# UCirKitBreadboardWithEverything3.net
KiCad netlist of a schematic drawn in EAGLE
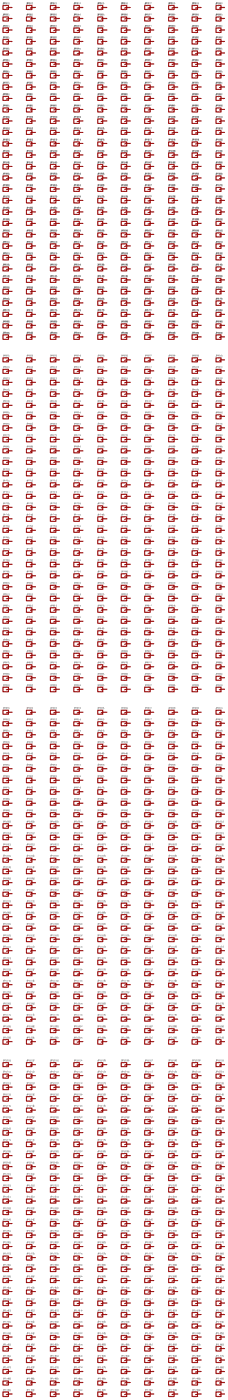
[diagram p0: schematic, sheet 1, overview]
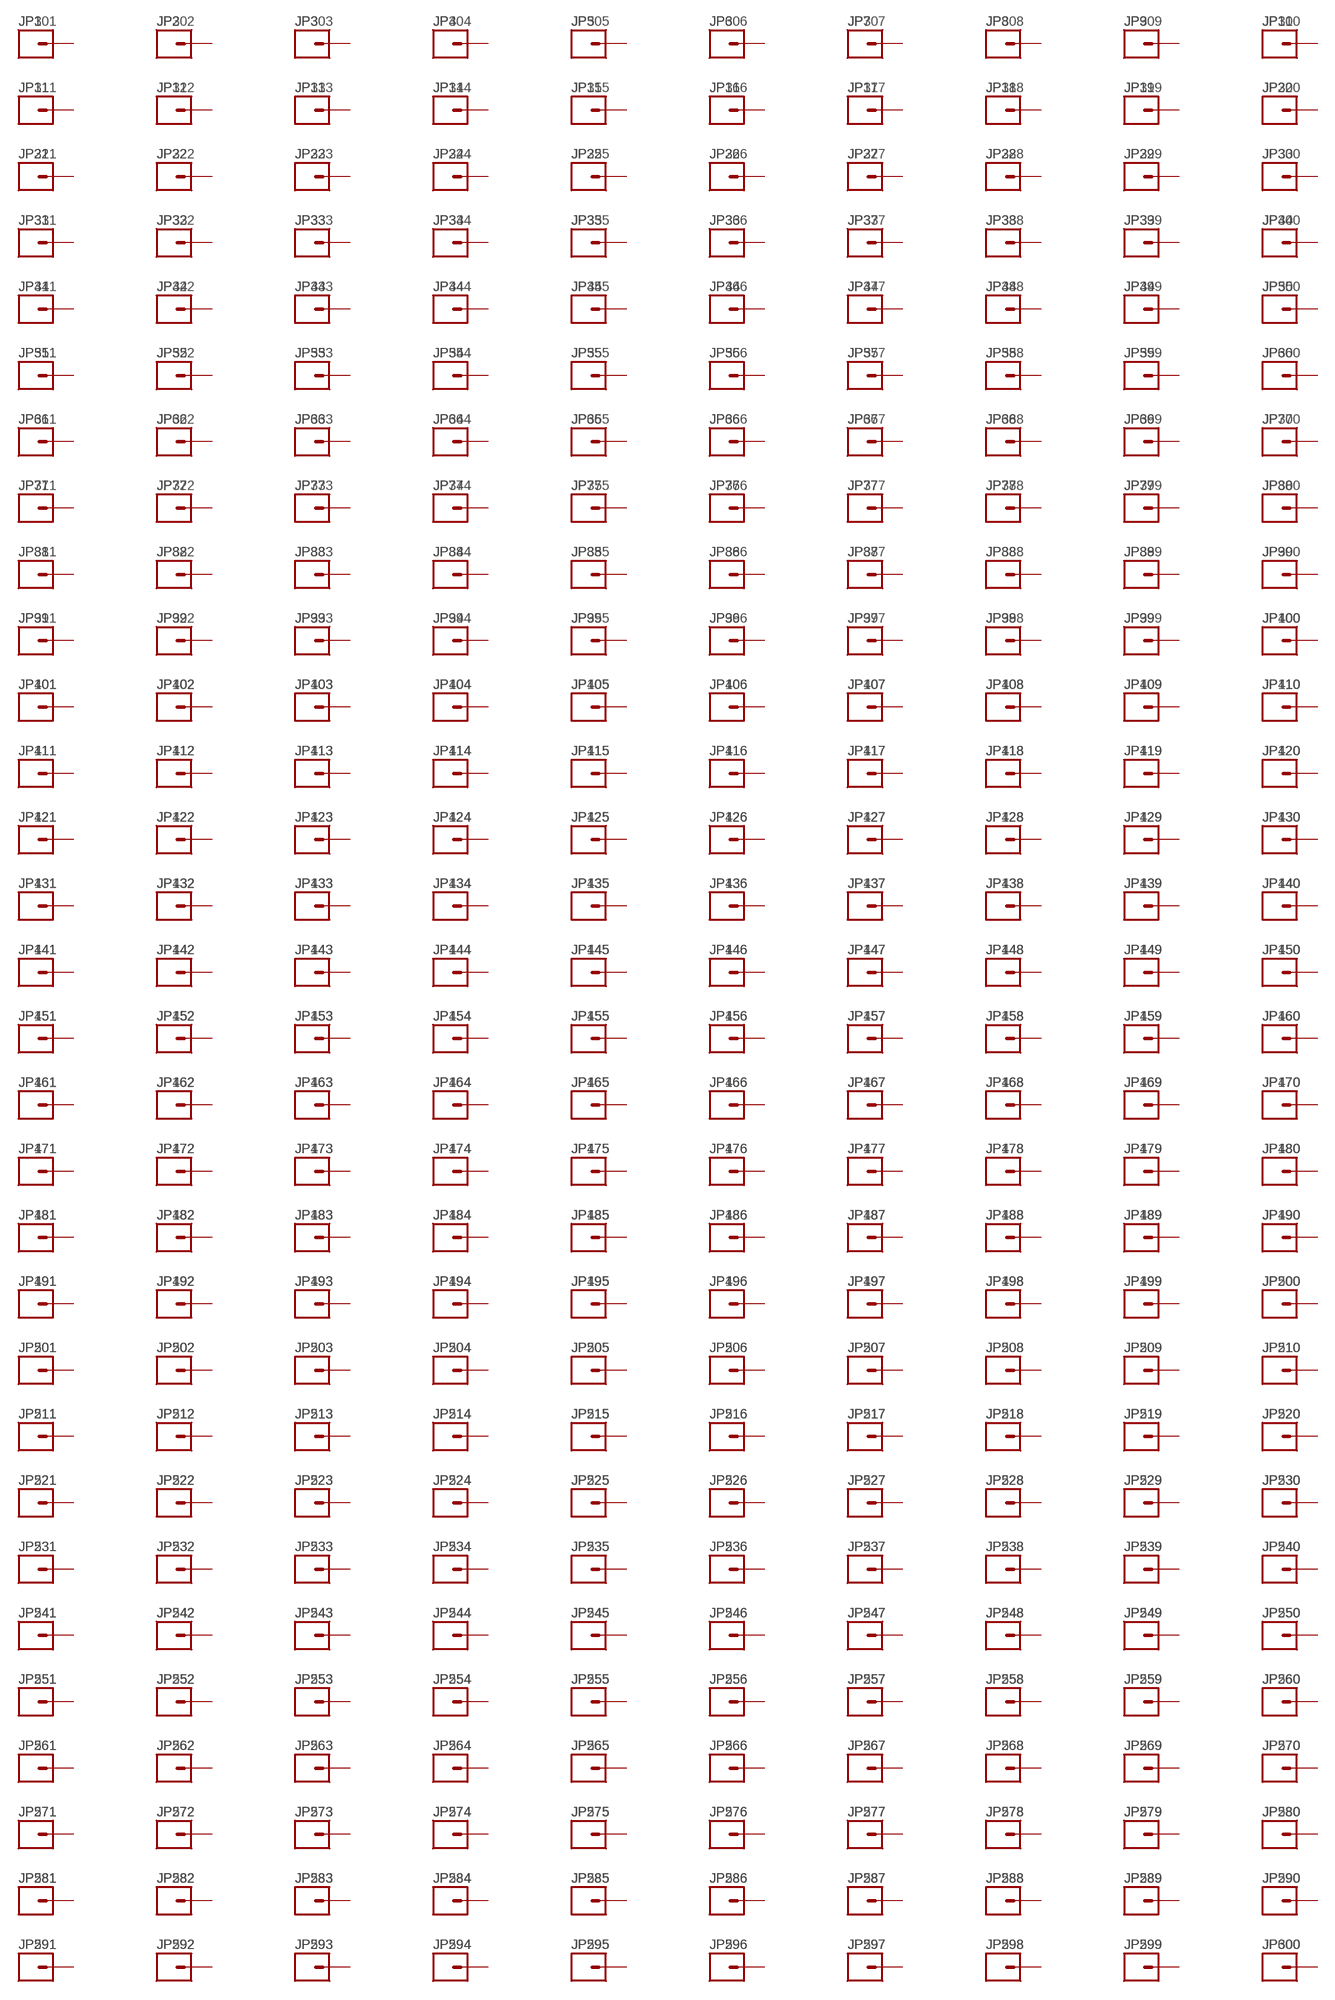
[diagram p1: schematic, sheet 1, part 1 of 4]
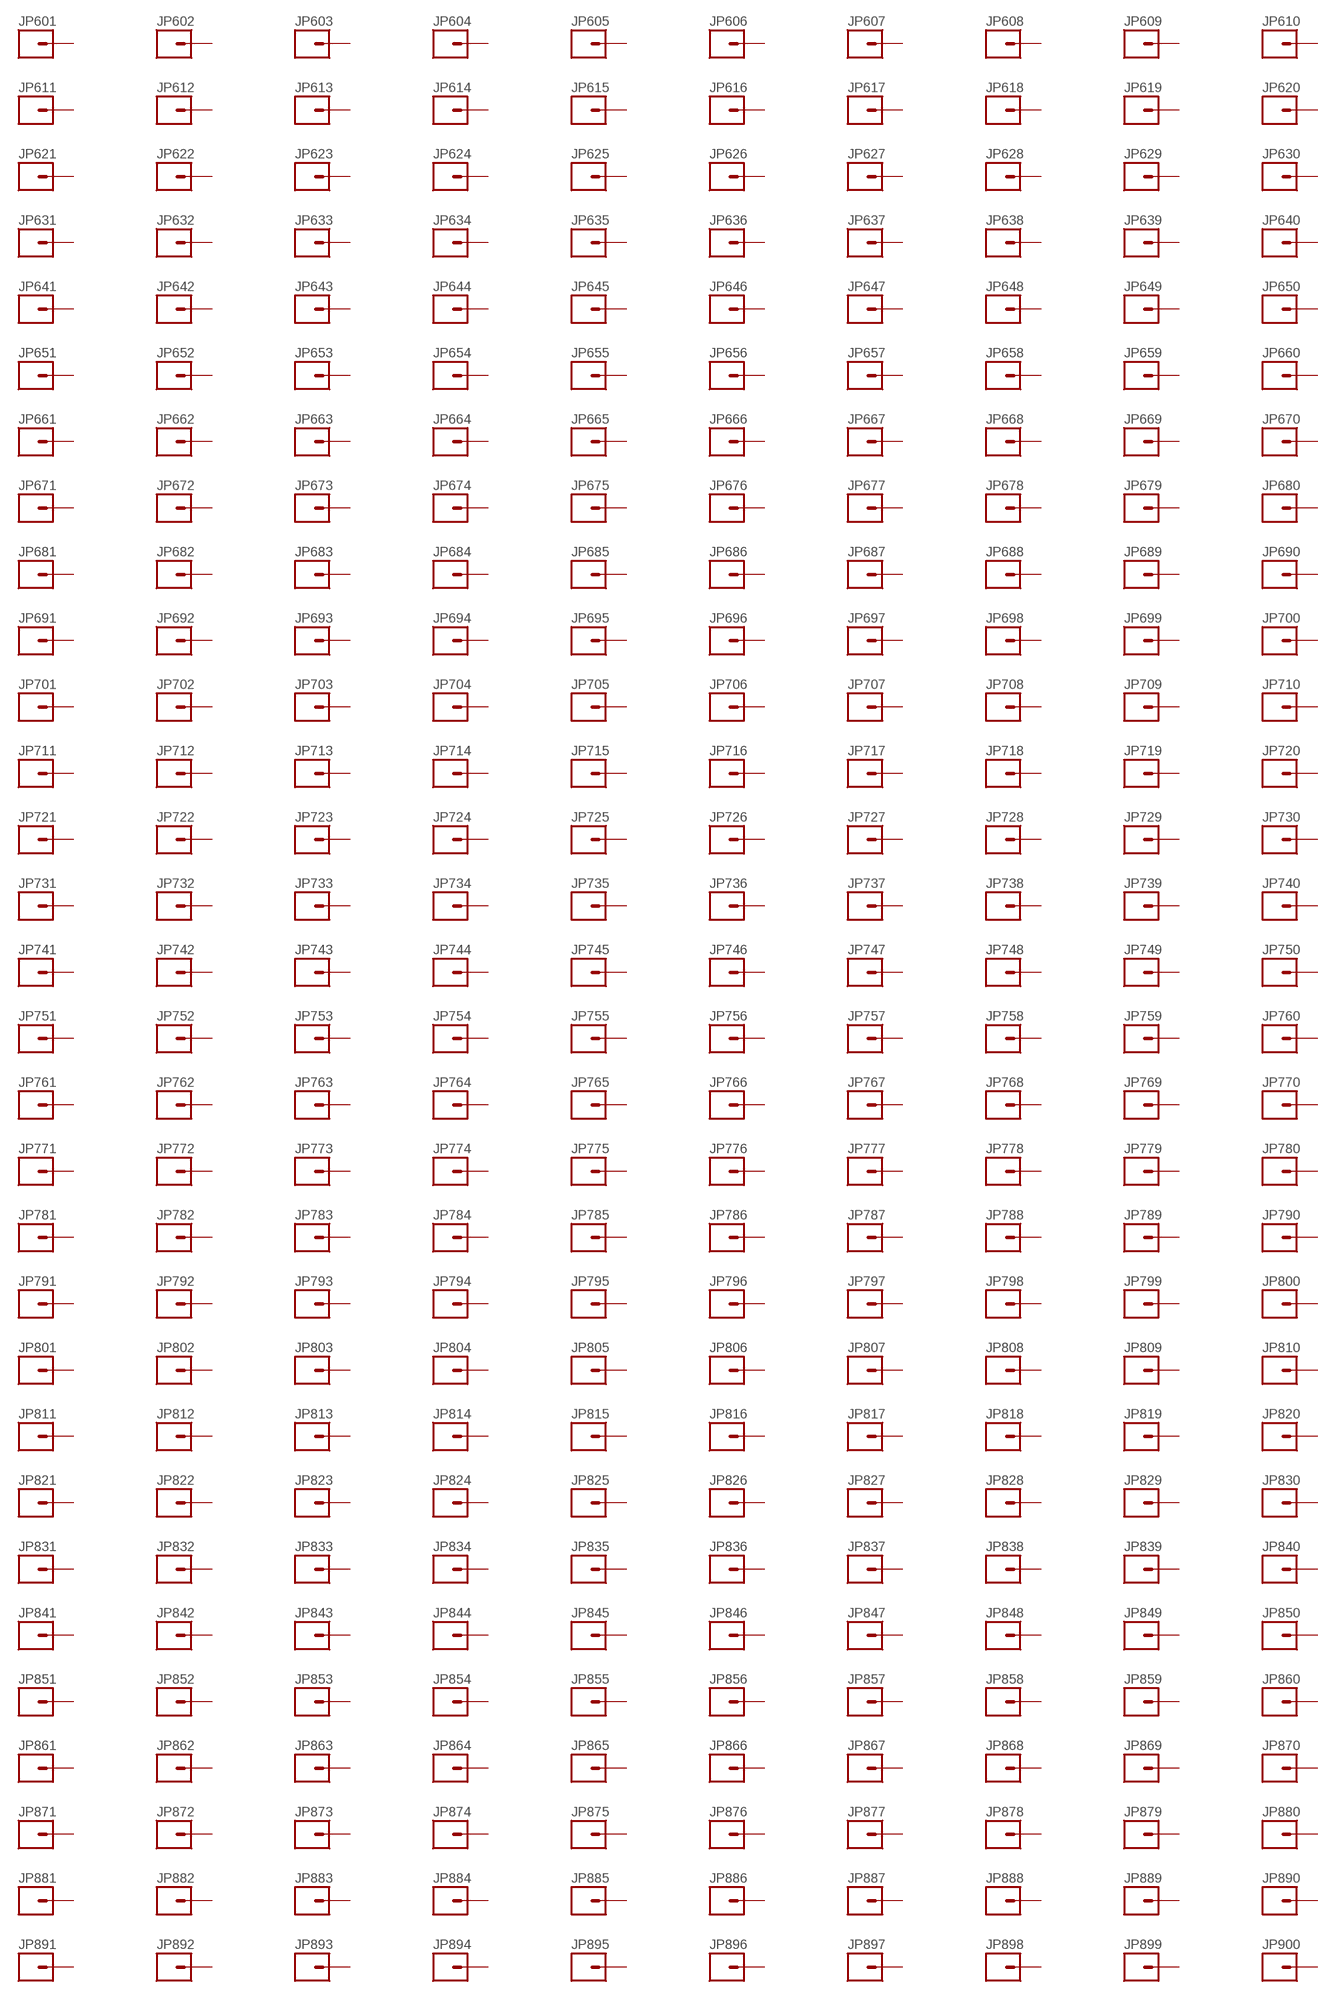
[diagram p2: schematic, sheet 1, part 2 of 4]
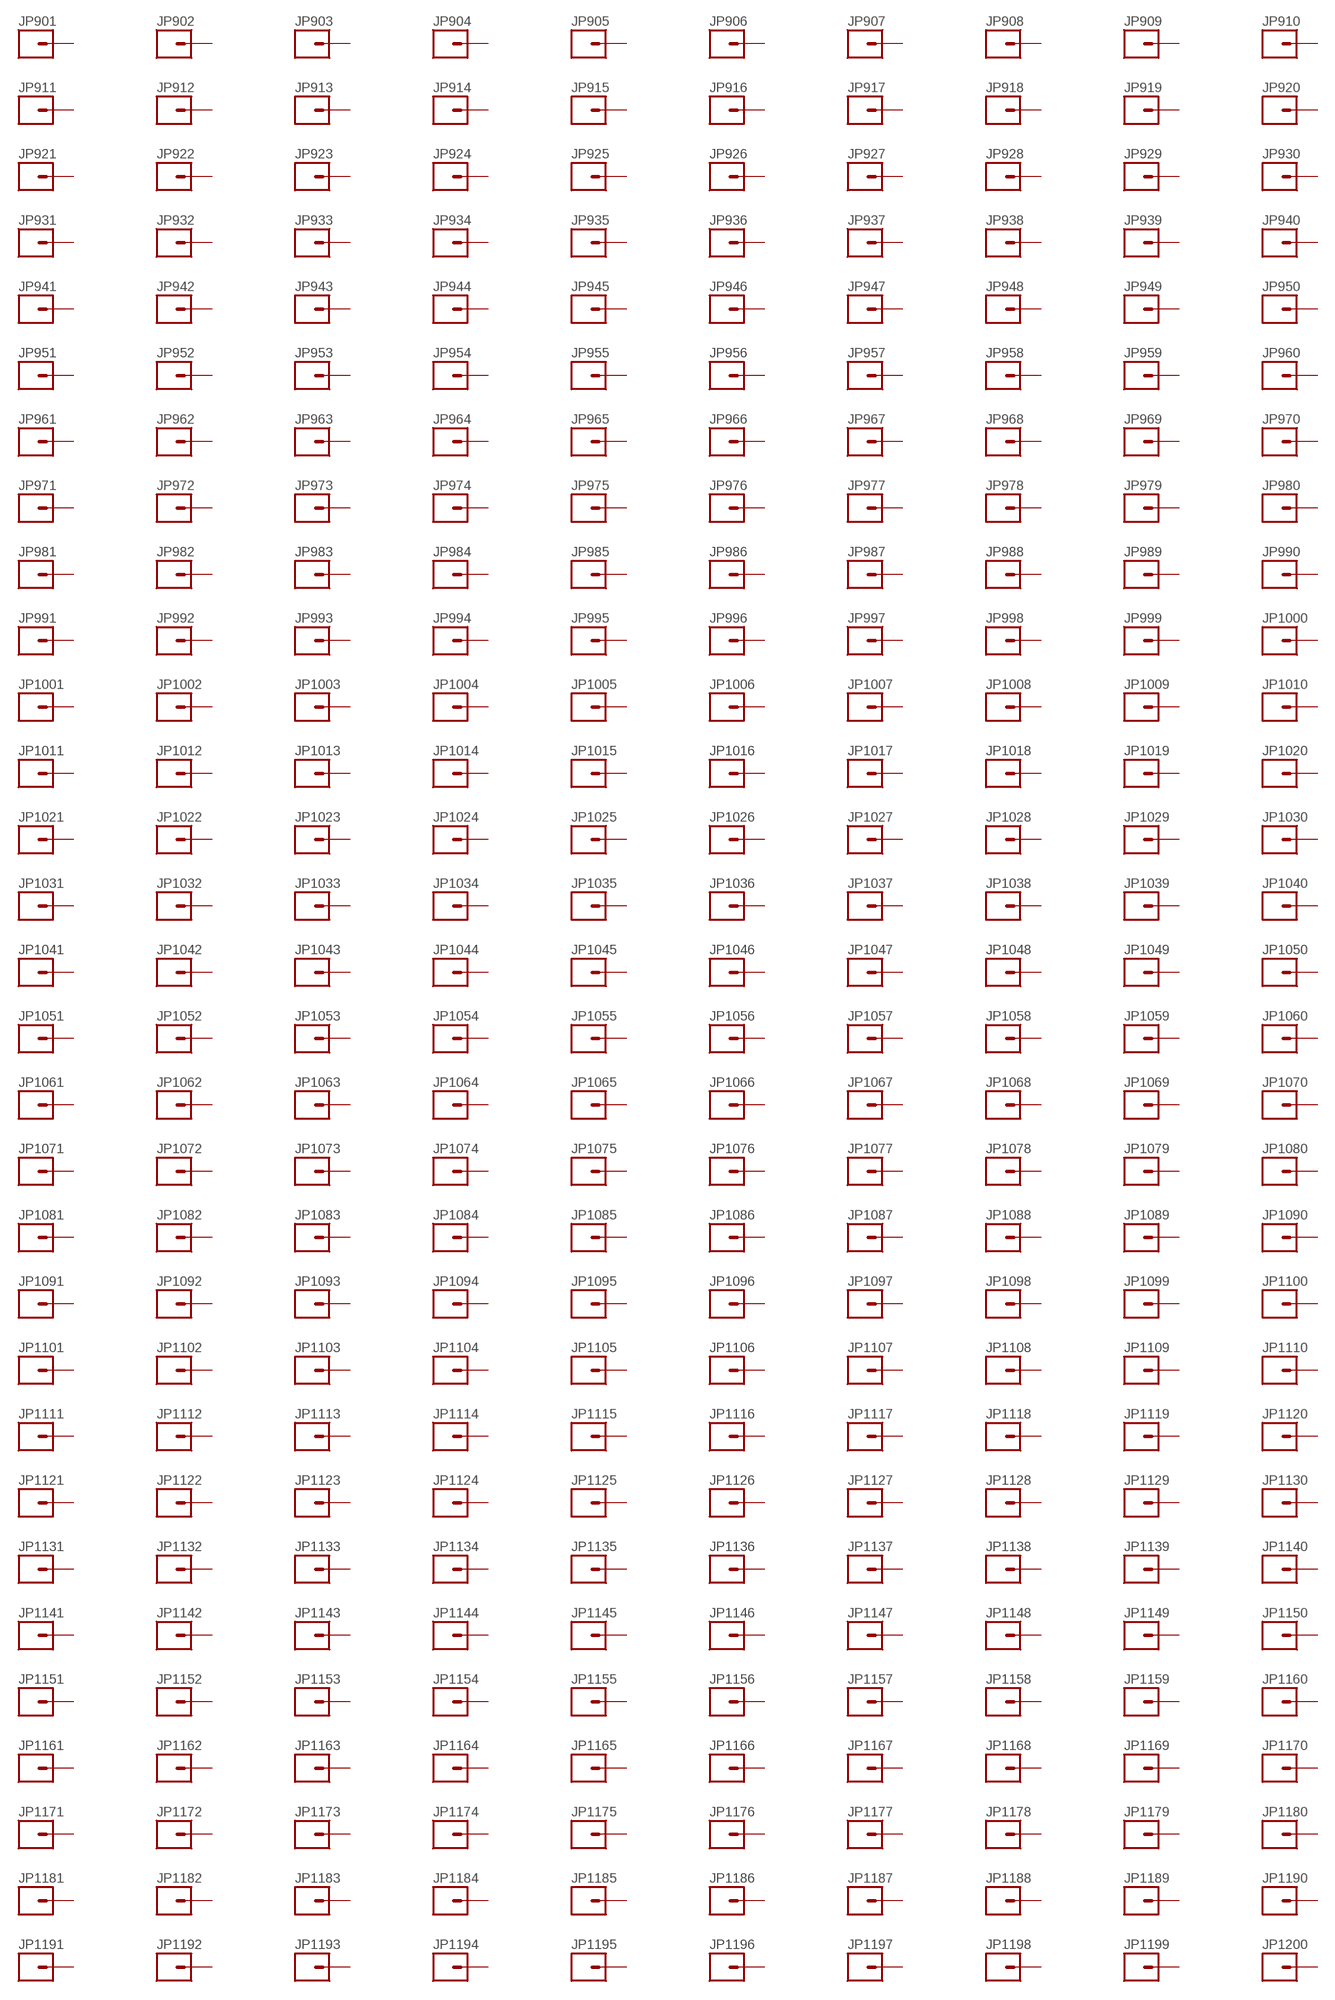
[diagram p3: schematic, sheet 1, part 3 of 4]
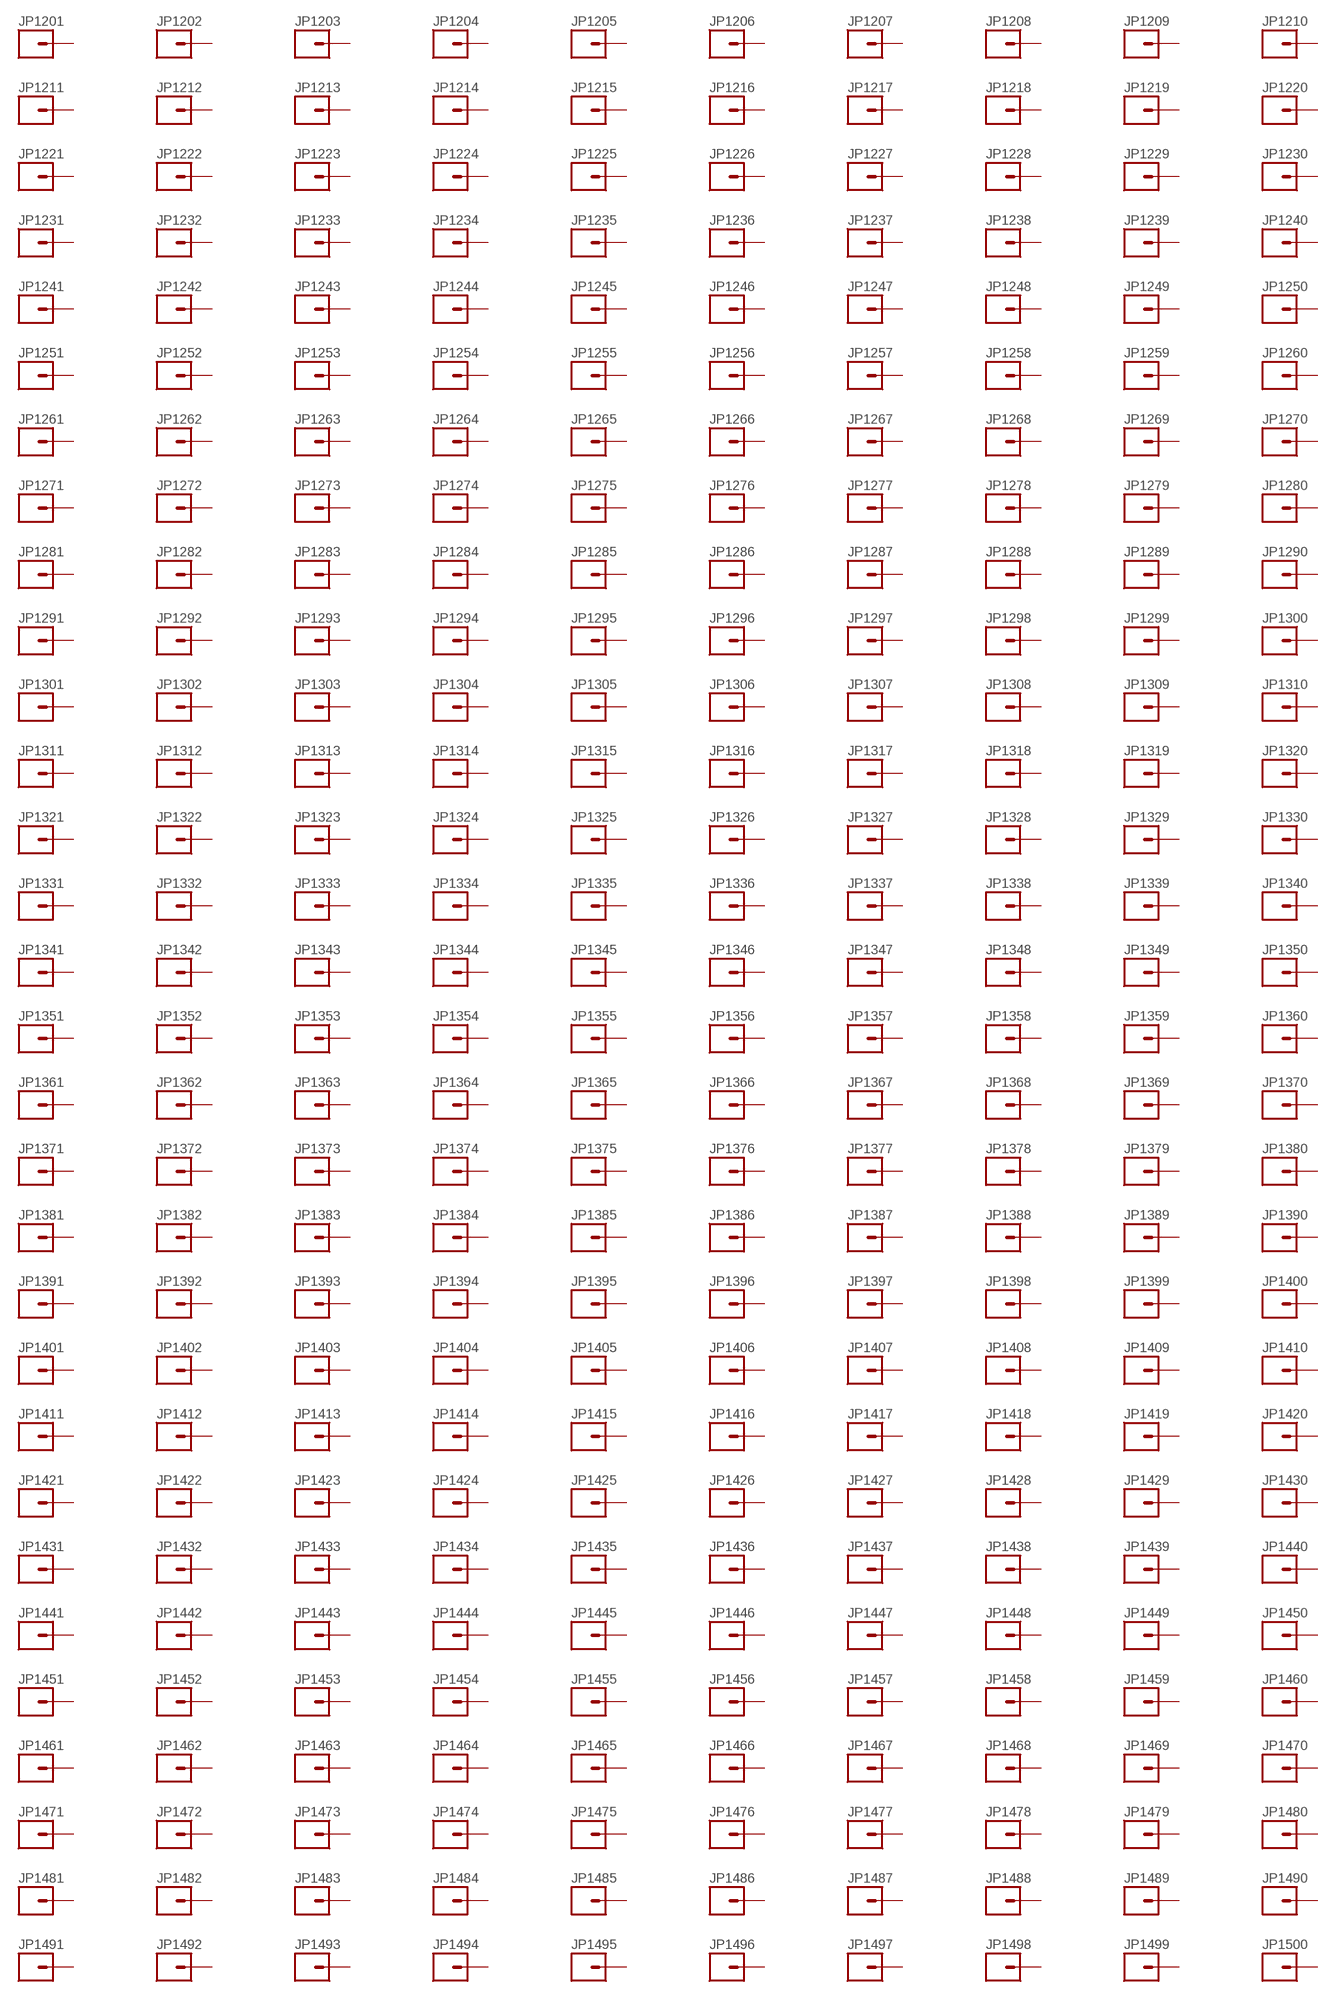
[diagram p4: schematic, sheet 1, part 4 of 4]

(export (version "E")
  (design (tool "Eeschema 10.0.6"))
  (components
    (comp (ref "JP1")
      (value "M01PTH_WITHOUT_TEXT")
      (footprint "eagle-import:1X01_WITHOUT_TEXT")
      (libsource (lib "eagle-import") (part "M01PTH_WITHOUT_TEXT"))
    )
    (comp (ref "JP2")
      (value "M01PTH_WITHOUT_TEXT")
      (footprint "eagle-import:1X01_WITHOUT_TEXT")
      (libsource (lib "eagle-import") (part "M01PTH_WITHOUT_TEXT"))
    )
    (comp (ref "JP3")
      (value "M01PTH_WITHOUT_TEXT")
      (footprint "eagle-import:1X01_WITHOUT_TEXT")
      (libsource (lib "eagle-import") (part "M01PTH_WITHOUT_TEXT"))
    )
    (comp (ref "JP4")
      (value "M01PTH_WITHOUT_TEXT")
      (footprint "eagle-import:1X01_WITHOUT_TEXT")
      (libsource (lib "eagle-import") (part "M01PTH_WITHOUT_TEXT"))
    )
    (comp (ref "JP5")
      (value "M01PTH_WITHOUT_TEXT")
      (footprint "eagle-import:1X01_WITHOUT_TEXT")
      (libsource (lib "eagle-import") (part "M01PTH_WITHOUT_TEXT"))
    )
    (comp (ref "JP6")
      (value "M01PTH_WITHOUT_TEXT")
      (footprint "eagle-import:1X01_WITHOUT_TEXT")
      (libsource (lib "eagle-import") (part "M01PTH_WITHOUT_TEXT"))
    )
    (comp (ref "JP7")
      (value "M01PTH_WITHOUT_TEXT")
      (footprint "eagle-import:1X01_WITHOUT_TEXT")
      (libsource (lib "eagle-import") (part "M01PTH_WITHOUT_TEXT"))
    )
    (comp (ref "JP8")
      (value "M01PTH_WITHOUT_TEXT")
      (footprint "eagle-import:1X01_WITHOUT_TEXT")
      (libsource (lib "eagle-import") (part "M01PTH_WITHOUT_TEXT"))
    )
    (comp (ref "JP9")
      (value "M01PTH_WITHOUT_TEXT")
      (footprint "eagle-import:1X01_WITHOUT_TEXT")
      (libsource (lib "eagle-import") (part "M01PTH_WITHOUT_TEXT"))
    )
    (comp (ref "JP10")
      (value "M01PTH_WITHOUT_TEXT")
      (footprint "eagle-import:1X01_WITHOUT_TEXT")
      (libsource (lib "eagle-import") (part "M01PTH_WITHOUT_TEXT"))
    )
    (comp (ref "JP11")
      (value "M01PTH_WITHOUT_TEXT")
      (footprint "eagle-import:1X01_WITHOUT_TEXT")
      (libsource (lib "eagle-import") (part "M01PTH_WITHOUT_TEXT"))
    )
    (comp (ref "JP12")
      (value "M01PTH_WITHOUT_TEXT")
      (footprint "eagle-import:1X01_WITHOUT_TEXT")
      (libsource (lib "eagle-import") (part "M01PTH_WITHOUT_TEXT"))
    )
    (comp (ref "JP13")
      (value "M01PTH_WITHOUT_TEXT")
      (footprint "eagle-import:1X01_WITHOUT_TEXT")
      (libsource (lib "eagle-import") (part "M01PTH_WITHOUT_TEXT"))
    )
    (comp (ref "JP14")
      (value "M01PTH_WITHOUT_TEXT")
      (footprint "eagle-import:1X01_WITHOUT_TEXT")
      (libsource (lib "eagle-import") (part "M01PTH_WITHOUT_TEXT"))
    )
    (comp (ref "JP15")
      (value "M01PTH_WITHOUT_TEXT")
      (footprint "eagle-import:1X01_WITHOUT_TEXT")
      (libsource (lib "eagle-import") (part "M01PTH_WITHOUT_TEXT"))
    )
    (comp (ref "JP16")
      (value "M01PTH_WITHOUT_TEXT")
      (footprint "eagle-import:1X01_WITHOUT_TEXT")
      (libsource (lib "eagle-import") (part "M01PTH_WITHOUT_TEXT"))
    )
    (comp (ref "JP17")
      (value "M01PTH_WITHOUT_TEXT")
      (footprint "eagle-import:1X01_WITHOUT_TEXT")
      (libsource (lib "eagle-import") (part "M01PTH_WITHOUT_TEXT"))
    )
    (comp (ref "JP18")
      (value "M01PTH_WITHOUT_TEXT")
      (footprint "eagle-import:1X01_WITHOUT_TEXT")
      (libsource (lib "eagle-import") (part "M01PTH_WITHOUT_TEXT"))
    )
    (comp (ref "JP19")
      (value "M01PTH_WITHOUT_TEXT")
      (footprint "eagle-import:1X01_WITHOUT_TEXT")
      (libsource (lib "eagle-import") (part "M01PTH_WITHOUT_TEXT"))
    )
    (comp (ref "JP20")
      (value "M01PTH_WITHOUT_TEXT")
      (footprint "eagle-import:1X01_WITHOUT_TEXT")
      (libsource (lib "eagle-import") (part "M01PTH_WITHOUT_TEXT"))
    )
    (comp (ref "JP21")
      (value "M01PTH_WITHOUT_TEXT")
      (footprint "eagle-import:1X01_WITHOUT_TEXT")
      (libsource (lib "eagle-import") (part "M01PTH_WITHOUT_TEXT"))
    )
    (comp (ref "JP22")
      (value "M01PTH_WITHOUT_TEXT")
      (footprint "eagle-import:1X01_WITHOUT_TEXT")
      (libsource (lib "eagle-import") (part "M01PTH_WITHOUT_TEXT"))
    )
    (comp (ref "JP23")
      (value "M01PTH_WITHOUT_TEXT")
      (footprint "eagle-import:1X01_WITHOUT_TEXT")
      (libsource (lib "eagle-import") (part "M01PTH_WITHOUT_TEXT"))
    )
    (comp (ref "JP24")
      (value "M01PTH_WITHOUT_TEXT")
      (footprint "eagle-import:1X01_WITHOUT_TEXT")
      (libsource (lib "eagle-import") (part "M01PTH_WITHOUT_TEXT"))
    )
    (comp (ref "JP25")
      (value "M01PTH_WITHOUT_TEXT")
      (footprint "eagle-import:1X01_WITHOUT_TEXT")
      (libsource (lib "eagle-import") (part "M01PTH_WITHOUT_TEXT"))
    )
    (comp (ref "JP26")
      (value "M01PTH_WITHOUT_TEXT")
      (footprint "eagle-import:1X01_WITHOUT_TEXT")
      (libsource (lib "eagle-import") (part "M01PTH_WITHOUT_TEXT"))
    )
    (comp (ref "JP27")
      (value "M01PTH_WITHOUT_TEXT")
      (footprint "eagle-import:1X01_WITHOUT_TEXT")
      (libsource (lib "eagle-import") (part "M01PTH_WITHOUT_TEXT"))
    )
    (comp (ref "JP28")
      (value "M01PTH_WITHOUT_TEXT")
      (footprint "eagle-import:1X01_WITHOUT_TEXT")
      (libsource (lib "eagle-import") (part "M01PTH_WITHOUT_TEXT"))
    )
    (comp (ref "JP29")
      (value "M01PTH_WITHOUT_TEXT")
      (footprint "eagle-import:1X01_WITHOUT_TEXT")
      (libsource (lib "eagle-import") (part "M01PTH_WITHOUT_TEXT"))
    )
    (comp (ref "JP30")
      (value "M01PTH_WITHOUT_TEXT")
      (footprint "eagle-import:1X01_WITHOUT_TEXT")
      (libsource (lib "eagle-import") (part "M01PTH_WITHOUT_TEXT"))
    )
    (comp (ref "JP31")
      (value "M01PTH_WITHOUT_TEXT")
      (footprint "eagle-import:1X01_WITHOUT_TEXT")
      (libsource (lib "eagle-import") (part "M01PTH_WITHOUT_TEXT"))
    )
    (comp (ref "JP32")
      (value "M01PTH_WITHOUT_TEXT")
      (footprint "eagle-import:1X01_WITHOUT_TEXT")
      (libsource (lib "eagle-import") (part "M01PTH_WITHOUT_TEXT"))
    )
    (comp (ref "JP33")
      (value "M01PTH_WITHOUT_TEXT")
      (footprint "eagle-import:1X01_WITHOUT_TEXT")
      (libsource (lib "eagle-import") (part "M01PTH_WITHOUT_TEXT"))
    )
    (comp (ref "JP34")
      (value "M01PTH_WITHOUT_TEXT")
      (footprint "eagle-import:1X01_WITHOUT_TEXT")
      (libsource (lib "eagle-import") (part "M01PTH_WITHOUT_TEXT"))
    )
    (comp (ref "JP35")
      (value "M01PTH_WITHOUT_TEXT")
      (footprint "eagle-import:1X01_WITHOUT_TEXT")
      (libsource (lib "eagle-import") (part "M01PTH_WITHOUT_TEXT"))
    )
    (comp (ref "JP36")
      (value "M01PTH_WITHOUT_TEXT")
      (footprint "eagle-import:1X01_WITHOUT_TEXT")
      (libsource (lib "eagle-import") (part "M01PTH_WITHOUT_TEXT"))
    )
    (comp (ref "JP37")
      (value "M01PTH_WITHOUT_TEXT")
      (footprint "eagle-import:1X01_WITHOUT_TEXT")
      (libsource (lib "eagle-import") (part "M01PTH_WITHOUT_TEXT"))
    )
    (comp (ref "JP38")
      (value "M01PTH_WITHOUT_TEXT")
      (footprint "eagle-import:1X01_WITHOUT_TEXT")
      (libsource (lib "eagle-import") (part "M01PTH_WITHOUT_TEXT"))
    )
    (comp (ref "JP39")
      (value "M01PTH_WITHOUT_TEXT")
      (footprint "eagle-import:1X01_WITHOUT_TEXT")
      (libsource (lib "eagle-import") (part "M01PTH_WITHOUT_TEXT"))
    )
    (comp (ref "JP40")
      (value "M01PTH_WITHOUT_TEXT")
      (footprint "eagle-import:1X01_WITHOUT_TEXT")
      (libsource (lib "eagle-import") (part "M01PTH_WITHOUT_TEXT"))
    )
    (comp (ref "JP41")
      (value "M01PTH_WITHOUT_TEXT")
      (footprint "eagle-import:1X01_WITHOUT_TEXT")
      (libsource (lib "eagle-import") (part "M01PTH_WITHOUT_TEXT"))
    )
    (comp (ref "JP42")
      (value "M01PTH_WITHOUT_TEXT")
      (footprint "eagle-import:1X01_WITHOUT_TEXT")
      (libsource (lib "eagle-import") (part "M01PTH_WITHOUT_TEXT"))
    )
    (comp (ref "JP43")
      (value "M01PTH_WITHOUT_TEXT")
      (footprint "eagle-import:1X01_WITHOUT_TEXT")
      (libsource (lib "eagle-import") (part "M01PTH_WITHOUT_TEXT"))
    )
    (comp (ref "JP44")
      (value "M01PTH_WITHOUT_TEXT")
      (footprint "eagle-import:1X01_WITHOUT_TEXT")
      (libsource (lib "eagle-import") (part "M01PTH_WITHOUT_TEXT"))
    )
    (comp (ref "JP45")
      (value "M01PTH_WITHOUT_TEXT")
      (footprint "eagle-import:1X01_WITHOUT_TEXT")
      (libsource (lib "eagle-import") (part "M01PTH_WITHOUT_TEXT"))
    )
    (comp (ref "JP46")
      (value "M01PTH_WITHOUT_TEXT")
      (footprint "eagle-import:1X01_WITHOUT_TEXT")
      (libsource (lib "eagle-import") (part "M01PTH_WITHOUT_TEXT"))
    )
    (comp (ref "JP47")
      (value "M01PTH_WITHOUT_TEXT")
      (footprint "eagle-import:1X01_WITHOUT_TEXT")
      (libsource (lib "eagle-import") (part "M01PTH_WITHOUT_TEXT"))
    )
    (comp (ref "JP48")
      (value "M01PTH_WITHOUT_TEXT")
      (footprint "eagle-import:1X01_WITHOUT_TEXT")
      (libsource (lib "eagle-import") (part "M01PTH_WITHOUT_TEXT"))
    )
    (comp (ref "JP49")
      (value "M01PTH_WITHOUT_TEXT")
      (footprint "eagle-import:1X01_WITHOUT_TEXT")
      (libsource (lib "eagle-import") (part "M01PTH_WITHOUT_TEXT"))
    )
    (comp (ref "JP50")
      (value "M01PTH_WITHOUT_TEXT")
      (footprint "eagle-import:1X01_WITHOUT_TEXT")
      (libsource (lib "eagle-import") (part "M01PTH_WITHOUT_TEXT"))
    )
    (comp (ref "JP51")
      (value "M01PTH_WITHOUT_TEXT")
      (footprint "eagle-import:1X01_WITHOUT_TEXT")
      (libsource (lib "eagle-import") (part "M01PTH_WITHOUT_TEXT"))
    )
    (comp (ref "JP52")
      (value "M01PTH_WITHOUT_TEXT")
      (footprint "eagle-import:1X01_WITHOUT_TEXT")
      (libsource (lib "eagle-import") (part "M01PTH_WITHOUT_TEXT"))
    )
    (comp (ref "JP53")
      (value "M01PTH_WITHOUT_TEXT")
      (footprint "eagle-import:1X01_WITHOUT_TEXT")
      (libsource (lib "eagle-import") (part "M01PTH_WITHOUT_TEXT"))
    )
    (comp (ref "JP54")
      (value "M01PTH_WITHOUT_TEXT")
      (footprint "eagle-import:1X01_WITHOUT_TEXT")
      (libsource (lib "eagle-import") (part "M01PTH_WITHOUT_TEXT"))
    )
    (comp (ref "JP55")
      (value "M01PTH_WITHOUT_TEXT")
      (footprint "eagle-import:1X01_WITHOUT_TEXT")
      (libsource (lib "eagle-import") (part "M01PTH_WITHOUT_TEXT"))
    )
    (comp (ref "JP56")
      (value "M01PTH_WITHOUT_TEXT")
      (footprint "eagle-import:1X01_WITHOUT_TEXT")
      (libsource (lib "eagle-import") (part "M01PTH_WITHOUT_TEXT"))
    )
    (comp (ref "JP57")
      (value "M01PTH_WITHOUT_TEXT")
      (footprint "eagle-import:1X01_WITHOUT_TEXT")
      (libsource (lib "eagle-import") (part "M01PTH_WITHOUT_TEXT"))
    )
    (comp (ref "JP58")
      (value "M01PTH_WITHOUT_TEXT")
      (footprint "eagle-import:1X01_WITHOUT_TEXT")
      (libsource (lib "eagle-import") (part "M01PTH_WITHOUT_TEXT"))
    )
    (comp (ref "JP59")
      (value "M01PTH_WITHOUT_TEXT")
      (footprint "eagle-import:1X01_WITHOUT_TEXT")
      (libsource (lib "eagle-import") (part "M01PTH_WITHOUT_TEXT"))
    )
    (comp (ref "JP60")
      (value "M01PTH_WITHOUT_TEXT")
      (footprint "eagle-import:1X01_WITHOUT_TEXT")
      (libsource (lib "eagle-import") (part "M01PTH_WITHOUT_TEXT"))
    )
    (comp (ref "JP61")
      (value "M01PTH_WITHOUT_TEXT")
      (footprint "eagle-import:1X01_WITHOUT_TEXT")
      (libsource (lib "eagle-import") (part "M01PTH_WITHOUT_TEXT"))
    )
    (comp (ref "JP62")
      (value "M01PTH_WITHOUT_TEXT")
      (footprint "eagle-import:1X01_WITHOUT_TEXT")
      (libsource (lib "eagle-import") (part "M01PTH_WITHOUT_TEXT"))
    )
    (comp (ref "JP63")
      (value "M01PTH_WITHOUT_TEXT")
      (footprint "eagle-import:1X01_WITHOUT_TEXT")
      (libsource (lib "eagle-import") (part "M01PTH_WITHOUT_TEXT"))
    )
    (comp (ref "JP64")
      (value "M01PTH_WITHOUT_TEXT")
      (footprint "eagle-import:1X01_WITHOUT_TEXT")
      (libsource (lib "eagle-import") (part "M01PTH_WITHOUT_TEXT"))
    )
    (comp (ref "JP65")
      (value "M01PTH_WITHOUT_TEXT")
      (footprint "eagle-import:1X01_WITHOUT_TEXT")
      (libsource (lib "eagle-import") (part "M01PTH_WITHOUT_TEXT"))
    )
    (comp (ref "JP66")
      (value "M01PTH_WITHOUT_TEXT")
      (footprint "eagle-import:1X01_WITHOUT_TEXT")
      (libsource (lib "eagle-import") (part "M01PTH_WITHOUT_TEXT"))
    )
    (comp (ref "JP67")
      (value "M01PTH_WITHOUT_TEXT")
      (footprint "eagle-import:1X01_WITHOUT_TEXT")
      (libsource (lib "eagle-import") (part "M01PTH_WITHOUT_TEXT"))
    )
    (comp (ref "JP68")
      (value "M01PTH_WITHOUT_TEXT")
      (footprint "eagle-import:1X01_WITHOUT_TEXT")
      (libsource (lib "eagle-import") (part "M01PTH_WITHOUT_TEXT"))
    )
    (comp (ref "JP69")
      (value "M01PTH_WITHOUT_TEXT")
      (footprint "eagle-import:1X01_WITHOUT_TEXT")
      (libsource (lib "eagle-import") (part "M01PTH_WITHOUT_TEXT"))
    )
    (comp (ref "JP70")
      (value "M01PTH_WITHOUT_TEXT")
      (footprint "eagle-import:1X01_WITHOUT_TEXT")
      (libsource (lib "eagle-import") (part "M01PTH_WITHOUT_TEXT"))
    )
    (comp (ref "JP71")
      (value "M01PTH_WITHOUT_TEXT")
      (footprint "eagle-import:1X01_WITHOUT_TEXT")
      (libsource (lib "eagle-import") (part "M01PTH_WITHOUT_TEXT"))
    )
    (comp (ref "JP72")
      (value "M01PTH_WITHOUT_TEXT")
      (footprint "eagle-import:1X01_WITHOUT_TEXT")
      (libsource (lib "eagle-import") (part "M01PTH_WITHOUT_TEXT"))
    )
    (comp (ref "JP73")
      (value "M01PTH_WITHOUT_TEXT")
      (footprint "eagle-import:1X01_WITHOUT_TEXT")
      (libsource (lib "eagle-import") (part "M01PTH_WITHOUT_TEXT"))
    )
    (comp (ref "JP74")
      (value "M01PTH_WITHOUT_TEXT")
      (footprint "eagle-import:1X01_WITHOUT_TEXT")
      (libsource (lib "eagle-import") (part "M01PTH_WITHOUT_TEXT"))
    )
    (comp (ref "JP75")
      (value "M01PTH_WITHOUT_TEXT")
      (footprint "eagle-import:1X01_WITHOUT_TEXT")
      (libsource (lib "eagle-import") (part "M01PTH_WITHOUT_TEXT"))
    )
    (comp (ref "JP76")
      (value "M01PTH_WITHOUT_TEXT")
      (footprint "eagle-import:1X01_WITHOUT_TEXT")
      (libsource (lib "eagle-import") (part "M01PTH_WITHOUT_TEXT"))
    )
    (comp (ref "JP77")
      (value "M01PTH_WITHOUT_TEXT")
      (footprint "eagle-import:1X01_WITHOUT_TEXT")
      (libsource (lib "eagle-import") (part "M01PTH_WITHOUT_TEXT"))
    )
    (comp (ref "JP78")
      (value "M01PTH_WITHOUT_TEXT")
      (footprint "eagle-import:1X01_WITHOUT_TEXT")
      (libsource (lib "eagle-import") (part "M01PTH_WITHOUT_TEXT"))
    )
    (comp (ref "JP79")
      (value "M01PTH_WITHOUT_TEXT")
      (footprint "eagle-import:1X01_WITHOUT_TEXT")
      (libsource (lib "eagle-import") (part "M01PTH_WITHOUT_TEXT"))
    )
    (comp (ref "JP80")
      (value "M01PTH_WITHOUT_TEXT")
      (footprint "eagle-import:1X01_WITHOUT_TEXT")
      (libsource (lib "eagle-import") (part "M01PTH_WITHOUT_TEXT"))
    )
    (comp (ref "JP81")
      (value "M01PTH_WITHOUT_TEXT")
      (footprint "eagle-import:1X01_WITHOUT_TEXT")
      (libsource (lib "eagle-import") (part "M01PTH_WITHOUT_TEXT"))
    )
    (comp (ref "JP82")
      (value "M01PTH_WITHOUT_TEXT")
      (footprint "eagle-import:1X01_WITHOUT_TEXT")
      (libsource (lib "eagle-import") (part "M01PTH_WITHOUT_TEXT"))
    )
    (comp (ref "JP83")
      (value "M01PTH_WITHOUT_TEXT")
      (footprint "eagle-import:1X01_WITHOUT_TEXT")
      (libsource (lib "eagle-import") (part "M01PTH_WITHOUT_TEXT"))
    )
    (comp (ref "JP84")
      (value "M01PTH_WITHOUT_TEXT")
      (footprint "eagle-import:1X01_WITHOUT_TEXT")
      (libsource (lib "eagle-import") (part "M01PTH_WITHOUT_TEXT"))
    )
    (comp (ref "JP85")
      (value "M01PTH_WITHOUT_TEXT")
      (footprint "eagle-import:1X01_WITHOUT_TEXT")
      (libsource (lib "eagle-import") (part "M01PTH_WITHOUT_TEXT"))
    )
    (comp (ref "JP86")
      (value "M01PTH_WITHOUT_TEXT")
      (footprint "eagle-import:1X01_WITHOUT_TEXT")
      (libsource (lib "eagle-import") (part "M01PTH_WITHOUT_TEXT"))
    )
    (comp (ref "JP87")
      (value "M01PTH_WITHOUT_TEXT")
      (footprint "eagle-import:1X01_WITHOUT_TEXT")
      (libsource (lib "eagle-import") (part "M01PTH_WITHOUT_TEXT"))
    )
    (comp (ref "JP88")
      (value "M01PTH_WITHOUT_TEXT")
      (footprint "eagle-import:1X01_WITHOUT_TEXT")
      (libsource (lib "eagle-import") (part "M01PTH_WITHOUT_TEXT"))
    )
    (comp (ref "JP89")
      (value "M01PTH_WITHOUT_TEXT")
      (footprint "eagle-import:1X01_WITHOUT_TEXT")
      (libsource (lib "eagle-import") (part "M01PTH_WITHOUT_TEXT"))
    )
    (comp (ref "JP90")
      (value "M01PTH_WITHOUT_TEXT")
      (footprint "eagle-import:1X01_WITHOUT_TEXT")
      (libsource (lib "eagle-import") (part "M01PTH_WITHOUT_TEXT"))
    )
    (comp (ref "JP91")
      (value "M01PTH_WITHOUT_TEXT")
      (footprint "eagle-import:1X01_WITHOUT_TEXT")
      (libsource (lib "eagle-import") (part "M01PTH_WITHOUT_TEXT"))
    )
    (comp (ref "JP92")
      (value "M01PTH_WITHOUT_TEXT")
      (footprint "eagle-import:1X01_WITHOUT_TEXT")
      (libsource (lib "eagle-import") (part "M01PTH_WITHOUT_TEXT"))
    )
    (comp (ref "JP93")
      (value "M01PTH_WITHOUT_TEXT")
      (footprint "eagle-import:1X01_WITHOUT_TEXT")
      (libsource (lib "eagle-import") (part "M01PTH_WITHOUT_TEXT"))
    )
    (comp (ref "JP94")
      (value "M01PTH_WITHOUT_TEXT")
      (footprint "eagle-import:1X01_WITHOUT_TEXT")
      (libsource (lib "eagle-import") (part "M01PTH_WITHOUT_TEXT"))
    )
    (comp (ref "JP95")
      (value "M01PTH_WITHOUT_TEXT")
      (footprint "eagle-import:1X01_WITHOUT_TEXT")
      (libsource (lib "eagle-import") (part "M01PTH_WITHOUT_TEXT"))
    )
    (comp (ref "JP96")
      (value "M01PTH_WITHOUT_TEXT")
      (footprint "eagle-import:1X01_WITHOUT_TEXT")
      (libsource (lib "eagle-import") (part "M01PTH_WITHOUT_TEXT"))
    )
    (comp (ref "JP97")
      (value "M01PTH_WITHOUT_TEXT")
      (footprint "eagle-import:1X01_WITHOUT_TEXT")
      (libsource (lib "eagle-import") (part "M01PTH_WITHOUT_TEXT"))
    )
    (comp (ref "JP98")
      (value "M01PTH_WITHOUT_TEXT")
      (footprint "eagle-import:1X01_WITHOUT_TEXT")
      (libsource (lib "eagle-import") (part "M01PTH_WITHOUT_TEXT"))
    )
    (comp (ref "JP99")
      (value "M01PTH_WITHOUT_TEXT")
      (footprint "eagle-import:1X01_WITHOUT_TEXT")
      (libsource (lib "eagle-import") (part "M01PTH_WITHOUT_TEXT"))
    )
    (comp (ref "JP100")
      (value "M01PTH_WITHOUT_TEXT")
      (footprint "eagle-import:1X01_WITHOUT_TEXT")
      (libsource (lib "eagle-import") (part "M01PTH_WITHOUT_TEXT"))
    )
    (comp (ref "JP101")
      (value "M01PTH_WITHOUT_TEXT")
      (footprint "eagle-import:1X01_WITHOUT_TEXT")
      (libsource (lib "eagle-import") (part "M01PTH_WITHOUT_TEXT"))
    )
    (comp (ref "JP102")
      (value "M01PTH_WITHOUT_TEXT")
      (footprint "eagle-import:1X01_WITHOUT_TEXT")
      (libsource (lib "eagle-import") (part "M01PTH_WITHOUT_TEXT"))
    )
    (comp (ref "JP103")
      (value "M01PTH_WITHOUT_TEXT")
      (footprint "eagle-import:1X01_WITHOUT_TEXT")
      (libsource (lib "eagle-import") (part "M01PTH_WITHOUT_TEXT"))
    )
    (comp (ref "JP104")
      (value "M01PTH_WITHOUT_TEXT")
      (footprint "eagle-import:1X01_WITHOUT_TEXT")
      (libsource (lib "eagle-import") (part "M01PTH_WITHOUT_TEXT"))
    )
    (comp (ref "JP105")
      (value "M01PTH_WITHOUT_TEXT")
      (footprint "eagle-import:1X01_WITHOUT_TEXT")
      (libsource (lib "eagle-import") (part "M01PTH_WITHOUT_TEXT"))
    )
    (comp (ref "JP106")
      (value "M01PTH_WITHOUT_TEXT")
      (footprint "eagle-import:1X01_WITHOUT_TEXT")
      (libsource (lib "eagle-import") (part "M01PTH_WITHOUT_TEXT"))
    )
    (comp (ref "JP107")
      (value "M01PTH_WITHOUT_TEXT")
      (footprint "eagle-import:1X01_WITHOUT_TEXT")
      (libsource (lib "eagle-import") (part "M01PTH_WITHOUT_TEXT"))
    )
    (comp (ref "JP108")
      (value "M01PTH_WITHOUT_TEXT")
      (footprint "eagle-import:1X01_WITHOUT_TEXT")
      (libsource (lib "eagle-import") (part "M01PTH_WITHOUT_TEXT"))
    )
    (comp (ref "JP109")
      (value "M01PTH_WITHOUT_TEXT")
      (footprint "eagle-import:1X01_WITHOUT_TEXT")
      (libsource (lib "eagle-import") (part "M01PTH_WITHOUT_TEXT"))
    )
    (comp (ref "JP110")
      (value "M01PTH_WITHOUT_TEXT")
      (footprint "eagle-import:1X01_WITHOUT_TEXT")
      (libsource (lib "eagle-import") (part "M01PTH_WITHOUT_TEXT"))
    )
    (comp (ref "JP111")
      (value "M01PTH_WITHOUT_TEXT")
      (footprint "eagle-import:1X01_WITHOUT_TEXT")
      (libsource (lib "eagle-import") (part "M01PTH_WITHOUT_TEXT"))
    )
    (comp (ref "JP112")
      (value "M01PTH_WITHOUT_TEXT")
      (footprint "eagle-import:1X01_WITHOUT_TEXT")
      (libsource (lib "eagle-import") (part "M01PTH_WITHOUT_TEXT"))
    )
    (comp (ref "JP113")
      (value "M01PTH_WITHOUT_TEXT")
      (footprint "eagle-import:1X01_WITHOUT_TEXT")
      (libsource (lib "eagle-import") (part "M01PTH_WITHOUT_TEXT"))
    )
    (comp (ref "JP114")
      (value "M01PTH_WITHOUT_TEXT")
      (footprint "eagle-import:1X01_WITHOUT_TEXT")
      (libsource (lib "eagle-import") (part "M01PTH_WITHOUT_TEXT"))
    )
    (comp (ref "JP115")
      (value "M01PTH_WITHOUT_TEXT")
      (footprint "eagle-import:1X01_WITHOUT_TEXT")
      (libsource (lib "eagle-import") (part "M01PTH_WITHOUT_TEXT"))
    )
    (comp (ref "JP116")
      (value "M01PTH_WITHOUT_TEXT")
      (footprint "eagle-import:1X01_WITHOUT_TEXT")
      (libsource (lib "eagle-import") (part "M01PTH_WITHOUT_TEXT"))
    )
    (comp (ref "JP117")
      (value "M01PTH_WITHOUT_TEXT")
      (footprint "eagle-import:1X01_WITHOUT_TEXT")
      (libsource (lib "eagle-import") (part "M01PTH_WITHOUT_TEXT"))
    )
    (comp (ref "JP118")
      (value "M01PTH_WITHOUT_TEXT")
      (footprint "eagle-import:1X01_WITHOUT_TEXT")
      (libsource (lib "eagle-import") (part "M01PTH_WITHOUT_TEXT"))
    )
    (comp (ref "JP119")
      (value "M01PTH_WITHOUT_TEXT")
      (footprint "eagle-import:1X01_WITHOUT_TEXT")
      (libsource (lib "eagle-import") (part "M01PTH_WITHOUT_TEXT"))
    )
    (comp (ref "JP120")
      (value "M01PTH_WITHOUT_TEXT")
      (footprint "eagle-import:1X01_WITHOUT_TEXT")
      (libsource (lib "eagle-import") (part "M01PTH_WITHOUT_TEXT"))
    )
    (comp (ref "JP121")
      (value "M01PTH_WITHOUT_TEXT")
      (footprint "eagle-import:1X01_WITHOUT_TEXT")
      (libsource (lib "eagle-import") (part "M01PTH_WITHOUT_TEXT"))
    )
    (comp (ref "JP122")
      (value "M01PTH_WITHOUT_TEXT")
      (footprint "eagle-import:1X01_WITHOUT_TEXT")
      (libsource (lib "eagle-import") (part "M01PTH_WITHOUT_TEXT"))
    )
    (comp (ref "JP123")
      (value "M01PTH_WITHOUT_TEXT")
      (footprint "eagle-import:1X01_WITHOUT_TEXT")
      (libsource (lib "eagle-import") (part "M01PTH_WITHOUT_TEXT"))
    )
    (comp (ref "JP124")
      (value "M01PTH_WITHOUT_TEXT")
      (footprint "eagle-import:1X01_WITHOUT_TEXT")
      (libsource (lib "eagle-import") (part "M01PTH_WITHOUT_TEXT"))
    )
    (comp (ref "JP125")
      (value "M01PTH_WITHOUT_TEXT")
      (footprint "eagle-import:1X01_WITHOUT_TEXT")
      (libsource (lib "eagle-import") (part "M01PTH_WITHOUT_TEXT"))
    )
    (comp (ref "JP126")
      (value "M01PTH_WITHOUT_TEXT")
      (footprint "eagle-import:1X01_WITHOUT_TEXT")
      (libsource (lib "eagle-import") (part "M01PTH_WITHOUT_TEXT"))
    )
    (comp (ref "JP127")
      (value "M01PTH_WITHOUT_TEXT")
      (footprint "eagle-import:1X01_WITHOUT_TEXT")
      (libsource (lib "eagle-import") (part "M01PTH_WITHOUT_TEXT"))
    )
    (comp (ref "JP128")
      (value "M01PTH_WITHOUT_TEXT")
      (footprint "eagle-import:1X01_WITHOUT_TEXT")
      (libsource (lib "eagle-import") (part "M01PTH_WITHOUT_TEXT"))
    )
    (comp (ref "JP129")
      (value "M01PTH_WITHOUT_TEXT")
      (footprint "eagle-import:1X01_WITHOUT_TEXT")
      (libsource (lib "eagle-import") (part "M01PTH_WITHOUT_TEXT"))
    )
    (comp (ref "JP130")
      (value "M01PTH_WITHOUT_TEXT")
      (footprint "eagle-import:1X01_WITHOUT_TEXT")
      (libsource (lib "eagle-import") (part "M01PTH_WITHOUT_TEXT"))
    )
    (comp (ref "JP131")
      (value "M01PTH_WITHOUT_TEXT")
      (footprint "eagle-import:1X01_WITHOUT_TEXT")
      (libsource (lib "eagle-import") (part "M01PTH_WITHOUT_TEXT"))
    )
    (comp (ref "JP132")
      (value "M01PTH_WITHOUT_TEXT")
      (footprint "eagle-import:1X01_WITHOUT_TEXT")
      (libsource (lib "eagle-import") (part "M01PTH_WITHOUT_TEXT"))
    )
    (comp (ref "JP133")
      (value "M01PTH_WITHOUT_TEXT")
      (footprint "eagle-import:1X01_WITHOUT_TEXT")
      (libsource (lib "eagle-import") (part "M01PTH_WITHOUT_TEXT"))
    )
    (comp (ref "JP134")
      (value "M01PTH_WITHOUT_TEXT")
      (footprint "eagle-import:1X01_WITHOUT_TEXT")
      (libsource (lib "eagle-import") (part "M01PTH_WITHOUT_TEXT"))
    )
    (comp (ref "JP135")
      (value "M01PTH_WITHOUT_TEXT")
      (footprint "eagle-import:1X01_WITHOUT_TEXT")
      (libsource (lib "eagle-import") (part "M01PTH_WITHOUT_TEXT"))
    )
    (comp (ref "JP136")
      (value "M01PTH_WITHOUT_TEXT")
      (footprint "eagle-import:1X01_WITHOUT_TEXT")
      (libsource (lib "eagle-import") (part "M01PTH_WITHOUT_TEXT"))
    )
    (comp (ref "JP137")
      (value "M01PTH_WITHOUT_TEXT")
      (footprint "eagle-import:1X01_WITHOUT_TEXT")
      (libsource (lib "eagle-import") (part "M01PTH_WITHOUT_TEXT"))
    )
    (comp (ref "JP138")
      (value "M01PTH_WITHOUT_TEXT")
      (footprint "eagle-import:1X01_WITHOUT_TEXT")
      (libsource (lib "eagle-import") (part "M01PTH_WITHOUT_TEXT"))
    )
    (comp (ref "JP139")
      (value "M01PTH_WITHOUT_TEXT")
      (footprint "eagle-import:1X01_WITHOUT_TEXT")
      (libsource (lib "eagle-import") (part "M01PTH_WITHOUT_TEXT"))
    )
    (comp (ref "JP140")
      (value "M01PTH_WITHOUT_TEXT")
      (footprint "eagle-import:1X01_WITHOUT_TEXT")
      (libsource (lib "eagle-import") (part "M01PTH_WITHOUT_TEXT"))
    )
    (comp (ref "JP141")
      (value "M01PTH_WITHOUT_TEXT")
      (footprint "eagle-import:1X01_WITHOUT_TEXT")
      (libsource (lib "eagle-import") (part "M01PTH_WITHOUT_TEXT"))
    )
    (comp (ref "JP142")
      (value "M01PTH_WITHOUT_TEXT")
      (footprint "eagle-import:1X01_WITHOUT_TEXT")
      (libsource (lib "eagle-import") (part "M01PTH_WITHOUT_TEXT"))
    )
    (comp (ref "JP143")
      (value "M01PTH_WITHOUT_TEXT")
      (footprint "eagle-import:1X01_WITHOUT_TEXT")
      (libsource (lib "eagle-import") (part "M01PTH_WITHOUT_TEXT"))
    )
    (comp (ref "JP144")
      (value "M01PTH_WITHOUT_TEXT")
      (footprint "eagle-import:1X01_WITHOUT_TEXT")
      (libsource (lib "eagle-import") (part "M01PTH_WITHOUT_TEXT"))
    )
    (comp (ref "JP145")
      (value "M01PTH_WITHOUT_TEXT")
      (footprint "eagle-import:1X01_WITHOUT_TEXT")
      (libsource (lib "eagle-import") (part "M01PTH_WITHOUT_TEXT"))
    )
    (comp (ref "JP146")
      (value "M01PTH_WITHOUT_TEXT")
      (footprint "eagle-import:1X01_WITHOUT_TEXT")
      (libsource (lib "eagle-import") (part "M01PTH_WITHOUT_TEXT"))
    )
    (comp (ref "JP147")
      (value "M01PTH_WITHOUT_TEXT")
      (footprint "eagle-import:1X01_WITHOUT_TEXT")
      (libsource (lib "eagle-import") (part "M01PTH_WITHOUT_TEXT"))
    )
    (comp (ref "JP148")
      (value "M01PTH_WITHOUT_TEXT")
      (footprint "eagle-import:1X01_WITHOUT_TEXT")
      (libsource (lib "eagle-import") (part "M01PTH_WITHOUT_TEXT"))
    )
    (comp (ref "JP149")
      (value "M01PTH_WITHOUT_TEXT")
      (footprint "eagle-import:1X01_WITHOUT_TEXT")
      (libsource (lib "eagle-import") (part "M01PTH_WITHOUT_TEXT"))
    )
    (comp (ref "JP150")
      (value "M01PTH_WITHOUT_TEXT")
      (footprint "eagle-import:1X01_WITHOUT_TEXT")
      (libsource (lib "eagle-import") (part "M01PTH_WITHOUT_TEXT"))
    )
    (comp (ref "JP151")
      (value "M01PTH_WITHOUT_TEXT")
      (footprint "eagle-import:1X01_WITHOUT_TEXT")
      (libsource (lib "eagle-import") (part "M01PTH_WITHOUT_TEXT"))
    )
    (comp (ref "JP152")
      (value "M01PTH_WITHOUT_TEXT")
      (footprint "eagle-import:1X01_WITHOUT_TEXT")
      (libsource (lib "eagle-import") (part "M01PTH_WITHOUT_TEXT"))
    )
    (comp (ref "JP153")
      (value "M01PTH_WITHOUT_TEXT")
      (footprint "eagle-import:1X01_WITHOUT_TEXT")
      (libsource (lib "eagle-import") (part "M01PTH_WITHOUT_TEXT"))
    )
    (comp (ref "JP154")
      (value "M01PTH_WITHOUT_TEXT")
      (footprint "eagle-import:1X01_WITHOUT_TEXT")
      (libsource (lib "eagle-import") (part "M01PTH_WITHOUT_TEXT"))
    )
    (comp (ref "JP155")
      (value "M01PTH_WITHOUT_TEXT")
      (footprint "eagle-import:1X01_WITHOUT_TEXT")
      (libsource (lib "eagle-import") (part "M01PTH_WITHOUT_TEXT"))
    )
    (comp (ref "JP156")
      (value "M01PTH_WITHOUT_TEXT")
      (footprint "eagle-import:1X01_WITHOUT_TEXT")
      (libsource (lib "eagle-import") (part "M01PTH_WITHOUT_TEXT"))
    )
    (comp (ref "JP157")
      (value "M01PTH_WITHOUT_TEXT")
      (footprint "eagle-import:1X01_WITHOUT_TEXT")
      (libsource (lib "eagle-import") (part "M01PTH_WITHOUT_TEXT"))
    )
    (comp (ref "JP158")
      (value "M01PTH_WITHOUT_TEXT")
      (footprint "eagle-import:1X01_WITHOUT_TEXT")
      (libsource (lib "eagle-import") (part "M01PTH_WITHOUT_TEXT"))
    )
    (comp (ref "JP159")
      (value "M01PTH_WITHOUT_TEXT")
      (footprint "eagle-import:1X01_WITHOUT_TEXT")
      (libsource (lib "eagle-import") (part "M01PTH_WITHOUT_TEXT"))
    )
    (comp (ref "JP160")
      (value "M01PTH_WITHOUT_TEXT")
      (footprint "eagle-import:1X01_WITHOUT_TEXT")
      (libsource (lib "eagle-import") (part "M01PTH_WITHOUT_TEXT"))
    )
    (comp (ref "JP161")
      (value "M01PTH_WITHOUT_TEXT")
      (footprint "eagle-import:1X01_WITHOUT_TEXT")
      (libsource (lib "eagle-import") (part "M01PTH_WITHOUT_TEXT"))
    )
    (comp (ref "JP162")
      (value "M01PTH_WITHOUT_TEXT")
      (footprint "eagle-import:1X01_WITHOUT_TEXT")
      (libsource (lib "eagle-import") (part "M01PTH_WITHOUT_TEXT"))
    )
    (comp (ref "JP163")
      (value "M01PTH_WITHOUT_TEXT")
      (footprint "eagle-import:1X01_WITHOUT_TEXT")
      (libsource (lib "eagle-import") (part "M01PTH_WITHOUT_TEXT"))
    )
    (comp (ref "JP164")
      (value "M01PTH_WITHOUT_TEXT")
      (footprint "eagle-import:1X01_WITHOUT_TEXT")
      (libsource (lib "eagle-import") (part "M01PTH_WITHOUT_TEXT"))
    )
    (comp (ref "JP165")
      (value "M01PTH_WITHOUT_TEXT")
      (footprint "eagle-import:1X01_WITHOUT_TEXT")
      (libsource (lib "eagle-import") (part "M01PTH_WITHOUT_TEXT"))
    )
    (comp (ref "JP166")
      (value "M01PTH_WITHOUT_TEXT")
      (footprint "eagle-import:1X01_WITHOUT_TEXT")
      (libsource (lib "eagle-import") (part "M01PTH_WITHOUT_TEXT"))
    )
    (comp (ref "JP167")
      (value "M01PTH_WITHOUT_TEXT")
      (footprint "eagle-import:1X01_WITHOUT_TEXT")
      (libsource (lib "eagle-import") (part "M01PTH_WITHOUT_TEXT"))
    )
    (comp (ref "JP168")
      (value "M01PTH_WITHOUT_TEXT")
      (footprint "eagle-import:1X01_WITHOUT_TEXT")
      (libsource (lib "eagle-import") (part "M01PTH_WITHOUT_TEXT"))
    )
    (comp (ref "JP169")
      (value "M01PTH_WITHOUT_TEXT")
      (footprint "eagle-import:1X01_WITHOUT_TEXT")
      (libsource (lib "eagle-import") (part "M01PTH_WITHOUT_TEXT"))
    )
    (comp (ref "JP170")
      (value "M01PTH_WITHOUT_TEXT")
      (footprint "eagle-import:1X01_WITHOUT_TEXT")
      (libsource (lib "eagle-import") (part "M01PTH_WITHOUT_TEXT"))
    )
    (comp (ref "JP171")
      (value "M01PTH_WITHOUT_TEXT")
      (footprint "eagle-import:1X01_WITHOUT_TEXT")
      (libsource (lib "eagle-import") (part "M01PTH_WITHOUT_TEXT"))
    )
    (comp (ref "JP172")
      (value "M01PTH_WITHOUT_TEXT")
      (footprint "eagle-import:1X01_WITHOUT_TEXT")
      (libsource (lib "eagle-import") (part "M01PTH_WITHOUT_TEXT"))
    )
    (comp (ref "JP173")
      (value "M01PTH_WITHOUT_TEXT")
      (footprint "eagle-import:1X01_WITHOUT_TEXT")
      (libsource (lib "eagle-import") (part "M01PTH_WITHOUT_TEXT"))
    )
    (comp (ref "JP174")
      (value "M01PTH_WITHOUT_TEXT")
      (footprint "eagle-import:1X01_WITHOUT_TEXT")
      (libsource (lib "eagle-import") (part "M01PTH_WITHOUT_TEXT"))
    )
    (comp (ref "JP175")
      (value "M01PTH_WITHOUT_TEXT")
      (footprint "eagle-import:1X01_WITHOUT_TEXT")
      (libsource (lib "eagle-import") (part "M01PTH_WITHOUT_TEXT"))
    )
    (comp (ref "JP176")
      (value "M01PTH_WITHOUT_TEXT")
      (footprint "eagle-import:1X01_WITHOUT_TEXT")
      (libsource (lib "eagle-import") (part "M01PTH_WITHOUT_TEXT"))
    )
    (comp (ref "JP177")
      (value "M01PTH_WITHOUT_TEXT")
      (footprint "eagle-import:1X01_WITHOUT_TEXT")
      (libsource (lib "eagle-import") (part "M01PTH_WITHOUT_TEXT"))
    )
    (comp (ref "JP178")
      (value "M01PTH_WITHOUT_TEXT")
      (footprint "eagle-import:1X01_WITHOUT_TEXT")
      (libsource (lib "eagle-import") (part "M01PTH_WITHOUT_TEXT"))
    )
    (comp (ref "JP179")
      (value "M01PTH_WITHOUT_TEXT")
      (footprint "eagle-import:1X01_WITHOUT_TEXT")
      (libsource (lib "eagle-import") (part "M01PTH_WITHOUT_TEXT"))
    )
    (comp (ref "JP180")
      (value "M01PTH_WITHOUT_TEXT")
      (footprint "eagle-import:1X01_WITHOUT_TEXT")
      (libsource (lib "eagle-import") (part "M01PTH_WITHOUT_TEXT"))
    )
    (comp (ref "JP181")
      (value "M01PTH_WITHOUT_TEXT")
      (footprint "eagle-import:1X01_WITHOUT_TEXT")
      (libsource (lib "eagle-import") (part "M01PTH_WITHOUT_TEXT"))
    )
    (comp (ref "JP182")
      (value "M01PTH_WITHOUT_TEXT")
      (footprint "eagle-import:1X01_WITHOUT_TEXT")
      (libsource (lib "eagle-import") (part "M01PTH_WITHOUT_TEXT"))
    )
    (comp (ref "JP183")
      (value "M01PTH_WITHOUT_TEXT")
      (footprint "eagle-import:1X01_WITHOUT_TEXT")
      (libsource (lib "eagle-import") (part "M01PTH_WITHOUT_TEXT"))
    )
    (comp (ref "JP184")
      (value "M01PTH_WITHOUT_TEXT")
      (footprint "eagle-import:1X01_WITHOUT_TEXT")
      (libsource (lib "eagle-import") (part "M01PTH_WITHOUT_TEXT"))
    )
    (comp (ref "JP185")
      (value "M01PTH_WITHOUT_TEXT")
      (footprint "eagle-import:1X01_WITHOUT_TEXT")
      (libsource (lib "eagle-import") (part "M01PTH_WITHOUT_TEXT"))
    )
    (comp (ref "JP186")
      (value "M01PTH_WITHOUT_TEXT")
      (footprint "eagle-import:1X01_WITHOUT_TEXT")
      (libsource (lib "eagle-import") (part "M01PTH_WITHOUT_TEXT"))
    )
    (comp (ref "JP187")
      (value "M01PTH_WITHOUT_TEXT")
      (footprint "eagle-import:1X01_WITHOUT_TEXT")
      (libsource (lib "eagle-import") (part "M01PTH_WITHOUT_TEXT"))
    )
    (comp (ref "JP188")
      (value "M01PTH_WITHOUT_TEXT")
      (footprint "eagle-import:1X01_WITHOUT_TEXT")
      (libsource (lib "eagle-import") (part "M01PTH_WITHOUT_TEXT"))
    )
    (comp (ref "JP189")
      (value "M01PTH_WITHOUT_TEXT")
      (footprint "eagle-import:1X01_WITHOUT_TEXT")
      (libsource (lib "eagle-import") (part "M01PTH_WITHOUT_TEXT"))
    )
    (comp (ref "JP190")
      (value "M01PTH_WITHOUT_TEXT")
      (footprint "eagle-import:1X01_WITHOUT_TEXT")
      (libsource (lib "eagle-import") (part "M01PTH_WITHOUT_TEXT"))
    )
    (comp (ref "JP191")
      (value "M01PTH_WITHOUT_TEXT")
      (footprint "eagle-import:1X01_WITHOUT_TEXT")
      (libsource (lib "eagle-import") (part "M01PTH_WITHOUT_TEXT"))
    )
    (comp (ref "JP192")
      (value "M01PTH_WITHOUT_TEXT")
      (footprint "eagle-import:1X01_WITHOUT_TEXT")
      (libsource (lib "eagle-import") (part "M01PTH_WITHOUT_TEXT"))
    )
    (comp (ref "JP193")
      (value "M01PTH_WITHOUT_TEXT")
      (footprint "eagle-import:1X01_WITHOUT_TEXT")
      (libsource (lib "eagle-import") (part "M01PTH_WITHOUT_TEXT"))
    )
    (comp (ref "JP194")
      (value "M01PTH_WITHOUT_TEXT")
      (footprint "eagle-import:1X01_WITHOUT_TEXT")
      (libsource (lib "eagle-import") (part "M01PTH_WITHOUT_TEXT"))
    )
    (comp (ref "JP195")
      (value "M01PTH_WITHOUT_TEXT")
      (footprint "eagle-import:1X01_WITHOUT_TEXT")
      (libsource (lib "eagle-import") (part "M01PTH_WITHOUT_TEXT"))
    )
    (comp (ref "JP196")
      (value "M01PTH_WITHOUT_TEXT")
      (footprint "eagle-import:1X01_WITHOUT_TEXT")
      (libsource (lib "eagle-import") (part "M01PTH_WITHOUT_TEXT"))
    )
    (comp (ref "JP197")
      (value "M01PTH_WITHOUT_TEXT")
      (footprint "eagle-import:1X01_WITHOUT_TEXT")
      (libsource (lib "eagle-import") (part "M01PTH_WITHOUT_TEXT"))
    )
    (comp (ref "JP198")
      (value "M01PTH_WITHOUT_TEXT")
      (footprint "eagle-import:1X01_WITHOUT_TEXT")
      (libsource (lib "eagle-import") (part "M01PTH_WITHOUT_TEXT"))
    )
    (comp (ref "JP199")
      (value "M01PTH_WITHOUT_TEXT")
      (footprint "eagle-import:1X01_WITHOUT_TEXT")
      (libsource (lib "eagle-import") (part "M01PTH_WITHOUT_TEXT"))
    )
    (comp (ref "JP200")
      (value "M01PTH_WITHOUT_TEXT")
      (footprint "eagle-import:1X01_WITHOUT_TEXT")
      (libsource (lib "eagle-import") (part "M01PTH_WITHOUT_TEXT"))
    )
    (comp (ref "JP201")
      (value "M01PTH_WITHOUT_TEXT")
      (footprint "eagle-import:1X01_WITHOUT_TEXT")
      (libsource (lib "eagle-import") (part "M01PTH_WITHOUT_TEXT"))
    )
    (comp (ref "JP202")
      (value "M01PTH_WITHOUT_TEXT")
      (footprint "eagle-import:1X01_WITHOUT_TEXT")
      (libsource (lib "eagle-import") (part "M01PTH_WITHOUT_TEXT"))
    )
    (comp (ref "JP203")
      (value "M01PTH_WITHOUT_TEXT")
      (footprint "eagle-import:1X01_WITHOUT_TEXT")
      (libsource (lib "eagle-import") (part "M01PTH_WITHOUT_TEXT"))
    )
    (comp (ref "JP204")
      (value "M01PTH_WITHOUT_TEXT")
      (footprint "eagle-import:1X01_WITHOUT_TEXT")
      (libsource (lib "eagle-import") (part "M01PTH_WITHOUT_TEXT"))
    )
    (comp (ref "JP205")
      (value "M01PTH_WITHOUT_TEXT")
      (footprint "eagle-import:1X01_WITHOUT_TEXT")
      (libsource (lib "eagle-import") (part "M01PTH_WITHOUT_TEXT"))
    )
    (comp (ref "JP206")
      (value "M01PTH_WITHOUT_TEXT")
      (footprint "eagle-import:1X01_WITHOUT_TEXT")
      (libsource (lib "eagle-import") (part "M01PTH_WITHOUT_TEXT"))
    )
    (comp (ref "JP207")
      (value "M01PTH_WITHOUT_TEXT")
      (footprint "eagle-import:1X01_WITHOUT_TEXT")
      (libsource (lib "eagle-import") (part "M01PTH_WITHOUT_TEXT"))
    )
    (comp (ref "JP208")
      (value "M01PTH_WITHOUT_TEXT")
      (footprint "eagle-import:1X01_WITHOUT_TEXT")
      (libsource (lib "eagle-import") (part "M01PTH_WITHOUT_TEXT"))
    )
    (comp (ref "JP209")
      (value "M01PTH_WITHOUT_TEXT")
      (footprint "eagle-import:1X01_WITHOUT_TEXT")
      (libsource (lib "eagle-import") (part "M01PTH_WITHOUT_TEXT"))
    )
    (comp (ref "JP210")
      (value "M01PTH_WITHOUT_TEXT")
      (footprint "eagle-import:1X01_WITHOUT_TEXT")
      (libsource (lib "eagle-import") (part "M01PTH_WITHOUT_TEXT"))
    )
    (comp (ref "JP211")
      (value "M01PTH_WITHOUT_TEXT")
      (footprint "eagle-import:1X01_WITHOUT_TEXT")
      (libsource (lib "eagle-import") (part "M01PTH_WITHOUT_TEXT"))
    )
    (comp (ref "JP212")
      (value "M01PTH_WITHOUT_TEXT")
      (footprint "eagle-import:1X01_WITHOUT_TEXT")
      (libsource (lib "eagle-import") (part "M01PTH_WITHOUT_TEXT"))
    )
    (comp (ref "JP213")
      (value "M01PTH_WITHOUT_TEXT")
      (footprint "eagle-import:1X01_WITHOUT_TEXT")
      (libsource (lib "eagle-import") (part "M01PTH_WITHOUT_TEXT"))
    )
    (comp (ref "JP214")
      (value "M01PTH_WITHOUT_TEXT")
      (footprint "eagle-import:1X01_WITHOUT_TEXT")
      (libsource (lib "eagle-import") (part "M01PTH_WITHOUT_TEXT"))
    )
    (comp (ref "JP215")
      (value "M01PTH_WITHOUT_TEXT")
      (footprint "eagle-import:1X01_WITHOUT_TEXT")
      (libsource (lib "eagle-import") (part "M01PTH_WITHOUT_TEXT"))
    )
    (comp (ref "JP216")
      (value "M01PTH_WITHOUT_TEXT")
      (footprint "eagle-import:1X01_WITHOUT_TEXT")
      (libsource (lib "eagle-import") (part "M01PTH_WITHOUT_TEXT"))
    )
    (comp (ref "JP217")
      (value "M01PTH_WITHOUT_TEXT")
      (footprint "eagle-import:1X01_WITHOUT_TEXT")
      (libsource (lib "eagle-import") (part "M01PTH_WITHOUT_TEXT"))
    )
    (comp (ref "JP218")
      (value "M01PTH_WITHOUT_TEXT")
      (footprint "eagle-import:1X01_WITHOUT_TEXT")
      (libsource (lib "eagle-import") (part "M01PTH_WITHOUT_TEXT"))
    )
    (comp (ref "JP219")
      (value "M01PTH_WITHOUT_TEXT")
      (footprint "eagle-import:1X01_WITHOUT_TEXT")
      (libsource (lib "eagle-import") (part "M01PTH_WITHOUT_TEXT"))
    )
    (comp (ref "JP220")
      (value "M01PTH_WITHOUT_TEXT")
      (footprint "eagle-import:1X01_WITHOUT_TEXT")
      (libsource (lib "eagle-import") (part "M01PTH_WITHOUT_TEXT"))
    )
    (comp (ref "JP221")
      (value "M01PTH_WITHOUT_TEXT")
      (footprint "eagle-import:1X01_WITHOUT_TEXT")
      (libsource (lib "eagle-import") (part "M01PTH_WITHOUT_TEXT"))
    )
    (comp (ref "JP222")
      (value "M01PTH_WITHOUT_TEXT")
      (footprint "eagle-import:1X01_WITHOUT_TEXT")
      (libsource (lib "eagle-import") (part "M01PTH_WITHOUT_TEXT"))
    )
    (comp (ref "JP223")
      (value "M01PTH_WITHOUT_TEXT")
      (footprint "eagle-import:1X01_WITHOUT_TEXT")
      (libsource (lib "eagle-import") (part "M01PTH_WITHOUT_TEXT"))
    )
    (comp (ref "JP224")
      (value "M01PTH_WITHOUT_TEXT")
      (footprint "eagle-import:1X01_WITHOUT_TEXT")
      (libsource (lib "eagle-import") (part "M01PTH_WITHOUT_TEXT"))
    )
    (comp (ref "JP225")
      (value "M01PTH_WITHOUT_TEXT")
      (footprint "eagle-import:1X01_WITHOUT_TEXT")
      (libsource (lib "eagle-import") (part "M01PTH_WITHOUT_TEXT"))
    )
    (comp (ref "JP226")
      (value "M01PTH_WITHOUT_TEXT")
      (footprint "eagle-import:1X01_WITHOUT_TEXT")
      (libsource (lib "eagle-import") (part "M01PTH_WITHOUT_TEXT"))
    )
    (comp (ref "JP227")
      (value "M01PTH_WITHOUT_TEXT")
      (footprint "eagle-import:1X01_WITHOUT_TEXT")
      (libsource (lib "eagle-import") (part "M01PTH_WITHOUT_TEXT"))
    )
    (comp (ref "JP228")
      (value "M01PTH_WITHOUT_TEXT")
      (footprint "eagle-import:1X01_WITHOUT_TEXT")
      (libsource (lib "eagle-import") (part "M01PTH_WITHOUT_TEXT"))
    )
    (comp (ref "JP229")
      (value "M01PTH_WITHOUT_TEXT")
      (footprint "eagle-import:1X01_WITHOUT_TEXT")
      (libsource (lib "eagle-import") (part "M01PTH_WITHOUT_TEXT"))
    )
    (comp (ref "JP230")
      (value "M01PTH_WITHOUT_TEXT")
      (footprint "eagle-import:1X01_WITHOUT_TEXT")
      (libsource (lib "eagle-import") (part "M01PTH_WITHOUT_TEXT"))
    )
    (comp (ref "JP231")
      (value "M01PTH_WITHOUT_TEXT")
      (footprint "eagle-import:1X01_WITHOUT_TEXT")
      (libsource (lib "eagle-import") (part "M01PTH_WITHOUT_TEXT"))
    )
    (comp (ref "JP232")
      (value "M01PTH_WITHOUT_TEXT")
      (footprint "eagle-import:1X01_WITHOUT_TEXT")
      (libsource (lib "eagle-import") (part "M01PTH_WITHOUT_TEXT"))
    )
    (comp (ref "JP233")
      (value "M01PTH_WITHOUT_TEXT")
      (footprint "eagle-import:1X01_WITHOUT_TEXT")
      (libsource (lib "eagle-import") (part "M01PTH_WITHOUT_TEXT"))
    )
    (comp (ref "JP234")
      (value "M01PTH_WITHOUT_TEXT")
      (footprint "eagle-import:1X01_WITHOUT_TEXT")
      (libsource (lib "eagle-import") (part "M01PTH_WITHOUT_TEXT"))
    )
    (comp (ref "JP235")
      (value "M01PTH_WITHOUT_TEXT")
      (footprint "eagle-import:1X01_WITHOUT_TEXT")
      (libsource (lib "eagle-import") (part "M01PTH_WITHOUT_TEXT"))
    )
    (comp (ref "JP236")
      (value "M01PTH_WITHOUT_TEXT")
      (footprint "eagle-import:1X01_WITHOUT_TEXT")
      (libsource (lib "eagle-import") (part "M01PTH_WITHOUT_TEXT"))
    )
    (comp (ref "JP237")
      (value "M01PTH_WITHOUT_TEXT")
      (footprint "eagle-import:1X01_WITHOUT_TEXT")
      (libsource (lib "eagle-import") (part "M01PTH_WITHOUT_TEXT"))
    )
    (comp (ref "JP238")
      (value "M01PTH_WITHOUT_TEXT")
      (footprint "eagle-import:1X01_WITHOUT_TEXT")
      (libsource (lib "eagle-import") (part "M01PTH_WITHOUT_TEXT"))
    )
    (comp (ref "JP239")
      (value "M01PTH_WITHOUT_TEXT")
      (footprint "eagle-import:1X01_WITHOUT_TEXT")
      (libsource (lib "eagle-import") (part "M01PTH_WITHOUT_TEXT"))
    )
    (comp (ref "JP240")
      (value "M01PTH_WITHOUT_TEXT")
      (footprint "eagle-import:1X01_WITHOUT_TEXT")
      (libsource (lib "eagle-import") (part "M01PTH_WITHOUT_TEXT"))
    )
    (comp (ref "JP241")
      (value "M01PTH_WITHOUT_TEXT")
      (footprint "eagle-import:1X01_WITHOUT_TEXT")
      (libsource (lib "eagle-import") (part "M01PTH_WITHOUT_TEXT"))
    )
    (comp (ref "JP242")
      (value "M01PTH_WITHOUT_TEXT")
      (footprint "eagle-import:1X01_WITHOUT_TEXT")
      (libsource (lib "eagle-import") (part "M01PTH_WITHOUT_TEXT"))
    )
    (comp (ref "JP243")
      (value "M01PTH_WITHOUT_TEXT")
      (footprint "eagle-import:1X01_WITHOUT_TEXT")
      (libsource (lib "eagle-import") (part "M01PTH_WITHOUT_TEXT"))
    )
    (comp (ref "JP244")
      (value "M01PTH_WITHOUT_TEXT")
      (footprint "eagle-import:1X01_WITHOUT_TEXT")
      (libsource (lib "eagle-import") (part "M01PTH_WITHOUT_TEXT"))
    )
    (comp (ref "JP245")
      (value "M01PTH_WITHOUT_TEXT")
      (footprint "eagle-import:1X01_WITHOUT_TEXT")
      (libsource (lib "eagle-import") (part "M01PTH_WITHOUT_TEXT"))
    )
    (comp (ref "JP246")
      (value "M01PTH_WITHOUT_TEXT")
      (footprint "eagle-import:1X01_WITHOUT_TEXT")
      (libsource (lib "eagle-import") (part "M01PTH_WITHOUT_TEXT"))
    )
    (comp (ref "JP247")
      (value "M01PTH_WITHOUT_TEXT")
      (footprint "eagle-import:1X01_WITHOUT_TEXT")
      (libsource (lib "eagle-import") (part "M01PTH_WITHOUT_TEXT"))
    )
    (comp (ref "JP248")
      (value "M01PTH_WITHOUT_TEXT")
      (footprint "eagle-import:1X01_WITHOUT_TEXT")
      (libsource (lib "eagle-import") (part "M01PTH_WITHOUT_TEXT"))
    )
    (comp (ref "JP249")
      (value "M01PTH_WITHOUT_TEXT")
      (footprint "eagle-import:1X01_WITHOUT_TEXT")
      (libsource (lib "eagle-import") (part "M01PTH_WITHOUT_TEXT"))
    )
    (comp (ref "JP250")
      (value "M01PTH_WITHOUT_TEXT")
      (footprint "eagle-import:1X01_WITHOUT_TEXT")
      (libsource (lib "eagle-import") (part "M01PTH_WITHOUT_TEXT"))
    )
    (comp (ref "JP251")
      (value "M01PTH_WITHOUT_TEXT")
      (footprint "eagle-import:1X01_WITHOUT_TEXT")
      (libsource (lib "eagle-import") (part "M01PTH_WITHOUT_TEXT"))
    )
    (comp (ref "JP252")
      (value "M01PTH_WITHOUT_TEXT")
      (footprint "eagle-import:1X01_WITHOUT_TEXT")
      (libsource (lib "eagle-import") (part "M01PTH_WITHOUT_TEXT"))
    )
    (comp (ref "JP253")
      (value "M01PTH_WITHOUT_TEXT")
      (footprint "eagle-import:1X01_WITHOUT_TEXT")
      (libsource (lib "eagle-import") (part "M01PTH_WITHOUT_TEXT"))
    )
    (comp (ref "JP254")
      (value "M01PTH_WITHOUT_TEXT")
      (footprint "eagle-import:1X01_WITHOUT_TEXT")
      (libsource (lib "eagle-import") (part "M01PTH_WITHOUT_TEXT"))
    )
    (comp (ref "JP255")
      (value "M01PTH_WITHOUT_TEXT")
      (footprint "eagle-import:1X01_WITHOUT_TEXT")
      (libsource (lib "eagle-import") (part "M01PTH_WITHOUT_TEXT"))
    )
    (comp (ref "JP256")
      (value "M01PTH_WITHOUT_TEXT")
      (footprint "eagle-import:1X01_WITHOUT_TEXT")
      (libsource (lib "eagle-import") (part "M01PTH_WITHOUT_TEXT"))
    )
    (comp (ref "JP257")
      (value "M01PTH_WITHOUT_TEXT")
      (footprint "eagle-import:1X01_WITHOUT_TEXT")
      (libsource (lib "eagle-import") (part "M01PTH_WITHOUT_TEXT"))
    )
    (comp (ref "JP258")
      (value "M01PTH_WITHOUT_TEXT")
      (footprint "eagle-import:1X01_WITHOUT_TEXT")
      (libsource (lib "eagle-import") (part "M01PTH_WITHOUT_TEXT"))
    )
    (comp (ref "JP259")
      (value "M01PTH_WITHOUT_TEXT")
      (footprint "eagle-import:1X01_WITHOUT_TEXT")
      (libsource (lib "eagle-import") (part "M01PTH_WITHOUT_TEXT"))
    )
    (comp (ref "JP260")
      (value "M01PTH_WITHOUT_TEXT")
      (footprint "eagle-import:1X01_WITHOUT_TEXT")
      (libsource (lib "eagle-import") (part "M01PTH_WITHOUT_TEXT"))
    )
    (comp (ref "JP261")
      (value "M01PTH_WITHOUT_TEXT")
      (footprint "eagle-import:1X01_WITHOUT_TEXT")
      (libsource (lib "eagle-import") (part "M01PTH_WITHOUT_TEXT"))
    )
    (comp (ref "JP262")
      (value "M01PTH_WITHOUT_TEXT")
      (footprint "eagle-import:1X01_WITHOUT_TEXT")
      (libsource (lib "eagle-import") (part "M01PTH_WITHOUT_TEXT"))
    )
    (comp (ref "JP263")
      (value "M01PTH_WITHOUT_TEXT")
      (footprint "eagle-import:1X01_WITHOUT_TEXT")
      (libsource (lib "eagle-import") (part "M01PTH_WITHOUT_TEXT"))
    )
    (comp (ref "JP264")
      (value "M01PTH_WITHOUT_TEXT")
      (footprint "eagle-import:1X01_WITHOUT_TEXT")
      (libsource (lib "eagle-import") (part "M01PTH_WITHOUT_TEXT"))
    )
    (comp (ref "JP265")
      (value "M01PTH_WITHOUT_TEXT")
      (footprint "eagle-import:1X01_WITHOUT_TEXT")
      (libsource (lib "eagle-import") (part "M01PTH_WITHOUT_TEXT"))
    )
    (comp (ref "JP266")
      (value "M01PTH_WITHOUT_TEXT")
      (footprint "eagle-import:1X01_WITHOUT_TEXT")
      (libsource (lib "eagle-import") (part "M01PTH_WITHOUT_TEXT"))
    )
    (comp (ref "JP267")
      (value "M01PTH_WITHOUT_TEXT")
      (footprint "eagle-import:1X01_WITHOUT_TEXT")
      (libsource (lib "eagle-import") (part "M01PTH_WITHOUT_TEXT"))
    )
    (comp (ref "JP268")
      (value "M01PTH_WITHOUT_TEXT")
      (footprint "eagle-import:1X01_WITHOUT_TEXT")
      (libsource (lib "eagle-import") (part "M01PTH_WITHOUT_TEXT"))
    )
    (comp (ref "JP269")
      (value "M01PTH_WITHOUT_TEXT")
      (footprint "eagle-import:1X01_WITHOUT_TEXT")
      (libsource (lib "eagle-import") (part "M01PTH_WITHOUT_TEXT"))
    )
    (comp (ref "JP270")
      (value "M01PTH_WITHOUT_TEXT")
      (footprint "eagle-import:1X01_WITHOUT_TEXT")
      (libsource (lib "eagle-import") (part "M01PTH_WITHOUT_TEXT"))
    )
    (comp (ref "JP271")
      (value "M01PTH_WITHOUT_TEXT")
      (footprint "eagle-import:1X01_WITHOUT_TEXT")
      (libsource (lib "eagle-import") (part "M01PTH_WITHOUT_TEXT"))
    )
    (comp (ref "JP272")
      (value "M01PTH_WITHOUT_TEXT")
      (footprint "eagle-import:1X01_WITHOUT_TEXT")
      (libsource (lib "eagle-import") (part "M01PTH_WITHOUT_TEXT"))
    )
    (comp (ref "JP273")
      (value "M01PTH_WITHOUT_TEXT")
      (footprint "eagle-import:1X01_WITHOUT_TEXT")
      (libsource (lib "eagle-import") (part "M01PTH_WITHOUT_TEXT"))
    )
    (comp (ref "JP274")
      (value "M01PTH_WITHOUT_TEXT")
      (footprint "eagle-import:1X01_WITHOUT_TEXT")
      (libsource (lib "eagle-import") (part "M01PTH_WITHOUT_TEXT"))
    )
    (comp (ref "JP275")
      (value "M01PTH_WITHOUT_TEXT")
      (footprint "eagle-import:1X01_WITHOUT_TEXT")
      (libsource (lib "eagle-import") (part "M01PTH_WITHOUT_TEXT"))
    )
    (comp (ref "JP276")
      (value "M01PTH_WITHOUT_TEXT")
      (footprint "eagle-import:1X01_WITHOUT_TEXT")
      (libsource (lib "eagle-import") (part "M01PTH_WITHOUT_TEXT"))
    )
    (comp (ref "JP277")
      (value "M01PTH_WITHOUT_TEXT")
      (footprint "eagle-import:1X01_WITHOUT_TEXT")
      (libsource (lib "eagle-import") (part "M01PTH_WITHOUT_TEXT"))
    )
    (comp (ref "JP278")
      (value "M01PTH_WITHOUT_TEXT")
      (footprint "eagle-import:1X01_WITHOUT_TEXT")
      (libsource (lib "eagle-import") (part "M01PTH_WITHOUT_TEXT"))
    )
    (comp (ref "JP279")
      (value "M01PTH_WITHOUT_TEXT")
      (footprint "eagle-import:1X01_WITHOUT_TEXT")
      (libsource (lib "eagle-import") (part "M01PTH_WITHOUT_TEXT"))
    )
    (comp (ref "JP280")
      (value "M01PTH_WITHOUT_TEXT")
      (footprint "eagle-import:1X01_WITHOUT_TEXT")
      (libsource (lib "eagle-import") (part "M01PTH_WITHOUT_TEXT"))
    )
    (comp (ref "JP281")
      (value "M01PTH_WITHOUT_TEXT")
      (footprint "eagle-import:1X01_WITHOUT_TEXT")
      (libsource (lib "eagle-import") (part "M01PTH_WITHOUT_TEXT"))
    )
    (comp (ref "JP282")
      (value "M01PTH_WITHOUT_TEXT")
      (footprint "eagle-import:1X01_WITHOUT_TEXT")
      (libsource (lib "eagle-import") (part "M01PTH_WITHOUT_TEXT"))
    )
    (comp (ref "JP283")
      (value "M01PTH_WITHOUT_TEXT")
      (footprint "eagle-import:1X01_WITHOUT_TEXT")
      (libsource (lib "eagle-import") (part "M01PTH_WITHOUT_TEXT"))
    )
    (comp (ref "JP284")
      (value "M01PTH_WITHOUT_TEXT")
      (footprint "eagle-import:1X01_WITHOUT_TEXT")
      (libsource (lib "eagle-import") (part "M01PTH_WITHOUT_TEXT"))
    )
    (comp (ref "JP285")
      (value "M01PTH_WITHOUT_TEXT")
      (footprint "eagle-import:1X01_WITHOUT_TEXT")
      (libsource (lib "eagle-import") (part "M01PTH_WITHOUT_TEXT"))
    )
    (comp (ref "JP286")
      (value "M01PTH_WITHOUT_TEXT")
      (footprint "eagle-import:1X01_WITHOUT_TEXT")
      (libsource (lib "eagle-import") (part "M01PTH_WITHOUT_TEXT"))
    )
    (comp (ref "JP287")
      (value "M01PTH_WITHOUT_TEXT")
      (footprint "eagle-import:1X01_WITHOUT_TEXT")
      (libsource (lib "eagle-import") (part "M01PTH_WITHOUT_TEXT"))
    )
    (comp (ref "JP288")
      (value "M01PTH_WITHOUT_TEXT")
      (footprint "eagle-import:1X01_WITHOUT_TEXT")
      (libsource (lib "eagle-import") (part "M01PTH_WITHOUT_TEXT"))
    )
    (comp (ref "JP289")
      (value "M01PTH_WITHOUT_TEXT")
      (footprint "eagle-import:1X01_WITHOUT_TEXT")
      (libsource (lib "eagle-import") (part "M01PTH_WITHOUT_TEXT"))
    )
    (comp (ref "JP290")
      (value "M01PTH_WITHOUT_TEXT")
      (footprint "eagle-import:1X01_WITHOUT_TEXT")
      (libsource (lib "eagle-import") (part "M01PTH_WITHOUT_TEXT"))
    )
    (comp (ref "JP291")
      (value "M01PTH_WITHOUT_TEXT")
      (footprint "eagle-import:1X01_WITHOUT_TEXT")
      (libsource (lib "eagle-import") (part "M01PTH_WITHOUT_TEXT"))
    )
    (comp (ref "JP292")
      (value "M01PTH_WITHOUT_TEXT")
      (footprint "eagle-import:1X01_WITHOUT_TEXT")
      (libsource (lib "eagle-import") (part "M01PTH_WITHOUT_TEXT"))
    )
    (comp (ref "JP293")
      (value "M01PTH_WITHOUT_TEXT")
      (footprint "eagle-import:1X01_WITHOUT_TEXT")
      (libsource (lib "eagle-import") (part "M01PTH_WITHOUT_TEXT"))
    )
    (comp (ref "JP294")
      (value "M01PTH_WITHOUT_TEXT")
      (footprint "eagle-import:1X01_WITHOUT_TEXT")
      (libsource (lib "eagle-import") (part "M01PTH_WITHOUT_TEXT"))
    )
    (comp (ref "JP295")
      (value "M01PTH_WITHOUT_TEXT")
      (footprint "eagle-import:1X01_WITHOUT_TEXT")
      (libsource (lib "eagle-import") (part "M01PTH_WITHOUT_TEXT"))
    )
    (comp (ref "JP296")
      (value "M01PTH_WITHOUT_TEXT")
      (footprint "eagle-import:1X01_WITHOUT_TEXT")
      (libsource (lib "eagle-import") (part "M01PTH_WITHOUT_TEXT"))
    )
    (comp (ref "JP297")
      (value "M01PTH_WITHOUT_TEXT")
      (footprint "eagle-import:1X01_WITHOUT_TEXT")
      (libsource (lib "eagle-import") (part "M01PTH_WITHOUT_TEXT"))
    )
    (comp (ref "JP298")
      (value "M01PTH_WITHOUT_TEXT")
      (footprint "eagle-import:1X01_WITHOUT_TEXT")
      (libsource (lib "eagle-import") (part "M01PTH_WITHOUT_TEXT"))
    )
    (comp (ref "JP299")
      (value "M01PTH_WITHOUT_TEXT")
      (footprint "eagle-import:1X01_WITHOUT_TEXT")
      (libsource (lib "eagle-import") (part "M01PTH_WITHOUT_TEXT"))
    )
    (comp (ref "JP300")
      (value "M01PTH_WITHOUT_TEXT")
      (footprint "eagle-import:1X01_WITHOUT_TEXT")
      (libsource (lib "eagle-import") (part "M01PTH_WITHOUT_TEXT"))
    )
    (comp (ref "JP301")
      (value "M01PTH_WITHOUT_TEXT")
      (footprint "eagle-import:1X01_WITHOUT_TEXT")
      (libsource (lib "eagle-import") (part "M01PTH_WITHOUT_TEXT"))
    )
    (comp (ref "JP302")
      (value "M01PTH_WITHOUT_TEXT")
      (footprint "eagle-import:1X01_WITHOUT_TEXT")
      (libsource (lib "eagle-import") (part "M01PTH_WITHOUT_TEXT"))
    )
    (comp (ref "JP303")
      (value "M01PTH_WITHOUT_TEXT")
      (footprint "eagle-import:1X01_WITHOUT_TEXT")
      (libsource (lib "eagle-import") (part "M01PTH_WITHOUT_TEXT"))
    )
    (comp (ref "JP304")
      (value "M01PTH_WITHOUT_TEXT")
      (footprint "eagle-import:1X01_WITHOUT_TEXT")
      (libsource (lib "eagle-import") (part "M01PTH_WITHOUT_TEXT"))
    )
    (comp (ref "JP305")
      (value "M01PTH_WITHOUT_TEXT")
      (footprint "eagle-import:1X01_WITHOUT_TEXT")
      (libsource (lib "eagle-import") (part "M01PTH_WITHOUT_TEXT"))
    )
    (comp (ref "JP306")
      (value "M01PTH_WITHOUT_TEXT")
      (footprint "eagle-import:1X01_WITHOUT_TEXT")
      (libsource (lib "eagle-import") (part "M01PTH_WITHOUT_TEXT"))
    )
    (comp (ref "JP307")
      (value "M01PTH_WITHOUT_TEXT")
      (footprint "eagle-import:1X01_WITHOUT_TEXT")
      (libsource (lib "eagle-import") (part "M01PTH_WITHOUT_TEXT"))
    )
    (comp (ref "JP308")
      (value "M01PTH_WITHOUT_TEXT")
      (footprint "eagle-import:1X01_WITHOUT_TEXT")
      (libsource (lib "eagle-import") (part "M01PTH_WITHOUT_TEXT"))
    )
    (comp (ref "JP309")
      (value "M01PTH_WITHOUT_TEXT")
      (footprint "eagle-import:1X01_WITHOUT_TEXT")
      (libsource (lib "eagle-import") (part "M01PTH_WITHOUT_TEXT"))
    )
    (comp (ref "JP310")
      (value "M01PTH_WITHOUT_TEXT")
      (footprint "eagle-import:1X01_WITHOUT_TEXT")
      (libsource (lib "eagle-import") (part "M01PTH_WITHOUT_TEXT"))
    )
    (comp (ref "JP311")
      (value "M01PTH_WITHOUT_TEXT")
      (footprint "eagle-import:1X01_WITHOUT_TEXT")
      (libsource (lib "eagle-import") (part "M01PTH_WITHOUT_TEXT"))
    )
    (comp (ref "JP312")
      (value "M01PTH_WITHOUT_TEXT")
      (footprint "eagle-import:1X01_WITHOUT_TEXT")
      (libsource (lib "eagle-import") (part "M01PTH_WITHOUT_TEXT"))
    )
    (comp (ref "JP313")
      (value "M01PTH_WITHOUT_TEXT")
      (footprint "eagle-import:1X01_WITHOUT_TEXT")
      (libsource (lib "eagle-import") (part "M01PTH_WITHOUT_TEXT"))
    )
    (comp (ref "JP314")
      (value "M01PTH_WITHOUT_TEXT")
      (footprint "eagle-import:1X01_WITHOUT_TEXT")
      (libsource (lib "eagle-import") (part "M01PTH_WITHOUT_TEXT"))
    )
    (comp (ref "JP315")
      (value "M01PTH_WITHOUT_TEXT")
      (footprint "eagle-import:1X01_WITHOUT_TEXT")
      (libsource (lib "eagle-import") (part "M01PTH_WITHOUT_TEXT"))
    )
    (comp (ref "JP316")
      (value "M01PTH_WITHOUT_TEXT")
      (footprint "eagle-import:1X01_WITHOUT_TEXT")
      (libsource (lib "eagle-import") (part "M01PTH_WITHOUT_TEXT"))
    )
    (comp (ref "JP317")
      (value "M01PTH_WITHOUT_TEXT")
      (footprint "eagle-import:1X01_WITHOUT_TEXT")
      (libsource (lib "eagle-import") (part "M01PTH_WITHOUT_TEXT"))
    )
    (comp (ref "JP318")
      (value "M01PTH_WITHOUT_TEXT")
      (footprint "eagle-import:1X01_WITHOUT_TEXT")
      (libsource (lib "eagle-import") (part "M01PTH_WITHOUT_TEXT"))
    )
    (comp (ref "JP319")
      (value "M01PTH_WITHOUT_TEXT")
      (footprint "eagle-import:1X01_WITHOUT_TEXT")
      (libsource (lib "eagle-import") (part "M01PTH_WITHOUT_TEXT"))
    )
    (comp (ref "JP320")
      (value "M01PTH_WITHOUT_TEXT")
      (footprint "eagle-import:1X01_WITHOUT_TEXT")
      (libsource (lib "eagle-import") (part "M01PTH_WITHOUT_TEXT"))
    )
    (comp (ref "JP321")
      (value "M01PTH_WITHOUT_TEXT")
      (footprint "eagle-import:1X01_WITHOUT_TEXT")
      (libsource (lib "eagle-import") (part "M01PTH_WITHOUT_TEXT"))
    )
    (comp (ref "JP322")
      (value "M01PTH_WITHOUT_TEXT")
      (footprint "eagle-import:1X01_WITHOUT_TEXT")
      (libsource (lib "eagle-import") (part "M01PTH_WITHOUT_TEXT"))
    )
    (comp (ref "JP323")
      (value "M01PTH_WITHOUT_TEXT")
      (footprint "eagle-import:1X01_WITHOUT_TEXT")
      (libsource (lib "eagle-import") (part "M01PTH_WITHOUT_TEXT"))
    )
    (comp (ref "JP324")
      (value "M01PTH_WITHOUT_TEXT")
      (footprint "eagle-import:1X01_WITHOUT_TEXT")
      (libsource (lib "eagle-import") (part "M01PTH_WITHOUT_TEXT"))
    )
    (comp (ref "JP325")
      (value "M01PTH_WITHOUT_TEXT")
      (footprint "eagle-import:1X01_WITHOUT_TEXT")
      (libsource (lib "eagle-import") (part "M01PTH_WITHOUT_TEXT"))
    )
    (comp (ref "JP326")
      (value "M01PTH_WITHOUT_TEXT")
      (footprint "eagle-import:1X01_WITHOUT_TEXT")
      (libsource (lib "eagle-import") (part "M01PTH_WITHOUT_TEXT"))
    )
    (comp (ref "JP327")
      (value "M01PTH_WITHOUT_TEXT")
      (footprint "eagle-import:1X01_WITHOUT_TEXT")
      (libsource (lib "eagle-import") (part "M01PTH_WITHOUT_TEXT"))
    )
    (comp (ref "JP328")
      (value "M01PTH_WITHOUT_TEXT")
      (footprint "eagle-import:1X01_WITHOUT_TEXT")
      (libsource (lib "eagle-import") (part "M01PTH_WITHOUT_TEXT"))
    )
    (comp (ref "JP329")
      (value "M01PTH_WITHOUT_TEXT")
      (footprint "eagle-import:1X01_WITHOUT_TEXT")
      (libsource (lib "eagle-import") (part "M01PTH_WITHOUT_TEXT"))
    )
    (comp (ref "JP330")
      (value "M01PTH_WITHOUT_TEXT")
      (footprint "eagle-import:1X01_WITHOUT_TEXT")
      (libsource (lib "eagle-import") (part "M01PTH_WITHOUT_TEXT"))
    )
    (comp (ref "JP331")
      (value "M01PTH_WITHOUT_TEXT")
      (footprint "eagle-import:1X01_WITHOUT_TEXT")
      (libsource (lib "eagle-import") (part "M01PTH_WITHOUT_TEXT"))
    )
    (comp (ref "JP332")
      (value "M01PTH_WITHOUT_TEXT")
      (footprint "eagle-import:1X01_WITHOUT_TEXT")
      (libsource (lib "eagle-import") (part "M01PTH_WITHOUT_TEXT"))
    )
    (comp (ref "JP333")
      (value "M01PTH_WITHOUT_TEXT")
      (footprint "eagle-import:1X01_WITHOUT_TEXT")
      (libsource (lib "eagle-import") (part "M01PTH_WITHOUT_TEXT"))
    )
    (comp (ref "JP334")
      (value "M01PTH_WITHOUT_TEXT")
      (footprint "eagle-import:1X01_WITHOUT_TEXT")
      (libsource (lib "eagle-import") (part "M01PTH_WITHOUT_TEXT"))
    )
    (comp (ref "JP335")
      (value "M01PTH_WITHOUT_TEXT")
      (footprint "eagle-import:1X01_WITHOUT_TEXT")
      (libsource (lib "eagle-import") (part "M01PTH_WITHOUT_TEXT"))
    )
    (comp (ref "JP336")
      (value "M01PTH_WITHOUT_TEXT")
      (footprint "eagle-import:1X01_WITHOUT_TEXT")
      (libsource (lib "eagle-import") (part "M01PTH_WITHOUT_TEXT"))
    )
    (comp (ref "JP337")
      (value "M01PTH_WITHOUT_TEXT")
      (footprint "eagle-import:1X01_WITHOUT_TEXT")
      (libsource (lib "eagle-import") (part "M01PTH_WITHOUT_TEXT"))
    )
    (comp (ref "JP338")
      (value "M01PTH_WITHOUT_TEXT")
      (footprint "eagle-import:1X01_WITHOUT_TEXT")
      (libsource (lib "eagle-import") (part "M01PTH_WITHOUT_TEXT"))
    )
    (comp (ref "JP339")
      (value "M01PTH_WITHOUT_TEXT")
      (footprint "eagle-import:1X01_WITHOUT_TEXT")
      (libsource (lib "eagle-import") (part "M01PTH_WITHOUT_TEXT"))
    )
    (comp (ref "JP340")
      (value "M01PTH_WITHOUT_TEXT")
      (footprint "eagle-import:1X01_WITHOUT_TEXT")
      (libsource (lib "eagle-import") (part "M01PTH_WITHOUT_TEXT"))
    )
    (comp (ref "JP341")
      (value "M01PTH_WITHOUT_TEXT")
      (footprint "eagle-import:1X01_WITHOUT_TEXT")
      (libsource (lib "eagle-import") (part "M01PTH_WITHOUT_TEXT"))
    )
    (comp (ref "JP342")
      (value "M01PTH_WITHOUT_TEXT")
      (footprint "eagle-import:1X01_WITHOUT_TEXT")
      (libsource (lib "eagle-import") (part "M01PTH_WITHOUT_TEXT"))
    )
    (comp (ref "JP343")
      (value "M01PTH_WITHOUT_TEXT")
      (footprint "eagle-import:1X01_WITHOUT_TEXT")
      (libsource (lib "eagle-import") (part "M01PTH_WITHOUT_TEXT"))
    )
    (comp (ref "JP344")
      (value "M01PTH_WITHOUT_TEXT")
      (footprint "eagle-import:1X01_WITHOUT_TEXT")
      (libsource (lib "eagle-import") (part "M01PTH_WITHOUT_TEXT"))
    )
    (comp (ref "JP345")
      (value "M01PTH_WITHOUT_TEXT")
      (footprint "eagle-import:1X01_WITHOUT_TEXT")
      (libsource (lib "eagle-import") (part "M01PTH_WITHOUT_TEXT"))
    )
    (comp (ref "JP346")
      (value "M01PTH_WITHOUT_TEXT")
      (footprint "eagle-import:1X01_WITHOUT_TEXT")
      (libsource (lib "eagle-import") (part "M01PTH_WITHOUT_TEXT"))
    )
    (comp (ref "JP347")
      (value "M01PTH_WITHOUT_TEXT")
      (footprint "eagle-import:1X01_WITHOUT_TEXT")
      (libsource (lib "eagle-import") (part "M01PTH_WITHOUT_TEXT"))
    )
    (comp (ref "JP348")
      (value "M01PTH_WITHOUT_TEXT")
      (footprint "eagle-import:1X01_WITHOUT_TEXT")
      (libsource (lib "eagle-import") (part "M01PTH_WITHOUT_TEXT"))
    )
    (comp (ref "JP349")
      (value "M01PTH_WITHOUT_TEXT")
      (footprint "eagle-import:1X01_WITHOUT_TEXT")
      (libsource (lib "eagle-import") (part "M01PTH_WITHOUT_TEXT"))
    )
    (comp (ref "JP350")
      (value "M01PTH_WITHOUT_TEXT")
      (footprint "eagle-import:1X01_WITHOUT_TEXT")
      (libsource (lib "eagle-import") (part "M01PTH_WITHOUT_TEXT"))
    )
    (comp (ref "JP351")
      (value "M01PTH_WITHOUT_TEXT")
      (footprint "eagle-import:1X01_WITHOUT_TEXT")
      (libsource (lib "eagle-import") (part "M01PTH_WITHOUT_TEXT"))
    )
    (comp (ref "JP352")
      (value "M01PTH_WITHOUT_TEXT")
      (footprint "eagle-import:1X01_WITHOUT_TEXT")
      (libsource (lib "eagle-import") (part "M01PTH_WITHOUT_TEXT"))
    )
    (comp (ref "JP353")
      (value "M01PTH_WITHOUT_TEXT")
      (footprint "eagle-import:1X01_WITHOUT_TEXT")
      (libsource (lib "eagle-import") (part "M01PTH_WITHOUT_TEXT"))
    )
    (comp (ref "JP354")
      (value "M01PTH_WITHOUT_TEXT")
      (footprint "eagle-import:1X01_WITHOUT_TEXT")
      (libsource (lib "eagle-import") (part "M01PTH_WITHOUT_TEXT"))
    )
    (comp (ref "JP355")
      (value "M01PTH_WITHOUT_TEXT")
      (footprint "eagle-import:1X01_WITHOUT_TEXT")
      (libsource (lib "eagle-import") (part "M01PTH_WITHOUT_TEXT"))
    )
    (comp (ref "JP356")
      (value "M01PTH_WITHOUT_TEXT")
      (footprint "eagle-import:1X01_WITHOUT_TEXT")
      (libsource (lib "eagle-import") (part "M01PTH_WITHOUT_TEXT"))
    )
    (comp (ref "JP357")
      (value "M01PTH_WITHOUT_TEXT")
      (footprint "eagle-import:1X01_WITHOUT_TEXT")
      (libsource (lib "eagle-import") (part "M01PTH_WITHOUT_TEXT"))
    )
    (comp (ref "JP358")
      (value "M01PTH_WITHOUT_TEXT")
      (footprint "eagle-import:1X01_WITHOUT_TEXT")
      (libsource (lib "eagle-import") (part "M01PTH_WITHOUT_TEXT"))
    )
    (comp (ref "JP359")
      (value "M01PTH_WITHOUT_TEXT")
      (footprint "eagle-import:1X01_WITHOUT_TEXT")
      (libsource (lib "eagle-import") (part "M01PTH_WITHOUT_TEXT"))
    )
    (comp (ref "JP360")
      (value "M01PTH_WITHOUT_TEXT")
      (footprint "eagle-import:1X01_WITHOUT_TEXT")
      (libsource (lib "eagle-import") (part "M01PTH_WITHOUT_TEXT"))
    )
    (comp (ref "JP361")
      (value "M01PTH_WITHOUT_TEXT")
      (footprint "eagle-import:1X01_WITHOUT_TEXT")
      (libsource (lib "eagle-import") (part "M01PTH_WITHOUT_TEXT"))
    )
    (comp (ref "JP362")
      (value "M01PTH_WITHOUT_TEXT")
      (footprint "eagle-import:1X01_WITHOUT_TEXT")
      (libsource (lib "eagle-import") (part "M01PTH_WITHOUT_TEXT"))
    )
    (comp (ref "JP363")
      (value "M01PTH_WITHOUT_TEXT")
      (footprint "eagle-import:1X01_WITHOUT_TEXT")
      (libsource (lib "eagle-import") (part "M01PTH_WITHOUT_TEXT"))
    )
    (comp (ref "JP364")
      (value "M01PTH_WITHOUT_TEXT")
      (footprint "eagle-import:1X01_WITHOUT_TEXT")
      (libsource (lib "eagle-import") (part "M01PTH_WITHOUT_TEXT"))
    )
    (comp (ref "JP365")
      (value "M01PTH_WITHOUT_TEXT")
      (footprint "eagle-import:1X01_WITHOUT_TEXT")
      (libsource (lib "eagle-import") (part "M01PTH_WITHOUT_TEXT"))
    )
    (comp (ref "JP366")
      (value "M01PTH_WITHOUT_TEXT")
      (footprint "eagle-import:1X01_WITHOUT_TEXT")
      (libsource (lib "eagle-import") (part "M01PTH_WITHOUT_TEXT"))
    )
    (comp (ref "JP367")
      (value "M01PTH_WITHOUT_TEXT")
      (footprint "eagle-import:1X01_WITHOUT_TEXT")
      (libsource (lib "eagle-import") (part "M01PTH_WITHOUT_TEXT"))
    )
    (comp (ref "JP368")
      (value "M01PTH_WITHOUT_TEXT")
      (footprint "eagle-import:1X01_WITHOUT_TEXT")
      (libsource (lib "eagle-import") (part "M01PTH_WITHOUT_TEXT"))
    )
    (comp (ref "JP369")
      (value "M01PTH_WITHOUT_TEXT")
      (footprint "eagle-import:1X01_WITHOUT_TEXT")
      (libsource (lib "eagle-import") (part "M01PTH_WITHOUT_TEXT"))
    )
    (comp (ref "JP370")
      (value "M01PTH_WITHOUT_TEXT")
      (footprint "eagle-import:1X01_WITHOUT_TEXT")
      (libsource (lib "eagle-import") (part "M01PTH_WITHOUT_TEXT"))
    )
    (comp (ref "JP371")
      (value "M01PTH_WITHOUT_TEXT")
      (footprint "eagle-import:1X01_WITHOUT_TEXT")
      (libsource (lib "eagle-import") (part "M01PTH_WITHOUT_TEXT"))
    )
    (comp (ref "JP372")
      (value "M01PTH_WITHOUT_TEXT")
      (footprint "eagle-import:1X01_WITHOUT_TEXT")
      (libsource (lib "eagle-import") (part "M01PTH_WITHOUT_TEXT"))
    )
    (comp (ref "JP373")
      (value "M01PTH_WITHOUT_TEXT")
      (footprint "eagle-import:1X01_WITHOUT_TEXT")
      (libsource (lib "eagle-import") (part "M01PTH_WITHOUT_TEXT"))
    )
    (comp (ref "JP374")
      (value "M01PTH_WITHOUT_TEXT")
      (footprint "eagle-import:1X01_WITHOUT_TEXT")
      (libsource (lib "eagle-import") (part "M01PTH_WITHOUT_TEXT"))
    )
    (comp (ref "JP375")
      (value "M01PTH_WITHOUT_TEXT")
      (footprint "eagle-import:1X01_WITHOUT_TEXT")
      (libsource (lib "eagle-import") (part "M01PTH_WITHOUT_TEXT"))
    )
    (comp (ref "JP376")
      (value "M01PTH_WITHOUT_TEXT")
      (footprint "eagle-import:1X01_WITHOUT_TEXT")
      (libsource (lib "eagle-import") (part "M01PTH_WITHOUT_TEXT"))
    )
    (comp (ref "JP377")
      (value "M01PTH_WITHOUT_TEXT")
      (footprint "eagle-import:1X01_WITHOUT_TEXT")
      (libsource (lib "eagle-import") (part "M01PTH_WITHOUT_TEXT"))
    )
    (comp (ref "JP378")
      (value "M01PTH_WITHOUT_TEXT")
      (footprint "eagle-import:1X01_WITHOUT_TEXT")
      (libsource (lib "eagle-import") (part "M01PTH_WITHOUT_TEXT"))
    )
    (comp (ref "JP379")
      (value "M01PTH_WITHOUT_TEXT")
      (footprint "eagle-import:1X01_WITHOUT_TEXT")
      (libsource (lib "eagle-import") (part "M01PTH_WITHOUT_TEXT"))
    )
    (comp (ref "JP380")
      (value "M01PTH_WITHOUT_TEXT")
      (footprint "eagle-import:1X01_WITHOUT_TEXT")
      (libsource (lib "eagle-import") (part "M01PTH_WITHOUT_TEXT"))
    )
    (comp (ref "JP381")
      (value "M01PTH_WITHOUT_TEXT")
      (footprint "eagle-import:1X01_WITHOUT_TEXT")
      (libsource (lib "eagle-import") (part "M01PTH_WITHOUT_TEXT"))
    )
    (comp (ref "JP382")
      (value "M01PTH_WITHOUT_TEXT")
      (footprint "eagle-import:1X01_WITHOUT_TEXT")
      (libsource (lib "eagle-import") (part "M01PTH_WITHOUT_TEXT"))
    )
    (comp (ref "JP383")
      (value "M01PTH_WITHOUT_TEXT")
      (footprint "eagle-import:1X01_WITHOUT_TEXT")
      (libsource (lib "eagle-import") (part "M01PTH_WITHOUT_TEXT"))
    )
    (comp (ref "JP384")
      (value "M01PTH_WITHOUT_TEXT")
      (footprint "eagle-import:1X01_WITHOUT_TEXT")
      (libsource (lib "eagle-import") (part "M01PTH_WITHOUT_TEXT"))
    )
    (comp (ref "JP385")
      (value "M01PTH_WITHOUT_TEXT")
      (footprint "eagle-import:1X01_WITHOUT_TEXT")
      (libsource (lib "eagle-import") (part "M01PTH_WITHOUT_TEXT"))
    )
    (comp (ref "JP386")
      (value "M01PTH_WITHOUT_TEXT")
      (footprint "eagle-import:1X01_WITHOUT_TEXT")
      (libsource (lib "eagle-import") (part "M01PTH_WITHOUT_TEXT"))
    )
    (comp (ref "JP387")
      (value "M01PTH_WITHOUT_TEXT")
      (footprint "eagle-import:1X01_WITHOUT_TEXT")
      (libsource (lib "eagle-import") (part "M01PTH_WITHOUT_TEXT"))
    )
    (comp (ref "JP388")
      (value "M01PTH_WITHOUT_TEXT")
      (footprint "eagle-import:1X01_WITHOUT_TEXT")
      (libsource (lib "eagle-import") (part "M01PTH_WITHOUT_TEXT"))
    )
    (comp (ref "JP389")
      (value "M01PTH_WITHOUT_TEXT")
      (footprint "eagle-import:1X01_WITHOUT_TEXT")
      (libsource (lib "eagle-import") (part "M01PTH_WITHOUT_TEXT"))
    )
    (comp (ref "JP390")
      (value "M01PTH_WITHOUT_TEXT")
      (footprint "eagle-import:1X01_WITHOUT_TEXT")
      (libsource (lib "eagle-import") (part "M01PTH_WITHOUT_TEXT"))
    )
    (comp (ref "JP391")
      (value "M01PTH_WITHOUT_TEXT")
      (footprint "eagle-import:1X01_WITHOUT_TEXT")
      (libsource (lib "eagle-import") (part "M01PTH_WITHOUT_TEXT"))
    )
    (comp (ref "JP392")
      (value "M01PTH_WITHOUT_TEXT")
      (footprint "eagle-import:1X01_WITHOUT_TEXT")
      (libsource (lib "eagle-import") (part "M01PTH_WITHOUT_TEXT"))
    )
    (comp (ref "JP393")
      (value "M01PTH_WITHOUT_TEXT")
      (footprint "eagle-import:1X01_WITHOUT_TEXT")
      (libsource (lib "eagle-import") (part "M01PTH_WITHOUT_TEXT"))
    )
    (comp (ref "JP394")
      (value "M01PTH_WITHOUT_TEXT")
      (footprint "eagle-import:1X01_WITHOUT_TEXT")
      (libsource (lib "eagle-import") (part "M01PTH_WITHOUT_TEXT"))
    )
    (comp (ref "JP395")
      (value "M01PTH_WITHOUT_TEXT")
      (footprint "eagle-import:1X01_WITHOUT_TEXT")
      (libsource (lib "eagle-import") (part "M01PTH_WITHOUT_TEXT"))
    )
    (comp (ref "JP396")
      (value "M01PTH_WITHOUT_TEXT")
      (footprint "eagle-import:1X01_WITHOUT_TEXT")
      (libsource (lib "eagle-import") (part "M01PTH_WITHOUT_TEXT"))
    )
    (comp (ref "JP397")
      (value "M01PTH_WITHOUT_TEXT")
      (footprint "eagle-import:1X01_WITHOUT_TEXT")
      (libsource (lib "eagle-import") (part "M01PTH_WITHOUT_TEXT"))
    )
    (comp (ref "JP398")
      (value "M01PTH_WITHOUT_TEXT")
      (footprint "eagle-import:1X01_WITHOUT_TEXT")
      (libsource (lib "eagle-import") (part "M01PTH_WITHOUT_TEXT"))
    )
    (comp (ref "JP399")
      (value "M01PTH_WITHOUT_TEXT")
      (footprint "eagle-import:1X01_WITHOUT_TEXT")
      (libsource (lib "eagle-import") (part "M01PTH_WITHOUT_TEXT"))
    )
    (comp (ref "JP400")
      (value "M01PTH_WITHOUT_TEXT")
      (footprint "eagle-import:1X01_WITHOUT_TEXT")
      (libsource (lib "eagle-import") (part "M01PTH_WITHOUT_TEXT"))
    )
    (comp (ref "JP401")
      (value "M01PTH_WITHOUT_TEXT")
      (footprint "eagle-import:1X01_WITHOUT_TEXT")
      (libsource (lib "eagle-import") (part "M01PTH_WITHOUT_TEXT"))
    )
    (comp (ref "JP402")
      (value "M01PTH_WITHOUT_TEXT")
      (footprint "eagle-import:1X01_WITHOUT_TEXT")
      (libsource (lib "eagle-import") (part "M01PTH_WITHOUT_TEXT"))
    )
    (comp (ref "JP403")
      (value "M01PTH_WITHOUT_TEXT")
      (footprint "eagle-import:1X01_WITHOUT_TEXT")
      (libsource (lib "eagle-import") (part "M01PTH_WITHOUT_TEXT"))
    )
    (comp (ref "JP404")
      (value "M01PTH_WITHOUT_TEXT")
      (footprint "eagle-import:1X01_WITHOUT_TEXT")
      (libsource (lib "eagle-import") (part "M01PTH_WITHOUT_TEXT"))
    )
    (comp (ref "JP405")
      (value "M01PTH_WITHOUT_TEXT")
      (footprint "eagle-import:1X01_WITHOUT_TEXT")
      (libsource (lib "eagle-import") (part "M01PTH_WITHOUT_TEXT"))
    )
    (comp (ref "JP406")
      (value "M01PTH_WITHOUT_TEXT")
      (footprint "eagle-import:1X01_WITHOUT_TEXT")
      (libsource (lib "eagle-import") (part "M01PTH_WITHOUT_TEXT"))
    )
    (comp (ref "JP407")
      (value "M01PTH_WITHOUT_TEXT")
      (footprint "eagle-import:1X01_WITHOUT_TEXT")
      (libsource (lib "eagle-import") (part "M01PTH_WITHOUT_TEXT"))
    )
    (comp (ref "JP408")
      (value "M01PTH_WITHOUT_TEXT")
      (footprint "eagle-import:1X01_WITHOUT_TEXT")
      (libsource (lib "eagle-import") (part "M01PTH_WITHOUT_TEXT"))
    )
    (comp (ref "JP409")
      (value "M01PTH_WITHOUT_TEXT")
      (footprint "eagle-import:1X01_WITHOUT_TEXT")
      (libsource (lib "eagle-import") (part "M01PTH_WITHOUT_TEXT"))
    )
    (comp (ref "JP410")
      (value "M01PTH_WITHOUT_TEXT")
      (footprint "eagle-import:1X01_WITHOUT_TEXT")
      (libsource (lib "eagle-import") (part "M01PTH_WITHOUT_TEXT"))
    )
    (comp (ref "JP411")
      (value "M01PTH_WITHOUT_TEXT")
      (footprint "eagle-import:1X01_WITHOUT_TEXT")
      (libsource (lib "eagle-import") (part "M01PTH_WITHOUT_TEXT"))
    )
    (comp (ref "JP412")
      (value "M01PTH_WITHOUT_TEXT")
      (footprint "eagle-import:1X01_WITHOUT_TEXT")
      (libsource (lib "eagle-import") (part "M01PTH_WITHOUT_TEXT"))
    )
    (comp (ref "JP413")
      (value "M01PTH_WITHOUT_TEXT")
      (footprint "eagle-import:1X01_WITHOUT_TEXT")
      (libsource (lib "eagle-import") (part "M01PTH_WITHOUT_TEXT"))
    )
    (comp (ref "JP414")
      (value "M01PTH_WITHOUT_TEXT")
      (footprint "eagle-import:1X01_WITHOUT_TEXT")
      (libsource (lib "eagle-import") (part "M01PTH_WITHOUT_TEXT"))
    )
    (comp (ref "JP415")
      (value "M01PTH_WITHOUT_TEXT")
      (footprint "eagle-import:1X01_WITHOUT_TEXT")
      (libsource (lib "eagle-import") (part "M01PTH_WITHOUT_TEXT"))
    )
    (comp (ref "JP416")
      (value "M01PTH_WITHOUT_TEXT")
      (footprint "eagle-import:1X01_WITHOUT_TEXT")
      (libsource (lib "eagle-import") (part "M01PTH_WITHOUT_TEXT"))
    )
    (comp (ref "JP417")
      (value "M01PTH_WITHOUT_TEXT")
      (footprint "eagle-import:1X01_WITHOUT_TEXT")
      (libsource (lib "eagle-import") (part "M01PTH_WITHOUT_TEXT"))
    )
    (comp (ref "JP418")
      (value "M01PTH_WITHOUT_TEXT")
      (footprint "eagle-import:1X01_WITHOUT_TEXT")
      (libsource (lib "eagle-import") (part "M01PTH_WITHOUT_TEXT"))
    )
    (comp (ref "JP419")
      (value "M01PTH_WITHOUT_TEXT")
      (footprint "eagle-import:1X01_WITHOUT_TEXT")
      (libsource (lib "eagle-import") (part "M01PTH_WITHOUT_TEXT"))
    )
    (comp (ref "JP420")
      (value "M01PTH_WITHOUT_TEXT")
      (footprint "eagle-import:1X01_WITHOUT_TEXT")
      (libsource (lib "eagle-import") (part "M01PTH_WITHOUT_TEXT"))
    )
    (comp (ref "JP421")
      (value "M01PTH_WITHOUT_TEXT")
      (footprint "eagle-import:1X01_WITHOUT_TEXT")
      (libsource (lib "eagle-import") (part "M01PTH_WITHOUT_TEXT"))
    )
    (comp (ref "JP422")
      (value "M01PTH_WITHOUT_TEXT")
      (footprint "eagle-import:1X01_WITHOUT_TEXT")
      (libsource (lib "eagle-import") (part "M01PTH_WITHOUT_TEXT"))
    )
    (comp (ref "JP423")
      (value "M01PTH_WITHOUT_TEXT")
      (footprint "eagle-import:1X01_WITHOUT_TEXT")
      (libsource (lib "eagle-import") (part "M01PTH_WITHOUT_TEXT"))
    )
    (comp (ref "JP424")
      (value "M01PTH_WITHOUT_TEXT")
      (footprint "eagle-import:1X01_WITHOUT_TEXT")
      (libsource (lib "eagle-import") (part "M01PTH_WITHOUT_TEXT"))
    )
    (comp (ref "JP425")
      (value "M01PTH_WITHOUT_TEXT")
      (footprint "eagle-import:1X01_WITHOUT_TEXT")
      (libsource (lib "eagle-import") (part "M01PTH_WITHOUT_TEXT"))
    )
    (comp (ref "JP426")
      (value "M01PTH_WITHOUT_TEXT")
      (footprint "eagle-import:1X01_WITHOUT_TEXT")
      (libsource (lib "eagle-import") (part "M01PTH_WITHOUT_TEXT"))
    )
    (comp (ref "JP427")
      (value "M01PTH_WITHOUT_TEXT")
      (footprint "eagle-import:1X01_WITHOUT_TEXT")
      (libsource (lib "eagle-import") (part "M01PTH_WITHOUT_TEXT"))
    )
    (comp (ref "JP428")
      (value "M01PTH_WITHOUT_TEXT")
      (footprint "eagle-import:1X01_WITHOUT_TEXT")
      (libsource (lib "eagle-import") (part "M01PTH_WITHOUT_TEXT"))
    )
    (comp (ref "JP429")
      (value "M01PTH_WITHOUT_TEXT")
      (footprint "eagle-import:1X01_WITHOUT_TEXT")
      (libsource (lib "eagle-import") (part "M01PTH_WITHOUT_TEXT"))
    )
    (comp (ref "JP430")
      (value "M01PTH_WITHOUT_TEXT")
      (footprint "eagle-import:1X01_WITHOUT_TEXT")
      (libsource (lib "eagle-import") (part "M01PTH_WITHOUT_TEXT"))
    )
    (comp (ref "JP431")
      (value "M01PTH_WITHOUT_TEXT")
      (footprint "eagle-import:1X01_WITHOUT_TEXT")
      (libsource (lib "eagle-import") (part "M01PTH_WITHOUT_TEXT"))
    )
    (comp (ref "JP432")
      (value "M01PTH_WITHOUT_TEXT")
      (footprint "eagle-import:1X01_WITHOUT_TEXT")
      (libsource (lib "eagle-import") (part "M01PTH_WITHOUT_TEXT"))
    )
    (comp (ref "JP433")
      (value "M01PTH_WITHOUT_TEXT")
      (footprint "eagle-import:1X01_WITHOUT_TEXT")
      (libsource (lib "eagle-import") (part "M01PTH_WITHOUT_TEXT"))
    )
    (comp (ref "JP434")
      (value "M01PTH_WITHOUT_TEXT")
      (footprint "eagle-import:1X01_WITHOUT_TEXT")
      (libsource (lib "eagle-import") (part "M01PTH_WITHOUT_TEXT"))
    )
    (comp (ref "JP435")
      (value "M01PTH_WITHOUT_TEXT")
      (footprint "eagle-import:1X01_WITHOUT_TEXT")
      (libsource (lib "eagle-import") (part "M01PTH_WITHOUT_TEXT"))
    )
    (comp (ref "JP436")
      (value "M01PTH_WITHOUT_TEXT")
      (footprint "eagle-import:1X01_WITHOUT_TEXT")
      (libsource (lib "eagle-import") (part "M01PTH_WITHOUT_TEXT"))
    )
    (comp (ref "JP437")
      (value "M01PTH_WITHOUT_TEXT")
      (footprint "eagle-import:1X01_WITHOUT_TEXT")
      (libsource (lib "eagle-import") (part "M01PTH_WITHOUT_TEXT"))
    )
    (comp (ref "JP438")
      (value "M01PTH_WITHOUT_TEXT")
      (footprint "eagle-import:1X01_WITHOUT_TEXT")
      (libsource (lib "eagle-import") (part "M01PTH_WITHOUT_TEXT"))
    )
    (comp (ref "JP439")
      (value "M01PTH_WITHOUT_TEXT")
      (footprint "eagle-import:1X01_WITHOUT_TEXT")
      (libsource (lib "eagle-import") (part "M01PTH_WITHOUT_TEXT"))
    )
    (comp (ref "JP440")
      (value "M01PTH_WITHOUT_TEXT")
      (footprint "eagle-import:1X01_WITHOUT_TEXT")
      (libsource (lib "eagle-import") (part "M01PTH_WITHOUT_TEXT"))
    )
    (comp (ref "JP441")
      (value "M01PTH_WITHOUT_TEXT")
      (footprint "eagle-import:1X01_WITHOUT_TEXT")
      (libsource (lib "eagle-import") (part "M01PTH_WITHOUT_TEXT"))
    )
    (comp (ref "JP442")
      (value "M01PTH_WITHOUT_TEXT")
      (footprint "eagle-import:1X01_WITHOUT_TEXT")
      (libsource (lib "eagle-import") (part "M01PTH_WITHOUT_TEXT"))
    )
    (comp (ref "JP443")
      (value "M01PTH_WITHOUT_TEXT")
      (footprint "eagle-import:1X01_WITHOUT_TEXT")
      (libsource (lib "eagle-import") (part "M01PTH_WITHOUT_TEXT"))
    )
    (comp (ref "JP444")
      (value "M01PTH_WITHOUT_TEXT")
      (footprint "eagle-import:1X01_WITHOUT_TEXT")
      (libsource (lib "eagle-import") (part "M01PTH_WITHOUT_TEXT"))
    )
    (comp (ref "JP445")
      (value "M01PTH_WITHOUT_TEXT")
      (footprint "eagle-import:1X01_WITHOUT_TEXT")
      (libsource (lib "eagle-import") (part "M01PTH_WITHOUT_TEXT"))
    )
    (comp (ref "JP446")
      (value "M01PTH_WITHOUT_TEXT")
      (footprint "eagle-import:1X01_WITHOUT_TEXT")
      (libsource (lib "eagle-import") (part "M01PTH_WITHOUT_TEXT"))
    )
    (comp (ref "JP447")
      (value "M01PTH_WITHOUT_TEXT")
      (footprint "eagle-import:1X01_WITHOUT_TEXT")
      (libsource (lib "eagle-import") (part "M01PTH_WITHOUT_TEXT"))
    )
    (comp (ref "JP448")
      (value "M01PTH_WITHOUT_TEXT")
      (footprint "eagle-import:1X01_WITHOUT_TEXT")
      (libsource (lib "eagle-import") (part "M01PTH_WITHOUT_TEXT"))
    )
    (comp (ref "JP449")
      (value "M01PTH_WITHOUT_TEXT")
      (footprint "eagle-import:1X01_WITHOUT_TEXT")
      (libsource (lib "eagle-import") (part "M01PTH_WITHOUT_TEXT"))
    )
    (comp (ref "JP450")
      (value "M01PTH_WITHOUT_TEXT")
      (footprint "eagle-import:1X01_WITHOUT_TEXT")
      (libsource (lib "eagle-import") (part "M01PTH_WITHOUT_TEXT"))
    )
    (comp (ref "JP451")
      (value "M01PTH_WITHOUT_TEXT")
      (footprint "eagle-import:1X01_WITHOUT_TEXT")
      (libsource (lib "eagle-import") (part "M01PTH_WITHOUT_TEXT"))
    )
    (comp (ref "JP452")
      (value "M01PTH_WITHOUT_TEXT")
      (footprint "eagle-import:1X01_WITHOUT_TEXT")
      (libsource (lib "eagle-import") (part "M01PTH_WITHOUT_TEXT"))
    )
    (comp (ref "JP453")
      (value "M01PTH_WITHOUT_TEXT")
      (footprint "eagle-import:1X01_WITHOUT_TEXT")
      (libsource (lib "eagle-import") (part "M01PTH_WITHOUT_TEXT"))
    )
    (comp (ref "JP454")
      (value "M01PTH_WITHOUT_TEXT")
      (footprint "eagle-import:1X01_WITHOUT_TEXT")
      (libsource (lib "eagle-import") (part "M01PTH_WITHOUT_TEXT"))
    )
    (comp (ref "JP455")
      (value "M01PTH_WITHOUT_TEXT")
      (footprint "eagle-import:1X01_WITHOUT_TEXT")
      (libsource (lib "eagle-import") (part "M01PTH_WITHOUT_TEXT"))
    )
    (comp (ref "JP456")
      (value "M01PTH_WITHOUT_TEXT")
      (footprint "eagle-import:1X01_WITHOUT_TEXT")
      (libsource (lib "eagle-import") (part "M01PTH_WITHOUT_TEXT"))
    )
    (comp (ref "JP457")
      (value "M01PTH_WITHOUT_TEXT")
      (footprint "eagle-import:1X01_WITHOUT_TEXT")
      (libsource (lib "eagle-import") (part "M01PTH_WITHOUT_TEXT"))
    )
    (comp (ref "JP458")
      (value "M01PTH_WITHOUT_TEXT")
      (footprint "eagle-import:1X01_WITHOUT_TEXT")
      (libsource (lib "eagle-import") (part "M01PTH_WITHOUT_TEXT"))
    )
    (comp (ref "JP459")
      (value "M01PTH_WITHOUT_TEXT")
      (footprint "eagle-import:1X01_WITHOUT_TEXT")
      (libsource (lib "eagle-import") (part "M01PTH_WITHOUT_TEXT"))
    )
    (comp (ref "JP460")
      (value "M01PTH_WITHOUT_TEXT")
      (footprint "eagle-import:1X01_WITHOUT_TEXT")
      (libsource (lib "eagle-import") (part "M01PTH_WITHOUT_TEXT"))
    )
    (comp (ref "JP461")
      (value "M01PTH_WITHOUT_TEXT")
      (footprint "eagle-import:1X01_WITHOUT_TEXT")
      (libsource (lib "eagle-import") (part "M01PTH_WITHOUT_TEXT"))
    )
    (comp (ref "JP462")
      (value "M01PTH_WITHOUT_TEXT")
      (footprint "eagle-import:1X01_WITHOUT_TEXT")
      (libsource (lib "eagle-import") (part "M01PTH_WITHOUT_TEXT"))
    )
    (comp (ref "JP463")
      (value "M01PTH_WITHOUT_TEXT")
      (footprint "eagle-import:1X01_WITHOUT_TEXT")
      (libsource (lib "eagle-import") (part "M01PTH_WITHOUT_TEXT"))
    )
    (comp (ref "JP464")
      (value "M01PTH_WITHOUT_TEXT")
      (footprint "eagle-import:1X01_WITHOUT_TEXT")
      (libsource (lib "eagle-import") (part "M01PTH_WITHOUT_TEXT"))
    )
    (comp (ref "JP465")
      (value "M01PTH_WITHOUT_TEXT")
      (footprint "eagle-import:1X01_WITHOUT_TEXT")
      (libsource (lib "eagle-import") (part "M01PTH_WITHOUT_TEXT"))
    )
    (comp (ref "JP466")
      (value "M01PTH_WITHOUT_TEXT")
      (footprint "eagle-import:1X01_WITHOUT_TEXT")
      (libsource (lib "eagle-import") (part "M01PTH_WITHOUT_TEXT"))
    )
    (comp (ref "JP467")
      (value "M01PTH_WITHOUT_TEXT")
      (footprint "eagle-import:1X01_WITHOUT_TEXT")
      (libsource (lib "eagle-import") (part "M01PTH_WITHOUT_TEXT"))
    )
    (comp (ref "JP468")
      (value "M01PTH_WITHOUT_TEXT")
      (footprint "eagle-import:1X01_WITHOUT_TEXT")
      (libsource (lib "eagle-import") (part "M01PTH_WITHOUT_TEXT"))
    )
    (comp (ref "JP469")
      (value "M01PTH_WITHOUT_TEXT")
      (footprint "eagle-import:1X01_WITHOUT_TEXT")
      (libsource (lib "eagle-import") (part "M01PTH_WITHOUT_TEXT"))
    )
    (comp (ref "JP470")
      (value "M01PTH_WITHOUT_TEXT")
      (footprint "eagle-import:1X01_WITHOUT_TEXT")
      (libsource (lib "eagle-import") (part "M01PTH_WITHOUT_TEXT"))
    )
    (comp (ref "JP471")
      (value "M01PTH_WITHOUT_TEXT")
      (footprint "eagle-import:1X01_WITHOUT_TEXT")
      (libsource (lib "eagle-import") (part "M01PTH_WITHOUT_TEXT"))
    )
    (comp (ref "JP472")
      (value "M01PTH_WITHOUT_TEXT")
      (footprint "eagle-import:1X01_WITHOUT_TEXT")
      (libsource (lib "eagle-import") (part "M01PTH_WITHOUT_TEXT"))
    )
    (comp (ref "JP473")
      (value "M01PTH_WITHOUT_TEXT")
      (footprint "eagle-import:1X01_WITHOUT_TEXT")
      (libsource (lib "eagle-import") (part "M01PTH_WITHOUT_TEXT"))
    )
    (comp (ref "JP474")
      (value "M01PTH_WITHOUT_TEXT")
      (footprint "eagle-import:1X01_WITHOUT_TEXT")
      (libsource (lib "eagle-import") (part "M01PTH_WITHOUT_TEXT"))
    )
    (comp (ref "JP475")
      (value "M01PTH_WITHOUT_TEXT")
      (footprint "eagle-import:1X01_WITHOUT_TEXT")
      (libsource (lib "eagle-import") (part "M01PTH_WITHOUT_TEXT"))
    )
    (comp (ref "JP476")
      (value "M01PTH_WITHOUT_TEXT")
      (footprint "eagle-import:1X01_WITHOUT_TEXT")
      (libsource (lib "eagle-import") (part "M01PTH_WITHOUT_TEXT"))
    )
    (comp (ref "JP477")
      (value "M01PTH_WITHOUT_TEXT")
      (footprint "eagle-import:1X01_WITHOUT_TEXT")
      (libsource (lib "eagle-import") (part "M01PTH_WITHOUT_TEXT"))
    )
    (comp (ref "JP478")
      (value "M01PTH_WITHOUT_TEXT")
      (footprint "eagle-import:1X01_WITHOUT_TEXT")
      (libsource (lib "eagle-import") (part "M01PTH_WITHOUT_TEXT"))
    )
    (comp (ref "JP479")
      (value "M01PTH_WITHOUT_TEXT")
      (footprint "eagle-import:1X01_WITHOUT_TEXT")
      (libsource (lib "eagle-import") (part "M01PTH_WITHOUT_TEXT"))
    )
    (comp (ref "JP480")
      (value "M01PTH_WITHOUT_TEXT")
      (footprint "eagle-import:1X01_WITHOUT_TEXT")
      (libsource (lib "eagle-import") (part "M01PTH_WITHOUT_TEXT"))
    )
    (comp (ref "JP481")
      (value "M01PTH_WITHOUT_TEXT")
      (footprint "eagle-import:1X01_WITHOUT_TEXT")
      (libsource (lib "eagle-import") (part "M01PTH_WITHOUT_TEXT"))
    )
    (comp (ref "JP482")
      (value "M01PTH_WITHOUT_TEXT")
      (footprint "eagle-import:1X01_WITHOUT_TEXT")
      (libsource (lib "eagle-import") (part "M01PTH_WITHOUT_TEXT"))
    )
    (comp (ref "JP483")
      (value "M01PTH_WITHOUT_TEXT")
      (footprint "eagle-import:1X01_WITHOUT_TEXT")
      (libsource (lib "eagle-import") (part "M01PTH_WITHOUT_TEXT"))
    )
    (comp (ref "JP484")
      (value "M01PTH_WITHOUT_TEXT")
      (footprint "eagle-import:1X01_WITHOUT_TEXT")
      (libsource (lib "eagle-import") (part "M01PTH_WITHOUT_TEXT"))
    )
    (comp (ref "JP485")
      (value "M01PTH_WITHOUT_TEXT")
      (footprint "eagle-import:1X01_WITHOUT_TEXT")
      (libsource (lib "eagle-import") (part "M01PTH_WITHOUT_TEXT"))
    )
    (comp (ref "JP486")
      (value "M01PTH_WITHOUT_TEXT")
      (footprint "eagle-import:1X01_WITHOUT_TEXT")
      (libsource (lib "eagle-import") (part "M01PTH_WITHOUT_TEXT"))
    )
    (comp (ref "JP487")
      (value "M01PTH_WITHOUT_TEXT")
      (footprint "eagle-import:1X01_WITHOUT_TEXT")
      (libsource (lib "eagle-import") (part "M01PTH_WITHOUT_TEXT"))
    )
    (comp (ref "JP488")
      (value "M01PTH_WITHOUT_TEXT")
      (footprint "eagle-import:1X01_WITHOUT_TEXT")
      (libsource (lib "eagle-import") (part "M01PTH_WITHOUT_TEXT"))
    )
    (comp (ref "JP489")
      (value "M01PTH_WITHOUT_TEXT")
      (footprint "eagle-import:1X01_WITHOUT_TEXT")
      (libsource (lib "eagle-import") (part "M01PTH_WITHOUT_TEXT"))
    )
    (comp (ref "JP490")
      (value "M01PTH_WITHOUT_TEXT")
      (footprint "eagle-import:1X01_WITHOUT_TEXT")
      (libsource (lib "eagle-import") (part "M01PTH_WITHOUT_TEXT"))
    )
    (comp (ref "JP491")
      (value "M01PTH_WITHOUT_TEXT")
      (footprint "eagle-import:1X01_WITHOUT_TEXT")
      (libsource (lib "eagle-import") (part "M01PTH_WITHOUT_TEXT"))
    )
    (comp (ref "JP492")
      (value "M01PTH_WITHOUT_TEXT")
      (footprint "eagle-import:1X01_WITHOUT_TEXT")
      (libsource (lib "eagle-import") (part "M01PTH_WITHOUT_TEXT"))
    )
    (comp (ref "JP493")
      (value "M01PTH_WITHOUT_TEXT")
      (footprint "eagle-import:1X01_WITHOUT_TEXT")
      (libsource (lib "eagle-import") (part "M01PTH_WITHOUT_TEXT"))
    )
    (comp (ref "JP494")
      (value "M01PTH_WITHOUT_TEXT")
      (footprint "eagle-import:1X01_WITHOUT_TEXT")
      (libsource (lib "eagle-import") (part "M01PTH_WITHOUT_TEXT"))
    )
    (comp (ref "JP495")
      (value "M01PTH_WITHOUT_TEXT")
      (footprint "eagle-import:1X01_WITHOUT_TEXT")
      (libsource (lib "eagle-import") (part "M01PTH_WITHOUT_TEXT"))
    )
    (comp (ref "JP496")
      (value "M01PTH_WITHOUT_TEXT")
      (footprint "eagle-import:1X01_WITHOUT_TEXT")
      (libsource (lib "eagle-import") (part "M01PTH_WITHOUT_TEXT"))
    )
    (comp (ref "JP497")
      (value "M01PTH_WITHOUT_TEXT")
      (footprint "eagle-import:1X01_WITHOUT_TEXT")
      (libsource (lib "eagle-import") (part "M01PTH_WITHOUT_TEXT"))
    )
    (comp (ref "JP498")
      (value "M01PTH_WITHOUT_TEXT")
      (footprint "eagle-import:1X01_WITHOUT_TEXT")
      (libsource (lib "eagle-import") (part "M01PTH_WITHOUT_TEXT"))
    )
    (comp (ref "JP499")
      (value "M01PTH_WITHOUT_TEXT")
      (footprint "eagle-import:1X01_WITHOUT_TEXT")
      (libsource (lib "eagle-import") (part "M01PTH_WITHOUT_TEXT"))
    )
    (comp (ref "JP500")
      (value "M01PTH_WITHOUT_TEXT")
      (footprint "eagle-import:1X01_WITHOUT_TEXT")
      (libsource (lib "eagle-import") (part "M01PTH_WITHOUT_TEXT"))
    )
    (comp (ref "JP501")
      (value "M01PTH_WITHOUT_TEXT")
      (footprint "eagle-import:1X01_WITHOUT_TEXT")
      (libsource (lib "eagle-import") (part "M01PTH_WITHOUT_TEXT"))
    )
    (comp (ref "JP502")
      (value "M01PTH_WITHOUT_TEXT")
      (footprint "eagle-import:1X01_WITHOUT_TEXT")
      (libsource (lib "eagle-import") (part "M01PTH_WITHOUT_TEXT"))
    )
    (comp (ref "JP503")
      (value "M01PTH_WITHOUT_TEXT")
      (footprint "eagle-import:1X01_WITHOUT_TEXT")
      (libsource (lib "eagle-import") (part "M01PTH_WITHOUT_TEXT"))
    )
    (comp (ref "JP504")
      (value "M01PTH_WITHOUT_TEXT")
      (footprint "eagle-import:1X01_WITHOUT_TEXT")
      (libsource (lib "eagle-import") (part "M01PTH_WITHOUT_TEXT"))
    )
    (comp (ref "JP505")
      (value "M01PTH_WITHOUT_TEXT")
      (footprint "eagle-import:1X01_WITHOUT_TEXT")
      (libsource (lib "eagle-import") (part "M01PTH_WITHOUT_TEXT"))
    )
    (comp (ref "JP506")
      (value "M01PTH_WITHOUT_TEXT")
      (footprint "eagle-import:1X01_WITHOUT_TEXT")
      (libsource (lib "eagle-import") (part "M01PTH_WITHOUT_TEXT"))
    )
    (comp (ref "JP507")
      (value "M01PTH_WITHOUT_TEXT")
      (footprint "eagle-import:1X01_WITHOUT_TEXT")
      (libsource (lib "eagle-import") (part "M01PTH_WITHOUT_TEXT"))
    )
    (comp (ref "JP508")
      (value "M01PTH_WITHOUT_TEXT")
      (footprint "eagle-import:1X01_WITHOUT_TEXT")
      (libsource (lib "eagle-import") (part "M01PTH_WITHOUT_TEXT"))
    )
    (comp (ref "JP509")
      (value "M01PTH_WITHOUT_TEXT")
      (footprint "eagle-import:1X01_WITHOUT_TEXT")
      (libsource (lib "eagle-import") (part "M01PTH_WITHOUT_TEXT"))
    )
    (comp (ref "JP510")
      (value "M01PTH_WITHOUT_TEXT")
      (footprint "eagle-import:1X01_WITHOUT_TEXT")
      (libsource (lib "eagle-import") (part "M01PTH_WITHOUT_TEXT"))
    )
    (comp (ref "JP511")
      (value "M01PTH_WITHOUT_TEXT")
      (footprint "eagle-import:1X01_WITHOUT_TEXT")
      (libsource (lib "eagle-import") (part "M01PTH_WITHOUT_TEXT"))
    )
    (comp (ref "JP512")
      (value "M01PTH_WITHOUT_TEXT")
      (footprint "eagle-import:1X01_WITHOUT_TEXT")
      (libsource (lib "eagle-import") (part "M01PTH_WITHOUT_TEXT"))
    )
    (comp (ref "JP513")
      (value "M01PTH_WITHOUT_TEXT")
      (footprint "eagle-import:1X01_WITHOUT_TEXT")
      (libsource (lib "eagle-import") (part "M01PTH_WITHOUT_TEXT"))
    )
    (comp (ref "JP514")
      (value "M01PTH_WITHOUT_TEXT")
      (footprint "eagle-import:1X01_WITHOUT_TEXT")
      (libsource (lib "eagle-import") (part "M01PTH_WITHOUT_TEXT"))
    )
    (comp (ref "JP515")
      (value "M01PTH_WITHOUT_TEXT")
      (footprint "eagle-import:1X01_WITHOUT_TEXT")
      (libsource (lib "eagle-import") (part "M01PTH_WITHOUT_TEXT"))
    )
    (comp (ref "JP516")
      (value "M01PTH_WITHOUT_TEXT")
      (footprint "eagle-import:1X01_WITHOUT_TEXT")
      (libsource (lib "eagle-import") (part "M01PTH_WITHOUT_TEXT"))
    )
    (comp (ref "JP517")
      (value "M01PTH_WITHOUT_TEXT")
      (footprint "eagle-import:1X01_WITHOUT_TEXT")
      (libsource (lib "eagle-import") (part "M01PTH_WITHOUT_TEXT"))
    )
    (comp (ref "JP518")
      (value "M01PTH_WITHOUT_TEXT")
      (footprint "eagle-import:1X01_WITHOUT_TEXT")
      (libsource (lib "eagle-import") (part "M01PTH_WITHOUT_TEXT"))
    )
    (comp (ref "JP519")
      (value "M01PTH_WITHOUT_TEXT")
      (footprint "eagle-import:1X01_WITHOUT_TEXT")
      (libsource (lib "eagle-import") (part "M01PTH_WITHOUT_TEXT"))
    )
    (comp (ref "JP520")
      (value "M01PTH_WITHOUT_TEXT")
      (footprint "eagle-import:1X01_WITHOUT_TEXT")
      (libsource (lib "eagle-import") (part "M01PTH_WITHOUT_TEXT"))
    )
    (comp (ref "JP521")
      (value "M01PTH_WITHOUT_TEXT")
      (footprint "eagle-import:1X01_WITHOUT_TEXT")
      (libsource (lib "eagle-import") (part "M01PTH_WITHOUT_TEXT"))
    )
    (comp (ref "JP522")
      (value "M01PTH_WITHOUT_TEXT")
      (footprint "eagle-import:1X01_WITHOUT_TEXT")
      (libsource (lib "eagle-import") (part "M01PTH_WITHOUT_TEXT"))
    )
    (comp (ref "JP523")
      (value "M01PTH_WITHOUT_TEXT")
      (footprint "eagle-import:1X01_WITHOUT_TEXT")
      (libsource (lib "eagle-import") (part "M01PTH_WITHOUT_TEXT"))
    )
    (comp (ref "JP524")
      (value "M01PTH_WITHOUT_TEXT")
      (footprint "eagle-import:1X01_WITHOUT_TEXT")
      (libsource (lib "eagle-import") (part "M01PTH_WITHOUT_TEXT"))
    )
    (comp (ref "JP525")
      (value "M01PTH_WITHOUT_TEXT")
      (footprint "eagle-import:1X01_WITHOUT_TEXT")
      (libsource (lib "eagle-import") (part "M01PTH_WITHOUT_TEXT"))
    )
    (comp (ref "JP526")
      (value "M01PTH_WITHOUT_TEXT")
      (footprint "eagle-import:1X01_WITHOUT_TEXT")
      (libsource (lib "eagle-import") (part "M01PTH_WITHOUT_TEXT"))
    )
    (comp (ref "JP527")
      (value "M01PTH_WITHOUT_TEXT")
      (footprint "eagle-import:1X01_WITHOUT_TEXT")
      (libsource (lib "eagle-import") (part "M01PTH_WITHOUT_TEXT"))
    )
    (comp (ref "JP528")
      (value "M01PTH_WITHOUT_TEXT")
      (footprint "eagle-import:1X01_WITHOUT_TEXT")
      (libsource (lib "eagle-import") (part "M01PTH_WITHOUT_TEXT"))
    )
    (comp (ref "JP529")
      (value "M01PTH_WITHOUT_TEXT")
      (footprint "eagle-import:1X01_WITHOUT_TEXT")
      (libsource (lib "eagle-import") (part "M01PTH_WITHOUT_TEXT"))
    )
    (comp (ref "JP530")
      (value "M01PTH_WITHOUT_TEXT")
      (footprint "eagle-import:1X01_WITHOUT_TEXT")
      (libsource (lib "eagle-import") (part "M01PTH_WITHOUT_TEXT"))
    )
    (comp (ref "JP531")
      (value "M01PTH_WITHOUT_TEXT")
      (footprint "eagle-import:1X01_WITHOUT_TEXT")
      (libsource (lib "eagle-import") (part "M01PTH_WITHOUT_TEXT"))
    )
    (comp (ref "JP532")
      (value "M01PTH_WITHOUT_TEXT")
      (footprint "eagle-import:1X01_WITHOUT_TEXT")
      (libsource (lib "eagle-import") (part "M01PTH_WITHOUT_TEXT"))
    )
    (comp (ref "JP533")
      (value "M01PTH_WITHOUT_TEXT")
      (footprint "eagle-import:1X01_WITHOUT_TEXT")
      (libsource (lib "eagle-import") (part "M01PTH_WITHOUT_TEXT"))
    )
    (comp (ref "JP534")
      (value "M01PTH_WITHOUT_TEXT")
      (footprint "eagle-import:1X01_WITHOUT_TEXT")
      (libsource (lib "eagle-import") (part "M01PTH_WITHOUT_TEXT"))
    )
    (comp (ref "JP535")
      (value "M01PTH_WITHOUT_TEXT")
      (footprint "eagle-import:1X01_WITHOUT_TEXT")
      (libsource (lib "eagle-import") (part "M01PTH_WITHOUT_TEXT"))
    )
    (comp (ref "JP536")
      (value "M01PTH_WITHOUT_TEXT")
      (footprint "eagle-import:1X01_WITHOUT_TEXT")
      (libsource (lib "eagle-import") (part "M01PTH_WITHOUT_TEXT"))
    )
    (comp (ref "JP537")
      (value "M01PTH_WITHOUT_TEXT")
      (footprint "eagle-import:1X01_WITHOUT_TEXT")
      (libsource (lib "eagle-import") (part "M01PTH_WITHOUT_TEXT"))
    )
    (comp (ref "JP538")
      (value "M01PTH_WITHOUT_TEXT")
      (footprint "eagle-import:1X01_WITHOUT_TEXT")
      (libsource (lib "eagle-import") (part "M01PTH_WITHOUT_TEXT"))
    )
    (comp (ref "JP539")
      (value "M01PTH_WITHOUT_TEXT")
      (footprint "eagle-import:1X01_WITHOUT_TEXT")
      (libsource (lib "eagle-import") (part "M01PTH_WITHOUT_TEXT"))
    )
    (comp (ref "JP540")
      (value "M01PTH_WITHOUT_TEXT")
      (footprint "eagle-import:1X01_WITHOUT_TEXT")
      (libsource (lib "eagle-import") (part "M01PTH_WITHOUT_TEXT"))
    )
    (comp (ref "JP541")
      (value "M01PTH_WITHOUT_TEXT")
      (footprint "eagle-import:1X01_WITHOUT_TEXT")
      (libsource (lib "eagle-import") (part "M01PTH_WITHOUT_TEXT"))
    )
    (comp (ref "JP542")
      (value "M01PTH_WITHOUT_TEXT")
      (footprint "eagle-import:1X01_WITHOUT_TEXT")
      (libsource (lib "eagle-import") (part "M01PTH_WITHOUT_TEXT"))
    )
    (comp (ref "JP543")
      (value "M01PTH_WITHOUT_TEXT")
      (footprint "eagle-import:1X01_WITHOUT_TEXT")
      (libsource (lib "eagle-import") (part "M01PTH_WITHOUT_TEXT"))
    )
    (comp (ref "JP544")
      (value "M01PTH_WITHOUT_TEXT")
      (footprint "eagle-import:1X01_WITHOUT_TEXT")
      (libsource (lib "eagle-import") (part "M01PTH_WITHOUT_TEXT"))
    )
    (comp (ref "JP545")
      (value "M01PTH_WITHOUT_TEXT")
      (footprint "eagle-import:1X01_WITHOUT_TEXT")
      (libsource (lib "eagle-import") (part "M01PTH_WITHOUT_TEXT"))
    )
    (comp (ref "JP546")
      (value "M01PTH_WITHOUT_TEXT")
      (footprint "eagle-import:1X01_WITHOUT_TEXT")
      (libsource (lib "eagle-import") (part "M01PTH_WITHOUT_TEXT"))
    )
    (comp (ref "JP547")
      (value "M01PTH_WITHOUT_TEXT")
      (footprint "eagle-import:1X01_WITHOUT_TEXT")
      (libsource (lib "eagle-import") (part "M01PTH_WITHOUT_TEXT"))
    )
    (comp (ref "JP548")
      (value "M01PTH_WITHOUT_TEXT")
      (footprint "eagle-import:1X01_WITHOUT_TEXT")
      (libsource (lib "eagle-import") (part "M01PTH_WITHOUT_TEXT"))
    )
    (comp (ref "JP549")
      (value "M01PTH_WITHOUT_TEXT")
      (footprint "eagle-import:1X01_WITHOUT_TEXT")
      (libsource (lib "eagle-import") (part "M01PTH_WITHOUT_TEXT"))
    )
    (comp (ref "JP550")
      (value "M01PTH_WITHOUT_TEXT")
      (footprint "eagle-import:1X01_WITHOUT_TEXT")
      (libsource (lib "eagle-import") (part "M01PTH_WITHOUT_TEXT"))
    )
    (comp (ref "JP551")
      (value "M01PTH_WITHOUT_TEXT")
      (footprint "eagle-import:1X01_WITHOUT_TEXT")
      (libsource (lib "eagle-import") (part "M01PTH_WITHOUT_TEXT"))
    )
    (comp (ref "JP552")
      (value "M01PTH_WITHOUT_TEXT")
      (footprint "eagle-import:1X01_WITHOUT_TEXT")
      (libsource (lib "eagle-import") (part "M01PTH_WITHOUT_TEXT"))
    )
    (comp (ref "JP553")
      (value "M01PTH_WITHOUT_TEXT")
      (footprint "eagle-import:1X01_WITHOUT_TEXT")
      (libsource (lib "eagle-import") (part "M01PTH_WITHOUT_TEXT"))
    )
    (comp (ref "JP554")
      (value "M01PTH_WITHOUT_TEXT")
      (footprint "eagle-import:1X01_WITHOUT_TEXT")
      (libsource (lib "eagle-import") (part "M01PTH_WITHOUT_TEXT"))
    )
    (comp (ref "JP555")
      (value "M01PTH_WITHOUT_TEXT")
      (footprint "eagle-import:1X01_WITHOUT_TEXT")
      (libsource (lib "eagle-import") (part "M01PTH_WITHOUT_TEXT"))
    )
    (comp (ref "JP556")
      (value "M01PTH_WITHOUT_TEXT")
      (footprint "eagle-import:1X01_WITHOUT_TEXT")
      (libsource (lib "eagle-import") (part "M01PTH_WITHOUT_TEXT"))
    )
    (comp (ref "JP557")
      (value "M01PTH_WITHOUT_TEXT")
      (footprint "eagle-import:1X01_WITHOUT_TEXT")
      (libsource (lib "eagle-import") (part "M01PTH_WITHOUT_TEXT"))
    )
    (comp (ref "JP558")
      (value "M01PTH_WITHOUT_TEXT")
      (footprint "eagle-import:1X01_WITHOUT_TEXT")
      (libsource (lib "eagle-import") (part "M01PTH_WITHOUT_TEXT"))
    )
    (comp (ref "JP559")
      (value "M01PTH_WITHOUT_TEXT")
      (footprint "eagle-import:1X01_WITHOUT_TEXT")
      (libsource (lib "eagle-import") (part "M01PTH_WITHOUT_TEXT"))
    )
    (comp (ref "JP560")
      (value "M01PTH_WITHOUT_TEXT")
      (footprint "eagle-import:1X01_WITHOUT_TEXT")
      (libsource (lib "eagle-import") (part "M01PTH_WITHOUT_TEXT"))
    )
    (comp (ref "JP561")
      (value "M01PTH_WITHOUT_TEXT")
      (footprint "eagle-import:1X01_WITHOUT_TEXT")
      (libsource (lib "eagle-import") (part "M01PTH_WITHOUT_TEXT"))
    )
    (comp (ref "JP562")
      (value "M01PTH_WITHOUT_TEXT")
      (footprint "eagle-import:1X01_WITHOUT_TEXT")
      (libsource (lib "eagle-import") (part "M01PTH_WITHOUT_TEXT"))
    )
    (comp (ref "JP563")
      (value "M01PTH_WITHOUT_TEXT")
      (footprint "eagle-import:1X01_WITHOUT_TEXT")
      (libsource (lib "eagle-import") (part "M01PTH_WITHOUT_TEXT"))
    )
    (comp (ref "JP564")
      (value "M01PTH_WITHOUT_TEXT")
      (footprint "eagle-import:1X01_WITHOUT_TEXT")
      (libsource (lib "eagle-import") (part "M01PTH_WITHOUT_TEXT"))
    )
    (comp (ref "JP565")
      (value "M01PTH_WITHOUT_TEXT")
      (footprint "eagle-import:1X01_WITHOUT_TEXT")
      (libsource (lib "eagle-import") (part "M01PTH_WITHOUT_TEXT"))
    )
    (comp (ref "JP566")
      (value "M01PTH_WITHOUT_TEXT")
      (footprint "eagle-import:1X01_WITHOUT_TEXT")
      (libsource (lib "eagle-import") (part "M01PTH_WITHOUT_TEXT"))
    )
    (comp (ref "JP567")
      (value "M01PTH_WITHOUT_TEXT")
      (footprint "eagle-import:1X01_WITHOUT_TEXT")
      (libsource (lib "eagle-import") (part "M01PTH_WITHOUT_TEXT"))
    )
    (comp (ref "JP568")
      (value "M01PTH_WITHOUT_TEXT")
      (footprint "eagle-import:1X01_WITHOUT_TEXT")
      (libsource (lib "eagle-import") (part "M01PTH_WITHOUT_TEXT"))
    )
    (comp (ref "JP569")
      (value "M01PTH_WITHOUT_TEXT")
      (footprint "eagle-import:1X01_WITHOUT_TEXT")
      (libsource (lib "eagle-import") (part "M01PTH_WITHOUT_TEXT"))
    )
    (comp (ref "JP570")
      (value "M01PTH_WITHOUT_TEXT")
      (footprint "eagle-import:1X01_WITHOUT_TEXT")
      (libsource (lib "eagle-import") (part "M01PTH_WITHOUT_TEXT"))
    )
    (comp (ref "JP571")
      (value "M01PTH_WITHOUT_TEXT")
      (footprint "eagle-import:1X01_WITHOUT_TEXT")
      (libsource (lib "eagle-import") (part "M01PTH_WITHOUT_TEXT"))
    )
    (comp (ref "JP572")
      (value "M01PTH_WITHOUT_TEXT")
      (footprint "eagle-import:1X01_WITHOUT_TEXT")
      (libsource (lib "eagle-import") (part "M01PTH_WITHOUT_TEXT"))
    )
    (comp (ref "JP573")
      (value "M01PTH_WITHOUT_TEXT")
      (footprint "eagle-import:1X01_WITHOUT_TEXT")
      (libsource (lib "eagle-import") (part "M01PTH_WITHOUT_TEXT"))
    )
    (comp (ref "JP574")
      (value "M01PTH_WITHOUT_TEXT")
      (footprint "eagle-import:1X01_WITHOUT_TEXT")
      (libsource (lib "eagle-import") (part "M01PTH_WITHOUT_TEXT"))
    )
    (comp (ref "JP575")
      (value "M01PTH_WITHOUT_TEXT")
      (footprint "eagle-import:1X01_WITHOUT_TEXT")
      (libsource (lib "eagle-import") (part "M01PTH_WITHOUT_TEXT"))
    )
    (comp (ref "JP576")
      (value "M01PTH_WITHOUT_TEXT")
      (footprint "eagle-import:1X01_WITHOUT_TEXT")
      (libsource (lib "eagle-import") (part "M01PTH_WITHOUT_TEXT"))
    )
    (comp (ref "JP577")
      (value "M01PTH_WITHOUT_TEXT")
      (footprint "eagle-import:1X01_WITHOUT_TEXT")
      (libsource (lib "eagle-import") (part "M01PTH_WITHOUT_TEXT"))
    )
    (comp (ref "JP578")
      (value "M01PTH_WITHOUT_TEXT")
      (footprint "eagle-import:1X01_WITHOUT_TEXT")
      (libsource (lib "eagle-import") (part "M01PTH_WITHOUT_TEXT"))
    )
    (comp (ref "JP579")
      (value "M01PTH_WITHOUT_TEXT")
      (footprint "eagle-import:1X01_WITHOUT_TEXT")
      (libsource (lib "eagle-import") (part "M01PTH_WITHOUT_TEXT"))
    )
    (comp (ref "JP580")
      (value "M01PTH_WITHOUT_TEXT")
      (footprint "eagle-import:1X01_WITHOUT_TEXT")
      (libsource (lib "eagle-import") (part "M01PTH_WITHOUT_TEXT"))
    )
    (comp (ref "JP581")
      (value "M01PTH_WITHOUT_TEXT")
      (footprint "eagle-import:1X01_WITHOUT_TEXT")
      (libsource (lib "eagle-import") (part "M01PTH_WITHOUT_TEXT"))
    )
    (comp (ref "JP582")
      (value "M01PTH_WITHOUT_TEXT")
      (footprint "eagle-import:1X01_WITHOUT_TEXT")
      (libsource (lib "eagle-import") (part "M01PTH_WITHOUT_TEXT"))
    )
    (comp (ref "JP583")
      (value "M01PTH_WITHOUT_TEXT")
      (footprint "eagle-import:1X01_WITHOUT_TEXT")
      (libsource (lib "eagle-import") (part "M01PTH_WITHOUT_TEXT"))
    )
    (comp (ref "JP584")
      (value "M01PTH_WITHOUT_TEXT")
      (footprint "eagle-import:1X01_WITHOUT_TEXT")
      (libsource (lib "eagle-import") (part "M01PTH_WITHOUT_TEXT"))
    )
    (comp (ref "JP585")
      (value "M01PTH_WITHOUT_TEXT")
      (footprint "eagle-import:1X01_WITHOUT_TEXT")
      (libsource (lib "eagle-import") (part "M01PTH_WITHOUT_TEXT"))
    )
    (comp (ref "JP586")
      (value "M01PTH_WITHOUT_TEXT")
      (footprint "eagle-import:1X01_WITHOUT_TEXT")
      (libsource (lib "eagle-import") (part "M01PTH_WITHOUT_TEXT"))
    )
    (comp (ref "JP587")
      (value "M01PTH_WITHOUT_TEXT")
      (footprint "eagle-import:1X01_WITHOUT_TEXT")
      (libsource (lib "eagle-import") (part "M01PTH_WITHOUT_TEXT"))
    )
    (comp (ref "JP588")
      (value "M01PTH_WITHOUT_TEXT")
      (footprint "eagle-import:1X01_WITHOUT_TEXT")
      (libsource (lib "eagle-import") (part "M01PTH_WITHOUT_TEXT"))
    )
    (comp (ref "JP589")
      (value "M01PTH_WITHOUT_TEXT")
      (footprint "eagle-import:1X01_WITHOUT_TEXT")
      (libsource (lib "eagle-import") (part "M01PTH_WITHOUT_TEXT"))
    )
    (comp (ref "JP590")
      (value "M01PTH_WITHOUT_TEXT")
      (footprint "eagle-import:1X01_WITHOUT_TEXT")
      (libsource (lib "eagle-import") (part "M01PTH_WITHOUT_TEXT"))
    )
    (comp (ref "JP591")
      (value "M01PTH_WITHOUT_TEXT")
      (footprint "eagle-import:1X01_WITHOUT_TEXT")
      (libsource (lib "eagle-import") (part "M01PTH_WITHOUT_TEXT"))
    )
    (comp (ref "JP592")
      (value "M01PTH_WITHOUT_TEXT")
      (footprint "eagle-import:1X01_WITHOUT_TEXT")
      (libsource (lib "eagle-import") (part "M01PTH_WITHOUT_TEXT"))
    )
    (comp (ref "JP593")
      (value "M01PTH_WITHOUT_TEXT")
      (footprint "eagle-import:1X01_WITHOUT_TEXT")
      (libsource (lib "eagle-import") (part "M01PTH_WITHOUT_TEXT"))
    )
    (comp (ref "JP594")
      (value "M01PTH_WITHOUT_TEXT")
      (footprint "eagle-import:1X01_WITHOUT_TEXT")
      (libsource (lib "eagle-import") (part "M01PTH_WITHOUT_TEXT"))
    )
    (comp (ref "JP595")
      (value "M01PTH_WITHOUT_TEXT")
      (footprint "eagle-import:1X01_WITHOUT_TEXT")
      (libsource (lib "eagle-import") (part "M01PTH_WITHOUT_TEXT"))
    )
    (comp (ref "JP596")
      (value "M01PTH_WITHOUT_TEXT")
      (footprint "eagle-import:1X01_WITHOUT_TEXT")
      (libsource (lib "eagle-import") (part "M01PTH_WITHOUT_TEXT"))
    )
    (comp (ref "JP597")
      (value "M01PTH_WITHOUT_TEXT")
      (footprint "eagle-import:1X01_WITHOUT_TEXT")
      (libsource (lib "eagle-import") (part "M01PTH_WITHOUT_TEXT"))
    )
    (comp (ref "JP598")
      (value "M01PTH_WITHOUT_TEXT")
      (footprint "eagle-import:1X01_WITHOUT_TEXT")
      (libsource (lib "eagle-import") (part "M01PTH_WITHOUT_TEXT"))
    )
    (comp (ref "JP599")
      (value "M01PTH_WITHOUT_TEXT")
      (footprint "eagle-import:1X01_WITHOUT_TEXT")
      (libsource (lib "eagle-import") (part "M01PTH_WITHOUT_TEXT"))
    )
    (comp (ref "JP600")
      (value "M01PTH_WITHOUT_TEXT")
      (footprint "eagle-import:1X01_WITHOUT_TEXT")
      (libsource (lib "eagle-import") (part "M01PTH_WITHOUT_TEXT"))
    )
    (comp (ref "JP601")
      (value "M01PTH_SMD_3.25X0.85MM_NO_SILK")
      (footprint "eagle-import:1X01_SMD_3.25X0.85MM_NO_SILK")
      (libsource (lib "eagle-import") (part "M01PTH_SMD_3.25X0.85MM_NO_SILK"))
    )
    (comp (ref "JP602")
      (value "M01PTH_SMD_3.25X0.85MM_NO_SILK")
      (footprint "eagle-import:1X01_SMD_3.25X0.85MM_NO_SILK")
      (libsource (lib "eagle-import") (part "M01PTH_SMD_3.25X0.85MM_NO_SILK"))
    )
    (comp (ref "JP603")
      (value "M01PTH_SMD_3.25X0.85MM_NO_SILK")
      (footprint "eagle-import:1X01_SMD_3.25X0.85MM_NO_SILK")
      (libsource (lib "eagle-import") (part "M01PTH_SMD_3.25X0.85MM_NO_SILK"))
    )
    (comp (ref "JP604")
      (value "M01PTH_SMD_3.25X0.85MM_NO_SILK")
      (footprint "eagle-import:1X01_SMD_3.25X0.85MM_NO_SILK")
      (libsource (lib "eagle-import") (part "M01PTH_SMD_3.25X0.85MM_NO_SILK"))
    )
    (comp (ref "JP605")
      (value "M01PTH_SMD_3.25X0.85MM_NO_SILK")
      (footprint "eagle-import:1X01_SMD_3.25X0.85MM_NO_SILK")
      (libsource (lib "eagle-import") (part "M01PTH_SMD_3.25X0.85MM_NO_SILK"))
    )
    (comp (ref "JP606")
      (value "M01PTH_SMD_3.25X0.85MM_NO_SILK")
      (footprint "eagle-import:1X01_SMD_3.25X0.85MM_NO_SILK")
      (libsource (lib "eagle-import") (part "M01PTH_SMD_3.25X0.85MM_NO_SILK"))
    )
    (comp (ref "JP607")
      (value "M01PTH_SMD_3.25X0.85MM_NO_SILK")
      (footprint "eagle-import:1X01_SMD_3.25X0.85MM_NO_SILK")
      (libsource (lib "eagle-import") (part "M01PTH_SMD_3.25X0.85MM_NO_SILK"))
    )
    (comp (ref "JP608")
      (value "M01PTH_SMD_3.25X0.85MM_NO_SILK")
      (footprint "eagle-import:1X01_SMD_3.25X0.85MM_NO_SILK")
      (libsource (lib "eagle-import") (part "M01PTH_SMD_3.25X0.85MM_NO_SILK"))
    )
    (comp (ref "JP609")
      (value "M01PTH_SMD_3.25X0.85MM_NO_SILK")
      (footprint "eagle-import:1X01_SMD_3.25X0.85MM_NO_SILK")
      (libsource (lib "eagle-import") (part "M01PTH_SMD_3.25X0.85MM_NO_SILK"))
    )
    (comp (ref "JP610")
      (value "M01PTH_SMD_3.25X0.85MM_NO_SILK")
      (footprint "eagle-import:1X01_SMD_3.25X0.85MM_NO_SILK")
      (libsource (lib "eagle-import") (part "M01PTH_SMD_3.25X0.85MM_NO_SILK"))
    )
    (comp (ref "JP611")
      (value "M01PTH_SMD_3.25X0.85MM_NO_SILK")
      (footprint "eagle-import:1X01_SMD_3.25X0.85MM_NO_SILK")
      (libsource (lib "eagle-import") (part "M01PTH_SMD_3.25X0.85MM_NO_SILK"))
    )
    (comp (ref "JP612")
      (value "M01PTH_SMD_3.25X0.85MM_NO_SILK")
      (footprint "eagle-import:1X01_SMD_3.25X0.85MM_NO_SILK")
      (libsource (lib "eagle-import") (part "M01PTH_SMD_3.25X0.85MM_NO_SILK"))
    )
    (comp (ref "JP613")
      (value "M01PTH_SMD_3.25X0.85MM_NO_SILK")
      (footprint "eagle-import:1X01_SMD_3.25X0.85MM_NO_SILK")
      (libsource (lib "eagle-import") (part "M01PTH_SMD_3.25X0.85MM_NO_SILK"))
    )
    (comp (ref "JP614")
      (value "M01PTH_SMD_3.25X0.85MM_NO_SILK")
      (footprint "eagle-import:1X01_SMD_3.25X0.85MM_NO_SILK")
      (libsource (lib "eagle-import") (part "M01PTH_SMD_3.25X0.85MM_NO_SILK"))
    )
    (comp (ref "JP615")
      (value "M01PTH_SMD_3.25X0.85MM_NO_SILK")
      (footprint "eagle-import:1X01_SMD_3.25X0.85MM_NO_SILK")
      (libsource (lib "eagle-import") (part "M01PTH_SMD_3.25X0.85MM_NO_SILK"))
    )
    (comp (ref "JP616")
      (value "M01PTH_SMD_3.25X0.85MM_NO_SILK")
      (footprint "eagle-import:1X01_SMD_3.25X0.85MM_NO_SILK")
      (libsource (lib "eagle-import") (part "M01PTH_SMD_3.25X0.85MM_NO_SILK"))
    )
    (comp (ref "JP617")
      (value "M01PTH_SMD_3.25X0.85MM_NO_SILK")
      (footprint "eagle-import:1X01_SMD_3.25X0.85MM_NO_SILK")
      (libsource (lib "eagle-import") (part "M01PTH_SMD_3.25X0.85MM_NO_SILK"))
    )
    (comp (ref "JP618")
      (value "M01PTH_SMD_3.25X0.85MM_NO_SILK")
      (footprint "eagle-import:1X01_SMD_3.25X0.85MM_NO_SILK")
      (libsource (lib "eagle-import") (part "M01PTH_SMD_3.25X0.85MM_NO_SILK"))
    )
    (comp (ref "JP619")
      (value "M01PTH_SMD_3.25X0.85MM_NO_SILK")
      (footprint "eagle-import:1X01_SMD_3.25X0.85MM_NO_SILK")
      (libsource (lib "eagle-import") (part "M01PTH_SMD_3.25X0.85MM_NO_SILK"))
    )
    (comp (ref "JP620")
      (value "M01PTH_SMD_3.25X0.85MM_NO_SILK")
      (footprint "eagle-import:1X01_SMD_3.25X0.85MM_NO_SILK")
      (libsource (lib "eagle-import") (part "M01PTH_SMD_3.25X0.85MM_NO_SILK"))
    )
    (comp (ref "JP621")
      (value "M01PTH_SMD_3.25X0.85MM_NO_SILK")
      (footprint "eagle-import:1X01_SMD_3.25X0.85MM_NO_SILK")
      (libsource (lib "eagle-import") (part "M01PTH_SMD_3.25X0.85MM_NO_SILK"))
    )
    (comp (ref "JP622")
      (value "M01PTH_SMD_3.25X0.85MM_NO_SILK")
      (footprint "eagle-import:1X01_SMD_3.25X0.85MM_NO_SILK")
      (libsource (lib "eagle-import") (part "M01PTH_SMD_3.25X0.85MM_NO_SILK"))
    )
    (comp (ref "JP623")
      (value "M01PTH_SMD_3.25X0.85MM_NO_SILK")
      (footprint "eagle-import:1X01_SMD_3.25X0.85MM_NO_SILK")
      (libsource (lib "eagle-import") (part "M01PTH_SMD_3.25X0.85MM_NO_SILK"))
    )
    (comp (ref "JP624")
      (value "M01PTH_SMD_3.25X0.85MM_NO_SILK")
      (footprint "eagle-import:1X01_SMD_3.25X0.85MM_NO_SILK")
      (libsource (lib "eagle-import") (part "M01PTH_SMD_3.25X0.85MM_NO_SILK"))
    )
    (comp (ref "JP625")
      (value "M01PTH_SMD_3.25X0.85MM_NO_SILK")
      (footprint "eagle-import:1X01_SMD_3.25X0.85MM_NO_SILK")
      (libsource (lib "eagle-import") (part "M01PTH_SMD_3.25X0.85MM_NO_SILK"))
    )
    (comp (ref "JP626")
      (value "M01PTH_SMD_3.25X0.85MM_NO_SILK")
      (footprint "eagle-import:1X01_SMD_3.25X0.85MM_NO_SILK")
      (libsource (lib "eagle-import") (part "M01PTH_SMD_3.25X0.85MM_NO_SILK"))
    )
    (comp (ref "JP627")
      (value "M01PTH_SMD_3.25X0.85MM_NO_SILK")
      (footprint "eagle-import:1X01_SMD_3.25X0.85MM_NO_SILK")
      (libsource (lib "eagle-import") (part "M01PTH_SMD_3.25X0.85MM_NO_SILK"))
    )
    (comp (ref "JP628")
      (value "M01PTH_SMD_3.25X0.85MM_NO_SILK")
      (footprint "eagle-import:1X01_SMD_3.25X0.85MM_NO_SILK")
      (libsource (lib "eagle-import") (part "M01PTH_SMD_3.25X0.85MM_NO_SILK"))
    )
    (comp (ref "JP629")
      (value "M01PTH_SMD_3.25X0.85MM_NO_SILK")
      (footprint "eagle-import:1X01_SMD_3.25X0.85MM_NO_SILK")
      (libsource (lib "eagle-import") (part "M01PTH_SMD_3.25X0.85MM_NO_SILK"))
    )
    (comp (ref "JP630")
      (value "M01PTH_SMD_3.25X0.85MM_NO_SILK")
      (footprint "eagle-import:1X01_SMD_3.25X0.85MM_NO_SILK")
      (libsource (lib "eagle-import") (part "M01PTH_SMD_3.25X0.85MM_NO_SILK"))
    )
    (comp (ref "JP631")
      (value "M01PTH_SMD_3.25X0.85MM_NO_SILK")
      (footprint "eagle-import:1X01_SMD_3.25X0.85MM_NO_SILK")
      (libsource (lib "eagle-import") (part "M01PTH_SMD_3.25X0.85MM_NO_SILK"))
    )
    (comp (ref "JP632")
      (value "M01PTH_SMD_3.25X0.85MM_NO_SILK")
      (footprint "eagle-import:1X01_SMD_3.25X0.85MM_NO_SILK")
      (libsource (lib "eagle-import") (part "M01PTH_SMD_3.25X0.85MM_NO_SILK"))
    )
    (comp (ref "JP633")
      (value "M01PTH_SMD_3.25X0.85MM_NO_SILK")
      (footprint "eagle-import:1X01_SMD_3.25X0.85MM_NO_SILK")
      (libsource (lib "eagle-import") (part "M01PTH_SMD_3.25X0.85MM_NO_SILK"))
    )
    (comp (ref "JP634")
      (value "M01PTH_SMD_3.25X0.85MM_NO_SILK")
      (footprint "eagle-import:1X01_SMD_3.25X0.85MM_NO_SILK")
      (libsource (lib "eagle-import") (part "M01PTH_SMD_3.25X0.85MM_NO_SILK"))
    )
    (comp (ref "JP635")
      (value "M01PTH_SMD_3.25X0.85MM_NO_SILK")
      (footprint "eagle-import:1X01_SMD_3.25X0.85MM_NO_SILK")
      (libsource (lib "eagle-import") (part "M01PTH_SMD_3.25X0.85MM_NO_SILK"))
    )
    (comp (ref "JP636")
      (value "M01PTH_SMD_3.25X0.85MM_NO_SILK")
      (footprint "eagle-import:1X01_SMD_3.25X0.85MM_NO_SILK")
      (libsource (lib "eagle-import") (part "M01PTH_SMD_3.25X0.85MM_NO_SILK"))
    )
    (comp (ref "JP637")
      (value "M01PTH_SMD_3.25X0.85MM_NO_SILK")
      (footprint "eagle-import:1X01_SMD_3.25X0.85MM_NO_SILK")
      (libsource (lib "eagle-import") (part "M01PTH_SMD_3.25X0.85MM_NO_SILK"))
    )
    (comp (ref "JP638")
      (value "M01PTH_SMD_3.25X0.85MM_NO_SILK")
      (footprint "eagle-import:1X01_SMD_3.25X0.85MM_NO_SILK")
      (libsource (lib "eagle-import") (part "M01PTH_SMD_3.25X0.85MM_NO_SILK"))
    )
    (comp (ref "JP639")
      (value "M01PTH_SMD_3.25X0.85MM_NO_SILK")
      (footprint "eagle-import:1X01_SMD_3.25X0.85MM_NO_SILK")
      (libsource (lib "eagle-import") (part "M01PTH_SMD_3.25X0.85MM_NO_SILK"))
    )
    (comp (ref "JP640")
      (value "M01PTH_SMD_3.25X0.85MM_NO_SILK")
      (footprint "eagle-import:1X01_SMD_3.25X0.85MM_NO_SILK")
      (libsource (lib "eagle-import") (part "M01PTH_SMD_3.25X0.85MM_NO_SILK"))
    )
    (comp (ref "JP641")
      (value "M01PTH_SMD_3.25X0.85MM_NO_SILK")
      (footprint "eagle-import:1X01_SMD_3.25X0.85MM_NO_SILK")
      (libsource (lib "eagle-import") (part "M01PTH_SMD_3.25X0.85MM_NO_SILK"))
    )
    (comp (ref "JP642")
      (value "M01PTH_SMD_3.25X0.85MM_NO_SILK")
      (footprint "eagle-import:1X01_SMD_3.25X0.85MM_NO_SILK")
      (libsource (lib "eagle-import") (part "M01PTH_SMD_3.25X0.85MM_NO_SILK"))
    )
    (comp (ref "JP643")
      (value "M01PTH_SMD_3.25X0.85MM_NO_SILK")
      (footprint "eagle-import:1X01_SMD_3.25X0.85MM_NO_SILK")
      (libsource (lib "eagle-import") (part "M01PTH_SMD_3.25X0.85MM_NO_SILK"))
    )
    (comp (ref "JP644")
      (value "M01PTH_SMD_3.25X0.85MM_NO_SILK")
      (footprint "eagle-import:1X01_SMD_3.25X0.85MM_NO_SILK")
      (libsource (lib "eagle-import") (part "M01PTH_SMD_3.25X0.85MM_NO_SILK"))
    )
    (comp (ref "JP645")
      (value "M01PTH_SMD_3.25X0.85MM_NO_SILK")
      (footprint "eagle-import:1X01_SMD_3.25X0.85MM_NO_SILK")
      (libsource (lib "eagle-import") (part "M01PTH_SMD_3.25X0.85MM_NO_SILK"))
    )
    (comp (ref "JP646")
      (value "M01PTH_SMD_3.25X0.85MM_NO_SILK")
      (footprint "eagle-import:1X01_SMD_3.25X0.85MM_NO_SILK")
      (libsource (lib "eagle-import") (part "M01PTH_SMD_3.25X0.85MM_NO_SILK"))
    )
    (comp (ref "JP647")
      (value "M01PTH_SMD_3.25X0.85MM_NO_SILK")
      (footprint "eagle-import:1X01_SMD_3.25X0.85MM_NO_SILK")
      (libsource (lib "eagle-import") (part "M01PTH_SMD_3.25X0.85MM_NO_SILK"))
    )
    (comp (ref "JP648")
      (value "M01PTH_SMD_3.25X0.85MM_NO_SILK")
      (footprint "eagle-import:1X01_SMD_3.25X0.85MM_NO_SILK")
      (libsource (lib "eagle-import") (part "M01PTH_SMD_3.25X0.85MM_NO_SILK"))
    )
    (comp (ref "JP649")
      (value "M01PTH_SMD_3.25X0.85MM_NO_SILK")
      (footprint "eagle-import:1X01_SMD_3.25X0.85MM_NO_SILK")
      (libsource (lib "eagle-import") (part "M01PTH_SMD_3.25X0.85MM_NO_SILK"))
    )
    (comp (ref "JP650")
      (value "M01PTH_SMD_3.25X0.85MM_NO_SILK")
      (footprint "eagle-import:1X01_SMD_3.25X0.85MM_NO_SILK")
      (libsource (lib "eagle-import") (part "M01PTH_SMD_3.25X0.85MM_NO_SILK"))
    )
    (comp (ref "JP651")
      (value "M01PTH_SMD_3.25X0.85MM_NO_SILK")
      (footprint "eagle-import:1X01_SMD_3.25X0.85MM_NO_SILK")
      (libsource (lib "eagle-import") (part "M01PTH_SMD_3.25X0.85MM_NO_SILK"))
    )
    (comp (ref "JP652")
      (value "M01PTH_SMD_3.25X0.85MM_NO_SILK")
      (footprint "eagle-import:1X01_SMD_3.25X0.85MM_NO_SILK")
      (libsource (lib "eagle-import") (part "M01PTH_SMD_3.25X0.85MM_NO_SILK"))
    )
    (comp (ref "JP653")
      (value "M01PTH_SMD_3.25X0.85MM_NO_SILK")
      (footprint "eagle-import:1X01_SMD_3.25X0.85MM_NO_SILK")
      (libsource (lib "eagle-import") (part "M01PTH_SMD_3.25X0.85MM_NO_SILK"))
    )
    (comp (ref "JP654")
      (value "M01PTH_SMD_3.25X0.85MM_NO_SILK")
      (footprint "eagle-import:1X01_SMD_3.25X0.85MM_NO_SILK")
      (libsource (lib "eagle-import") (part "M01PTH_SMD_3.25X0.85MM_NO_SILK"))
    )
    (comp (ref "JP655")
      (value "M01PTH_SMD_3.25X0.85MM_NO_SILK")
      (footprint "eagle-import:1X01_SMD_3.25X0.85MM_NO_SILK")
      (libsource (lib "eagle-import") (part "M01PTH_SMD_3.25X0.85MM_NO_SILK"))
    )
    (comp (ref "JP656")
      (value "M01PTH_SMD_3.25X0.85MM_NO_SILK")
      (footprint "eagle-import:1X01_SMD_3.25X0.85MM_NO_SILK")
      (libsource (lib "eagle-import") (part "M01PTH_SMD_3.25X0.85MM_NO_SILK"))
    )
    (comp (ref "JP657")
      (value "M01PTH_SMD_3.25X0.85MM_NO_SILK")
      (footprint "eagle-import:1X01_SMD_3.25X0.85MM_NO_SILK")
      (libsource (lib "eagle-import") (part "M01PTH_SMD_3.25X0.85MM_NO_SILK"))
    )
    (comp (ref "JP658")
      (value "M01PTH_SMD_3.25X0.85MM_NO_SILK")
      (footprint "eagle-import:1X01_SMD_3.25X0.85MM_NO_SILK")
      (libsource (lib "eagle-import") (part "M01PTH_SMD_3.25X0.85MM_NO_SILK"))
    )
    (comp (ref "JP659")
      (value "M01PTH_SMD_3.25X0.85MM_NO_SILK")
      (footprint "eagle-import:1X01_SMD_3.25X0.85MM_NO_SILK")
      (libsource (lib "eagle-import") (part "M01PTH_SMD_3.25X0.85MM_NO_SILK"))
    )
    (comp (ref "JP660")
      (value "M01PTH_SMD_3.25X0.85MM_NO_SILK")
      (footprint "eagle-import:1X01_SMD_3.25X0.85MM_NO_SILK")
      (libsource (lib "eagle-import") (part "M01PTH_SMD_3.25X0.85MM_NO_SILK"))
    )
    (comp (ref "JP661")
      (value "M01PTH_SMD_3.25X0.85MM_NO_SILK")
      (footprint "eagle-import:1X01_SMD_3.25X0.85MM_NO_SILK")
      (libsource (lib "eagle-import") (part "M01PTH_SMD_3.25X0.85MM_NO_SILK"))
    )
    (comp (ref "JP662")
      (value "M01PTH_SMD_3.25X0.85MM_NO_SILK")
      (footprint "eagle-import:1X01_SMD_3.25X0.85MM_NO_SILK")
      (libsource (lib "eagle-import") (part "M01PTH_SMD_3.25X0.85MM_NO_SILK"))
    )
    (comp (ref "JP663")
      (value "M01PTH_SMD_3.25X0.85MM_NO_SILK")
      (footprint "eagle-import:1X01_SMD_3.25X0.85MM_NO_SILK")
      (libsource (lib "eagle-import") (part "M01PTH_SMD_3.25X0.85MM_NO_SILK"))
    )
    (comp (ref "JP664")
      (value "M01PTH_SMD_3.25X0.85MM_NO_SILK")
      (footprint "eagle-import:1X01_SMD_3.25X0.85MM_NO_SILK")
      (libsource (lib "eagle-import") (part "M01PTH_SMD_3.25X0.85MM_NO_SILK"))
    )
    (comp (ref "JP665")
      (value "M01PTH_SMD_3.25X0.85MM_NO_SILK")
      (footprint "eagle-import:1X01_SMD_3.25X0.85MM_NO_SILK")
      (libsource (lib "eagle-import") (part "M01PTH_SMD_3.25X0.85MM_NO_SILK"))
    )
    (comp (ref "JP666")
      (value "M01PTH_SMD_3.25X0.85MM_NO_SILK")
      (footprint "eagle-import:1X01_SMD_3.25X0.85MM_NO_SILK")
      (libsource (lib "eagle-import") (part "M01PTH_SMD_3.25X0.85MM_NO_SILK"))
    )
    (comp (ref "JP667")
      (value "M01PTH_SMD_3.25X0.85MM_NO_SILK")
      (footprint "eagle-import:1X01_SMD_3.25X0.85MM_NO_SILK")
      (libsource (lib "eagle-import") (part "M01PTH_SMD_3.25X0.85MM_NO_SILK"))
    )
    (comp (ref "JP668")
      (value "M01PTH_SMD_3.25X0.85MM_NO_SILK")
      (footprint "eagle-import:1X01_SMD_3.25X0.85MM_NO_SILK")
      (libsource (lib "eagle-import") (part "M01PTH_SMD_3.25X0.85MM_NO_SILK"))
    )
    (comp (ref "JP669")
      (value "M01PTH_SMD_3.25X0.85MM_NO_SILK")
      (footprint "eagle-import:1X01_SMD_3.25X0.85MM_NO_SILK")
      (libsource (lib "eagle-import") (part "M01PTH_SMD_3.25X0.85MM_NO_SILK"))
    )
    (comp (ref "JP670")
      (value "M01PTH_SMD_3.25X0.85MM_NO_SILK")
      (footprint "eagle-import:1X01_SMD_3.25X0.85MM_NO_SILK")
      (libsource (lib "eagle-import") (part "M01PTH_SMD_3.25X0.85MM_NO_SILK"))
    )
    (comp (ref "JP671")
      (value "M01PTH_SMD_3.25X0.85MM_NO_SILK")
      (footprint "eagle-import:1X01_SMD_3.25X0.85MM_NO_SILK")
      (libsource (lib "eagle-import") (part "M01PTH_SMD_3.25X0.85MM_NO_SILK"))
    )
    (comp (ref "JP672")
      (value "M01PTH_SMD_3.25X0.85MM_NO_SILK")
      (footprint "eagle-import:1X01_SMD_3.25X0.85MM_NO_SILK")
      (libsource (lib "eagle-import") (part "M01PTH_SMD_3.25X0.85MM_NO_SILK"))
    )
    (comp (ref "JP673")
      (value "M01PTH_SMD_3.25X0.85MM_NO_SILK")
      (footprint "eagle-import:1X01_SMD_3.25X0.85MM_NO_SILK")
      (libsource (lib "eagle-import") (part "M01PTH_SMD_3.25X0.85MM_NO_SILK"))
    )
    (comp (ref "JP674")
      (value "M01PTH_SMD_3.25X0.85MM_NO_SILK")
      (footprint "eagle-import:1X01_SMD_3.25X0.85MM_NO_SILK")
      (libsource (lib "eagle-import") (part "M01PTH_SMD_3.25X0.85MM_NO_SILK"))
    )
    (comp (ref "JP675")
      (value "M01PTH_SMD_3.25X0.85MM_NO_SILK")
      (footprint "eagle-import:1X01_SMD_3.25X0.85MM_NO_SILK")
      (libsource (lib "eagle-import") (part "M01PTH_SMD_3.25X0.85MM_NO_SILK"))
    )
    (comp (ref "JP676")
      (value "M01PTH_SMD_3.25X0.85MM_NO_SILK")
      (footprint "eagle-import:1X01_SMD_3.25X0.85MM_NO_SILK")
      (libsource (lib "eagle-import") (part "M01PTH_SMD_3.25X0.85MM_NO_SILK"))
    )
    (comp (ref "JP677")
      (value "M01PTH_SMD_3.25X0.85MM_NO_SILK")
      (footprint "eagle-import:1X01_SMD_3.25X0.85MM_NO_SILK")
      (libsource (lib "eagle-import") (part "M01PTH_SMD_3.25X0.85MM_NO_SILK"))
    )
    (comp (ref "JP678")
      (value "M01PTH_SMD_3.25X0.85MM_NO_SILK")
      (footprint "eagle-import:1X01_SMD_3.25X0.85MM_NO_SILK")
      (libsource (lib "eagle-import") (part "M01PTH_SMD_3.25X0.85MM_NO_SILK"))
    )
    (comp (ref "JP679")
      (value "M01PTH_SMD_3.25X0.85MM_NO_SILK")
      (footprint "eagle-import:1X01_SMD_3.25X0.85MM_NO_SILK")
      (libsource (lib "eagle-import") (part "M01PTH_SMD_3.25X0.85MM_NO_SILK"))
    )
    (comp (ref "JP680")
      (value "M01PTH_SMD_3.25X0.85MM_NO_SILK")
      (footprint "eagle-import:1X01_SMD_3.25X0.85MM_NO_SILK")
      (libsource (lib "eagle-import") (part "M01PTH_SMD_3.25X0.85MM_NO_SILK"))
    )
    (comp (ref "JP681")
      (value "M01PTH_SMD_3.25X0.85MM_NO_SILK")
      (footprint "eagle-import:1X01_SMD_3.25X0.85MM_NO_SILK")
      (libsource (lib "eagle-import") (part "M01PTH_SMD_3.25X0.85MM_NO_SILK"))
    )
    (comp (ref "JP682")
      (value "M01PTH_SMD_3.25X0.85MM_NO_SILK")
      (footprint "eagle-import:1X01_SMD_3.25X0.85MM_NO_SILK")
      (libsource (lib "eagle-import") (part "M01PTH_SMD_3.25X0.85MM_NO_SILK"))
    )
    (comp (ref "JP683")
      (value "M01PTH_SMD_3.25X0.85MM_NO_SILK")
      (footprint "eagle-import:1X01_SMD_3.25X0.85MM_NO_SILK")
      (libsource (lib "eagle-import") (part "M01PTH_SMD_3.25X0.85MM_NO_SILK"))
    )
    (comp (ref "JP684")
      (value "M01PTH_SMD_3.25X0.85MM_NO_SILK")
      (footprint "eagle-import:1X01_SMD_3.25X0.85MM_NO_SILK")
      (libsource (lib "eagle-import") (part "M01PTH_SMD_3.25X0.85MM_NO_SILK"))
    )
    (comp (ref "JP685")
      (value "M01PTH_SMD_3.25X0.85MM_NO_SILK")
      (footprint "eagle-import:1X01_SMD_3.25X0.85MM_NO_SILK")
      (libsource (lib "eagle-import") (part "M01PTH_SMD_3.25X0.85MM_NO_SILK"))
    )
    (comp (ref "JP686")
      (value "M01PTH_SMD_3.25X0.85MM_NO_SILK")
      (footprint "eagle-import:1X01_SMD_3.25X0.85MM_NO_SILK")
      (libsource (lib "eagle-import") (part "M01PTH_SMD_3.25X0.85MM_NO_SILK"))
    )
    (comp (ref "JP687")
      (value "M01PTH_SMD_3.25X0.85MM_NO_SILK")
      (footprint "eagle-import:1X01_SMD_3.25X0.85MM_NO_SILK")
      (libsource (lib "eagle-import") (part "M01PTH_SMD_3.25X0.85MM_NO_SILK"))
    )
    (comp (ref "JP688")
      (value "M01PTH_SMD_3.25X0.85MM_NO_SILK")
      (footprint "eagle-import:1X01_SMD_3.25X0.85MM_NO_SILK")
      (libsource (lib "eagle-import") (part "M01PTH_SMD_3.25X0.85MM_NO_SILK"))
    )
    (comp (ref "JP689")
      (value "M01PTH_SMD_3.25X0.85MM_NO_SILK")
      (footprint "eagle-import:1X01_SMD_3.25X0.85MM_NO_SILK")
      (libsource (lib "eagle-import") (part "M01PTH_SMD_3.25X0.85MM_NO_SILK"))
    )
    (comp (ref "JP690")
      (value "M01PTH_SMD_3.25X0.85MM_NO_SILK")
      (footprint "eagle-import:1X01_SMD_3.25X0.85MM_NO_SILK")
      (libsource (lib "eagle-import") (part "M01PTH_SMD_3.25X0.85MM_NO_SILK"))
    )
    (comp (ref "JP691")
      (value "M01PTH_SMD_3.25X0.85MM_NO_SILK")
      (footprint "eagle-import:1X01_SMD_3.25X0.85MM_NO_SILK")
      (libsource (lib "eagle-import") (part "M01PTH_SMD_3.25X0.85MM_NO_SILK"))
    )
    (comp (ref "JP692")
      (value "M01PTH_SMD_3.25X0.85MM_NO_SILK")
      (footprint "eagle-import:1X01_SMD_3.25X0.85MM_NO_SILK")
      (libsource (lib "eagle-import") (part "M01PTH_SMD_3.25X0.85MM_NO_SILK"))
    )
    (comp (ref "JP693")
      (value "M01PTH_SMD_3.25X0.85MM_NO_SILK")
      (footprint "eagle-import:1X01_SMD_3.25X0.85MM_NO_SILK")
      (libsource (lib "eagle-import") (part "M01PTH_SMD_3.25X0.85MM_NO_SILK"))
    )
    (comp (ref "JP694")
      (value "M01PTH_SMD_3.25X0.85MM_NO_SILK")
      (footprint "eagle-import:1X01_SMD_3.25X0.85MM_NO_SILK")
      (libsource (lib "eagle-import") (part "M01PTH_SMD_3.25X0.85MM_NO_SILK"))
    )
    (comp (ref "JP695")
      (value "M01PTH_SMD_3.25X0.85MM_NO_SILK")
      (footprint "eagle-import:1X01_SMD_3.25X0.85MM_NO_SILK")
      (libsource (lib "eagle-import") (part "M01PTH_SMD_3.25X0.85MM_NO_SILK"))
    )
    (comp (ref "JP696")
      (value "M01PTH_SMD_3.25X0.85MM_NO_SILK")
      (footprint "eagle-import:1X01_SMD_3.25X0.85MM_NO_SILK")
      (libsource (lib "eagle-import") (part "M01PTH_SMD_3.25X0.85MM_NO_SILK"))
    )
    (comp (ref "JP697")
      (value "M01PTH_SMD_3.25X0.85MM_NO_SILK")
      (footprint "eagle-import:1X01_SMD_3.25X0.85MM_NO_SILK")
      (libsource (lib "eagle-import") (part "M01PTH_SMD_3.25X0.85MM_NO_SILK"))
    )
    (comp (ref "JP698")
      (value "M01PTH_SMD_3.25X0.85MM_NO_SILK")
      (footprint "eagle-import:1X01_SMD_3.25X0.85MM_NO_SILK")
      (libsource (lib "eagle-import") (part "M01PTH_SMD_3.25X0.85MM_NO_SILK"))
    )
    (comp (ref "JP699")
      (value "M01PTH_SMD_3.25X0.85MM_NO_SILK")
      (footprint "eagle-import:1X01_SMD_3.25X0.85MM_NO_SILK")
      (libsource (lib "eagle-import") (part "M01PTH_SMD_3.25X0.85MM_NO_SILK"))
    )
    (comp (ref "JP700")
      (value "M01PTH_SMD_3.25X0.85MM_NO_SILK")
      (footprint "eagle-import:1X01_SMD_3.25X0.85MM_NO_SILK")
      (libsource (lib "eagle-import") (part "M01PTH_SMD_3.25X0.85MM_NO_SILK"))
    )
    (comp (ref "JP701")
      (value "M01PTH_SMD_3.25X0.85MM_NO_SILK")
      (footprint "eagle-import:1X01_SMD_3.25X0.85MM_NO_SILK")
      (libsource (lib "eagle-import") (part "M01PTH_SMD_3.25X0.85MM_NO_SILK"))
    )
    (comp (ref "JP702")
      (value "M01PTH_SMD_3.25X0.85MM_NO_SILK")
      (footprint "eagle-import:1X01_SMD_3.25X0.85MM_NO_SILK")
      (libsource (lib "eagle-import") (part "M01PTH_SMD_3.25X0.85MM_NO_SILK"))
    )
    (comp (ref "JP703")
      (value "M01PTH_SMD_3.25X0.85MM_NO_SILK")
      (footprint "eagle-import:1X01_SMD_3.25X0.85MM_NO_SILK")
      (libsource (lib "eagle-import") (part "M01PTH_SMD_3.25X0.85MM_NO_SILK"))
    )
    (comp (ref "JP704")
      (value "M01PTH_SMD_3.25X0.85MM_NO_SILK")
      (footprint "eagle-import:1X01_SMD_3.25X0.85MM_NO_SILK")
      (libsource (lib "eagle-import") (part "M01PTH_SMD_3.25X0.85MM_NO_SILK"))
    )
    (comp (ref "JP705")
      (value "M01PTH_SMD_3.25X0.85MM_NO_SILK")
      (footprint "eagle-import:1X01_SMD_3.25X0.85MM_NO_SILK")
      (libsource (lib "eagle-import") (part "M01PTH_SMD_3.25X0.85MM_NO_SILK"))
    )
    (comp (ref "JP706")
      (value "M01PTH_SMD_3.25X0.85MM_NO_SILK")
      (footprint "eagle-import:1X01_SMD_3.25X0.85MM_NO_SILK")
      (libsource (lib "eagle-import") (part "M01PTH_SMD_3.25X0.85MM_NO_SILK"))
    )
    (comp (ref "JP707")
      (value "M01PTH_SMD_3.25X0.85MM_NO_SILK")
      (footprint "eagle-import:1X01_SMD_3.25X0.85MM_NO_SILK")
      (libsource (lib "eagle-import") (part "M01PTH_SMD_3.25X0.85MM_NO_SILK"))
    )
    (comp (ref "JP708")
      (value "M01PTH_SMD_3.25X0.85MM_NO_SILK")
      (footprint "eagle-import:1X01_SMD_3.25X0.85MM_NO_SILK")
      (libsource (lib "eagle-import") (part "M01PTH_SMD_3.25X0.85MM_NO_SILK"))
    )
    (comp (ref "JP709")
      (value "M01PTH_SMD_3.25X0.85MM_NO_SILK")
      (footprint "eagle-import:1X01_SMD_3.25X0.85MM_NO_SILK")
      (libsource (lib "eagle-import") (part "M01PTH_SMD_3.25X0.85MM_NO_SILK"))
    )
    (comp (ref "JP710")
      (value "M01PTH_SMD_3.25X0.85MM_NO_SILK")
      (footprint "eagle-import:1X01_SMD_3.25X0.85MM_NO_SILK")
      (libsource (lib "eagle-import") (part "M01PTH_SMD_3.25X0.85MM_NO_SILK"))
    )
    (comp (ref "JP711")
      (value "M01PTH_SMD_3.25X0.85MM_NO_SILK")
      (footprint "eagle-import:1X01_SMD_3.25X0.85MM_NO_SILK")
      (libsource (lib "eagle-import") (part "M01PTH_SMD_3.25X0.85MM_NO_SILK"))
    )
    (comp (ref "JP712")
      (value "M01PTH_SMD_3.25X0.85MM_NO_SILK")
      (footprint "eagle-import:1X01_SMD_3.25X0.85MM_NO_SILK")
      (libsource (lib "eagle-import") (part "M01PTH_SMD_3.25X0.85MM_NO_SILK"))
    )
    (comp (ref "JP713")
      (value "M01PTH_SMD_3.25X0.85MM_NO_SILK")
      (footprint "eagle-import:1X01_SMD_3.25X0.85MM_NO_SILK")
      (libsource (lib "eagle-import") (part "M01PTH_SMD_3.25X0.85MM_NO_SILK"))
    )
    (comp (ref "JP714")
      (value "M01PTH_SMD_3.25X0.85MM_NO_SILK")
      (footprint "eagle-import:1X01_SMD_3.25X0.85MM_NO_SILK")
      (libsource (lib "eagle-import") (part "M01PTH_SMD_3.25X0.85MM_NO_SILK"))
    )
    (comp (ref "JP715")
      (value "M01PTH_SMD_3.25X0.85MM_NO_SILK")
      (footprint "eagle-import:1X01_SMD_3.25X0.85MM_NO_SILK")
      (libsource (lib "eagle-import") (part "M01PTH_SMD_3.25X0.85MM_NO_SILK"))
    )
    (comp (ref "JP716")
      (value "M01PTH_SMD_3.25X0.85MM_NO_SILK")
      (footprint "eagle-import:1X01_SMD_3.25X0.85MM_NO_SILK")
      (libsource (lib "eagle-import") (part "M01PTH_SMD_3.25X0.85MM_NO_SILK"))
    )
    (comp (ref "JP717")
      (value "M01PTH_SMD_3.25X0.85MM_NO_SILK")
      (footprint "eagle-import:1X01_SMD_3.25X0.85MM_NO_SILK")
      (libsource (lib "eagle-import") (part "M01PTH_SMD_3.25X0.85MM_NO_SILK"))
    )
    (comp (ref "JP718")
      (value "M01PTH_SMD_3.25X0.85MM_NO_SILK")
      (footprint "eagle-import:1X01_SMD_3.25X0.85MM_NO_SILK")
      (libsource (lib "eagle-import") (part "M01PTH_SMD_3.25X0.85MM_NO_SILK"))
    )
    (comp (ref "JP719")
      (value "M01PTH_SMD_3.25X0.85MM_NO_SILK")
      (footprint "eagle-import:1X01_SMD_3.25X0.85MM_NO_SILK")
      (libsource (lib "eagle-import") (part "M01PTH_SMD_3.25X0.85MM_NO_SILK"))
    )
    (comp (ref "JP720")
      (value "M01PTH_SMD_3.25X0.85MM_NO_SILK")
      (footprint "eagle-import:1X01_SMD_3.25X0.85MM_NO_SILK")
      (libsource (lib "eagle-import") (part "M01PTH_SMD_3.25X0.85MM_NO_SILK"))
    )
    (comp (ref "JP721")
      (value "M01PTH_SMD_3.25X0.85MM_NO_SILK")
      (footprint "eagle-import:1X01_SMD_3.25X0.85MM_NO_SILK")
      (libsource (lib "eagle-import") (part "M01PTH_SMD_3.25X0.85MM_NO_SILK"))
    )
    (comp (ref "JP722")
      (value "M01PTH_SMD_3.25X0.85MM_NO_SILK")
      (footprint "eagle-import:1X01_SMD_3.25X0.85MM_NO_SILK")
      (libsource (lib "eagle-import") (part "M01PTH_SMD_3.25X0.85MM_NO_SILK"))
    )
    (comp (ref "JP723")
      (value "M01PTH_SMD_3.25X0.85MM_NO_SILK")
      (footprint "eagle-import:1X01_SMD_3.25X0.85MM_NO_SILK")
      (libsource (lib "eagle-import") (part "M01PTH_SMD_3.25X0.85MM_NO_SILK"))
    )
    (comp (ref "JP724")
      (value "M01PTH_SMD_3.25X0.85MM_NO_SILK")
      (footprint "eagle-import:1X01_SMD_3.25X0.85MM_NO_SILK")
      (libsource (lib "eagle-import") (part "M01PTH_SMD_3.25X0.85MM_NO_SILK"))
    )
    (comp (ref "JP725")
      (value "M01PTH_SMD_3.25X0.85MM_NO_SILK")
      (footprint "eagle-import:1X01_SMD_3.25X0.85MM_NO_SILK")
      (libsource (lib "eagle-import") (part "M01PTH_SMD_3.25X0.85MM_NO_SILK"))
    )
    (comp (ref "JP726")
      (value "M01PTH_SMD_3.25X0.85MM_NO_SILK")
      (footprint "eagle-import:1X01_SMD_3.25X0.85MM_NO_SILK")
      (libsource (lib "eagle-import") (part "M01PTH_SMD_3.25X0.85MM_NO_SILK"))
    )
    (comp (ref "JP727")
      (value "M01PTH_SMD_3.25X0.85MM_NO_SILK")
      (footprint "eagle-import:1X01_SMD_3.25X0.85MM_NO_SILK")
      (libsource (lib "eagle-import") (part "M01PTH_SMD_3.25X0.85MM_NO_SILK"))
    )
    (comp (ref "JP728")
      (value "M01PTH_SMD_3.25X0.85MM_NO_SILK")
      (footprint "eagle-import:1X01_SMD_3.25X0.85MM_NO_SILK")
      (libsource (lib "eagle-import") (part "M01PTH_SMD_3.25X0.85MM_NO_SILK"))
    )
    (comp (ref "JP729")
      (value "M01PTH_SMD_3.25X0.85MM_NO_SILK")
      (footprint "eagle-import:1X01_SMD_3.25X0.85MM_NO_SILK")
      (libsource (lib "eagle-import") (part "M01PTH_SMD_3.25X0.85MM_NO_SILK"))
    )
    (comp (ref "JP730")
      (value "M01PTH_SMD_3.25X0.85MM_NO_SILK")
      (footprint "eagle-import:1X01_SMD_3.25X0.85MM_NO_SILK")
      (libsource (lib "eagle-import") (part "M01PTH_SMD_3.25X0.85MM_NO_SILK"))
    )
    (comp (ref "JP731")
      (value "M01PTH_SMD_3.25X0.85MM_NO_SILK")
      (footprint "eagle-import:1X01_SMD_3.25X0.85MM_NO_SILK")
      (libsource (lib "eagle-import") (part "M01PTH_SMD_3.25X0.85MM_NO_SILK"))
    )
    (comp (ref "JP732")
      (value "M01PTH_SMD_3.25X0.85MM_NO_SILK")
      (footprint "eagle-import:1X01_SMD_3.25X0.85MM_NO_SILK")
      (libsource (lib "eagle-import") (part "M01PTH_SMD_3.25X0.85MM_NO_SILK"))
    )
    (comp (ref "JP733")
      (value "M01PTH_SMD_3.25X0.85MM_NO_SILK")
      (footprint "eagle-import:1X01_SMD_3.25X0.85MM_NO_SILK")
      (libsource (lib "eagle-import") (part "M01PTH_SMD_3.25X0.85MM_NO_SILK"))
    )
    (comp (ref "JP734")
      (value "M01PTH_SMD_3.25X0.85MM_NO_SILK")
      (footprint "eagle-import:1X01_SMD_3.25X0.85MM_NO_SILK")
      (libsource (lib "eagle-import") (part "M01PTH_SMD_3.25X0.85MM_NO_SILK"))
    )
    (comp (ref "JP735")
      (value "M01PTH_SMD_3.25X0.85MM_NO_SILK")
      (footprint "eagle-import:1X01_SMD_3.25X0.85MM_NO_SILK")
      (libsource (lib "eagle-import") (part "M01PTH_SMD_3.25X0.85MM_NO_SILK"))
    )
    (comp (ref "JP736")
      (value "M01PTH_SMD_3.25X0.85MM_NO_SILK")
      (footprint "eagle-import:1X01_SMD_3.25X0.85MM_NO_SILK")
      (libsource (lib "eagle-import") (part "M01PTH_SMD_3.25X0.85MM_NO_SILK"))
    )
    (comp (ref "JP737")
      (value "M01PTH_SMD_3.25X0.85MM_NO_SILK")
      (footprint "eagle-import:1X01_SMD_3.25X0.85MM_NO_SILK")
      (libsource (lib "eagle-import") (part "M01PTH_SMD_3.25X0.85MM_NO_SILK"))
    )
    (comp (ref "JP738")
      (value "M01PTH_SMD_3.25X0.85MM_NO_SILK")
      (footprint "eagle-import:1X01_SMD_3.25X0.85MM_NO_SILK")
      (libsource (lib "eagle-import") (part "M01PTH_SMD_3.25X0.85MM_NO_SILK"))
    )
    (comp (ref "JP739")
      (value "M01PTH_SMD_3.25X0.85MM_NO_SILK")
      (footprint "eagle-import:1X01_SMD_3.25X0.85MM_NO_SILK")
      (libsource (lib "eagle-import") (part "M01PTH_SMD_3.25X0.85MM_NO_SILK"))
    )
    (comp (ref "JP740")
      (value "M01PTH_SMD_3.25X0.85MM_NO_SILK")
      (footprint "eagle-import:1X01_SMD_3.25X0.85MM_NO_SILK")
      (libsource (lib "eagle-import") (part "M01PTH_SMD_3.25X0.85MM_NO_SILK"))
    )
    (comp (ref "JP741")
      (value "M01PTH_SMD_3.25X0.85MM_NO_SILK")
      (footprint "eagle-import:1X01_SMD_3.25X0.85MM_NO_SILK")
      (libsource (lib "eagle-import") (part "M01PTH_SMD_3.25X0.85MM_NO_SILK"))
    )
    (comp (ref "JP742")
      (value "M01PTH_SMD_3.25X0.85MM_NO_SILK")
      (footprint "eagle-import:1X01_SMD_3.25X0.85MM_NO_SILK")
      (libsource (lib "eagle-import") (part "M01PTH_SMD_3.25X0.85MM_NO_SILK"))
    )
    (comp (ref "JP743")
      (value "M01PTH_SMD_3.25X0.85MM_NO_SILK")
      (footprint "eagle-import:1X01_SMD_3.25X0.85MM_NO_SILK")
      (libsource (lib "eagle-import") (part "M01PTH_SMD_3.25X0.85MM_NO_SILK"))
    )
    (comp (ref "JP744")
      (value "M01PTH_SMD_3.25X0.85MM_NO_SILK")
      (footprint "eagle-import:1X01_SMD_3.25X0.85MM_NO_SILK")
      (libsource (lib "eagle-import") (part "M01PTH_SMD_3.25X0.85MM_NO_SILK"))
    )
    (comp (ref "JP745")
      (value "M01PTH_SMD_3.25X0.85MM_NO_SILK")
      (footprint "eagle-import:1X01_SMD_3.25X0.85MM_NO_SILK")
      (libsource (lib "eagle-import") (part "M01PTH_SMD_3.25X0.85MM_NO_SILK"))
    )
    (comp (ref "JP746")
      (value "M01PTH_SMD_3.25X0.85MM_NO_SILK")
      (footprint "eagle-import:1X01_SMD_3.25X0.85MM_NO_SILK")
      (libsource (lib "eagle-import") (part "M01PTH_SMD_3.25X0.85MM_NO_SILK"))
    )
    (comp (ref "JP747")
      (value "M01PTH_SMD_3.25X0.85MM_NO_SILK")
      (footprint "eagle-import:1X01_SMD_3.25X0.85MM_NO_SILK")
      (libsource (lib "eagle-import") (part "M01PTH_SMD_3.25X0.85MM_NO_SILK"))
    )
    (comp (ref "JP748")
      (value "M01PTH_SMD_3.25X0.85MM_NO_SILK")
      (footprint "eagle-import:1X01_SMD_3.25X0.85MM_NO_SILK")
      (libsource (lib "eagle-import") (part "M01PTH_SMD_3.25X0.85MM_NO_SILK"))
    )
    (comp (ref "JP749")
      (value "M01PTH_SMD_3.25X0.85MM_NO_SILK")
      (footprint "eagle-import:1X01_SMD_3.25X0.85MM_NO_SILK")
      (libsource (lib "eagle-import") (part "M01PTH_SMD_3.25X0.85MM_NO_SILK"))
    )
    (comp (ref "JP750")
      (value "M01PTH_SMD_3.25X0.85MM_NO_SILK")
      (footprint "eagle-import:1X01_SMD_3.25X0.85MM_NO_SILK")
      (libsource (lib "eagle-import") (part "M01PTH_SMD_3.25X0.85MM_NO_SILK"))
    )
    (comp (ref "JP751")
      (value "M01PTH_SMD_3.25X0.85MM_NO_SILK")
      (footprint "eagle-import:1X01_SMD_3.25X0.85MM_NO_SILK")
      (libsource (lib "eagle-import") (part "M01PTH_SMD_3.25X0.85MM_NO_SILK"))
    )
    (comp (ref "JP752")
      (value "M01PTH_SMD_3.25X0.85MM_NO_SILK")
      (footprint "eagle-import:1X01_SMD_3.25X0.85MM_NO_SILK")
      (libsource (lib "eagle-import") (part "M01PTH_SMD_3.25X0.85MM_NO_SILK"))
    )
    (comp (ref "JP753")
      (value "M01PTH_SMD_3.25X0.85MM_NO_SILK")
      (footprint "eagle-import:1X01_SMD_3.25X0.85MM_NO_SILK")
      (libsource (lib "eagle-import") (part "M01PTH_SMD_3.25X0.85MM_NO_SILK"))
    )
    (comp (ref "JP754")
      (value "M01PTH_SMD_3.25X0.85MM_NO_SILK")
      (footprint "eagle-import:1X01_SMD_3.25X0.85MM_NO_SILK")
      (libsource (lib "eagle-import") (part "M01PTH_SMD_3.25X0.85MM_NO_SILK"))
    )
    (comp (ref "JP755")
      (value "M01PTH_SMD_3.25X0.85MM_NO_SILK")
      (footprint "eagle-import:1X01_SMD_3.25X0.85MM_NO_SILK")
      (libsource (lib "eagle-import") (part "M01PTH_SMD_3.25X0.85MM_NO_SILK"))
    )
    (comp (ref "JP756")
      (value "M01PTH_SMD_3.25X0.85MM_NO_SILK")
      (footprint "eagle-import:1X01_SMD_3.25X0.85MM_NO_SILK")
      (libsource (lib "eagle-import") (part "M01PTH_SMD_3.25X0.85MM_NO_SILK"))
    )
    (comp (ref "JP757")
      (value "M01PTH_SMD_3.25X0.85MM_NO_SILK")
      (footprint "eagle-import:1X01_SMD_3.25X0.85MM_NO_SILK")
      (libsource (lib "eagle-import") (part "M01PTH_SMD_3.25X0.85MM_NO_SILK"))
    )
    (comp (ref "JP758")
      (value "M01PTH_SMD_3.25X0.85MM_NO_SILK")
      (footprint "eagle-import:1X01_SMD_3.25X0.85MM_NO_SILK")
      (libsource (lib "eagle-import") (part "M01PTH_SMD_3.25X0.85MM_NO_SILK"))
    )
    (comp (ref "JP759")
      (value "M01PTH_SMD_3.25X0.85MM_NO_SILK")
      (footprint "eagle-import:1X01_SMD_3.25X0.85MM_NO_SILK")
      (libsource (lib "eagle-import") (part "M01PTH_SMD_3.25X0.85MM_NO_SILK"))
    )
    (comp (ref "JP760")
      (value "M01PTH_SMD_3.25X0.85MM_NO_SILK")
      (footprint "eagle-import:1X01_SMD_3.25X0.85MM_NO_SILK")
      (libsource (lib "eagle-import") (part "M01PTH_SMD_3.25X0.85MM_NO_SILK"))
    )
    (comp (ref "JP761")
      (value "M01PTH_SMD_3.25X0.85MM_NO_SILK")
      (footprint "eagle-import:1X01_SMD_3.25X0.85MM_NO_SILK")
      (libsource (lib "eagle-import") (part "M01PTH_SMD_3.25X0.85MM_NO_SILK"))
    )
    (comp (ref "JP762")
      (value "M01PTH_SMD_3.25X0.85MM_NO_SILK")
      (footprint "eagle-import:1X01_SMD_3.25X0.85MM_NO_SILK")
      (libsource (lib "eagle-import") (part "M01PTH_SMD_3.25X0.85MM_NO_SILK"))
    )
    (comp (ref "JP763")
      (value "M01PTH_SMD_3.25X0.85MM_NO_SILK")
      (footprint "eagle-import:1X01_SMD_3.25X0.85MM_NO_SILK")
      (libsource (lib "eagle-import") (part "M01PTH_SMD_3.25X0.85MM_NO_SILK"))
    )
    (comp (ref "JP764")
      (value "M01PTH_SMD_3.25X0.85MM_NO_SILK")
      (footprint "eagle-import:1X01_SMD_3.25X0.85MM_NO_SILK")
      (libsource (lib "eagle-import") (part "M01PTH_SMD_3.25X0.85MM_NO_SILK"))
    )
    (comp (ref "JP765")
      (value "M01PTH_SMD_3.25X0.85MM_NO_SILK")
      (footprint "eagle-import:1X01_SMD_3.25X0.85MM_NO_SILK")
      (libsource (lib "eagle-import") (part "M01PTH_SMD_3.25X0.85MM_NO_SILK"))
    )
    (comp (ref "JP766")
      (value "M01PTH_SMD_3.25X0.85MM_NO_SILK")
      (footprint "eagle-import:1X01_SMD_3.25X0.85MM_NO_SILK")
      (libsource (lib "eagle-import") (part "M01PTH_SMD_3.25X0.85MM_NO_SILK"))
    )
    (comp (ref "JP767")
      (value "M01PTH_SMD_3.25X0.85MM_NO_SILK")
      (footprint "eagle-import:1X01_SMD_3.25X0.85MM_NO_SILK")
      (libsource (lib "eagle-import") (part "M01PTH_SMD_3.25X0.85MM_NO_SILK"))
    )
    (comp (ref "JP768")
      (value "M01PTH_SMD_3.25X0.85MM_NO_SILK")
      (footprint "eagle-import:1X01_SMD_3.25X0.85MM_NO_SILK")
      (libsource (lib "eagle-import") (part "M01PTH_SMD_3.25X0.85MM_NO_SILK"))
    )
    (comp (ref "JP769")
      (value "M01PTH_SMD_3.25X0.85MM_NO_SILK")
      (footprint "eagle-import:1X01_SMD_3.25X0.85MM_NO_SILK")
      (libsource (lib "eagle-import") (part "M01PTH_SMD_3.25X0.85MM_NO_SILK"))
    )
    (comp (ref "JP770")
      (value "M01PTH_SMD_3.25X0.85MM_NO_SILK")
      (footprint "eagle-import:1X01_SMD_3.25X0.85MM_NO_SILK")
      (libsource (lib "eagle-import") (part "M01PTH_SMD_3.25X0.85MM_NO_SILK"))
    )
    (comp (ref "JP771")
      (value "M01PTH_SMD_3.25X0.85MM_NO_SILK")
      (footprint "eagle-import:1X01_SMD_3.25X0.85MM_NO_SILK")
      (libsource (lib "eagle-import") (part "M01PTH_SMD_3.25X0.85MM_NO_SILK"))
    )
    (comp (ref "JP772")
      (value "M01PTH_SMD_3.25X0.85MM_NO_SILK")
      (footprint "eagle-import:1X01_SMD_3.25X0.85MM_NO_SILK")
      (libsource (lib "eagle-import") (part "M01PTH_SMD_3.25X0.85MM_NO_SILK"))
    )
    (comp (ref "JP773")
      (value "M01PTH_SMD_3.25X0.85MM_NO_SILK")
      (footprint "eagle-import:1X01_SMD_3.25X0.85MM_NO_SILK")
      (libsource (lib "eagle-import") (part "M01PTH_SMD_3.25X0.85MM_NO_SILK"))
    )
    (comp (ref "JP774")
      (value "M01PTH_SMD_3.25X0.85MM_NO_SILK")
      (footprint "eagle-import:1X01_SMD_3.25X0.85MM_NO_SILK")
      (libsource (lib "eagle-import") (part "M01PTH_SMD_3.25X0.85MM_NO_SILK"))
    )
    (comp (ref "JP775")
      (value "M01PTH_SMD_3.25X0.85MM_NO_SILK")
      (footprint "eagle-import:1X01_SMD_3.25X0.85MM_NO_SILK")
      (libsource (lib "eagle-import") (part "M01PTH_SMD_3.25X0.85MM_NO_SILK"))
    )
    (comp (ref "JP776")
      (value "M01PTH_SMD_3.25X0.85MM_NO_SILK")
      (footprint "eagle-import:1X01_SMD_3.25X0.85MM_NO_SILK")
      (libsource (lib "eagle-import") (part "M01PTH_SMD_3.25X0.85MM_NO_SILK"))
    )
    (comp (ref "JP777")
      (value "M01PTH_SMD_3.25X0.85MM_NO_SILK")
      (footprint "eagle-import:1X01_SMD_3.25X0.85MM_NO_SILK")
      (libsource (lib "eagle-import") (part "M01PTH_SMD_3.25X0.85MM_NO_SILK"))
    )
    (comp (ref "JP778")
      (value "M01PTH_SMD_3.25X0.85MM_NO_SILK")
      (footprint "eagle-import:1X01_SMD_3.25X0.85MM_NO_SILK")
      (libsource (lib "eagle-import") (part "M01PTH_SMD_3.25X0.85MM_NO_SILK"))
    )
    (comp (ref "JP779")
      (value "M01PTH_SMD_3.25X0.85MM_NO_SILK")
      (footprint "eagle-import:1X01_SMD_3.25X0.85MM_NO_SILK")
      (libsource (lib "eagle-import") (part "M01PTH_SMD_3.25X0.85MM_NO_SILK"))
    )
    (comp (ref "JP780")
      (value "M01PTH_SMD_3.25X0.85MM_NO_SILK")
      (footprint "eagle-import:1X01_SMD_3.25X0.85MM_NO_SILK")
      (libsource (lib "eagle-import") (part "M01PTH_SMD_3.25X0.85MM_NO_SILK"))
    )
    (comp (ref "JP781")
      (value "M01PTH_SMD_3.25X0.85MM_NO_SILK")
      (footprint "eagle-import:1X01_SMD_3.25X0.85MM_NO_SILK")
      (libsource (lib "eagle-import") (part "M01PTH_SMD_3.25X0.85MM_NO_SILK"))
    )
    (comp (ref "JP782")
      (value "M01PTH_SMD_3.25X0.85MM_NO_SILK")
      (footprint "eagle-import:1X01_SMD_3.25X0.85MM_NO_SILK")
      (libsource (lib "eagle-import") (part "M01PTH_SMD_3.25X0.85MM_NO_SILK"))
    )
    (comp (ref "JP783")
      (value "M01PTH_SMD_3.25X0.85MM_NO_SILK")
      (footprint "eagle-import:1X01_SMD_3.25X0.85MM_NO_SILK")
      (libsource (lib "eagle-import") (part "M01PTH_SMD_3.25X0.85MM_NO_SILK"))
    )
    (comp (ref "JP784")
      (value "M01PTH_SMD_3.25X0.85MM_NO_SILK")
      (footprint "eagle-import:1X01_SMD_3.25X0.85MM_NO_SILK")
      (libsource (lib "eagle-import") (part "M01PTH_SMD_3.25X0.85MM_NO_SILK"))
    )
    (comp (ref "JP785")
      (value "M01PTH_SMD_3.25X0.85MM_NO_SILK")
      (footprint "eagle-import:1X01_SMD_3.25X0.85MM_NO_SILK")
      (libsource (lib "eagle-import") (part "M01PTH_SMD_3.25X0.85MM_NO_SILK"))
    )
    (comp (ref "JP786")
      (value "M01PTH_SMD_3.25X0.85MM_NO_SILK")
      (footprint "eagle-import:1X01_SMD_3.25X0.85MM_NO_SILK")
      (libsource (lib "eagle-import") (part "M01PTH_SMD_3.25X0.85MM_NO_SILK"))
    )
    (comp (ref "JP787")
      (value "M01PTH_SMD_3.25X0.85MM_NO_SILK")
      (footprint "eagle-import:1X01_SMD_3.25X0.85MM_NO_SILK")
      (libsource (lib "eagle-import") (part "M01PTH_SMD_3.25X0.85MM_NO_SILK"))
    )
    (comp (ref "JP788")
      (value "M01PTH_SMD_3.25X0.85MM_NO_SILK")
      (footprint "eagle-import:1X01_SMD_3.25X0.85MM_NO_SILK")
      (libsource (lib "eagle-import") (part "M01PTH_SMD_3.25X0.85MM_NO_SILK"))
    )
    (comp (ref "JP789")
      (value "M01PTH_SMD_3.25X0.85MM_NO_SILK")
      (footprint "eagle-import:1X01_SMD_3.25X0.85MM_NO_SILK")
      (libsource (lib "eagle-import") (part "M01PTH_SMD_3.25X0.85MM_NO_SILK"))
    )
    (comp (ref "JP790")
      (value "M01PTH_SMD_3.25X0.85MM_NO_SILK")
      (footprint "eagle-import:1X01_SMD_3.25X0.85MM_NO_SILK")
      (libsource (lib "eagle-import") (part "M01PTH_SMD_3.25X0.85MM_NO_SILK"))
    )
    (comp (ref "JP791")
      (value "M01PTH_SMD_3.25X0.85MM_NO_SILK")
      (footprint "eagle-import:1X01_SMD_3.25X0.85MM_NO_SILK")
      (libsource (lib "eagle-import") (part "M01PTH_SMD_3.25X0.85MM_NO_SILK"))
    )
    (comp (ref "JP792")
      (value "M01PTH_SMD_3.25X0.85MM_NO_SILK")
      (footprint "eagle-import:1X01_SMD_3.25X0.85MM_NO_SILK")
      (libsource (lib "eagle-import") (part "M01PTH_SMD_3.25X0.85MM_NO_SILK"))
    )
    (comp (ref "JP793")
      (value "M01PTH_SMD_3.25X0.85MM_NO_SILK")
      (footprint "eagle-import:1X01_SMD_3.25X0.85MM_NO_SILK")
      (libsource (lib "eagle-import") (part "M01PTH_SMD_3.25X0.85MM_NO_SILK"))
    )
    (comp (ref "JP794")
      (value "M01PTH_SMD_3.25X0.85MM_NO_SILK")
      (footprint "eagle-import:1X01_SMD_3.25X0.85MM_NO_SILK")
      (libsource (lib "eagle-import") (part "M01PTH_SMD_3.25X0.85MM_NO_SILK"))
    )
    (comp (ref "JP795")
      (value "M01PTH_SMD_3.25X0.85MM_NO_SILK")
      (footprint "eagle-import:1X01_SMD_3.25X0.85MM_NO_SILK")
      (libsource (lib "eagle-import") (part "M01PTH_SMD_3.25X0.85MM_NO_SILK"))
    )
    (comp (ref "JP796")
      (value "M01PTH_SMD_3.25X0.85MM_NO_SILK")
      (footprint "eagle-import:1X01_SMD_3.25X0.85MM_NO_SILK")
      (libsource (lib "eagle-import") (part "M01PTH_SMD_3.25X0.85MM_NO_SILK"))
    )
    (comp (ref "JP797")
      (value "M01PTH_SMD_3.25X0.85MM_NO_SILK")
      (footprint "eagle-import:1X01_SMD_3.25X0.85MM_NO_SILK")
      (libsource (lib "eagle-import") (part "M01PTH_SMD_3.25X0.85MM_NO_SILK"))
    )
    (comp (ref "JP798")
      (value "M01PTH_SMD_3.25X0.85MM_NO_SILK")
      (footprint "eagle-import:1X01_SMD_3.25X0.85MM_NO_SILK")
      (libsource (lib "eagle-import") (part "M01PTH_SMD_3.25X0.85MM_NO_SILK"))
    )
    (comp (ref "JP799")
      (value "M01PTH_SMD_3.25X0.85MM_NO_SILK")
      (footprint "eagle-import:1X01_SMD_3.25X0.85MM_NO_SILK")
      (libsource (lib "eagle-import") (part "M01PTH_SMD_3.25X0.85MM_NO_SILK"))
    )
    (comp (ref "JP800")
      (value "M01PTH_SMD_3.25X0.85MM_NO_SILK")
      (footprint "eagle-import:1X01_SMD_3.25X0.85MM_NO_SILK")
      (libsource (lib "eagle-import") (part "M01PTH_SMD_3.25X0.85MM_NO_SILK"))
    )
    (comp (ref "JP801")
      (value "M01PTH_SMD_3.25X0.85MM_NO_SILK")
      (footprint "eagle-import:1X01_SMD_3.25X0.85MM_NO_SILK")
      (libsource (lib "eagle-import") (part "M01PTH_SMD_3.25X0.85MM_NO_SILK"))
    )
    (comp (ref "JP802")
      (value "M01PTH_SMD_3.25X0.85MM_NO_SILK")
      (footprint "eagle-import:1X01_SMD_3.25X0.85MM_NO_SILK")
      (libsource (lib "eagle-import") (part "M01PTH_SMD_3.25X0.85MM_NO_SILK"))
    )
    (comp (ref "JP803")
      (value "M01PTH_SMD_3.25X0.85MM_NO_SILK")
      (footprint "eagle-import:1X01_SMD_3.25X0.85MM_NO_SILK")
      (libsource (lib "eagle-import") (part "M01PTH_SMD_3.25X0.85MM_NO_SILK"))
    )
    (comp (ref "JP804")
      (value "M01PTH_SMD_3.25X0.85MM_NO_SILK")
      (footprint "eagle-import:1X01_SMD_3.25X0.85MM_NO_SILK")
      (libsource (lib "eagle-import") (part "M01PTH_SMD_3.25X0.85MM_NO_SILK"))
    )
    (comp (ref "JP805")
      (value "M01PTH_SMD_3.25X0.85MM_NO_SILK")
      (footprint "eagle-import:1X01_SMD_3.25X0.85MM_NO_SILK")
      (libsource (lib "eagle-import") (part "M01PTH_SMD_3.25X0.85MM_NO_SILK"))
    )
    (comp (ref "JP806")
      (value "M01PTH_SMD_3.25X0.85MM_NO_SILK")
      (footprint "eagle-import:1X01_SMD_3.25X0.85MM_NO_SILK")
      (libsource (lib "eagle-import") (part "M01PTH_SMD_3.25X0.85MM_NO_SILK"))
    )
    (comp (ref "JP807")
      (value "M01PTH_SMD_3.25X0.85MM_NO_SILK")
      (footprint "eagle-import:1X01_SMD_3.25X0.85MM_NO_SILK")
      (libsource (lib "eagle-import") (part "M01PTH_SMD_3.25X0.85MM_NO_SILK"))
    )
    (comp (ref "JP808")
      (value "M01PTH_SMD_3.25X0.85MM_NO_SILK")
      (footprint "eagle-import:1X01_SMD_3.25X0.85MM_NO_SILK")
      (libsource (lib "eagle-import") (part "M01PTH_SMD_3.25X0.85MM_NO_SILK"))
    )
    (comp (ref "JP809")
      (value "M01PTH_SMD_3.25X0.85MM_NO_SILK")
      (footprint "eagle-import:1X01_SMD_3.25X0.85MM_NO_SILK")
      (libsource (lib "eagle-import") (part "M01PTH_SMD_3.25X0.85MM_NO_SILK"))
    )
    (comp (ref "JP810")
      (value "M01PTH_SMD_3.25X0.85MM_NO_SILK")
      (footprint "eagle-import:1X01_SMD_3.25X0.85MM_NO_SILK")
      (libsource (lib "eagle-import") (part "M01PTH_SMD_3.25X0.85MM_NO_SILK"))
    )
    (comp (ref "JP811")
      (value "M01PTH_SMD_3.25X0.85MM_NO_SILK")
      (footprint "eagle-import:1X01_SMD_3.25X0.85MM_NO_SILK")
      (libsource (lib "eagle-import") (part "M01PTH_SMD_3.25X0.85MM_NO_SILK"))
    )
    (comp (ref "JP812")
      (value "M01PTH_SMD_3.25X0.85MM_NO_SILK")
      (footprint "eagle-import:1X01_SMD_3.25X0.85MM_NO_SILK")
      (libsource (lib "eagle-import") (part "M01PTH_SMD_3.25X0.85MM_NO_SILK"))
    )
    (comp (ref "JP813")
      (value "M01PTH_SMD_3.25X0.85MM_NO_SILK")
      (footprint "eagle-import:1X01_SMD_3.25X0.85MM_NO_SILK")
      (libsource (lib "eagle-import") (part "M01PTH_SMD_3.25X0.85MM_NO_SILK"))
    )
    (comp (ref "JP814")
      (value "M01PTH_SMD_3.25X0.85MM_NO_SILK")
      (footprint "eagle-import:1X01_SMD_3.25X0.85MM_NO_SILK")
      (libsource (lib "eagle-import") (part "M01PTH_SMD_3.25X0.85MM_NO_SILK"))
    )
    (comp (ref "JP815")
      (value "M01PTH_SMD_3.25X0.85MM_NO_SILK")
      (footprint "eagle-import:1X01_SMD_3.25X0.85MM_NO_SILK")
      (libsource (lib "eagle-import") (part "M01PTH_SMD_3.25X0.85MM_NO_SILK"))
    )
    (comp (ref "JP816")
      (value "M01PTH_SMD_3.25X0.85MM_NO_SILK")
      (footprint "eagle-import:1X01_SMD_3.25X0.85MM_NO_SILK")
      (libsource (lib "eagle-import") (part "M01PTH_SMD_3.25X0.85MM_NO_SILK"))
    )
    (comp (ref "JP817")
      (value "M01PTH_SMD_3.25X0.85MM_NO_SILK")
      (footprint "eagle-import:1X01_SMD_3.25X0.85MM_NO_SILK")
      (libsource (lib "eagle-import") (part "M01PTH_SMD_3.25X0.85MM_NO_SILK"))
    )
    (comp (ref "JP818")
      (value "M01PTH_SMD_3.25X0.85MM_NO_SILK")
      (footprint "eagle-import:1X01_SMD_3.25X0.85MM_NO_SILK")
      (libsource (lib "eagle-import") (part "M01PTH_SMD_3.25X0.85MM_NO_SILK"))
    )
    (comp (ref "JP819")
      (value "M01PTH_SMD_3.25X0.85MM_NO_SILK")
      (footprint "eagle-import:1X01_SMD_3.25X0.85MM_NO_SILK")
      (libsource (lib "eagle-import") (part "M01PTH_SMD_3.25X0.85MM_NO_SILK"))
    )
    (comp (ref "JP820")
      (value "M01PTH_SMD_3.25X0.85MM_NO_SILK")
      (footprint "eagle-import:1X01_SMD_3.25X0.85MM_NO_SILK")
      (libsource (lib "eagle-import") (part "M01PTH_SMD_3.25X0.85MM_NO_SILK"))
    )
    (comp (ref "JP821")
      (value "M01PTH_SMD_3.25X0.85MM_NO_SILK")
      (footprint "eagle-import:1X01_SMD_3.25X0.85MM_NO_SILK")
      (libsource (lib "eagle-import") (part "M01PTH_SMD_3.25X0.85MM_NO_SILK"))
    )
    (comp (ref "JP822")
      (value "M01PTH_SMD_3.25X0.85MM_NO_SILK")
      (footprint "eagle-import:1X01_SMD_3.25X0.85MM_NO_SILK")
      (libsource (lib "eagle-import") (part "M01PTH_SMD_3.25X0.85MM_NO_SILK"))
    )
    (comp (ref "JP823")
      (value "M01PTH_SMD_3.25X0.85MM_NO_SILK")
      (footprint "eagle-import:1X01_SMD_3.25X0.85MM_NO_SILK")
      (libsource (lib "eagle-import") (part "M01PTH_SMD_3.25X0.85MM_NO_SILK"))
    )
    (comp (ref "JP824")
      (value "M01PTH_SMD_3.25X0.85MM_NO_SILK")
      (footprint "eagle-import:1X01_SMD_3.25X0.85MM_NO_SILK")
      (libsource (lib "eagle-import") (part "M01PTH_SMD_3.25X0.85MM_NO_SILK"))
    )
    (comp (ref "JP825")
      (value "M01PTH_SMD_3.25X0.85MM_NO_SILK")
      (footprint "eagle-import:1X01_SMD_3.25X0.85MM_NO_SILK")
      (libsource (lib "eagle-import") (part "M01PTH_SMD_3.25X0.85MM_NO_SILK"))
    )
    (comp (ref "JP826")
      (value "M01PTH_SMD_3.25X0.85MM_NO_SILK")
      (footprint "eagle-import:1X01_SMD_3.25X0.85MM_NO_SILK")
      (libsource (lib "eagle-import") (part "M01PTH_SMD_3.25X0.85MM_NO_SILK"))
    )
    (comp (ref "JP827")
      (value "M01PTH_SMD_3.25X0.85MM_NO_SILK")
      (footprint "eagle-import:1X01_SMD_3.25X0.85MM_NO_SILK")
      (libsource (lib "eagle-import") (part "M01PTH_SMD_3.25X0.85MM_NO_SILK"))
    )
    (comp (ref "JP828")
      (value "M01PTH_SMD_3.25X0.85MM_NO_SILK")
      (footprint "eagle-import:1X01_SMD_3.25X0.85MM_NO_SILK")
      (libsource (lib "eagle-import") (part "M01PTH_SMD_3.25X0.85MM_NO_SILK"))
    )
    (comp (ref "JP829")
      (value "M01PTH_SMD_3.25X0.85MM_NO_SILK")
      (footprint "eagle-import:1X01_SMD_3.25X0.85MM_NO_SILK")
      (libsource (lib "eagle-import") (part "M01PTH_SMD_3.25X0.85MM_NO_SILK"))
    )
    (comp (ref "JP830")
      (value "M01PTH_SMD_3.25X0.85MM_NO_SILK")
      (footprint "eagle-import:1X01_SMD_3.25X0.85MM_NO_SILK")
      (libsource (lib "eagle-import") (part "M01PTH_SMD_3.25X0.85MM_NO_SILK"))
    )
    (comp (ref "JP831")
      (value "M01PTH_SMD_3.25X0.85MM_NO_SILK")
      (footprint "eagle-import:1X01_SMD_3.25X0.85MM_NO_SILK")
      (libsource (lib "eagle-import") (part "M01PTH_SMD_3.25X0.85MM_NO_SILK"))
    )
    (comp (ref "JP832")
      (value "M01PTH_SMD_3.25X0.85MM_NO_SILK")
      (footprint "eagle-import:1X01_SMD_3.25X0.85MM_NO_SILK")
      (libsource (lib "eagle-import") (part "M01PTH_SMD_3.25X0.85MM_NO_SILK"))
    )
    (comp (ref "JP833")
      (value "M01PTH_SMD_3.25X0.85MM_NO_SILK")
      (footprint "eagle-import:1X01_SMD_3.25X0.85MM_NO_SILK")
      (libsource (lib "eagle-import") (part "M01PTH_SMD_3.25X0.85MM_NO_SILK"))
    )
    (comp (ref "JP834")
      (value "M01PTH_SMD_3.25X0.85MM_NO_SILK")
      (footprint "eagle-import:1X01_SMD_3.25X0.85MM_NO_SILK")
      (libsource (lib "eagle-import") (part "M01PTH_SMD_3.25X0.85MM_NO_SILK"))
    )
    (comp (ref "JP835")
      (value "M01PTH_SMD_3.25X0.85MM_NO_SILK")
      (footprint "eagle-import:1X01_SMD_3.25X0.85MM_NO_SILK")
      (libsource (lib "eagle-import") (part "M01PTH_SMD_3.25X0.85MM_NO_SILK"))
    )
    (comp (ref "JP836")
      (value "M01PTH_SMD_3.25X0.85MM_NO_SILK")
      (footprint "eagle-import:1X01_SMD_3.25X0.85MM_NO_SILK")
      (libsource (lib "eagle-import") (part "M01PTH_SMD_3.25X0.85MM_NO_SILK"))
    )
    (comp (ref "JP837")
      (value "M01PTH_SMD_3.25X0.85MM_NO_SILK")
      (footprint "eagle-import:1X01_SMD_3.25X0.85MM_NO_SILK")
      (libsource (lib "eagle-import") (part "M01PTH_SMD_3.25X0.85MM_NO_SILK"))
    )
    (comp (ref "JP838")
      (value "M01PTH_SMD_3.25X0.85MM_NO_SILK")
      (footprint "eagle-import:1X01_SMD_3.25X0.85MM_NO_SILK")
      (libsource (lib "eagle-import") (part "M01PTH_SMD_3.25X0.85MM_NO_SILK"))
    )
    (comp (ref "JP839")
      (value "M01PTH_SMD_3.25X0.85MM_NO_SILK")
      (footprint "eagle-import:1X01_SMD_3.25X0.85MM_NO_SILK")
      (libsource (lib "eagle-import") (part "M01PTH_SMD_3.25X0.85MM_NO_SILK"))
    )
    (comp (ref "JP840")
      (value "M01PTH_SMD_3.25X0.85MM_NO_SILK")
      (footprint "eagle-import:1X01_SMD_3.25X0.85MM_NO_SILK")
      (libsource (lib "eagle-import") (part "M01PTH_SMD_3.25X0.85MM_NO_SILK"))
    )
    (comp (ref "JP841")
      (value "M01PTH_SMD_3.25X0.85MM_NO_SILK")
      (footprint "eagle-import:1X01_SMD_3.25X0.85MM_NO_SILK")
      (libsource (lib "eagle-import") (part "M01PTH_SMD_3.25X0.85MM_NO_SILK"))
    )
    (comp (ref "JP842")
      (value "M01PTH_SMD_3.25X0.85MM_NO_SILK")
      (footprint "eagle-import:1X01_SMD_3.25X0.85MM_NO_SILK")
      (libsource (lib "eagle-import") (part "M01PTH_SMD_3.25X0.85MM_NO_SILK"))
    )
    (comp (ref "JP843")
      (value "M01PTH_SMD_3.25X0.85MM_NO_SILK")
      (footprint "eagle-import:1X01_SMD_3.25X0.85MM_NO_SILK")
      (libsource (lib "eagle-import") (part "M01PTH_SMD_3.25X0.85MM_NO_SILK"))
    )
    (comp (ref "JP844")
      (value "M01PTH_SMD_3.25X0.85MM_NO_SILK")
      (footprint "eagle-import:1X01_SMD_3.25X0.85MM_NO_SILK")
      (libsource (lib "eagle-import") (part "M01PTH_SMD_3.25X0.85MM_NO_SILK"))
    )
    (comp (ref "JP845")
      (value "M01PTH_SMD_3.25X0.85MM_NO_SILK")
      (footprint "eagle-import:1X01_SMD_3.25X0.85MM_NO_SILK")
      (libsource (lib "eagle-import") (part "M01PTH_SMD_3.25X0.85MM_NO_SILK"))
    )
    (comp (ref "JP846")
      (value "M01PTH_SMD_3.25X0.85MM_NO_SILK")
      (footprint "eagle-import:1X01_SMD_3.25X0.85MM_NO_SILK")
      (libsource (lib "eagle-import") (part "M01PTH_SMD_3.25X0.85MM_NO_SILK"))
    )
    (comp (ref "JP847")
      (value "M01PTH_SMD_3.25X0.85MM_NO_SILK")
      (footprint "eagle-import:1X01_SMD_3.25X0.85MM_NO_SILK")
      (libsource (lib "eagle-import") (part "M01PTH_SMD_3.25X0.85MM_NO_SILK"))
    )
    (comp (ref "JP848")
      (value "M01PTH_SMD_3.25X0.85MM_NO_SILK")
      (footprint "eagle-import:1X01_SMD_3.25X0.85MM_NO_SILK")
      (libsource (lib "eagle-import") (part "M01PTH_SMD_3.25X0.85MM_NO_SILK"))
    )
    (comp (ref "JP849")
      (value "M01PTH_SMD_3.25X0.85MM_NO_SILK")
      (footprint "eagle-import:1X01_SMD_3.25X0.85MM_NO_SILK")
      (libsource (lib "eagle-import") (part "M01PTH_SMD_3.25X0.85MM_NO_SILK"))
    )
    (comp (ref "JP850")
      (value "M01PTH_SMD_3.25X0.85MM_NO_SILK")
      (footprint "eagle-import:1X01_SMD_3.25X0.85MM_NO_SILK")
      (libsource (lib "eagle-import") (part "M01PTH_SMD_3.25X0.85MM_NO_SILK"))
    )
    (comp (ref "JP851")
      (value "M01PTH_SMD_3.25X0.85MM_NO_SILK")
      (footprint "eagle-import:1X01_SMD_3.25X0.85MM_NO_SILK")
      (libsource (lib "eagle-import") (part "M01PTH_SMD_3.25X0.85MM_NO_SILK"))
    )
    (comp (ref "JP852")
      (value "M01PTH_SMD_3.25X0.85MM_NO_SILK")
      (footprint "eagle-import:1X01_SMD_3.25X0.85MM_NO_SILK")
      (libsource (lib "eagle-import") (part "M01PTH_SMD_3.25X0.85MM_NO_SILK"))
    )
    (comp (ref "JP853")
      (value "M01PTH_SMD_3.25X0.85MM_NO_SILK")
      (footprint "eagle-import:1X01_SMD_3.25X0.85MM_NO_SILK")
      (libsource (lib "eagle-import") (part "M01PTH_SMD_3.25X0.85MM_NO_SILK"))
    )
    (comp (ref "JP854")
      (value "M01PTH_SMD_3.25X0.85MM_NO_SILK")
      (footprint "eagle-import:1X01_SMD_3.25X0.85MM_NO_SILK")
      (libsource (lib "eagle-import") (part "M01PTH_SMD_3.25X0.85MM_NO_SILK"))
    )
    (comp (ref "JP855")
      (value "M01PTH_SMD_3.25X0.85MM_NO_SILK")
      (footprint "eagle-import:1X01_SMD_3.25X0.85MM_NO_SILK")
      (libsource (lib "eagle-import") (part "M01PTH_SMD_3.25X0.85MM_NO_SILK"))
    )
    (comp (ref "JP856")
      (value "M01PTH_SMD_3.25X0.85MM_NO_SILK")
      (footprint "eagle-import:1X01_SMD_3.25X0.85MM_NO_SILK")
      (libsource (lib "eagle-import") (part "M01PTH_SMD_3.25X0.85MM_NO_SILK"))
    )
    (comp (ref "JP857")
      (value "M01PTH_SMD_3.25X0.85MM_NO_SILK")
      (footprint "eagle-import:1X01_SMD_3.25X0.85MM_NO_SILK")
      (libsource (lib "eagle-import") (part "M01PTH_SMD_3.25X0.85MM_NO_SILK"))
    )
    (comp (ref "JP858")
      (value "M01PTH_SMD_3.25X0.85MM_NO_SILK")
      (footprint "eagle-import:1X01_SMD_3.25X0.85MM_NO_SILK")
      (libsource (lib "eagle-import") (part "M01PTH_SMD_3.25X0.85MM_NO_SILK"))
    )
    (comp (ref "JP859")
      (value "M01PTH_SMD_3.25X0.85MM_NO_SILK")
      (footprint "eagle-import:1X01_SMD_3.25X0.85MM_NO_SILK")
      (libsource (lib "eagle-import") (part "M01PTH_SMD_3.25X0.85MM_NO_SILK"))
    )
    (comp (ref "JP860")
      (value "M01PTH_SMD_3.25X0.85MM_NO_SILK")
      (footprint "eagle-import:1X01_SMD_3.25X0.85MM_NO_SILK")
      (libsource (lib "eagle-import") (part "M01PTH_SMD_3.25X0.85MM_NO_SILK"))
    )
    (comp (ref "JP861")
      (value "M01PTH_SMD_3.25X0.85MM_NO_SILK")
      (footprint "eagle-import:1X01_SMD_3.25X0.85MM_NO_SILK")
      (libsource (lib "eagle-import") (part "M01PTH_SMD_3.25X0.85MM_NO_SILK"))
    )
    (comp (ref "JP862")
      (value "M01PTH_SMD_3.25X0.85MM_NO_SILK")
      (footprint "eagle-import:1X01_SMD_3.25X0.85MM_NO_SILK")
      (libsource (lib "eagle-import") (part "M01PTH_SMD_3.25X0.85MM_NO_SILK"))
    )
    (comp (ref "JP863")
      (value "M01PTH_SMD_3.25X0.85MM_NO_SILK")
      (footprint "eagle-import:1X01_SMD_3.25X0.85MM_NO_SILK")
      (libsource (lib "eagle-import") (part "M01PTH_SMD_3.25X0.85MM_NO_SILK"))
    )
    (comp (ref "JP864")
      (value "M01PTH_SMD_3.25X0.85MM_NO_SILK")
      (footprint "eagle-import:1X01_SMD_3.25X0.85MM_NO_SILK")
      (libsource (lib "eagle-import") (part "M01PTH_SMD_3.25X0.85MM_NO_SILK"))
    )
    (comp (ref "JP865")
      (value "M01PTH_SMD_3.25X0.85MM_NO_SILK")
      (footprint "eagle-import:1X01_SMD_3.25X0.85MM_NO_SILK")
      (libsource (lib "eagle-import") (part "M01PTH_SMD_3.25X0.85MM_NO_SILK"))
    )
    (comp (ref "JP866")
      (value "M01PTH_SMD_3.25X0.85MM_NO_SILK")
      (footprint "eagle-import:1X01_SMD_3.25X0.85MM_NO_SILK")
      (libsource (lib "eagle-import") (part "M01PTH_SMD_3.25X0.85MM_NO_SILK"))
    )
    (comp (ref "JP867")
      (value "M01PTH_SMD_3.25X0.85MM_NO_SILK")
      (footprint "eagle-import:1X01_SMD_3.25X0.85MM_NO_SILK")
      (libsource (lib "eagle-import") (part "M01PTH_SMD_3.25X0.85MM_NO_SILK"))
    )
    (comp (ref "JP868")
      (value "M01PTH_SMD_3.25X0.85MM_NO_SILK")
      (footprint "eagle-import:1X01_SMD_3.25X0.85MM_NO_SILK")
      (libsource (lib "eagle-import") (part "M01PTH_SMD_3.25X0.85MM_NO_SILK"))
    )
    (comp (ref "JP869")
      (value "M01PTH_SMD_3.25X0.85MM_NO_SILK")
      (footprint "eagle-import:1X01_SMD_3.25X0.85MM_NO_SILK")
      (libsource (lib "eagle-import") (part "M01PTH_SMD_3.25X0.85MM_NO_SILK"))
    )
    (comp (ref "JP870")
      (value "M01PTH_SMD_3.25X0.85MM_NO_SILK")
      (footprint "eagle-import:1X01_SMD_3.25X0.85MM_NO_SILK")
      (libsource (lib "eagle-import") (part "M01PTH_SMD_3.25X0.85MM_NO_SILK"))
    )
    (comp (ref "JP871")
      (value "M01PTH_SMD_3.25X0.85MM_NO_SILK")
      (footprint "eagle-import:1X01_SMD_3.25X0.85MM_NO_SILK")
      (libsource (lib "eagle-import") (part "M01PTH_SMD_3.25X0.85MM_NO_SILK"))
    )
    (comp (ref "JP872")
      (value "M01PTH_SMD_3.25X0.85MM_NO_SILK")
      (footprint "eagle-import:1X01_SMD_3.25X0.85MM_NO_SILK")
      (libsource (lib "eagle-import") (part "M01PTH_SMD_3.25X0.85MM_NO_SILK"))
    )
    (comp (ref "JP873")
      (value "M01PTH_SMD_3.25X0.85MM_NO_SILK")
      (footprint "eagle-import:1X01_SMD_3.25X0.85MM_NO_SILK")
      (libsource (lib "eagle-import") (part "M01PTH_SMD_3.25X0.85MM_NO_SILK"))
    )
    (comp (ref "JP874")
      (value "M01PTH_SMD_3.25X0.85MM_NO_SILK")
      (footprint "eagle-import:1X01_SMD_3.25X0.85MM_NO_SILK")
      (libsource (lib "eagle-import") (part "M01PTH_SMD_3.25X0.85MM_NO_SILK"))
    )
    (comp (ref "JP875")
      (value "M01PTH_SMD_3.25X0.85MM_NO_SILK")
      (footprint "eagle-import:1X01_SMD_3.25X0.85MM_NO_SILK")
      (libsource (lib "eagle-import") (part "M01PTH_SMD_3.25X0.85MM_NO_SILK"))
    )
    (comp (ref "JP876")
      (value "M01PTH_SMD_3.25X0.85MM_NO_SILK")
      (footprint "eagle-import:1X01_SMD_3.25X0.85MM_NO_SILK")
      (libsource (lib "eagle-import") (part "M01PTH_SMD_3.25X0.85MM_NO_SILK"))
    )
    (comp (ref "JP877")
      (value "M01PTH_SMD_3.25X0.85MM_NO_SILK")
      (footprint "eagle-import:1X01_SMD_3.25X0.85MM_NO_SILK")
      (libsource (lib "eagle-import") (part "M01PTH_SMD_3.25X0.85MM_NO_SILK"))
    )
    (comp (ref "JP878")
      (value "M01PTH_SMD_3.25X0.85MM_NO_SILK")
      (footprint "eagle-import:1X01_SMD_3.25X0.85MM_NO_SILK")
      (libsource (lib "eagle-import") (part "M01PTH_SMD_3.25X0.85MM_NO_SILK"))
    )
    (comp (ref "JP879")
      (value "M01PTH_SMD_3.25X0.85MM_NO_SILK")
      (footprint "eagle-import:1X01_SMD_3.25X0.85MM_NO_SILK")
      (libsource (lib "eagle-import") (part "M01PTH_SMD_3.25X0.85MM_NO_SILK"))
    )
    (comp (ref "JP880")
      (value "M01PTH_SMD_3.25X0.85MM_NO_SILK")
      (footprint "eagle-import:1X01_SMD_3.25X0.85MM_NO_SILK")
      (libsource (lib "eagle-import") (part "M01PTH_SMD_3.25X0.85MM_NO_SILK"))
    )
    (comp (ref "JP881")
      (value "M01PTH_SMD_3.25X0.85MM_NO_SILK")
      (footprint "eagle-import:1X01_SMD_3.25X0.85MM_NO_SILK")
      (libsource (lib "eagle-import") (part "M01PTH_SMD_3.25X0.85MM_NO_SILK"))
    )
    (comp (ref "JP882")
      (value "M01PTH_SMD_3.25X0.85MM_NO_SILK")
      (footprint "eagle-import:1X01_SMD_3.25X0.85MM_NO_SILK")
      (libsource (lib "eagle-import") (part "M01PTH_SMD_3.25X0.85MM_NO_SILK"))
    )
    (comp (ref "JP883")
      (value "M01PTH_SMD_3.25X0.85MM_NO_SILK")
      (footprint "eagle-import:1X01_SMD_3.25X0.85MM_NO_SILK")
      (libsource (lib "eagle-import") (part "M01PTH_SMD_3.25X0.85MM_NO_SILK"))
    )
    (comp (ref "JP884")
      (value "M01PTH_SMD_3.25X0.85MM_NO_SILK")
      (footprint "eagle-import:1X01_SMD_3.25X0.85MM_NO_SILK")
      (libsource (lib "eagle-import") (part "M01PTH_SMD_3.25X0.85MM_NO_SILK"))
    )
    (comp (ref "JP885")
      (value "M01PTH_SMD_3.25X0.85MM_NO_SILK")
      (footprint "eagle-import:1X01_SMD_3.25X0.85MM_NO_SILK")
      (libsource (lib "eagle-import") (part "M01PTH_SMD_3.25X0.85MM_NO_SILK"))
    )
    (comp (ref "JP886")
      (value "M01PTH_SMD_3.25X0.85MM_NO_SILK")
      (footprint "eagle-import:1X01_SMD_3.25X0.85MM_NO_SILK")
      (libsource (lib "eagle-import") (part "M01PTH_SMD_3.25X0.85MM_NO_SILK"))
    )
    (comp (ref "JP887")
      (value "M01PTH_SMD_3.25X0.85MM_NO_SILK")
      (footprint "eagle-import:1X01_SMD_3.25X0.85MM_NO_SILK")
      (libsource (lib "eagle-import") (part "M01PTH_SMD_3.25X0.85MM_NO_SILK"))
    )
    (comp (ref "JP888")
      (value "M01PTH_SMD_3.25X0.85MM_NO_SILK")
      (footprint "eagle-import:1X01_SMD_3.25X0.85MM_NO_SILK")
      (libsource (lib "eagle-import") (part "M01PTH_SMD_3.25X0.85MM_NO_SILK"))
    )
    (comp (ref "JP889")
      (value "M01PTH_SMD_3.25X0.85MM_NO_SILK")
      (footprint "eagle-import:1X01_SMD_3.25X0.85MM_NO_SILK")
      (libsource (lib "eagle-import") (part "M01PTH_SMD_3.25X0.85MM_NO_SILK"))
    )
    (comp (ref "JP890")
      (value "M01PTH_SMD_3.25X0.85MM_NO_SILK")
      (footprint "eagle-import:1X01_SMD_3.25X0.85MM_NO_SILK")
      (libsource (lib "eagle-import") (part "M01PTH_SMD_3.25X0.85MM_NO_SILK"))
    )
    (comp (ref "JP891")
      (value "M01PTH_SMD_3.25X0.85MM_NO_SILK")
      (footprint "eagle-import:1X01_SMD_3.25X0.85MM_NO_SILK")
      (libsource (lib "eagle-import") (part "M01PTH_SMD_3.25X0.85MM_NO_SILK"))
    )
    (comp (ref "JP892")
      (value "M01PTH_SMD_3.25X0.85MM_NO_SILK")
      (footprint "eagle-import:1X01_SMD_3.25X0.85MM_NO_SILK")
      (libsource (lib "eagle-import") (part "M01PTH_SMD_3.25X0.85MM_NO_SILK"))
    )
    (comp (ref "JP893")
      (value "M01PTH_SMD_3.25X0.85MM_NO_SILK")
      (footprint "eagle-import:1X01_SMD_3.25X0.85MM_NO_SILK")
      (libsource (lib "eagle-import") (part "M01PTH_SMD_3.25X0.85MM_NO_SILK"))
    )
    (comp (ref "JP894")
      (value "M01PTH_SMD_3.25X0.85MM_NO_SILK")
      (footprint "eagle-import:1X01_SMD_3.25X0.85MM_NO_SILK")
      (libsource (lib "eagle-import") (part "M01PTH_SMD_3.25X0.85MM_NO_SILK"))
    )
    (comp (ref "JP895")
      (value "M01PTH_SMD_3.25X0.85MM_NO_SILK")
      (footprint "eagle-import:1X01_SMD_3.25X0.85MM_NO_SILK")
      (libsource (lib "eagle-import") (part "M01PTH_SMD_3.25X0.85MM_NO_SILK"))
    )
    (comp (ref "JP896")
      (value "M01PTH_SMD_3.25X0.85MM_NO_SILK")
      (footprint "eagle-import:1X01_SMD_3.25X0.85MM_NO_SILK")
      (libsource (lib "eagle-import") (part "M01PTH_SMD_3.25X0.85MM_NO_SILK"))
    )
    (comp (ref "JP897")
      (value "M01PTH_SMD_3.25X0.85MM_NO_SILK")
      (footprint "eagle-import:1X01_SMD_3.25X0.85MM_NO_SILK")
      (libsource (lib "eagle-import") (part "M01PTH_SMD_3.25X0.85MM_NO_SILK"))
    )
    (comp (ref "JP898")
      (value "M01PTH_SMD_3.25X0.85MM_NO_SILK")
      (footprint "eagle-import:1X01_SMD_3.25X0.85MM_NO_SILK")
      (libsource (lib "eagle-import") (part "M01PTH_SMD_3.25X0.85MM_NO_SILK"))
    )
    (comp (ref "JP899")
      (value "M01PTH_SMD_3.25X0.85MM_NO_SILK")
      (footprint "eagle-import:1X01_SMD_3.25X0.85MM_NO_SILK")
      (libsource (lib "eagle-import") (part "M01PTH_SMD_3.25X0.85MM_NO_SILK"))
    )
    (comp (ref "JP900")
      (value "M01PTH_SMD_3.25X0.85MM_NO_SILK")
      (footprint "eagle-import:1X01_SMD_3.25X0.85MM_NO_SILK")
      (libsource (lib "eagle-import") (part "M01PTH_SMD_3.25X0.85MM_NO_SILK"))
    )
    (comp (ref "JP901")
      (value "M01PTH_SMD_3.25X0.85MM_NO_SILK")
      (footprint "eagle-import:1X01_SMD_3.25X0.85MM_NO_SILK")
      (libsource (lib "eagle-import") (part "M01PTH_SMD_3.25X0.85MM_NO_SILK"))
    )
    (comp (ref "JP902")
      (value "M01PTH_SMD_3.25X0.85MM_NO_SILK")
      (footprint "eagle-import:1X01_SMD_3.25X0.85MM_NO_SILK")
      (libsource (lib "eagle-import") (part "M01PTH_SMD_3.25X0.85MM_NO_SILK"))
    )
    (comp (ref "JP903")
      (value "M01PTH_SMD_3.25X0.85MM_NO_SILK")
      (footprint "eagle-import:1X01_SMD_3.25X0.85MM_NO_SILK")
      (libsource (lib "eagle-import") (part "M01PTH_SMD_3.25X0.85MM_NO_SILK"))
    )
    (comp (ref "JP904")
      (value "M01PTH_SMD_3.25X0.85MM_NO_SILK")
      (footprint "eagle-import:1X01_SMD_3.25X0.85MM_NO_SILK")
      (libsource (lib "eagle-import") (part "M01PTH_SMD_3.25X0.85MM_NO_SILK"))
    )
    (comp (ref "JP905")
      (value "M01PTH_SMD_3.25X0.85MM_NO_SILK")
      (footprint "eagle-import:1X01_SMD_3.25X0.85MM_NO_SILK")
      (libsource (lib "eagle-import") (part "M01PTH_SMD_3.25X0.85MM_NO_SILK"))
    )
    (comp (ref "JP906")
      (value "M01PTH_SMD_3.25X0.85MM_NO_SILK")
      (footprint "eagle-import:1X01_SMD_3.25X0.85MM_NO_SILK")
      (libsource (lib "eagle-import") (part "M01PTH_SMD_3.25X0.85MM_NO_SILK"))
    )
    (comp (ref "JP907")
      (value "M01PTH_SMD_3.25X0.85MM_NO_SILK")
      (footprint "eagle-import:1X01_SMD_3.25X0.85MM_NO_SILK")
      (libsource (lib "eagle-import") (part "M01PTH_SMD_3.25X0.85MM_NO_SILK"))
    )
    (comp (ref "JP908")
      (value "M01PTH_SMD_3.25X0.85MM_NO_SILK")
      (footprint "eagle-import:1X01_SMD_3.25X0.85MM_NO_SILK")
      (libsource (lib "eagle-import") (part "M01PTH_SMD_3.25X0.85MM_NO_SILK"))
    )
    (comp (ref "JP909")
      (value "M01PTH_SMD_3.25X0.85MM_NO_SILK")
      (footprint "eagle-import:1X01_SMD_3.25X0.85MM_NO_SILK")
      (libsource (lib "eagle-import") (part "M01PTH_SMD_3.25X0.85MM_NO_SILK"))
    )
    (comp (ref "JP910")
      (value "M01PTH_SMD_3.25X0.85MM_NO_SILK")
      (footprint "eagle-import:1X01_SMD_3.25X0.85MM_NO_SILK")
      (libsource (lib "eagle-import") (part "M01PTH_SMD_3.25X0.85MM_NO_SILK"))
    )
    (comp (ref "JP911")
      (value "M01PTH_SMD_3.25X0.85MM_NO_SILK")
      (footprint "eagle-import:1X01_SMD_3.25X0.85MM_NO_SILK")
      (libsource (lib "eagle-import") (part "M01PTH_SMD_3.25X0.85MM_NO_SILK"))
    )
    (comp (ref "JP912")
      (value "M01PTH_SMD_3.25X0.85MM_NO_SILK")
      (footprint "eagle-import:1X01_SMD_3.25X0.85MM_NO_SILK")
      (libsource (lib "eagle-import") (part "M01PTH_SMD_3.25X0.85MM_NO_SILK"))
    )
    (comp (ref "JP913")
      (value "M01PTH_SMD_3.25X0.85MM_NO_SILK")
      (footprint "eagle-import:1X01_SMD_3.25X0.85MM_NO_SILK")
      (libsource (lib "eagle-import") (part "M01PTH_SMD_3.25X0.85MM_NO_SILK"))
    )
    (comp (ref "JP914")
      (value "M01PTH_SMD_3.25X0.85MM_NO_SILK")
      (footprint "eagle-import:1X01_SMD_3.25X0.85MM_NO_SILK")
      (libsource (lib "eagle-import") (part "M01PTH_SMD_3.25X0.85MM_NO_SILK"))
    )
    (comp (ref "JP915")
      (value "M01PTH_SMD_3.25X0.85MM_NO_SILK")
      (footprint "eagle-import:1X01_SMD_3.25X0.85MM_NO_SILK")
      (libsource (lib "eagle-import") (part "M01PTH_SMD_3.25X0.85MM_NO_SILK"))
    )
    (comp (ref "JP916")
      (value "M01PTH_SMD_3.25X0.85MM_NO_SILK")
      (footprint "eagle-import:1X01_SMD_3.25X0.85MM_NO_SILK")
      (libsource (lib "eagle-import") (part "M01PTH_SMD_3.25X0.85MM_NO_SILK"))
    )
    (comp (ref "JP917")
      (value "M01PTH_SMD_3.25X0.85MM_NO_SILK")
      (footprint "eagle-import:1X01_SMD_3.25X0.85MM_NO_SILK")
      (libsource (lib "eagle-import") (part "M01PTH_SMD_3.25X0.85MM_NO_SILK"))
    )
    (comp (ref "JP918")
      (value "M01PTH_SMD_3.25X0.85MM_NO_SILK")
      (footprint "eagle-import:1X01_SMD_3.25X0.85MM_NO_SILK")
      (libsource (lib "eagle-import") (part "M01PTH_SMD_3.25X0.85MM_NO_SILK"))
    )
    (comp (ref "JP919")
      (value "M01PTH_SMD_3.25X0.85MM_NO_SILK")
      (footprint "eagle-import:1X01_SMD_3.25X0.85MM_NO_SILK")
      (libsource (lib "eagle-import") (part "M01PTH_SMD_3.25X0.85MM_NO_SILK"))
    )
    (comp (ref "JP920")
      (value "M01PTH_SMD_3.25X0.85MM_NO_SILK")
      (footprint "eagle-import:1X01_SMD_3.25X0.85MM_NO_SILK")
      (libsource (lib "eagle-import") (part "M01PTH_SMD_3.25X0.85MM_NO_SILK"))
    )
    (comp (ref "JP921")
      (value "M01PTH_SMD_3.25X0.85MM_NO_SILK")
      (footprint "eagle-import:1X01_SMD_3.25X0.85MM_NO_SILK")
      (libsource (lib "eagle-import") (part "M01PTH_SMD_3.25X0.85MM_NO_SILK"))
    )
    (comp (ref "JP922")
      (value "M01PTH_SMD_3.25X0.85MM_NO_SILK")
      (footprint "eagle-import:1X01_SMD_3.25X0.85MM_NO_SILK")
      (libsource (lib "eagle-import") (part "M01PTH_SMD_3.25X0.85MM_NO_SILK"))
    )
    (comp (ref "JP923")
      (value "M01PTH_SMD_3.25X0.85MM_NO_SILK")
      (footprint "eagle-import:1X01_SMD_3.25X0.85MM_NO_SILK")
      (libsource (lib "eagle-import") (part "M01PTH_SMD_3.25X0.85MM_NO_SILK"))
    )
    (comp (ref "JP924")
      (value "M01PTH_SMD_3.25X0.85MM_NO_SILK")
      (footprint "eagle-import:1X01_SMD_3.25X0.85MM_NO_SILK")
      (libsource (lib "eagle-import") (part "M01PTH_SMD_3.25X0.85MM_NO_SILK"))
    )
    (comp (ref "JP925")
      (value "M01PTH_SMD_3.25X0.85MM_NO_SILK")
      (footprint "eagle-import:1X01_SMD_3.25X0.85MM_NO_SILK")
      (libsource (lib "eagle-import") (part "M01PTH_SMD_3.25X0.85MM_NO_SILK"))
    )
    (comp (ref "JP926")
      (value "M01PTH_SMD_3.25X0.85MM_NO_SILK")
      (footprint "eagle-import:1X01_SMD_3.25X0.85MM_NO_SILK")
      (libsource (lib "eagle-import") (part "M01PTH_SMD_3.25X0.85MM_NO_SILK"))
    )
    (comp (ref "JP927")
      (value "M01PTH_SMD_3.25X0.85MM_NO_SILK")
      (footprint "eagle-import:1X01_SMD_3.25X0.85MM_NO_SILK")
      (libsource (lib "eagle-import") (part "M01PTH_SMD_3.25X0.85MM_NO_SILK"))
    )
    (comp (ref "JP928")
      (value "M01PTH_SMD_3.25X0.85MM_NO_SILK")
      (footprint "eagle-import:1X01_SMD_3.25X0.85MM_NO_SILK")
      (libsource (lib "eagle-import") (part "M01PTH_SMD_3.25X0.85MM_NO_SILK"))
    )
    (comp (ref "JP929")
      (value "M01PTH_SMD_3.25X0.85MM_NO_SILK")
      (footprint "eagle-import:1X01_SMD_3.25X0.85MM_NO_SILK")
      (libsource (lib "eagle-import") (part "M01PTH_SMD_3.25X0.85MM_NO_SILK"))
    )
    (comp (ref "JP930")
      (value "M01PTH_SMD_3.25X0.85MM_NO_SILK")
      (footprint "eagle-import:1X01_SMD_3.25X0.85MM_NO_SILK")
      (libsource (lib "eagle-import") (part "M01PTH_SMD_3.25X0.85MM_NO_SILK"))
    )
    (comp (ref "JP931")
      (value "M01PTH_SMD_3.25X0.85MM_NO_SILK")
      (footprint "eagle-import:1X01_SMD_3.25X0.85MM_NO_SILK")
      (libsource (lib "eagle-import") (part "M01PTH_SMD_3.25X0.85MM_NO_SILK"))
    )
    (comp (ref "JP932")
      (value "M01PTH_SMD_3.25X0.85MM_NO_SILK")
      (footprint "eagle-import:1X01_SMD_3.25X0.85MM_NO_SILK")
      (libsource (lib "eagle-import") (part "M01PTH_SMD_3.25X0.85MM_NO_SILK"))
    )
    (comp (ref "JP933")
      (value "M01PTH_SMD_3.25X0.85MM_NO_SILK")
      (footprint "eagle-import:1X01_SMD_3.25X0.85MM_NO_SILK")
      (libsource (lib "eagle-import") (part "M01PTH_SMD_3.25X0.85MM_NO_SILK"))
    )
    (comp (ref "JP934")
      (value "M01PTH_SMD_3.25X0.85MM_NO_SILK")
      (footprint "eagle-import:1X01_SMD_3.25X0.85MM_NO_SILK")
      (libsource (lib "eagle-import") (part "M01PTH_SMD_3.25X0.85MM_NO_SILK"))
    )
    (comp (ref "JP935")
      (value "M01PTH_SMD_3.25X0.85MM_NO_SILK")
      (footprint "eagle-import:1X01_SMD_3.25X0.85MM_NO_SILK")
      (libsource (lib "eagle-import") (part "M01PTH_SMD_3.25X0.85MM_NO_SILK"))
    )
    (comp (ref "JP936")
      (value "M01PTH_SMD_3.25X0.85MM_NO_SILK")
      (footprint "eagle-import:1X01_SMD_3.25X0.85MM_NO_SILK")
      (libsource (lib "eagle-import") (part "M01PTH_SMD_3.25X0.85MM_NO_SILK"))
    )
    (comp (ref "JP937")
      (value "M01PTH_SMD_3.25X0.85MM_NO_SILK")
      (footprint "eagle-import:1X01_SMD_3.25X0.85MM_NO_SILK")
      (libsource (lib "eagle-import") (part "M01PTH_SMD_3.25X0.85MM_NO_SILK"))
    )
    (comp (ref "JP938")
      (value "M01PTH_SMD_3.25X0.85MM_NO_SILK")
      (footprint "eagle-import:1X01_SMD_3.25X0.85MM_NO_SILK")
      (libsource (lib "eagle-import") (part "M01PTH_SMD_3.25X0.85MM_NO_SILK"))
    )
    (comp (ref "JP939")
      (value "M01PTH_SMD_3.25X0.85MM_NO_SILK")
      (footprint "eagle-import:1X01_SMD_3.25X0.85MM_NO_SILK")
      (libsource (lib "eagle-import") (part "M01PTH_SMD_3.25X0.85MM_NO_SILK"))
    )
    (comp (ref "JP940")
      (value "M01PTH_SMD_3.25X0.85MM_NO_SILK")
      (footprint "eagle-import:1X01_SMD_3.25X0.85MM_NO_SILK")
      (libsource (lib "eagle-import") (part "M01PTH_SMD_3.25X0.85MM_NO_SILK"))
    )
    (comp (ref "JP941")
      (value "M01PTH_SMD_3.25X0.85MM_NO_SILK")
      (footprint "eagle-import:1X01_SMD_3.25X0.85MM_NO_SILK")
      (libsource (lib "eagle-import") (part "M01PTH_SMD_3.25X0.85MM_NO_SILK"))
    )
    (comp (ref "JP942")
      (value "M01PTH_SMD_3.25X0.85MM_NO_SILK")
      (footprint "eagle-import:1X01_SMD_3.25X0.85MM_NO_SILK")
      (libsource (lib "eagle-import") (part "M01PTH_SMD_3.25X0.85MM_NO_SILK"))
    )
    (comp (ref "JP943")
      (value "M01PTH_SMD_3.25X0.85MM_NO_SILK")
      (footprint "eagle-import:1X01_SMD_3.25X0.85MM_NO_SILK")
      (libsource (lib "eagle-import") (part "M01PTH_SMD_3.25X0.85MM_NO_SILK"))
    )
    (comp (ref "JP944")
      (value "M01PTH_SMD_3.25X0.85MM_NO_SILK")
      (footprint "eagle-import:1X01_SMD_3.25X0.85MM_NO_SILK")
      (libsource (lib "eagle-import") (part "M01PTH_SMD_3.25X0.85MM_NO_SILK"))
    )
    (comp (ref "JP945")
      (value "M01PTH_SMD_3.25X0.85MM_NO_SILK")
      (footprint "eagle-import:1X01_SMD_3.25X0.85MM_NO_SILK")
      (libsource (lib "eagle-import") (part "M01PTH_SMD_3.25X0.85MM_NO_SILK"))
    )
    (comp (ref "JP946")
      (value "M01PTH_SMD_3.25X0.85MM_NO_SILK")
      (footprint "eagle-import:1X01_SMD_3.25X0.85MM_NO_SILK")
      (libsource (lib "eagle-import") (part "M01PTH_SMD_3.25X0.85MM_NO_SILK"))
    )
    (comp (ref "JP947")
      (value "M01PTH_SMD_3.25X0.85MM_NO_SILK")
      (footprint "eagle-import:1X01_SMD_3.25X0.85MM_NO_SILK")
      (libsource (lib "eagle-import") (part "M01PTH_SMD_3.25X0.85MM_NO_SILK"))
    )
    (comp (ref "JP948")
      (value "M01PTH_SMD_3.25X0.85MM_NO_SILK")
      (footprint "eagle-import:1X01_SMD_3.25X0.85MM_NO_SILK")
      (libsource (lib "eagle-import") (part "M01PTH_SMD_3.25X0.85MM_NO_SILK"))
    )
    (comp (ref "JP949")
      (value "M01PTH_SMD_3.25X0.85MM_NO_SILK")
      (footprint "eagle-import:1X01_SMD_3.25X0.85MM_NO_SILK")
      (libsource (lib "eagle-import") (part "M01PTH_SMD_3.25X0.85MM_NO_SILK"))
    )
    (comp (ref "JP950")
      (value "M01PTH_SMD_3.25X0.85MM_NO_SILK")
      (footprint "eagle-import:1X01_SMD_3.25X0.85MM_NO_SILK")
      (libsource (lib "eagle-import") (part "M01PTH_SMD_3.25X0.85MM_NO_SILK"))
    )
    (comp (ref "JP951")
      (value "M01PTH_SMD_3.25X0.85MM_NO_SILK")
      (footprint "eagle-import:1X01_SMD_3.25X0.85MM_NO_SILK")
      (libsource (lib "eagle-import") (part "M01PTH_SMD_3.25X0.85MM_NO_SILK"))
    )
    (comp (ref "JP952")
      (value "M01PTH_SMD_3.25X0.85MM_NO_SILK")
      (footprint "eagle-import:1X01_SMD_3.25X0.85MM_NO_SILK")
      (libsource (lib "eagle-import") (part "M01PTH_SMD_3.25X0.85MM_NO_SILK"))
    )
    (comp (ref "JP953")
      (value "M01PTH_SMD_3.25X0.85MM_NO_SILK")
      (footprint "eagle-import:1X01_SMD_3.25X0.85MM_NO_SILK")
      (libsource (lib "eagle-import") (part "M01PTH_SMD_3.25X0.85MM_NO_SILK"))
    )
    (comp (ref "JP954")
      (value "M01PTH_SMD_3.25X0.85MM_NO_SILK")
      (footprint "eagle-import:1X01_SMD_3.25X0.85MM_NO_SILK")
      (libsource (lib "eagle-import") (part "M01PTH_SMD_3.25X0.85MM_NO_SILK"))
    )
    (comp (ref "JP955")
      (value "M01PTH_SMD_3.25X0.85MM_NO_SILK")
      (footprint "eagle-import:1X01_SMD_3.25X0.85MM_NO_SILK")
      (libsource (lib "eagle-import") (part "M01PTH_SMD_3.25X0.85MM_NO_SILK"))
    )
    (comp (ref "JP956")
      (value "M01PTH_SMD_3.25X0.85MM_NO_SILK")
      (footprint "eagle-import:1X01_SMD_3.25X0.85MM_NO_SILK")
      (libsource (lib "eagle-import") (part "M01PTH_SMD_3.25X0.85MM_NO_SILK"))
    )
    (comp (ref "JP957")
      (value "M01PTH_SMD_3.25X0.85MM_NO_SILK")
      (footprint "eagle-import:1X01_SMD_3.25X0.85MM_NO_SILK")
      (libsource (lib "eagle-import") (part "M01PTH_SMD_3.25X0.85MM_NO_SILK"))
    )
    (comp (ref "JP958")
      (value "M01PTH_SMD_3.25X0.85MM_NO_SILK")
      (footprint "eagle-import:1X01_SMD_3.25X0.85MM_NO_SILK")
      (libsource (lib "eagle-import") (part "M01PTH_SMD_3.25X0.85MM_NO_SILK"))
    )
    (comp (ref "JP959")
      (value "M01PTH_SMD_3.25X0.85MM_NO_SILK")
      (footprint "eagle-import:1X01_SMD_3.25X0.85MM_NO_SILK")
      (libsource (lib "eagle-import") (part "M01PTH_SMD_3.25X0.85MM_NO_SILK"))
    )
    (comp (ref "JP960")
      (value "M01PTH_SMD_3.25X0.85MM_NO_SILK")
      (footprint "eagle-import:1X01_SMD_3.25X0.85MM_NO_SILK")
      (libsource (lib "eagle-import") (part "M01PTH_SMD_3.25X0.85MM_NO_SILK"))
    )
    (comp (ref "JP961")
      (value "M01PTH_SMD_3.25X0.85MM_NO_SILK")
      (footprint "eagle-import:1X01_SMD_3.25X0.85MM_NO_SILK")
      (libsource (lib "eagle-import") (part "M01PTH_SMD_3.25X0.85MM_NO_SILK"))
    )
    (comp (ref "JP962")
      (value "M01PTH_SMD_3.25X0.85MM_NO_SILK")
      (footprint "eagle-import:1X01_SMD_3.25X0.85MM_NO_SILK")
      (libsource (lib "eagle-import") (part "M01PTH_SMD_3.25X0.85MM_NO_SILK"))
    )
    (comp (ref "JP963")
      (value "M01PTH_SMD_3.25X0.85MM_NO_SILK")
      (footprint "eagle-import:1X01_SMD_3.25X0.85MM_NO_SILK")
      (libsource (lib "eagle-import") (part "M01PTH_SMD_3.25X0.85MM_NO_SILK"))
    )
    (comp (ref "JP964")
      (value "M01PTH_SMD_3.25X0.85MM_NO_SILK")
      (footprint "eagle-import:1X01_SMD_3.25X0.85MM_NO_SILK")
      (libsource (lib "eagle-import") (part "M01PTH_SMD_3.25X0.85MM_NO_SILK"))
    )
    (comp (ref "JP965")
      (value "M01PTH_SMD_3.25X0.85MM_NO_SILK")
      (footprint "eagle-import:1X01_SMD_3.25X0.85MM_NO_SILK")
      (libsource (lib "eagle-import") (part "M01PTH_SMD_3.25X0.85MM_NO_SILK"))
    )
    (comp (ref "JP966")
      (value "M01PTH_SMD_3.25X0.85MM_NO_SILK")
      (footprint "eagle-import:1X01_SMD_3.25X0.85MM_NO_SILK")
      (libsource (lib "eagle-import") (part "M01PTH_SMD_3.25X0.85MM_NO_SILK"))
    )
    (comp (ref "JP967")
      (value "M01PTH_SMD_3.25X0.85MM_NO_SILK")
      (footprint "eagle-import:1X01_SMD_3.25X0.85MM_NO_SILK")
      (libsource (lib "eagle-import") (part "M01PTH_SMD_3.25X0.85MM_NO_SILK"))
    )
    (comp (ref "JP968")
      (value "M01PTH_SMD_3.25X0.85MM_NO_SILK")
      (footprint "eagle-import:1X01_SMD_3.25X0.85MM_NO_SILK")
      (libsource (lib "eagle-import") (part "M01PTH_SMD_3.25X0.85MM_NO_SILK"))
    )
    (comp (ref "JP969")
      (value "M01PTH_SMD_3.25X0.85MM_NO_SILK")
      (footprint "eagle-import:1X01_SMD_3.25X0.85MM_NO_SILK")
      (libsource (lib "eagle-import") (part "M01PTH_SMD_3.25X0.85MM_NO_SILK"))
    )
    (comp (ref "JP970")
      (value "M01PTH_SMD_3.25X0.85MM_NO_SILK")
      (footprint "eagle-import:1X01_SMD_3.25X0.85MM_NO_SILK")
      (libsource (lib "eagle-import") (part "M01PTH_SMD_3.25X0.85MM_NO_SILK"))
    )
    (comp (ref "JP971")
      (value "M01PTH_SMD_3.25X0.85MM_NO_SILK")
      (footprint "eagle-import:1X01_SMD_3.25X0.85MM_NO_SILK")
      (libsource (lib "eagle-import") (part "M01PTH_SMD_3.25X0.85MM_NO_SILK"))
    )
    (comp (ref "JP972")
      (value "M01PTH_SMD_3.25X0.85MM_NO_SILK")
      (footprint "eagle-import:1X01_SMD_3.25X0.85MM_NO_SILK")
      (libsource (lib "eagle-import") (part "M01PTH_SMD_3.25X0.85MM_NO_SILK"))
    )
    (comp (ref "JP973")
      (value "M01PTH_SMD_3.25X0.85MM_NO_SILK")
      (footprint "eagle-import:1X01_SMD_3.25X0.85MM_NO_SILK")
      (libsource (lib "eagle-import") (part "M01PTH_SMD_3.25X0.85MM_NO_SILK"))
    )
    (comp (ref "JP974")
      (value "M01PTH_SMD_3.25X0.85MM_NO_SILK")
      (footprint "eagle-import:1X01_SMD_3.25X0.85MM_NO_SILK")
      (libsource (lib "eagle-import") (part "M01PTH_SMD_3.25X0.85MM_NO_SILK"))
    )
    (comp (ref "JP975")
      (value "M01PTH_SMD_3.25X0.85MM_NO_SILK")
      (footprint "eagle-import:1X01_SMD_3.25X0.85MM_NO_SILK")
      (libsource (lib "eagle-import") (part "M01PTH_SMD_3.25X0.85MM_NO_SILK"))
    )
    (comp (ref "JP976")
      (value "M01PTH_SMD_3.25X0.85MM_NO_SILK")
      (footprint "eagle-import:1X01_SMD_3.25X0.85MM_NO_SILK")
      (libsource (lib "eagle-import") (part "M01PTH_SMD_3.25X0.85MM_NO_SILK"))
    )
    (comp (ref "JP977")
      (value "M01PTH_SMD_3.25X0.85MM_NO_SILK")
      (footprint "eagle-import:1X01_SMD_3.25X0.85MM_NO_SILK")
      (libsource (lib "eagle-import") (part "M01PTH_SMD_3.25X0.85MM_NO_SILK"))
    )
    (comp (ref "JP978")
      (value "M01PTH_SMD_3.25X0.85MM_NO_SILK")
      (footprint "eagle-import:1X01_SMD_3.25X0.85MM_NO_SILK")
      (libsource (lib "eagle-import") (part "M01PTH_SMD_3.25X0.85MM_NO_SILK"))
    )
    (comp (ref "JP979")
      (value "M01PTH_SMD_3.25X0.85MM_NO_SILK")
      (footprint "eagle-import:1X01_SMD_3.25X0.85MM_NO_SILK")
      (libsource (lib "eagle-import") (part "M01PTH_SMD_3.25X0.85MM_NO_SILK"))
    )
    (comp (ref "JP980")
      (value "M01PTH_SMD_3.25X0.85MM_NO_SILK")
      (footprint "eagle-import:1X01_SMD_3.25X0.85MM_NO_SILK")
      (libsource (lib "eagle-import") (part "M01PTH_SMD_3.25X0.85MM_NO_SILK"))
    )
    (comp (ref "JP981")
      (value "M01PTH_SMD_3.25X0.85MM_NO_SILK")
      (footprint "eagle-import:1X01_SMD_3.25X0.85MM_NO_SILK")
      (libsource (lib "eagle-import") (part "M01PTH_SMD_3.25X0.85MM_NO_SILK"))
    )
    (comp (ref "JP982")
      (value "M01PTH_SMD_3.25X0.85MM_NO_SILK")
      (footprint "eagle-import:1X01_SMD_3.25X0.85MM_NO_SILK")
      (libsource (lib "eagle-import") (part "M01PTH_SMD_3.25X0.85MM_NO_SILK"))
    )
    (comp (ref "JP983")
      (value "M01PTH_SMD_3.25X0.85MM_NO_SILK")
      (footprint "eagle-import:1X01_SMD_3.25X0.85MM_NO_SILK")
      (libsource (lib "eagle-import") (part "M01PTH_SMD_3.25X0.85MM_NO_SILK"))
    )
    (comp (ref "JP984")
      (value "M01PTH_SMD_3.25X0.85MM_NO_SILK")
      (footprint "eagle-import:1X01_SMD_3.25X0.85MM_NO_SILK")
      (libsource (lib "eagle-import") (part "M01PTH_SMD_3.25X0.85MM_NO_SILK"))
    )
    (comp (ref "JP985")
      (value "M01PTH_SMD_3.25X0.85MM_NO_SILK")
      (footprint "eagle-import:1X01_SMD_3.25X0.85MM_NO_SILK")
      (libsource (lib "eagle-import") (part "M01PTH_SMD_3.25X0.85MM_NO_SILK"))
    )
    (comp (ref "JP986")
      (value "M01PTH_SMD_3.25X0.85MM_NO_SILK")
      (footprint "eagle-import:1X01_SMD_3.25X0.85MM_NO_SILK")
      (libsource (lib "eagle-import") (part "M01PTH_SMD_3.25X0.85MM_NO_SILK"))
    )
    (comp (ref "JP987")
      (value "M01PTH_SMD_3.25X0.85MM_NO_SILK")
      (footprint "eagle-import:1X01_SMD_3.25X0.85MM_NO_SILK")
      (libsource (lib "eagle-import") (part "M01PTH_SMD_3.25X0.85MM_NO_SILK"))
    )
    (comp (ref "JP988")
      (value "M01PTH_SMD_3.25X0.85MM_NO_SILK")
      (footprint "eagle-import:1X01_SMD_3.25X0.85MM_NO_SILK")
      (libsource (lib "eagle-import") (part "M01PTH_SMD_3.25X0.85MM_NO_SILK"))
    )
    (comp (ref "JP989")
      (value "M01PTH_SMD_3.25X0.85MM_NO_SILK")
      (footprint "eagle-import:1X01_SMD_3.25X0.85MM_NO_SILK")
      (libsource (lib "eagle-import") (part "M01PTH_SMD_3.25X0.85MM_NO_SILK"))
    )
    (comp (ref "JP990")
      (value "M01PTH_SMD_3.25X0.85MM_NO_SILK")
      (footprint "eagle-import:1X01_SMD_3.25X0.85MM_NO_SILK")
      (libsource (lib "eagle-import") (part "M01PTH_SMD_3.25X0.85MM_NO_SILK"))
    )
    (comp (ref "JP991")
      (value "M01PTH_SMD_3.25X0.85MM_NO_SILK")
      (footprint "eagle-import:1X01_SMD_3.25X0.85MM_NO_SILK")
      (libsource (lib "eagle-import") (part "M01PTH_SMD_3.25X0.85MM_NO_SILK"))
    )
    (comp (ref "JP992")
      (value "M01PTH_SMD_3.25X0.85MM_NO_SILK")
      (footprint "eagle-import:1X01_SMD_3.25X0.85MM_NO_SILK")
      (libsource (lib "eagle-import") (part "M01PTH_SMD_3.25X0.85MM_NO_SILK"))
    )
    (comp (ref "JP993")
      (value "M01PTH_SMD_3.25X0.85MM_NO_SILK")
      (footprint "eagle-import:1X01_SMD_3.25X0.85MM_NO_SILK")
      (libsource (lib "eagle-import") (part "M01PTH_SMD_3.25X0.85MM_NO_SILK"))
    )
    (comp (ref "JP994")
      (value "M01PTH_SMD_3.25X0.85MM_NO_SILK")
      (footprint "eagle-import:1X01_SMD_3.25X0.85MM_NO_SILK")
      (libsource (lib "eagle-import") (part "M01PTH_SMD_3.25X0.85MM_NO_SILK"))
    )
    (comp (ref "JP995")
      (value "M01PTH_SMD_3.25X0.85MM_NO_SILK")
      (footprint "eagle-import:1X01_SMD_3.25X0.85MM_NO_SILK")
      (libsource (lib "eagle-import") (part "M01PTH_SMD_3.25X0.85MM_NO_SILK"))
    )
    (comp (ref "JP996")
      (value "M01PTH_SMD_3.25X0.85MM_NO_SILK")
      (footprint "eagle-import:1X01_SMD_3.25X0.85MM_NO_SILK")
      (libsource (lib "eagle-import") (part "M01PTH_SMD_3.25X0.85MM_NO_SILK"))
    )
    (comp (ref "JP997")
      (value "M01PTH_SMD_3.25X0.85MM_NO_SILK")
      (footprint "eagle-import:1X01_SMD_3.25X0.85MM_NO_SILK")
      (libsource (lib "eagle-import") (part "M01PTH_SMD_3.25X0.85MM_NO_SILK"))
    )
    (comp (ref "JP998")
      (value "M01PTH_SMD_3.25X0.85MM_NO_SILK")
      (footprint "eagle-import:1X01_SMD_3.25X0.85MM_NO_SILK")
      (libsource (lib "eagle-import") (part "M01PTH_SMD_3.25X0.85MM_NO_SILK"))
    )
    (comp (ref "JP999")
      (value "M01PTH_SMD_3.25X0.85MM_NO_SILK")
      (footprint "eagle-import:1X01_SMD_3.25X0.85MM_NO_SILK")
      (libsource (lib "eagle-import") (part "M01PTH_SMD_3.25X0.85MM_NO_SILK"))
    )
    (comp (ref "JP1000")
      (value "M01PTH_SMD_3.25X0.85MM_NO_SILK")
      (footprint "eagle-import:1X01_SMD_3.25X0.85MM_NO_SILK")
      (libsource (lib "eagle-import") (part "M01PTH_SMD_3.25X0.85MM_NO_SILK"))
    )
    (comp (ref "JP1001")
      (value "M01PTH_SMD_3.25X0.85MM_NO_SILK")
      (footprint "eagle-import:1X01_SMD_3.25X0.85MM_NO_SILK")
      (libsource (lib "eagle-import") (part "M01PTH_SMD_3.25X0.85MM_NO_SILK"))
    )
    (comp (ref "JP1002")
      (value "M01PTH_SMD_3.25X0.85MM_NO_SILK")
      (footprint "eagle-import:1X01_SMD_3.25X0.85MM_NO_SILK")
      (libsource (lib "eagle-import") (part "M01PTH_SMD_3.25X0.85MM_NO_SILK"))
    )
    (comp (ref "JP1003")
      (value "M01PTH_SMD_3.25X0.85MM_NO_SILK")
      (footprint "eagle-import:1X01_SMD_3.25X0.85MM_NO_SILK")
      (libsource (lib "eagle-import") (part "M01PTH_SMD_3.25X0.85MM_NO_SILK"))
    )
    (comp (ref "JP1004")
      (value "M01PTH_SMD_3.25X0.85MM_NO_SILK")
      (footprint "eagle-import:1X01_SMD_3.25X0.85MM_NO_SILK")
      (libsource (lib "eagle-import") (part "M01PTH_SMD_3.25X0.85MM_NO_SILK"))
    )
    (comp (ref "JP1005")
      (value "M01PTH_SMD_3.25X0.85MM_NO_SILK")
      (footprint "eagle-import:1X01_SMD_3.25X0.85MM_NO_SILK")
      (libsource (lib "eagle-import") (part "M01PTH_SMD_3.25X0.85MM_NO_SILK"))
    )
    (comp (ref "JP1006")
      (value "M01PTH_SMD_3.25X0.85MM_NO_SILK")
      (footprint "eagle-import:1X01_SMD_3.25X0.85MM_NO_SILK")
      (libsource (lib "eagle-import") (part "M01PTH_SMD_3.25X0.85MM_NO_SILK"))
    )
    (comp (ref "JP1007")
      (value "M01PTH_SMD_3.25X0.85MM_NO_SILK")
      (footprint "eagle-import:1X01_SMD_3.25X0.85MM_NO_SILK")
      (libsource (lib "eagle-import") (part "M01PTH_SMD_3.25X0.85MM_NO_SILK"))
    )
    (comp (ref "JP1008")
      (value "M01PTH_SMD_3.25X0.85MM_NO_SILK")
      (footprint "eagle-import:1X01_SMD_3.25X0.85MM_NO_SILK")
      (libsource (lib "eagle-import") (part "M01PTH_SMD_3.25X0.85MM_NO_SILK"))
    )
    (comp (ref "JP1009")
      (value "M01PTH_SMD_3.25X0.85MM_NO_SILK")
      (footprint "eagle-import:1X01_SMD_3.25X0.85MM_NO_SILK")
      (libsource (lib "eagle-import") (part "M01PTH_SMD_3.25X0.85MM_NO_SILK"))
    )
    (comp (ref "JP1010")
      (value "M01PTH_SMD_3.25X0.85MM_NO_SILK")
      (footprint "eagle-import:1X01_SMD_3.25X0.85MM_NO_SILK")
      (libsource (lib "eagle-import") (part "M01PTH_SMD_3.25X0.85MM_NO_SILK"))
    )
    (comp (ref "JP1011")
      (value "M01PTH_SMD_3.25X0.85MM_NO_SILK")
      (footprint "eagle-import:1X01_SMD_3.25X0.85MM_NO_SILK")
      (libsource (lib "eagle-import") (part "M01PTH_SMD_3.25X0.85MM_NO_SILK"))
    )
    (comp (ref "JP1012")
      (value "M01PTH_SMD_3.25X0.85MM_NO_SILK")
      (footprint "eagle-import:1X01_SMD_3.25X0.85MM_NO_SILK")
      (libsource (lib "eagle-import") (part "M01PTH_SMD_3.25X0.85MM_NO_SILK"))
    )
    (comp (ref "JP1013")
      (value "M01PTH_SMD_3.25X0.85MM_NO_SILK")
      (footprint "eagle-import:1X01_SMD_3.25X0.85MM_NO_SILK")
      (libsource (lib "eagle-import") (part "M01PTH_SMD_3.25X0.85MM_NO_SILK"))
    )
    (comp (ref "JP1014")
      (value "M01PTH_SMD_3.25X0.85MM_NO_SILK")
      (footprint "eagle-import:1X01_SMD_3.25X0.85MM_NO_SILK")
      (libsource (lib "eagle-import") (part "M01PTH_SMD_3.25X0.85MM_NO_SILK"))
    )
    (comp (ref "JP1015")
      (value "M01PTH_SMD_3.25X0.85MM_NO_SILK")
      (footprint "eagle-import:1X01_SMD_3.25X0.85MM_NO_SILK")
      (libsource (lib "eagle-import") (part "M01PTH_SMD_3.25X0.85MM_NO_SILK"))
    )
    (comp (ref "JP1016")
      (value "M01PTH_SMD_3.25X0.85MM_NO_SILK")
      (footprint "eagle-import:1X01_SMD_3.25X0.85MM_NO_SILK")
      (libsource (lib "eagle-import") (part "M01PTH_SMD_3.25X0.85MM_NO_SILK"))
    )
    (comp (ref "JP1017")
      (value "M01PTH_SMD_3.25X0.85MM_NO_SILK")
      (footprint "eagle-import:1X01_SMD_3.25X0.85MM_NO_SILK")
      (libsource (lib "eagle-import") (part "M01PTH_SMD_3.25X0.85MM_NO_SILK"))
    )
    (comp (ref "JP1018")
      (value "M01PTH_SMD_3.25X0.85MM_NO_SILK")
      (footprint "eagle-import:1X01_SMD_3.25X0.85MM_NO_SILK")
      (libsource (lib "eagle-import") (part "M01PTH_SMD_3.25X0.85MM_NO_SILK"))
    )
    (comp (ref "JP1019")
      (value "M01PTH_SMD_3.25X0.85MM_NO_SILK")
      (footprint "eagle-import:1X01_SMD_3.25X0.85MM_NO_SILK")
      (libsource (lib "eagle-import") (part "M01PTH_SMD_3.25X0.85MM_NO_SILK"))
    )
    (comp (ref "JP1020")
      (value "M01PTH_SMD_3.25X0.85MM_NO_SILK")
      (footprint "eagle-import:1X01_SMD_3.25X0.85MM_NO_SILK")
      (libsource (lib "eagle-import") (part "M01PTH_SMD_3.25X0.85MM_NO_SILK"))
    )
    (comp (ref "JP1021")
      (value "M01PTH_SMD_3.25X0.85MM_NO_SILK")
      (footprint "eagle-import:1X01_SMD_3.25X0.85MM_NO_SILK")
      (libsource (lib "eagle-import") (part "M01PTH_SMD_3.25X0.85MM_NO_SILK"))
    )
    (comp (ref "JP1022")
      (value "M01PTH_SMD_3.25X0.85MM_NO_SILK")
      (footprint "eagle-import:1X01_SMD_3.25X0.85MM_NO_SILK")
      (libsource (lib "eagle-import") (part "M01PTH_SMD_3.25X0.85MM_NO_SILK"))
    )
    (comp (ref "JP1023")
      (value "M01PTH_SMD_3.25X0.85MM_NO_SILK")
      (footprint "eagle-import:1X01_SMD_3.25X0.85MM_NO_SILK")
      (libsource (lib "eagle-import") (part "M01PTH_SMD_3.25X0.85MM_NO_SILK"))
    )
    (comp (ref "JP1024")
      (value "M01PTH_SMD_3.25X0.85MM_NO_SILK")
      (footprint "eagle-import:1X01_SMD_3.25X0.85MM_NO_SILK")
      (libsource (lib "eagle-import") (part "M01PTH_SMD_3.25X0.85MM_NO_SILK"))
    )
    (comp (ref "JP1025")
      (value "M01PTH_SMD_3.25X0.85MM_NO_SILK")
      (footprint "eagle-import:1X01_SMD_3.25X0.85MM_NO_SILK")
      (libsource (lib "eagle-import") (part "M01PTH_SMD_3.25X0.85MM_NO_SILK"))
    )
    (comp (ref "JP1026")
      (value "M01PTH_SMD_3.25X0.85MM_NO_SILK")
      (footprint "eagle-import:1X01_SMD_3.25X0.85MM_NO_SILK")
      (libsource (lib "eagle-import") (part "M01PTH_SMD_3.25X0.85MM_NO_SILK"))
    )
    (comp (ref "JP1027")
      (value "M01PTH_SMD_3.25X0.85MM_NO_SILK")
      (footprint "eagle-import:1X01_SMD_3.25X0.85MM_NO_SILK")
      (libsource (lib "eagle-import") (part "M01PTH_SMD_3.25X0.85MM_NO_SILK"))
    )
    (comp (ref "JP1028")
      (value "M01PTH_SMD_3.25X0.85MM_NO_SILK")
      (footprint "eagle-import:1X01_SMD_3.25X0.85MM_NO_SILK")
      (libsource (lib "eagle-import") (part "M01PTH_SMD_3.25X0.85MM_NO_SILK"))
    )
    (comp (ref "JP1029")
      (value "M01PTH_SMD_3.25X0.85MM_NO_SILK")
      (footprint "eagle-import:1X01_SMD_3.25X0.85MM_NO_SILK")
      (libsource (lib "eagle-import") (part "M01PTH_SMD_3.25X0.85MM_NO_SILK"))
    )
    (comp (ref "JP1030")
      (value "M01PTH_SMD_3.25X0.85MM_NO_SILK")
      (footprint "eagle-import:1X01_SMD_3.25X0.85MM_NO_SILK")
      (libsource (lib "eagle-import") (part "M01PTH_SMD_3.25X0.85MM_NO_SILK"))
    )
    (comp (ref "JP1031")
      (value "M01PTH_SMD_3.25X0.85MM_NO_SILK")
      (footprint "eagle-import:1X01_SMD_3.25X0.85MM_NO_SILK")
      (libsource (lib "eagle-import") (part "M01PTH_SMD_3.25X0.85MM_NO_SILK"))
    )
    (comp (ref "JP1032")
      (value "M01PTH_SMD_3.25X0.85MM_NO_SILK")
      (footprint "eagle-import:1X01_SMD_3.25X0.85MM_NO_SILK")
      (libsource (lib "eagle-import") (part "M01PTH_SMD_3.25X0.85MM_NO_SILK"))
    )
    (comp (ref "JP1033")
      (value "M01PTH_SMD_3.25X0.85MM_NO_SILK")
      (footprint "eagle-import:1X01_SMD_3.25X0.85MM_NO_SILK")
      (libsource (lib "eagle-import") (part "M01PTH_SMD_3.25X0.85MM_NO_SILK"))
    )
    (comp (ref "JP1034")
      (value "M01PTH_SMD_3.25X0.85MM_NO_SILK")
      (footprint "eagle-import:1X01_SMD_3.25X0.85MM_NO_SILK")
      (libsource (lib "eagle-import") (part "M01PTH_SMD_3.25X0.85MM_NO_SILK"))
    )
    (comp (ref "JP1035")
      (value "M01PTH_SMD_3.25X0.85MM_NO_SILK")
      (footprint "eagle-import:1X01_SMD_3.25X0.85MM_NO_SILK")
      (libsource (lib "eagle-import") (part "M01PTH_SMD_3.25X0.85MM_NO_SILK"))
    )
    (comp (ref "JP1036")
      (value "M01PTH_SMD_3.25X0.85MM_NO_SILK")
      (footprint "eagle-import:1X01_SMD_3.25X0.85MM_NO_SILK")
      (libsource (lib "eagle-import") (part "M01PTH_SMD_3.25X0.85MM_NO_SILK"))
    )
    (comp (ref "JP1037")
      (value "M01PTH_SMD_3.25X0.85MM_NO_SILK")
      (footprint "eagle-import:1X01_SMD_3.25X0.85MM_NO_SILK")
      (libsource (lib "eagle-import") (part "M01PTH_SMD_3.25X0.85MM_NO_SILK"))
    )
    (comp (ref "JP1038")
      (value "M01PTH_SMD_3.25X0.85MM_NO_SILK")
      (footprint "eagle-import:1X01_SMD_3.25X0.85MM_NO_SILK")
      (libsource (lib "eagle-import") (part "M01PTH_SMD_3.25X0.85MM_NO_SILK"))
    )
    (comp (ref "JP1039")
      (value "M01PTH_SMD_3.25X0.85MM_NO_SILK")
      (footprint "eagle-import:1X01_SMD_3.25X0.85MM_NO_SILK")
      (libsource (lib "eagle-import") (part "M01PTH_SMD_3.25X0.85MM_NO_SILK"))
    )
    (comp (ref "JP1040")
      (value "M01PTH_SMD_3.25X0.85MM_NO_SILK")
      (footprint "eagle-import:1X01_SMD_3.25X0.85MM_NO_SILK")
      (libsource (lib "eagle-import") (part "M01PTH_SMD_3.25X0.85MM_NO_SILK"))
    )
    (comp (ref "JP1041")
      (value "M01PTH_SMD_3.25X0.85MM_NO_SILK")
      (footprint "eagle-import:1X01_SMD_3.25X0.85MM_NO_SILK")
      (libsource (lib "eagle-import") (part "M01PTH_SMD_3.25X0.85MM_NO_SILK"))
    )
    (comp (ref "JP1042")
      (value "M01PTH_SMD_3.25X0.85MM_NO_SILK")
      (footprint "eagle-import:1X01_SMD_3.25X0.85MM_NO_SILK")
      (libsource (lib "eagle-import") (part "M01PTH_SMD_3.25X0.85MM_NO_SILK"))
    )
    (comp (ref "JP1043")
      (value "M01PTH_SMD_3.25X0.85MM_NO_SILK")
      (footprint "eagle-import:1X01_SMD_3.25X0.85MM_NO_SILK")
      (libsource (lib "eagle-import") (part "M01PTH_SMD_3.25X0.85MM_NO_SILK"))
    )
    (comp (ref "JP1044")
      (value "M01PTH_SMD_3.25X0.85MM_NO_SILK")
      (footprint "eagle-import:1X01_SMD_3.25X0.85MM_NO_SILK")
      (libsource (lib "eagle-import") (part "M01PTH_SMD_3.25X0.85MM_NO_SILK"))
    )
    (comp (ref "JP1045")
      (value "M01PTH_SMD_3.25X0.85MM_NO_SILK")
      (footprint "eagle-import:1X01_SMD_3.25X0.85MM_NO_SILK")
      (libsource (lib "eagle-import") (part "M01PTH_SMD_3.25X0.85MM_NO_SILK"))
    )
    (comp (ref "JP1046")
      (value "M01PTH_SMD_3.25X0.85MM_NO_SILK")
      (footprint "eagle-import:1X01_SMD_3.25X0.85MM_NO_SILK")
      (libsource (lib "eagle-import") (part "M01PTH_SMD_3.25X0.85MM_NO_SILK"))
    )
    (comp (ref "JP1047")
      (value "M01PTH_SMD_3.25X0.85MM_NO_SILK")
      (footprint "eagle-import:1X01_SMD_3.25X0.85MM_NO_SILK")
      (libsource (lib "eagle-import") (part "M01PTH_SMD_3.25X0.85MM_NO_SILK"))
    )
    (comp (ref "JP1048")
      (value "M01PTH_SMD_3.25X0.85MM_NO_SILK")
      (footprint "eagle-import:1X01_SMD_3.25X0.85MM_NO_SILK")
      (libsource (lib "eagle-import") (part "M01PTH_SMD_3.25X0.85MM_NO_SILK"))
    )
    (comp (ref "JP1049")
      (value "M01PTH_SMD_3.25X0.85MM_NO_SILK")
      (footprint "eagle-import:1X01_SMD_3.25X0.85MM_NO_SILK")
      (libsource (lib "eagle-import") (part "M01PTH_SMD_3.25X0.85MM_NO_SILK"))
    )
    (comp (ref "JP1050")
      (value "M01PTH_SMD_3.25X0.85MM_NO_SILK")
      (footprint "eagle-import:1X01_SMD_3.25X0.85MM_NO_SILK")
      (libsource (lib "eagle-import") (part "M01PTH_SMD_3.25X0.85MM_NO_SILK"))
    )
    (comp (ref "JP1051")
      (value "M01PTH_SMD_3.25X0.85MM_NO_SILK")
      (footprint "eagle-import:1X01_SMD_3.25X0.85MM_NO_SILK")
      (libsource (lib "eagle-import") (part "M01PTH_SMD_3.25X0.85MM_NO_SILK"))
    )
    (comp (ref "JP1052")
      (value "M01PTH_SMD_3.25X0.85MM_NO_SILK")
      (footprint "eagle-import:1X01_SMD_3.25X0.85MM_NO_SILK")
      (libsource (lib "eagle-import") (part "M01PTH_SMD_3.25X0.85MM_NO_SILK"))
    )
    (comp (ref "JP1053")
      (value "M01PTH_SMD_3.25X0.85MM_NO_SILK")
      (footprint "eagle-import:1X01_SMD_3.25X0.85MM_NO_SILK")
      (libsource (lib "eagle-import") (part "M01PTH_SMD_3.25X0.85MM_NO_SILK"))
    )
    (comp (ref "JP1054")
      (value "M01PTH_SMD_3.25X0.85MM_NO_SILK")
      (footprint "eagle-import:1X01_SMD_3.25X0.85MM_NO_SILK")
      (libsource (lib "eagle-import") (part "M01PTH_SMD_3.25X0.85MM_NO_SILK"))
    )
    (comp (ref "JP1055")
      (value "M01PTH_SMD_3.25X0.85MM_NO_SILK")
      (footprint "eagle-import:1X01_SMD_3.25X0.85MM_NO_SILK")
      (libsource (lib "eagle-import") (part "M01PTH_SMD_3.25X0.85MM_NO_SILK"))
    )
    (comp (ref "JP1056")
      (value "M01PTH_SMD_3.25X0.85MM_NO_SILK")
      (footprint "eagle-import:1X01_SMD_3.25X0.85MM_NO_SILK")
      (libsource (lib "eagle-import") (part "M01PTH_SMD_3.25X0.85MM_NO_SILK"))
    )
    (comp (ref "JP1057")
      (value "M01PTH_SMD_3.25X0.85MM_NO_SILK")
      (footprint "eagle-import:1X01_SMD_3.25X0.85MM_NO_SILK")
      (libsource (lib "eagle-import") (part "M01PTH_SMD_3.25X0.85MM_NO_SILK"))
    )
    (comp (ref "JP1058")
      (value "M01PTH_SMD_3.25X0.85MM_NO_SILK")
      (footprint "eagle-import:1X01_SMD_3.25X0.85MM_NO_SILK")
      (libsource (lib "eagle-import") (part "M01PTH_SMD_3.25X0.85MM_NO_SILK"))
    )
    (comp (ref "JP1059")
      (value "M01PTH_SMD_3.25X0.85MM_NO_SILK")
      (footprint "eagle-import:1X01_SMD_3.25X0.85MM_NO_SILK")
      (libsource (lib "eagle-import") (part "M01PTH_SMD_3.25X0.85MM_NO_SILK"))
    )
    (comp (ref "JP1060")
      (value "M01PTH_SMD_3.25X0.85MM_NO_SILK")
      (footprint "eagle-import:1X01_SMD_3.25X0.85MM_NO_SILK")
      (libsource (lib "eagle-import") (part "M01PTH_SMD_3.25X0.85MM_NO_SILK"))
    )
    (comp (ref "JP1061")
      (value "M01PTH_SMD_3.25X0.85MM_NO_SILK")
      (footprint "eagle-import:1X01_SMD_3.25X0.85MM_NO_SILK")
      (libsource (lib "eagle-import") (part "M01PTH_SMD_3.25X0.85MM_NO_SILK"))
    )
    (comp (ref "JP1062")
      (value "M01PTH_SMD_3.25X0.85MM_NO_SILK")
      (footprint "eagle-import:1X01_SMD_3.25X0.85MM_NO_SILK")
      (libsource (lib "eagle-import") (part "M01PTH_SMD_3.25X0.85MM_NO_SILK"))
    )
    (comp (ref "JP1063")
      (value "M01PTH_SMD_3.25X0.85MM_NO_SILK")
      (footprint "eagle-import:1X01_SMD_3.25X0.85MM_NO_SILK")
      (libsource (lib "eagle-import") (part "M01PTH_SMD_3.25X0.85MM_NO_SILK"))
    )
    (comp (ref "JP1064")
      (value "M01PTH_SMD_3.25X0.85MM_NO_SILK")
      (footprint "eagle-import:1X01_SMD_3.25X0.85MM_NO_SILK")
      (libsource (lib "eagle-import") (part "M01PTH_SMD_3.25X0.85MM_NO_SILK"))
    )
    (comp (ref "JP1065")
      (value "M01PTH_SMD_3.25X0.85MM_NO_SILK")
      (footprint "eagle-import:1X01_SMD_3.25X0.85MM_NO_SILK")
      (libsource (lib "eagle-import") (part "M01PTH_SMD_3.25X0.85MM_NO_SILK"))
    )
    (comp (ref "JP1066")
      (value "M01PTH_SMD_3.25X0.85MM_NO_SILK")
      (footprint "eagle-import:1X01_SMD_3.25X0.85MM_NO_SILK")
      (libsource (lib "eagle-import") (part "M01PTH_SMD_3.25X0.85MM_NO_SILK"))
    )
    (comp (ref "JP1067")
      (value "M01PTH_SMD_3.25X0.85MM_NO_SILK")
      (footprint "eagle-import:1X01_SMD_3.25X0.85MM_NO_SILK")
      (libsource (lib "eagle-import") (part "M01PTH_SMD_3.25X0.85MM_NO_SILK"))
    )
    (comp (ref "JP1068")
      (value "M01PTH_SMD_3.25X0.85MM_NO_SILK")
      (footprint "eagle-import:1X01_SMD_3.25X0.85MM_NO_SILK")
      (libsource (lib "eagle-import") (part "M01PTH_SMD_3.25X0.85MM_NO_SILK"))
    )
    (comp (ref "JP1069")
      (value "M01PTH_SMD_3.25X0.85MM_NO_SILK")
      (footprint "eagle-import:1X01_SMD_3.25X0.85MM_NO_SILK")
      (libsource (lib "eagle-import") (part "M01PTH_SMD_3.25X0.85MM_NO_SILK"))
    )
    (comp (ref "JP1070")
      (value "M01PTH_SMD_3.25X0.85MM_NO_SILK")
      (footprint "eagle-import:1X01_SMD_3.25X0.85MM_NO_SILK")
      (libsource (lib "eagle-import") (part "M01PTH_SMD_3.25X0.85MM_NO_SILK"))
    )
    (comp (ref "JP1071")
      (value "M01PTH_SMD_3.25X0.85MM_NO_SILK")
      (footprint "eagle-import:1X01_SMD_3.25X0.85MM_NO_SILK")
      (libsource (lib "eagle-import") (part "M01PTH_SMD_3.25X0.85MM_NO_SILK"))
    )
    (comp (ref "JP1072")
      (value "M01PTH_SMD_3.25X0.85MM_NO_SILK")
      (footprint "eagle-import:1X01_SMD_3.25X0.85MM_NO_SILK")
      (libsource (lib "eagle-import") (part "M01PTH_SMD_3.25X0.85MM_NO_SILK"))
    )
    (comp (ref "JP1073")
      (value "M01PTH_SMD_3.25X0.85MM_NO_SILK")
      (footprint "eagle-import:1X01_SMD_3.25X0.85MM_NO_SILK")
      (libsource (lib "eagle-import") (part "M01PTH_SMD_3.25X0.85MM_NO_SILK"))
    )
    (comp (ref "JP1074")
      (value "M01PTH_SMD_3.25X0.85MM_NO_SILK")
      (footprint "eagle-import:1X01_SMD_3.25X0.85MM_NO_SILK")
      (libsource (lib "eagle-import") (part "M01PTH_SMD_3.25X0.85MM_NO_SILK"))
    )
    (comp (ref "JP1075")
      (value "M01PTH_SMD_3.25X0.85MM_NO_SILK")
      (footprint "eagle-import:1X01_SMD_3.25X0.85MM_NO_SILK")
      (libsource (lib "eagle-import") (part "M01PTH_SMD_3.25X0.85MM_NO_SILK"))
    )
    (comp (ref "JP1076")
      (value "M01PTH_SMD_3.25X0.85MM_NO_SILK")
      (footprint "eagle-import:1X01_SMD_3.25X0.85MM_NO_SILK")
      (libsource (lib "eagle-import") (part "M01PTH_SMD_3.25X0.85MM_NO_SILK"))
    )
    (comp (ref "JP1077")
      (value "M01PTH_SMD_3.25X0.85MM_NO_SILK")
      (footprint "eagle-import:1X01_SMD_3.25X0.85MM_NO_SILK")
      (libsource (lib "eagle-import") (part "M01PTH_SMD_3.25X0.85MM_NO_SILK"))
    )
    (comp (ref "JP1078")
      (value "M01PTH_SMD_3.25X0.85MM_NO_SILK")
      (footprint "eagle-import:1X01_SMD_3.25X0.85MM_NO_SILK")
      (libsource (lib "eagle-import") (part "M01PTH_SMD_3.25X0.85MM_NO_SILK"))
    )
    (comp (ref "JP1079")
      (value "M01PTH_SMD_3.25X0.85MM_NO_SILK")
      (footprint "eagle-import:1X01_SMD_3.25X0.85MM_NO_SILK")
      (libsource (lib "eagle-import") (part "M01PTH_SMD_3.25X0.85MM_NO_SILK"))
    )
    (comp (ref "JP1080")
      (value "M01PTH_SMD_3.25X0.85MM_NO_SILK")
      (footprint "eagle-import:1X01_SMD_3.25X0.85MM_NO_SILK")
      (libsource (lib "eagle-import") (part "M01PTH_SMD_3.25X0.85MM_NO_SILK"))
    )
    (comp (ref "JP1081")
      (value "M01PTH_SMD_3.25X0.85MM_NO_SILK")
      (footprint "eagle-import:1X01_SMD_3.25X0.85MM_NO_SILK")
      (libsource (lib "eagle-import") (part "M01PTH_SMD_3.25X0.85MM_NO_SILK"))
    )
    (comp (ref "JP1082")
      (value "M01PTH_SMD_3.25X0.85MM_NO_SILK")
      (footprint "eagle-import:1X01_SMD_3.25X0.85MM_NO_SILK")
      (libsource (lib "eagle-import") (part "M01PTH_SMD_3.25X0.85MM_NO_SILK"))
    )
    (comp (ref "JP1083")
      (value "M01PTH_SMD_3.25X0.85MM_NO_SILK")
      (footprint "eagle-import:1X01_SMD_3.25X0.85MM_NO_SILK")
      (libsource (lib "eagle-import") (part "M01PTH_SMD_3.25X0.85MM_NO_SILK"))
    )
    (comp (ref "JP1084")
      (value "M01PTH_SMD_3.25X0.85MM_NO_SILK")
      (footprint "eagle-import:1X01_SMD_3.25X0.85MM_NO_SILK")
      (libsource (lib "eagle-import") (part "M01PTH_SMD_3.25X0.85MM_NO_SILK"))
    )
    (comp (ref "JP1085")
      (value "M01PTH_SMD_3.25X0.85MM_NO_SILK")
      (footprint "eagle-import:1X01_SMD_3.25X0.85MM_NO_SILK")
      (libsource (lib "eagle-import") (part "M01PTH_SMD_3.25X0.85MM_NO_SILK"))
    )
    (comp (ref "JP1086")
      (value "M01PTH_SMD_3.25X0.85MM_NO_SILK")
      (footprint "eagle-import:1X01_SMD_3.25X0.85MM_NO_SILK")
      (libsource (lib "eagle-import") (part "M01PTH_SMD_3.25X0.85MM_NO_SILK"))
    )
    (comp (ref "JP1087")
      (value "M01PTH_SMD_3.25X0.85MM_NO_SILK")
      (footprint "eagle-import:1X01_SMD_3.25X0.85MM_NO_SILK")
      (libsource (lib "eagle-import") (part "M01PTH_SMD_3.25X0.85MM_NO_SILK"))
    )
    (comp (ref "JP1088")
      (value "M01PTH_SMD_3.25X0.85MM_NO_SILK")
      (footprint "eagle-import:1X01_SMD_3.25X0.85MM_NO_SILK")
      (libsource (lib "eagle-import") (part "M01PTH_SMD_3.25X0.85MM_NO_SILK"))
    )
    (comp (ref "JP1089")
      (value "M01PTH_SMD_3.25X0.85MM_NO_SILK")
      (footprint "eagle-import:1X01_SMD_3.25X0.85MM_NO_SILK")
      (libsource (lib "eagle-import") (part "M01PTH_SMD_3.25X0.85MM_NO_SILK"))
    )
    (comp (ref "JP1090")
      (value "M01PTH_SMD_3.25X0.85MM_NO_SILK")
      (footprint "eagle-import:1X01_SMD_3.25X0.85MM_NO_SILK")
      (libsource (lib "eagle-import") (part "M01PTH_SMD_3.25X0.85MM_NO_SILK"))
    )
    (comp (ref "JP1091")
      (value "M01PTH_SMD_3.25X0.85MM_NO_SILK")
      (footprint "eagle-import:1X01_SMD_3.25X0.85MM_NO_SILK")
      (libsource (lib "eagle-import") (part "M01PTH_SMD_3.25X0.85MM_NO_SILK"))
    )
    (comp (ref "JP1092")
      (value "M01PTH_SMD_3.25X0.85MM_NO_SILK")
      (footprint "eagle-import:1X01_SMD_3.25X0.85MM_NO_SILK")
      (libsource (lib "eagle-import") (part "M01PTH_SMD_3.25X0.85MM_NO_SILK"))
    )
    (comp (ref "JP1093")
      (value "M01PTH_SMD_3.25X0.85MM_NO_SILK")
      (footprint "eagle-import:1X01_SMD_3.25X0.85MM_NO_SILK")
      (libsource (lib "eagle-import") (part "M01PTH_SMD_3.25X0.85MM_NO_SILK"))
    )
    (comp (ref "JP1094")
      (value "M01PTH_SMD_3.25X0.85MM_NO_SILK")
      (footprint "eagle-import:1X01_SMD_3.25X0.85MM_NO_SILK")
      (libsource (lib "eagle-import") (part "M01PTH_SMD_3.25X0.85MM_NO_SILK"))
    )
    (comp (ref "JP1095")
      (value "M01PTH_SMD_3.25X0.85MM_NO_SILK")
      (footprint "eagle-import:1X01_SMD_3.25X0.85MM_NO_SILK")
      (libsource (lib "eagle-import") (part "M01PTH_SMD_3.25X0.85MM_NO_SILK"))
    )
    (comp (ref "JP1096")
      (value "M01PTH_SMD_3.25X0.85MM_NO_SILK")
      (footprint "eagle-import:1X01_SMD_3.25X0.85MM_NO_SILK")
      (libsource (lib "eagle-import") (part "M01PTH_SMD_3.25X0.85MM_NO_SILK"))
    )
    (comp (ref "JP1097")
      (value "M01PTH_SMD_3.25X0.85MM_NO_SILK")
      (footprint "eagle-import:1X01_SMD_3.25X0.85MM_NO_SILK")
      (libsource (lib "eagle-import") (part "M01PTH_SMD_3.25X0.85MM_NO_SILK"))
    )
    (comp (ref "JP1098")
      (value "M01PTH_SMD_3.25X0.85MM_NO_SILK")
      (footprint "eagle-import:1X01_SMD_3.25X0.85MM_NO_SILK")
      (libsource (lib "eagle-import") (part "M01PTH_SMD_3.25X0.85MM_NO_SILK"))
    )
    (comp (ref "JP1099")
      (value "M01PTH_SMD_3.25X0.85MM_NO_SILK")
      (footprint "eagle-import:1X01_SMD_3.25X0.85MM_NO_SILK")
      (libsource (lib "eagle-import") (part "M01PTH_SMD_3.25X0.85MM_NO_SILK"))
    )
    (comp (ref "JP1100")
      (value "M01PTH_SMD_3.25X0.85MM_NO_SILK")
      (footprint "eagle-import:1X01_SMD_3.25X0.85MM_NO_SILK")
      (libsource (lib "eagle-import") (part "M01PTH_SMD_3.25X0.85MM_NO_SILK"))
    )
    (comp (ref "JP1101")
      (value "M01PTH_SMD_3.25X0.85MM_NO_SILK")
      (footprint "eagle-import:1X01_SMD_3.25X0.85MM_NO_SILK")
      (libsource (lib "eagle-import") (part "M01PTH_SMD_3.25X0.85MM_NO_SILK"))
    )
    (comp (ref "JP1102")
      (value "M01PTH_SMD_3.25X0.85MM_NO_SILK")
      (footprint "eagle-import:1X01_SMD_3.25X0.85MM_NO_SILK")
      (libsource (lib "eagle-import") (part "M01PTH_SMD_3.25X0.85MM_NO_SILK"))
    )
    (comp (ref "JP1103")
      (value "M01PTH_SMD_3.25X0.85MM_NO_SILK")
      (footprint "eagle-import:1X01_SMD_3.25X0.85MM_NO_SILK")
      (libsource (lib "eagle-import") (part "M01PTH_SMD_3.25X0.85MM_NO_SILK"))
    )
    (comp (ref "JP1104")
      (value "M01PTH_SMD_3.25X0.85MM_NO_SILK")
      (footprint "eagle-import:1X01_SMD_3.25X0.85MM_NO_SILK")
      (libsource (lib "eagle-import") (part "M01PTH_SMD_3.25X0.85MM_NO_SILK"))
    )
    (comp (ref "JP1105")
      (value "M01PTH_SMD_3.25X0.85MM_NO_SILK")
      (footprint "eagle-import:1X01_SMD_3.25X0.85MM_NO_SILK")
      (libsource (lib "eagle-import") (part "M01PTH_SMD_3.25X0.85MM_NO_SILK"))
    )
    (comp (ref "JP1106")
      (value "M01PTH_SMD_3.25X0.85MM_NO_SILK")
      (footprint "eagle-import:1X01_SMD_3.25X0.85MM_NO_SILK")
      (libsource (lib "eagle-import") (part "M01PTH_SMD_3.25X0.85MM_NO_SILK"))
    )
    (comp (ref "JP1107")
      (value "M01PTH_SMD_3.25X0.85MM_NO_SILK")
      (footprint "eagle-import:1X01_SMD_3.25X0.85MM_NO_SILK")
      (libsource (lib "eagle-import") (part "M01PTH_SMD_3.25X0.85MM_NO_SILK"))
    )
    (comp (ref "JP1108")
      (value "M01PTH_SMD_3.25X0.85MM_NO_SILK")
      (footprint "eagle-import:1X01_SMD_3.25X0.85MM_NO_SILK")
      (libsource (lib "eagle-import") (part "M01PTH_SMD_3.25X0.85MM_NO_SILK"))
    )
    (comp (ref "JP1109")
      (value "M01PTH_SMD_3.25X0.85MM_NO_SILK")
      (footprint "eagle-import:1X01_SMD_3.25X0.85MM_NO_SILK")
      (libsource (lib "eagle-import") (part "M01PTH_SMD_3.25X0.85MM_NO_SILK"))
    )
    (comp (ref "JP1110")
      (value "M01PTH_SMD_3.25X0.85MM_NO_SILK")
      (footprint "eagle-import:1X01_SMD_3.25X0.85MM_NO_SILK")
      (libsource (lib "eagle-import") (part "M01PTH_SMD_3.25X0.85MM_NO_SILK"))
    )
    (comp (ref "JP1111")
      (value "M01PTH_SMD_3.25X0.85MM_NO_SILK")
      (footprint "eagle-import:1X01_SMD_3.25X0.85MM_NO_SILK")
      (libsource (lib "eagle-import") (part "M01PTH_SMD_3.25X0.85MM_NO_SILK"))
    )
    (comp (ref "JP1112")
      (value "M01PTH_SMD_3.25X0.85MM_NO_SILK")
      (footprint "eagle-import:1X01_SMD_3.25X0.85MM_NO_SILK")
      (libsource (lib "eagle-import") (part "M01PTH_SMD_3.25X0.85MM_NO_SILK"))
    )
    (comp (ref "JP1113")
      (value "M01PTH_SMD_3.25X0.85MM_NO_SILK")
      (footprint "eagle-import:1X01_SMD_3.25X0.85MM_NO_SILK")
      (libsource (lib "eagle-import") (part "M01PTH_SMD_3.25X0.85MM_NO_SILK"))
    )
    (comp (ref "JP1114")
      (value "M01PTH_SMD_3.25X0.85MM_NO_SILK")
      (footprint "eagle-import:1X01_SMD_3.25X0.85MM_NO_SILK")
      (libsource (lib "eagle-import") (part "M01PTH_SMD_3.25X0.85MM_NO_SILK"))
    )
    (comp (ref "JP1115")
      (value "M01PTH_SMD_3.25X0.85MM_NO_SILK")
      (footprint "eagle-import:1X01_SMD_3.25X0.85MM_NO_SILK")
      (libsource (lib "eagle-import") (part "M01PTH_SMD_3.25X0.85MM_NO_SILK"))
    )
    (comp (ref "JP1116")
      (value "M01PTH_SMD_3.25X0.85MM_NO_SILK")
      (footprint "eagle-import:1X01_SMD_3.25X0.85MM_NO_SILK")
      (libsource (lib "eagle-import") (part "M01PTH_SMD_3.25X0.85MM_NO_SILK"))
    )
    (comp (ref "JP1117")
      (value "M01PTH_SMD_3.25X0.85MM_NO_SILK")
      (footprint "eagle-import:1X01_SMD_3.25X0.85MM_NO_SILK")
      (libsource (lib "eagle-import") (part "M01PTH_SMD_3.25X0.85MM_NO_SILK"))
    )
    (comp (ref "JP1118")
      (value "M01PTH_SMD_3.25X0.85MM_NO_SILK")
      (footprint "eagle-import:1X01_SMD_3.25X0.85MM_NO_SILK")
      (libsource (lib "eagle-import") (part "M01PTH_SMD_3.25X0.85MM_NO_SILK"))
    )
    (comp (ref "JP1119")
      (value "M01PTH_SMD_3.25X0.85MM_NO_SILK")
      (footprint "eagle-import:1X01_SMD_3.25X0.85MM_NO_SILK")
      (libsource (lib "eagle-import") (part "M01PTH_SMD_3.25X0.85MM_NO_SILK"))
    )
    (comp (ref "JP1120")
      (value "M01PTH_SMD_3.25X0.85MM_NO_SILK")
      (footprint "eagle-import:1X01_SMD_3.25X0.85MM_NO_SILK")
      (libsource (lib "eagle-import") (part "M01PTH_SMD_3.25X0.85MM_NO_SILK"))
    )
    (comp (ref "JP1121")
      (value "M01PTH_SMD_3.25X0.85MM_NO_SILK")
      (footprint "eagle-import:1X01_SMD_3.25X0.85MM_NO_SILK")
      (libsource (lib "eagle-import") (part "M01PTH_SMD_3.25X0.85MM_NO_SILK"))
    )
    (comp (ref "JP1122")
      (value "M01PTH_SMD_3.25X0.85MM_NO_SILK")
      (footprint "eagle-import:1X01_SMD_3.25X0.85MM_NO_SILK")
      (libsource (lib "eagle-import") (part "M01PTH_SMD_3.25X0.85MM_NO_SILK"))
    )
    (comp (ref "JP1123")
      (value "M01PTH_SMD_3.25X0.85MM_NO_SILK")
      (footprint "eagle-import:1X01_SMD_3.25X0.85MM_NO_SILK")
      (libsource (lib "eagle-import") (part "M01PTH_SMD_3.25X0.85MM_NO_SILK"))
    )
    (comp (ref "JP1124")
      (value "M01PTH_SMD_3.25X0.85MM_NO_SILK")
      (footprint "eagle-import:1X01_SMD_3.25X0.85MM_NO_SILK")
      (libsource (lib "eagle-import") (part "M01PTH_SMD_3.25X0.85MM_NO_SILK"))
    )
    (comp (ref "JP1125")
      (value "M01PTH_SMD_3.25X0.85MM_NO_SILK")
      (footprint "eagle-import:1X01_SMD_3.25X0.85MM_NO_SILK")
      (libsource (lib "eagle-import") (part "M01PTH_SMD_3.25X0.85MM_NO_SILK"))
    )
    (comp (ref "JP1126")
      (value "M01PTH_SMD_3.25X0.85MM_NO_SILK")
      (footprint "eagle-import:1X01_SMD_3.25X0.85MM_NO_SILK")
      (libsource (lib "eagle-import") (part "M01PTH_SMD_3.25X0.85MM_NO_SILK"))
    )
    (comp (ref "JP1127")
      (value "M01PTH_SMD_3.25X0.85MM_NO_SILK")
      (footprint "eagle-import:1X01_SMD_3.25X0.85MM_NO_SILK")
      (libsource (lib "eagle-import") (part "M01PTH_SMD_3.25X0.85MM_NO_SILK"))
    )
    (comp (ref "JP1128")
      (value "M01PTH_SMD_3.25X0.85MM_NO_SILK")
      (footprint "eagle-import:1X01_SMD_3.25X0.85MM_NO_SILK")
      (libsource (lib "eagle-import") (part "M01PTH_SMD_3.25X0.85MM_NO_SILK"))
    )
    (comp (ref "JP1129")
      (value "M01PTH_SMD_3.25X0.85MM_NO_SILK")
      (footprint "eagle-import:1X01_SMD_3.25X0.85MM_NO_SILK")
      (libsource (lib "eagle-import") (part "M01PTH_SMD_3.25X0.85MM_NO_SILK"))
    )
    (comp (ref "JP1130")
      (value "M01PTH_SMD_3.25X0.85MM_NO_SILK")
      (footprint "eagle-import:1X01_SMD_3.25X0.85MM_NO_SILK")
      (libsource (lib "eagle-import") (part "M01PTH_SMD_3.25X0.85MM_NO_SILK"))
    )
    (comp (ref "JP1131")
      (value "M01PTH_SMD_3.25X0.85MM_NO_SILK")
      (footprint "eagle-import:1X01_SMD_3.25X0.85MM_NO_SILK")
      (libsource (lib "eagle-import") (part "M01PTH_SMD_3.25X0.85MM_NO_SILK"))
    )
    (comp (ref "JP1132")
      (value "M01PTH_SMD_3.25X0.85MM_NO_SILK")
      (footprint "eagle-import:1X01_SMD_3.25X0.85MM_NO_SILK")
      (libsource (lib "eagle-import") (part "M01PTH_SMD_3.25X0.85MM_NO_SILK"))
    )
    (comp (ref "JP1133")
      (value "M01PTH_SMD_3.25X0.85MM_NO_SILK")
      (footprint "eagle-import:1X01_SMD_3.25X0.85MM_NO_SILK")
      (libsource (lib "eagle-import") (part "M01PTH_SMD_3.25X0.85MM_NO_SILK"))
    )
    (comp (ref "JP1134")
      (value "M01PTH_SMD_3.25X0.85MM_NO_SILK")
      (footprint "eagle-import:1X01_SMD_3.25X0.85MM_NO_SILK")
      (libsource (lib "eagle-import") (part "M01PTH_SMD_3.25X0.85MM_NO_SILK"))
    )
    (comp (ref "JP1135")
      (value "M01PTH_SMD_3.25X0.85MM_NO_SILK")
      (footprint "eagle-import:1X01_SMD_3.25X0.85MM_NO_SILK")
      (libsource (lib "eagle-import") (part "M01PTH_SMD_3.25X0.85MM_NO_SILK"))
    )
    (comp (ref "JP1136")
      (value "M01PTH_SMD_3.25X0.85MM_NO_SILK")
      (footprint "eagle-import:1X01_SMD_3.25X0.85MM_NO_SILK")
      (libsource (lib "eagle-import") (part "M01PTH_SMD_3.25X0.85MM_NO_SILK"))
    )
    (comp (ref "JP1137")
      (value "M01PTH_SMD_3.25X0.85MM_NO_SILK")
      (footprint "eagle-import:1X01_SMD_3.25X0.85MM_NO_SILK")
      (libsource (lib "eagle-import") (part "M01PTH_SMD_3.25X0.85MM_NO_SILK"))
    )
    (comp (ref "JP1138")
      (value "M01PTH_SMD_3.25X0.85MM_NO_SILK")
      (footprint "eagle-import:1X01_SMD_3.25X0.85MM_NO_SILK")
      (libsource (lib "eagle-import") (part "M01PTH_SMD_3.25X0.85MM_NO_SILK"))
    )
    (comp (ref "JP1139")
      (value "M01PTH_SMD_3.25X0.85MM_NO_SILK")
      (footprint "eagle-import:1X01_SMD_3.25X0.85MM_NO_SILK")
      (libsource (lib "eagle-import") (part "M01PTH_SMD_3.25X0.85MM_NO_SILK"))
    )
    (comp (ref "JP1140")
      (value "M01PTH_SMD_3.25X0.85MM_NO_SILK")
      (footprint "eagle-import:1X01_SMD_3.25X0.85MM_NO_SILK")
      (libsource (lib "eagle-import") (part "M01PTH_SMD_3.25X0.85MM_NO_SILK"))
    )
    (comp (ref "JP1141")
      (value "M01PTH_SMD_3.25X0.85MM_NO_SILK")
      (footprint "eagle-import:1X01_SMD_3.25X0.85MM_NO_SILK")
      (libsource (lib "eagle-import") (part "M01PTH_SMD_3.25X0.85MM_NO_SILK"))
    )
    (comp (ref "JP1142")
      (value "M01PTH_SMD_3.25X0.85MM_NO_SILK")
      (footprint "eagle-import:1X01_SMD_3.25X0.85MM_NO_SILK")
      (libsource (lib "eagle-import") (part "M01PTH_SMD_3.25X0.85MM_NO_SILK"))
    )
    (comp (ref "JP1143")
      (value "M01PTH_SMD_3.25X0.85MM_NO_SILK")
      (footprint "eagle-import:1X01_SMD_3.25X0.85MM_NO_SILK")
      (libsource (lib "eagle-import") (part "M01PTH_SMD_3.25X0.85MM_NO_SILK"))
    )
    (comp (ref "JP1144")
      (value "M01PTH_SMD_3.25X0.85MM_NO_SILK")
      (footprint "eagle-import:1X01_SMD_3.25X0.85MM_NO_SILK")
      (libsource (lib "eagle-import") (part "M01PTH_SMD_3.25X0.85MM_NO_SILK"))
    )
    (comp (ref "JP1145")
      (value "M01PTH_SMD_3.25X0.85MM_NO_SILK")
      (footprint "eagle-import:1X01_SMD_3.25X0.85MM_NO_SILK")
      (libsource (lib "eagle-import") (part "M01PTH_SMD_3.25X0.85MM_NO_SILK"))
    )
    (comp (ref "JP1146")
      (value "M01PTH_SMD_3.25X0.85MM_NO_SILK")
      (footprint "eagle-import:1X01_SMD_3.25X0.85MM_NO_SILK")
      (libsource (lib "eagle-import") (part "M01PTH_SMD_3.25X0.85MM_NO_SILK"))
    )
    (comp (ref "JP1147")
      (value "M01PTH_SMD_3.25X0.85MM_NO_SILK")
      (footprint "eagle-import:1X01_SMD_3.25X0.85MM_NO_SILK")
      (libsource (lib "eagle-import") (part "M01PTH_SMD_3.25X0.85MM_NO_SILK"))
    )
    (comp (ref "JP1148")
      (value "M01PTH_SMD_3.25X0.85MM_NO_SILK")
      (footprint "eagle-import:1X01_SMD_3.25X0.85MM_NO_SILK")
      (libsource (lib "eagle-import") (part "M01PTH_SMD_3.25X0.85MM_NO_SILK"))
    )
    (comp (ref "JP1149")
      (value "M01PTH_SMD_3.25X0.85MM_NO_SILK")
      (footprint "eagle-import:1X01_SMD_3.25X0.85MM_NO_SILK")
      (libsource (lib "eagle-import") (part "M01PTH_SMD_3.25X0.85MM_NO_SILK"))
    )
    (comp (ref "JP1150")
      (value "M01PTH_SMD_3.25X0.85MM_NO_SILK")
      (footprint "eagle-import:1X01_SMD_3.25X0.85MM_NO_SILK")
      (libsource (lib "eagle-import") (part "M01PTH_SMD_3.25X0.85MM_NO_SILK"))
    )
    (comp (ref "JP1151")
      (value "M01PTH_SMD_3.25X0.85MM_NO_SILK")
      (footprint "eagle-import:1X01_SMD_3.25X0.85MM_NO_SILK")
      (libsource (lib "eagle-import") (part "M01PTH_SMD_3.25X0.85MM_NO_SILK"))
    )
    (comp (ref "JP1152")
      (value "M01PTH_SMD_3.25X0.85MM_NO_SILK")
      (footprint "eagle-import:1X01_SMD_3.25X0.85MM_NO_SILK")
      (libsource (lib "eagle-import") (part "M01PTH_SMD_3.25X0.85MM_NO_SILK"))
    )
    (comp (ref "JP1153")
      (value "M01PTH_SMD_3.25X0.85MM_NO_SILK")
      (footprint "eagle-import:1X01_SMD_3.25X0.85MM_NO_SILK")
      (libsource (lib "eagle-import") (part "M01PTH_SMD_3.25X0.85MM_NO_SILK"))
    )
    (comp (ref "JP1154")
      (value "M01PTH_SMD_3.25X0.85MM_NO_SILK")
      (footprint "eagle-import:1X01_SMD_3.25X0.85MM_NO_SILK")
      (libsource (lib "eagle-import") (part "M01PTH_SMD_3.25X0.85MM_NO_SILK"))
    )
    (comp (ref "JP1155")
      (value "M01PTH_SMD_3.25X0.85MM_NO_SILK")
      (footprint "eagle-import:1X01_SMD_3.25X0.85MM_NO_SILK")
      (libsource (lib "eagle-import") (part "M01PTH_SMD_3.25X0.85MM_NO_SILK"))
    )
    (comp (ref "JP1156")
      (value "M01PTH_SMD_3.25X0.85MM_NO_SILK")
      (footprint "eagle-import:1X01_SMD_3.25X0.85MM_NO_SILK")
      (libsource (lib "eagle-import") (part "M01PTH_SMD_3.25X0.85MM_NO_SILK"))
    )
    (comp (ref "JP1157")
      (value "M01PTH_SMD_3.25X0.85MM_NO_SILK")
      (footprint "eagle-import:1X01_SMD_3.25X0.85MM_NO_SILK")
      (libsource (lib "eagle-import") (part "M01PTH_SMD_3.25X0.85MM_NO_SILK"))
    )
    (comp (ref "JP1158")
      (value "M01PTH_SMD_3.25X0.85MM_NO_SILK")
      (footprint "eagle-import:1X01_SMD_3.25X0.85MM_NO_SILK")
      (libsource (lib "eagle-import") (part "M01PTH_SMD_3.25X0.85MM_NO_SILK"))
    )
    (comp (ref "JP1159")
      (value "M01PTH_SMD_3.25X0.85MM_NO_SILK")
      (footprint "eagle-import:1X01_SMD_3.25X0.85MM_NO_SILK")
      (libsource (lib "eagle-import") (part "M01PTH_SMD_3.25X0.85MM_NO_SILK"))
    )
    (comp (ref "JP1160")
      (value "M01PTH_SMD_3.25X0.85MM_NO_SILK")
      (footprint "eagle-import:1X01_SMD_3.25X0.85MM_NO_SILK")
      (libsource (lib "eagle-import") (part "M01PTH_SMD_3.25X0.85MM_NO_SILK"))
    )
    (comp (ref "JP1161")
      (value "M01PTH_SMD_3.25X0.85MM_NO_SILK")
      (footprint "eagle-import:1X01_SMD_3.25X0.85MM_NO_SILK")
      (libsource (lib "eagle-import") (part "M01PTH_SMD_3.25X0.85MM_NO_SILK"))
    )
    (comp (ref "JP1162")
      (value "M01PTH_SMD_3.25X0.85MM_NO_SILK")
      (footprint "eagle-import:1X01_SMD_3.25X0.85MM_NO_SILK")
      (libsource (lib "eagle-import") (part "M01PTH_SMD_3.25X0.85MM_NO_SILK"))
    )
    (comp (ref "JP1163")
      (value "M01PTH_SMD_3.25X0.85MM_NO_SILK")
      (footprint "eagle-import:1X01_SMD_3.25X0.85MM_NO_SILK")
      (libsource (lib "eagle-import") (part "M01PTH_SMD_3.25X0.85MM_NO_SILK"))
    )
    (comp (ref "JP1164")
      (value "M01PTH_SMD_3.25X0.85MM_NO_SILK")
      (footprint "eagle-import:1X01_SMD_3.25X0.85MM_NO_SILK")
      (libsource (lib "eagle-import") (part "M01PTH_SMD_3.25X0.85MM_NO_SILK"))
    )
    (comp (ref "JP1165")
      (value "M01PTH_SMD_3.25X0.85MM_NO_SILK")
      (footprint "eagle-import:1X01_SMD_3.25X0.85MM_NO_SILK")
      (libsource (lib "eagle-import") (part "M01PTH_SMD_3.25X0.85MM_NO_SILK"))
    )
    (comp (ref "JP1166")
      (value "M01PTH_SMD_3.25X0.85MM_NO_SILK")
      (footprint "eagle-import:1X01_SMD_3.25X0.85MM_NO_SILK")
      (libsource (lib "eagle-import") (part "M01PTH_SMD_3.25X0.85MM_NO_SILK"))
    )
    (comp (ref "JP1167")
      (value "M01PTH_SMD_3.25X0.85MM_NO_SILK")
      (footprint "eagle-import:1X01_SMD_3.25X0.85MM_NO_SILK")
      (libsource (lib "eagle-import") (part "M01PTH_SMD_3.25X0.85MM_NO_SILK"))
    )
    (comp (ref "JP1168")
      (value "M01PTH_SMD_3.25X0.85MM_NO_SILK")
      (footprint "eagle-import:1X01_SMD_3.25X0.85MM_NO_SILK")
      (libsource (lib "eagle-import") (part "M01PTH_SMD_3.25X0.85MM_NO_SILK"))
    )
    (comp (ref "JP1169")
      (value "M01PTH_SMD_3.25X0.85MM_NO_SILK")
      (footprint "eagle-import:1X01_SMD_3.25X0.85MM_NO_SILK")
      (libsource (lib "eagle-import") (part "M01PTH_SMD_3.25X0.85MM_NO_SILK"))
    )
    (comp (ref "JP1170")
      (value "M01PTH_SMD_3.25X0.85MM_NO_SILK")
      (footprint "eagle-import:1X01_SMD_3.25X0.85MM_NO_SILK")
      (libsource (lib "eagle-import") (part "M01PTH_SMD_3.25X0.85MM_NO_SILK"))
    )
    (comp (ref "JP1171")
      (value "M01PTH_SMD_3.25X0.85MM_NO_SILK")
      (footprint "eagle-import:1X01_SMD_3.25X0.85MM_NO_SILK")
      (libsource (lib "eagle-import") (part "M01PTH_SMD_3.25X0.85MM_NO_SILK"))
    )
    (comp (ref "JP1172")
      (value "M01PTH_SMD_3.25X0.85MM_NO_SILK")
      (footprint "eagle-import:1X01_SMD_3.25X0.85MM_NO_SILK")
      (libsource (lib "eagle-import") (part "M01PTH_SMD_3.25X0.85MM_NO_SILK"))
    )
    (comp (ref "JP1173")
      (value "M01PTH_SMD_3.25X0.85MM_NO_SILK")
      (footprint "eagle-import:1X01_SMD_3.25X0.85MM_NO_SILK")
      (libsource (lib "eagle-import") (part "M01PTH_SMD_3.25X0.85MM_NO_SILK"))
    )
    (comp (ref "JP1174")
      (value "M01PTH_SMD_3.25X0.85MM_NO_SILK")
      (footprint "eagle-import:1X01_SMD_3.25X0.85MM_NO_SILK")
      (libsource (lib "eagle-import") (part "M01PTH_SMD_3.25X0.85MM_NO_SILK"))
    )
    (comp (ref "JP1175")
      (value "M01PTH_SMD_3.25X0.85MM_NO_SILK")
      (footprint "eagle-import:1X01_SMD_3.25X0.85MM_NO_SILK")
      (libsource (lib "eagle-import") (part "M01PTH_SMD_3.25X0.85MM_NO_SILK"))
    )
    (comp (ref "JP1176")
      (value "M01PTH_SMD_3.25X0.85MM_NO_SILK")
      (footprint "eagle-import:1X01_SMD_3.25X0.85MM_NO_SILK")
      (libsource (lib "eagle-import") (part "M01PTH_SMD_3.25X0.85MM_NO_SILK"))
    )
    (comp (ref "JP1177")
      (value "M01PTH_SMD_3.25X0.85MM_NO_SILK")
      (footprint "eagle-import:1X01_SMD_3.25X0.85MM_NO_SILK")
      (libsource (lib "eagle-import") (part "M01PTH_SMD_3.25X0.85MM_NO_SILK"))
    )
    (comp (ref "JP1178")
      (value "M01PTH_SMD_3.25X0.85MM_NO_SILK")
      (footprint "eagle-import:1X01_SMD_3.25X0.85MM_NO_SILK")
      (libsource (lib "eagle-import") (part "M01PTH_SMD_3.25X0.85MM_NO_SILK"))
    )
    (comp (ref "JP1179")
      (value "M01PTH_SMD_3.25X0.85MM_NO_SILK")
      (footprint "eagle-import:1X01_SMD_3.25X0.85MM_NO_SILK")
      (libsource (lib "eagle-import") (part "M01PTH_SMD_3.25X0.85MM_NO_SILK"))
    )
    (comp (ref "JP1180")
      (value "M01PTH_SMD_3.25X0.85MM_NO_SILK")
      (footprint "eagle-import:1X01_SMD_3.25X0.85MM_NO_SILK")
      (libsource (lib "eagle-import") (part "M01PTH_SMD_3.25X0.85MM_NO_SILK"))
    )
    (comp (ref "JP1181")
      (value "M01PTH_SMD_3.25X0.85MM_NO_SILK")
      (footprint "eagle-import:1X01_SMD_3.25X0.85MM_NO_SILK")
      (libsource (lib "eagle-import") (part "M01PTH_SMD_3.25X0.85MM_NO_SILK"))
    )
    (comp (ref "JP1182")
      (value "M01PTH_SMD_3.25X0.85MM_NO_SILK")
      (footprint "eagle-import:1X01_SMD_3.25X0.85MM_NO_SILK")
      (libsource (lib "eagle-import") (part "M01PTH_SMD_3.25X0.85MM_NO_SILK"))
    )
    (comp (ref "JP1183")
      (value "M01PTH_SMD_3.25X0.85MM_NO_SILK")
      (footprint "eagle-import:1X01_SMD_3.25X0.85MM_NO_SILK")
      (libsource (lib "eagle-import") (part "M01PTH_SMD_3.25X0.85MM_NO_SILK"))
    )
    (comp (ref "JP1184")
      (value "M01PTH_SMD_3.25X0.85MM_NO_SILK")
      (footprint "eagle-import:1X01_SMD_3.25X0.85MM_NO_SILK")
      (libsource (lib "eagle-import") (part "M01PTH_SMD_3.25X0.85MM_NO_SILK"))
    )
    (comp (ref "JP1185")
      (value "M01PTH_SMD_3.25X0.85MM_NO_SILK")
      (footprint "eagle-import:1X01_SMD_3.25X0.85MM_NO_SILK")
      (libsource (lib "eagle-import") (part "M01PTH_SMD_3.25X0.85MM_NO_SILK"))
    )
    (comp (ref "JP1186")
      (value "M01PTH_SMD_3.25X0.85MM_NO_SILK")
      (footprint "eagle-import:1X01_SMD_3.25X0.85MM_NO_SILK")
      (libsource (lib "eagle-import") (part "M01PTH_SMD_3.25X0.85MM_NO_SILK"))
    )
    (comp (ref "JP1187")
      (value "M01PTH_SMD_3.25X0.85MM_NO_SILK")
      (footprint "eagle-import:1X01_SMD_3.25X0.85MM_NO_SILK")
      (libsource (lib "eagle-import") (part "M01PTH_SMD_3.25X0.85MM_NO_SILK"))
    )
    (comp (ref "JP1188")
      (value "M01PTH_SMD_3.25X0.85MM_NO_SILK")
      (footprint "eagle-import:1X01_SMD_3.25X0.85MM_NO_SILK")
      (libsource (lib "eagle-import") (part "M01PTH_SMD_3.25X0.85MM_NO_SILK"))
    )
    (comp (ref "JP1189")
      (value "M01PTH_SMD_3.25X0.85MM_NO_SILK")
      (footprint "eagle-import:1X01_SMD_3.25X0.85MM_NO_SILK")
      (libsource (lib "eagle-import") (part "M01PTH_SMD_3.25X0.85MM_NO_SILK"))
    )
    (comp (ref "JP1190")
      (value "M01PTH_SMD_3.25X0.85MM_NO_SILK")
      (footprint "eagle-import:1X01_SMD_3.25X0.85MM_NO_SILK")
      (libsource (lib "eagle-import") (part "M01PTH_SMD_3.25X0.85MM_NO_SILK"))
    )
    (comp (ref "JP1191")
      (value "M01PTH_SMD_3.25X0.85MM_NO_SILK")
      (footprint "eagle-import:1X01_SMD_3.25X0.85MM_NO_SILK")
      (libsource (lib "eagle-import") (part "M01PTH_SMD_3.25X0.85MM_NO_SILK"))
    )
    (comp (ref "JP1192")
      (value "M01PTH_SMD_3.25X0.85MM_NO_SILK")
      (footprint "eagle-import:1X01_SMD_3.25X0.85MM_NO_SILK")
      (libsource (lib "eagle-import") (part "M01PTH_SMD_3.25X0.85MM_NO_SILK"))
    )
    (comp (ref "JP1193")
      (value "M01PTH_SMD_3.25X0.85MM_NO_SILK")
      (footprint "eagle-import:1X01_SMD_3.25X0.85MM_NO_SILK")
      (libsource (lib "eagle-import") (part "M01PTH_SMD_3.25X0.85MM_NO_SILK"))
    )
    (comp (ref "JP1194")
      (value "M01PTH_SMD_3.25X0.85MM_NO_SILK")
      (footprint "eagle-import:1X01_SMD_3.25X0.85MM_NO_SILK")
      (libsource (lib "eagle-import") (part "M01PTH_SMD_3.25X0.85MM_NO_SILK"))
    )
    (comp (ref "JP1195")
      (value "M01PTH_SMD_3.25X0.85MM_NO_SILK")
      (footprint "eagle-import:1X01_SMD_3.25X0.85MM_NO_SILK")
      (libsource (lib "eagle-import") (part "M01PTH_SMD_3.25X0.85MM_NO_SILK"))
    )
    (comp (ref "JP1196")
      (value "M01PTH_SMD_3.25X0.85MM_NO_SILK")
      (footprint "eagle-import:1X01_SMD_3.25X0.85MM_NO_SILK")
      (libsource (lib "eagle-import") (part "M01PTH_SMD_3.25X0.85MM_NO_SILK"))
    )
    (comp (ref "JP1197")
      (value "M01PTH_SMD_3.25X0.85MM_NO_SILK")
      (footprint "eagle-import:1X01_SMD_3.25X0.85MM_NO_SILK")
      (libsource (lib "eagle-import") (part "M01PTH_SMD_3.25X0.85MM_NO_SILK"))
    )
    (comp (ref "JP1198")
      (value "M01PTH_SMD_3.25X0.85MM_NO_SILK")
      (footprint "eagle-import:1X01_SMD_3.25X0.85MM_NO_SILK")
      (libsource (lib "eagle-import") (part "M01PTH_SMD_3.25X0.85MM_NO_SILK"))
    )
    (comp (ref "JP1199")
      (value "M01PTH_SMD_3.25X0.85MM_NO_SILK")
      (footprint "eagle-import:1X01_SMD_3.25X0.85MM_NO_SILK")
      (libsource (lib "eagle-import") (part "M01PTH_SMD_3.25X0.85MM_NO_SILK"))
    )
    (comp (ref "JP1200")
      (value "M01PTH_SMD_3.25X0.85MM_NO_SILK")
      (footprint "eagle-import:1X01_SMD_3.25X0.85MM_NO_SILK")
      (libsource (lib "eagle-import") (part "M01PTH_SMD_3.25X0.85MM_NO_SILK"))
    )
    (comp (ref "JP1201")
      (value "M01PTH_SMD_3.25X0.85MM_NO_SILK")
      (footprint "eagle-import:1X01_SMD_3.25X0.85MM_NO_SILK")
      (libsource (lib "eagle-import") (part "M01PTH_SMD_3.25X0.85MM_NO_SILK"))
    )
    (comp (ref "JP1202")
      (value "M01PTH_SMD_3.25X0.85MM_NO_SILK")
      (footprint "eagle-import:1X01_SMD_3.25X0.85MM_NO_SILK")
      (libsource (lib "eagle-import") (part "M01PTH_SMD_3.25X0.85MM_NO_SILK"))
    )
    (comp (ref "JP1203")
      (value "M01PTH_SMD_3.25X0.85MM_NO_SILK")
      (footprint "eagle-import:1X01_SMD_3.25X0.85MM_NO_SILK")
      (libsource (lib "eagle-import") (part "M01PTH_SMD_3.25X0.85MM_NO_SILK"))
    )
    (comp (ref "JP1204")
      (value "M01PTH_SMD_3.25X0.85MM_NO_SILK")
      (footprint "eagle-import:1X01_SMD_3.25X0.85MM_NO_SILK")
      (libsource (lib "eagle-import") (part "M01PTH_SMD_3.25X0.85MM_NO_SILK"))
    )
    (comp (ref "JP1205")
      (value "M01PTH_SMD_3.25X0.85MM_NO_SILK")
      (footprint "eagle-import:1X01_SMD_3.25X0.85MM_NO_SILK")
      (libsource (lib "eagle-import") (part "M01PTH_SMD_3.25X0.85MM_NO_SILK"))
    )
    (comp (ref "JP1206")
      (value "M01PTH_SMD_3.25X0.85MM_NO_SILK")
      (footprint "eagle-import:1X01_SMD_3.25X0.85MM_NO_SILK")
      (libsource (lib "eagle-import") (part "M01PTH_SMD_3.25X0.85MM_NO_SILK"))
    )
    (comp (ref "JP1207")
      (value "M01PTH_SMD_3.25X0.85MM_NO_SILK")
      (footprint "eagle-import:1X01_SMD_3.25X0.85MM_NO_SILK")
      (libsource (lib "eagle-import") (part "M01PTH_SMD_3.25X0.85MM_NO_SILK"))
    )
    (comp (ref "JP1208")
      (value "M01PTH_SMD_3.25X0.85MM_NO_SILK")
      (footprint "eagle-import:1X01_SMD_3.25X0.85MM_NO_SILK")
      (libsource (lib "eagle-import") (part "M01PTH_SMD_3.25X0.85MM_NO_SILK"))
    )
    (comp (ref "JP1209")
      (value "M01PTH_SMD_3.25X0.85MM_NO_SILK")
      (footprint "eagle-import:1X01_SMD_3.25X0.85MM_NO_SILK")
      (libsource (lib "eagle-import") (part "M01PTH_SMD_3.25X0.85MM_NO_SILK"))
    )
    (comp (ref "JP1210")
      (value "M01PTH_SMD_3.25X0.85MM_NO_SILK")
      (footprint "eagle-import:1X01_SMD_3.25X0.85MM_NO_SILK")
      (libsource (lib "eagle-import") (part "M01PTH_SMD_3.25X0.85MM_NO_SILK"))
    )
    (comp (ref "JP1211")
      (value "M01PTH_SMD_3.25X0.85MM_NO_SILK")
      (footprint "eagle-import:1X01_SMD_3.25X0.85MM_NO_SILK")
      (libsource (lib "eagle-import") (part "M01PTH_SMD_3.25X0.85MM_NO_SILK"))
    )
    (comp (ref "JP1212")
      (value "M01PTH_SMD_3.25X0.85MM_NO_SILK")
      (footprint "eagle-import:1X01_SMD_3.25X0.85MM_NO_SILK")
      (libsource (lib "eagle-import") (part "M01PTH_SMD_3.25X0.85MM_NO_SILK"))
    )
    (comp (ref "JP1213")
      (value "M01PTH_SMD_3.25X0.85MM_NO_SILK")
      (footprint "eagle-import:1X01_SMD_3.25X0.85MM_NO_SILK")
      (libsource (lib "eagle-import") (part "M01PTH_SMD_3.25X0.85MM_NO_SILK"))
    )
    (comp (ref "JP1214")
      (value "M01PTH_SMD_3.25X0.85MM_NO_SILK")
      (footprint "eagle-import:1X01_SMD_3.25X0.85MM_NO_SILK")
      (libsource (lib "eagle-import") (part "M01PTH_SMD_3.25X0.85MM_NO_SILK"))
    )
    (comp (ref "JP1215")
      (value "M01PTH_SMD_3.25X0.85MM_NO_SILK")
      (footprint "eagle-import:1X01_SMD_3.25X0.85MM_NO_SILK")
      (libsource (lib "eagle-import") (part "M01PTH_SMD_3.25X0.85MM_NO_SILK"))
    )
    (comp (ref "JP1216")
      (value "M01PTH_SMD_3.25X0.85MM_NO_SILK")
      (footprint "eagle-import:1X01_SMD_3.25X0.85MM_NO_SILK")
      (libsource (lib "eagle-import") (part "M01PTH_SMD_3.25X0.85MM_NO_SILK"))
    )
    (comp (ref "JP1217")
      (value "M01PTH_SMD_3.25X0.85MM_NO_SILK")
      (footprint "eagle-import:1X01_SMD_3.25X0.85MM_NO_SILK")
      (libsource (lib "eagle-import") (part "M01PTH_SMD_3.25X0.85MM_NO_SILK"))
    )
    (comp (ref "JP1218")
      (value "M01PTH_SMD_3.25X0.85MM_NO_SILK")
      (footprint "eagle-import:1X01_SMD_3.25X0.85MM_NO_SILK")
      (libsource (lib "eagle-import") (part "M01PTH_SMD_3.25X0.85MM_NO_SILK"))
    )
    (comp (ref "JP1219")
      (value "M01PTH_SMD_3.25X0.85MM_NO_SILK")
      (footprint "eagle-import:1X01_SMD_3.25X0.85MM_NO_SILK")
      (libsource (lib "eagle-import") (part "M01PTH_SMD_3.25X0.85MM_NO_SILK"))
    )
    (comp (ref "JP1220")
      (value "M01PTH_SMD_3.25X0.85MM_NO_SILK")
      (footprint "eagle-import:1X01_SMD_3.25X0.85MM_NO_SILK")
      (libsource (lib "eagle-import") (part "M01PTH_SMD_3.25X0.85MM_NO_SILK"))
    )
    (comp (ref "JP1221")
      (value "M01PTH_SMD_3.25X0.85MM_NO_SILK")
      (footprint "eagle-import:1X01_SMD_3.25X0.85MM_NO_SILK")
      (libsource (lib "eagle-import") (part "M01PTH_SMD_3.25X0.85MM_NO_SILK"))
    )
    (comp (ref "JP1222")
      (value "M01PTH_SMD_3.25X0.85MM_NO_SILK")
      (footprint "eagle-import:1X01_SMD_3.25X0.85MM_NO_SILK")
      (libsource (lib "eagle-import") (part "M01PTH_SMD_3.25X0.85MM_NO_SILK"))
    )
    (comp (ref "JP1223")
      (value "M01PTH_SMD_3.25X0.85MM_NO_SILK")
      (footprint "eagle-import:1X01_SMD_3.25X0.85MM_NO_SILK")
      (libsource (lib "eagle-import") (part "M01PTH_SMD_3.25X0.85MM_NO_SILK"))
    )
    (comp (ref "JP1224")
      (value "M01PTH_SMD_3.25X0.85MM_NO_SILK")
      (footprint "eagle-import:1X01_SMD_3.25X0.85MM_NO_SILK")
      (libsource (lib "eagle-import") (part "M01PTH_SMD_3.25X0.85MM_NO_SILK"))
    )
    (comp (ref "JP1225")
      (value "M01PTH_SMD_3.25X0.85MM_NO_SILK")
      (footprint "eagle-import:1X01_SMD_3.25X0.85MM_NO_SILK")
      (libsource (lib "eagle-import") (part "M01PTH_SMD_3.25X0.85MM_NO_SILK"))
    )
    (comp (ref "JP1226")
      (value "M01PTH_SMD_3.25X0.85MM_NO_SILK")
      (footprint "eagle-import:1X01_SMD_3.25X0.85MM_NO_SILK")
      (libsource (lib "eagle-import") (part "M01PTH_SMD_3.25X0.85MM_NO_SILK"))
    )
    (comp (ref "JP1227")
      (value "M01PTH_SMD_3.25X0.85MM_NO_SILK")
      (footprint "eagle-import:1X01_SMD_3.25X0.85MM_NO_SILK")
      (libsource (lib "eagle-import") (part "M01PTH_SMD_3.25X0.85MM_NO_SILK"))
    )
    (comp (ref "JP1228")
      (value "M01PTH_SMD_3.25X0.85MM_NO_SILK")
      (footprint "eagle-import:1X01_SMD_3.25X0.85MM_NO_SILK")
      (libsource (lib "eagle-import") (part "M01PTH_SMD_3.25X0.85MM_NO_SILK"))
    )
    (comp (ref "JP1229")
      (value "M01PTH_SMD_3.25X0.85MM_NO_SILK")
      (footprint "eagle-import:1X01_SMD_3.25X0.85MM_NO_SILK")
      (libsource (lib "eagle-import") (part "M01PTH_SMD_3.25X0.85MM_NO_SILK"))
    )
    (comp (ref "JP1230")
      (value "M01PTH_SMD_3.25X0.85MM_NO_SILK")
      (footprint "eagle-import:1X01_SMD_3.25X0.85MM_NO_SILK")
      (libsource (lib "eagle-import") (part "M01PTH_SMD_3.25X0.85MM_NO_SILK"))
    )
    (comp (ref "JP1231")
      (value "M01PTH_SMD_3.25X0.85MM_NO_SILK")
      (footprint "eagle-import:1X01_SMD_3.25X0.85MM_NO_SILK")
      (libsource (lib "eagle-import") (part "M01PTH_SMD_3.25X0.85MM_NO_SILK"))
    )
    (comp (ref "JP1232")
      (value "M01PTH_SMD_3.25X0.85MM_NO_SILK")
      (footprint "eagle-import:1X01_SMD_3.25X0.85MM_NO_SILK")
      (libsource (lib "eagle-import") (part "M01PTH_SMD_3.25X0.85MM_NO_SILK"))
    )
    (comp (ref "JP1233")
      (value "M01PTH_SMD_3.25X0.85MM_NO_SILK")
      (footprint "eagle-import:1X01_SMD_3.25X0.85MM_NO_SILK")
      (libsource (lib "eagle-import") (part "M01PTH_SMD_3.25X0.85MM_NO_SILK"))
    )
    (comp (ref "JP1234")
      (value "M01PTH_SMD_3.25X0.85MM_NO_SILK")
      (footprint "eagle-import:1X01_SMD_3.25X0.85MM_NO_SILK")
      (libsource (lib "eagle-import") (part "M01PTH_SMD_3.25X0.85MM_NO_SILK"))
    )
    (comp (ref "JP1235")
      (value "M01PTH_SMD_3.25X0.85MM_NO_SILK")
      (footprint "eagle-import:1X01_SMD_3.25X0.85MM_NO_SILK")
      (libsource (lib "eagle-import") (part "M01PTH_SMD_3.25X0.85MM_NO_SILK"))
    )
    (comp (ref "JP1236")
      (value "M01PTH_SMD_3.25X0.85MM_NO_SILK")
      (footprint "eagle-import:1X01_SMD_3.25X0.85MM_NO_SILK")
      (libsource (lib "eagle-import") (part "M01PTH_SMD_3.25X0.85MM_NO_SILK"))
    )
    (comp (ref "JP1237")
      (value "M01PTH_SMD_3.25X0.85MM_NO_SILK")
      (footprint "eagle-import:1X01_SMD_3.25X0.85MM_NO_SILK")
      (libsource (lib "eagle-import") (part "M01PTH_SMD_3.25X0.85MM_NO_SILK"))
    )
    (comp (ref "JP1238")
      (value "M01PTH_SMD_3.25X0.85MM_NO_SILK")
      (footprint "eagle-import:1X01_SMD_3.25X0.85MM_NO_SILK")
      (libsource (lib "eagle-import") (part "M01PTH_SMD_3.25X0.85MM_NO_SILK"))
    )
    (comp (ref "JP1239")
      (value "M01PTH_SMD_3.25X0.85MM_NO_SILK")
      (footprint "eagle-import:1X01_SMD_3.25X0.85MM_NO_SILK")
      (libsource (lib "eagle-import") (part "M01PTH_SMD_3.25X0.85MM_NO_SILK"))
    )
    (comp (ref "JP1240")
      (value "M01PTH_SMD_3.25X0.85MM_NO_SILK")
      (footprint "eagle-import:1X01_SMD_3.25X0.85MM_NO_SILK")
      (libsource (lib "eagle-import") (part "M01PTH_SMD_3.25X0.85MM_NO_SILK"))
    )
    (comp (ref "JP1241")
      (value "M01PTH_SMD_3.25X0.85MM_NO_SILK")
      (footprint "eagle-import:1X01_SMD_3.25X0.85MM_NO_SILK")
      (libsource (lib "eagle-import") (part "M01PTH_SMD_3.25X0.85MM_NO_SILK"))
    )
    (comp (ref "JP1242")
      (value "M01PTH_SMD_3.25X0.85MM_NO_SILK")
      (footprint "eagle-import:1X01_SMD_3.25X0.85MM_NO_SILK")
      (libsource (lib "eagle-import") (part "M01PTH_SMD_3.25X0.85MM_NO_SILK"))
    )
    (comp (ref "JP1243")
      (value "M01PTH_SMD_3.25X0.85MM_NO_SILK")
      (footprint "eagle-import:1X01_SMD_3.25X0.85MM_NO_SILK")
      (libsource (lib "eagle-import") (part "M01PTH_SMD_3.25X0.85MM_NO_SILK"))
    )
    (comp (ref "JP1244")
      (value "M01PTH_SMD_3.25X0.85MM_NO_SILK")
      (footprint "eagle-import:1X01_SMD_3.25X0.85MM_NO_SILK")
      (libsource (lib "eagle-import") (part "M01PTH_SMD_3.25X0.85MM_NO_SILK"))
    )
    (comp (ref "JP1245")
      (value "M01PTH_SMD_3.25X0.85MM_NO_SILK")
      (footprint "eagle-import:1X01_SMD_3.25X0.85MM_NO_SILK")
      (libsource (lib "eagle-import") (part "M01PTH_SMD_3.25X0.85MM_NO_SILK"))
    )
    (comp (ref "JP1246")
      (value "M01PTH_SMD_3.25X0.85MM_NO_SILK")
      (footprint "eagle-import:1X01_SMD_3.25X0.85MM_NO_SILK")
      (libsource (lib "eagle-import") (part "M01PTH_SMD_3.25X0.85MM_NO_SILK"))
    )
    (comp (ref "JP1247")
      (value "M01PTH_SMD_3.25X0.85MM_NO_SILK")
      (footprint "eagle-import:1X01_SMD_3.25X0.85MM_NO_SILK")
      (libsource (lib "eagle-import") (part "M01PTH_SMD_3.25X0.85MM_NO_SILK"))
    )
    (comp (ref "JP1248")
      (value "M01PTH_SMD_3.25X0.85MM_NO_SILK")
      (footprint "eagle-import:1X01_SMD_3.25X0.85MM_NO_SILK")
      (libsource (lib "eagle-import") (part "M01PTH_SMD_3.25X0.85MM_NO_SILK"))
    )
    (comp (ref "JP1249")
      (value "M01PTH_SMD_3.25X0.85MM_NO_SILK")
      (footprint "eagle-import:1X01_SMD_3.25X0.85MM_NO_SILK")
      (libsource (lib "eagle-import") (part "M01PTH_SMD_3.25X0.85MM_NO_SILK"))
    )
    (comp (ref "JP1250")
      (value "M01PTH_SMD_3.25X0.85MM_NO_SILK")
      (footprint "eagle-import:1X01_SMD_3.25X0.85MM_NO_SILK")
      (libsource (lib "eagle-import") (part "M01PTH_SMD_3.25X0.85MM_NO_SILK"))
    )
    (comp (ref "JP1251")
      (value "M01PTH_SMD_3.25X0.85MM_NO_SILK")
      (footprint "eagle-import:1X01_SMD_3.25X0.85MM_NO_SILK")
      (libsource (lib "eagle-import") (part "M01PTH_SMD_3.25X0.85MM_NO_SILK"))
    )
    (comp (ref "JP1252")
      (value "M01PTH_SMD_3.25X0.85MM_NO_SILK")
      (footprint "eagle-import:1X01_SMD_3.25X0.85MM_NO_SILK")
      (libsource (lib "eagle-import") (part "M01PTH_SMD_3.25X0.85MM_NO_SILK"))
    )
    (comp (ref "JP1253")
      (value "M01PTH_SMD_3.25X0.85MM_NO_SILK")
      (footprint "eagle-import:1X01_SMD_3.25X0.85MM_NO_SILK")
      (libsource (lib "eagle-import") (part "M01PTH_SMD_3.25X0.85MM_NO_SILK"))
    )
    (comp (ref "JP1254")
      (value "M01PTH_SMD_3.25X0.85MM_NO_SILK")
      (footprint "eagle-import:1X01_SMD_3.25X0.85MM_NO_SILK")
      (libsource (lib "eagle-import") (part "M01PTH_SMD_3.25X0.85MM_NO_SILK"))
    )
    (comp (ref "JP1255")
      (value "M01PTH_SMD_3.25X0.85MM_NO_SILK")
      (footprint "eagle-import:1X01_SMD_3.25X0.85MM_NO_SILK")
      (libsource (lib "eagle-import") (part "M01PTH_SMD_3.25X0.85MM_NO_SILK"))
    )
    (comp (ref "JP1256")
      (value "M01PTH_SMD_3.25X0.85MM_NO_SILK")
      (footprint "eagle-import:1X01_SMD_3.25X0.85MM_NO_SILK")
      (libsource (lib "eagle-import") (part "M01PTH_SMD_3.25X0.85MM_NO_SILK"))
    )
    (comp (ref "JP1257")
      (value "M01PTH_SMD_3.25X0.85MM_NO_SILK")
      (footprint "eagle-import:1X01_SMD_3.25X0.85MM_NO_SILK")
      (libsource (lib "eagle-import") (part "M01PTH_SMD_3.25X0.85MM_NO_SILK"))
    )
    (comp (ref "JP1258")
      (value "M01PTH_SMD_3.25X0.85MM_NO_SILK")
      (footprint "eagle-import:1X01_SMD_3.25X0.85MM_NO_SILK")
      (libsource (lib "eagle-import") (part "M01PTH_SMD_3.25X0.85MM_NO_SILK"))
    )
    (comp (ref "JP1259")
      (value "M01PTH_SMD_3.25X0.85MM_NO_SILK")
      (footprint "eagle-import:1X01_SMD_3.25X0.85MM_NO_SILK")
      (libsource (lib "eagle-import") (part "M01PTH_SMD_3.25X0.85MM_NO_SILK"))
    )
    (comp (ref "JP1260")
      (value "M01PTH_SMD_3.25X0.85MM_NO_SILK")
      (footprint "eagle-import:1X01_SMD_3.25X0.85MM_NO_SILK")
      (libsource (lib "eagle-import") (part "M01PTH_SMD_3.25X0.85MM_NO_SILK"))
    )
    (comp (ref "JP1261")
      (value "M01PTH_SMD_3.25X0.85MM_NO_SILK")
      (footprint "eagle-import:1X01_SMD_3.25X0.85MM_NO_SILK")
      (libsource (lib "eagle-import") (part "M01PTH_SMD_3.25X0.85MM_NO_SILK"))
    )
    (comp (ref "JP1262")
      (value "M01PTH_SMD_3.25X0.85MM_NO_SILK")
      (footprint "eagle-import:1X01_SMD_3.25X0.85MM_NO_SILK")
      (libsource (lib "eagle-import") (part "M01PTH_SMD_3.25X0.85MM_NO_SILK"))
    )
    (comp (ref "JP1263")
      (value "M01PTH_SMD_3.25X0.85MM_NO_SILK")
      (footprint "eagle-import:1X01_SMD_3.25X0.85MM_NO_SILK")
      (libsource (lib "eagle-import") (part "M01PTH_SMD_3.25X0.85MM_NO_SILK"))
    )
    (comp (ref "JP1264")
      (value "M01PTH_SMD_3.25X0.85MM_NO_SILK")
      (footprint "eagle-import:1X01_SMD_3.25X0.85MM_NO_SILK")
      (libsource (lib "eagle-import") (part "M01PTH_SMD_3.25X0.85MM_NO_SILK"))
    )
    (comp (ref "JP1265")
      (value "M01PTH_SMD_3.25X0.85MM_NO_SILK")
      (footprint "eagle-import:1X01_SMD_3.25X0.85MM_NO_SILK")
      (libsource (lib "eagle-import") (part "M01PTH_SMD_3.25X0.85MM_NO_SILK"))
    )
    (comp (ref "JP1266")
      (value "M01PTH_SMD_3.25X0.85MM_NO_SILK")
      (footprint "eagle-import:1X01_SMD_3.25X0.85MM_NO_SILK")
      (libsource (lib "eagle-import") (part "M01PTH_SMD_3.25X0.85MM_NO_SILK"))
    )
    (comp (ref "JP1267")
      (value "M01PTH_SMD_3.25X0.85MM_NO_SILK")
      (footprint "eagle-import:1X01_SMD_3.25X0.85MM_NO_SILK")
      (libsource (lib "eagle-import") (part "M01PTH_SMD_3.25X0.85MM_NO_SILK"))
    )
    (comp (ref "JP1268")
      (value "M01PTH_SMD_3.25X0.85MM_NO_SILK")
      (footprint "eagle-import:1X01_SMD_3.25X0.85MM_NO_SILK")
      (libsource (lib "eagle-import") (part "M01PTH_SMD_3.25X0.85MM_NO_SILK"))
    )
    (comp (ref "JP1269")
      (value "M01PTH_SMD_3.25X0.85MM_NO_SILK")
      (footprint "eagle-import:1X01_SMD_3.25X0.85MM_NO_SILK")
      (libsource (lib "eagle-import") (part "M01PTH_SMD_3.25X0.85MM_NO_SILK"))
    )
    (comp (ref "JP1270")
      (value "M01PTH_SMD_3.25X0.85MM_NO_SILK")
      (footprint "eagle-import:1X01_SMD_3.25X0.85MM_NO_SILK")
      (libsource (lib "eagle-import") (part "M01PTH_SMD_3.25X0.85MM_NO_SILK"))
    )
    (comp (ref "JP1271")
      (value "M01PTH_SMD_3.25X0.85MM_NO_SILK")
      (footprint "eagle-import:1X01_SMD_3.25X0.85MM_NO_SILK")
      (libsource (lib "eagle-import") (part "M01PTH_SMD_3.25X0.85MM_NO_SILK"))
    )
    (comp (ref "JP1272")
      (value "M01PTH_SMD_3.25X0.85MM_NO_SILK")
      (footprint "eagle-import:1X01_SMD_3.25X0.85MM_NO_SILK")
      (libsource (lib "eagle-import") (part "M01PTH_SMD_3.25X0.85MM_NO_SILK"))
    )
    (comp (ref "JP1273")
      (value "M01PTH_SMD_3.25X0.85MM_NO_SILK")
      (footprint "eagle-import:1X01_SMD_3.25X0.85MM_NO_SILK")
      (libsource (lib "eagle-import") (part "M01PTH_SMD_3.25X0.85MM_NO_SILK"))
    )
    (comp (ref "JP1274")
      (value "M01PTH_SMD_3.25X0.85MM_NO_SILK")
      (footprint "eagle-import:1X01_SMD_3.25X0.85MM_NO_SILK")
      (libsource (lib "eagle-import") (part "M01PTH_SMD_3.25X0.85MM_NO_SILK"))
    )
    (comp (ref "JP1275")
      (value "M01PTH_SMD_3.25X0.85MM_NO_SILK")
      (footprint "eagle-import:1X01_SMD_3.25X0.85MM_NO_SILK")
      (libsource (lib "eagle-import") (part "M01PTH_SMD_3.25X0.85MM_NO_SILK"))
    )
    (comp (ref "JP1276")
      (value "M01PTH_SMD_3.25X0.85MM_NO_SILK")
      (footprint "eagle-import:1X01_SMD_3.25X0.85MM_NO_SILK")
      (libsource (lib "eagle-import") (part "M01PTH_SMD_3.25X0.85MM_NO_SILK"))
    )
    (comp (ref "JP1277")
      (value "M01PTH_SMD_3.25X0.85MM_NO_SILK")
      (footprint "eagle-import:1X01_SMD_3.25X0.85MM_NO_SILK")
      (libsource (lib "eagle-import") (part "M01PTH_SMD_3.25X0.85MM_NO_SILK"))
    )
    (comp (ref "JP1278")
      (value "M01PTH_SMD_3.25X0.85MM_NO_SILK")
      (footprint "eagle-import:1X01_SMD_3.25X0.85MM_NO_SILK")
      (libsource (lib "eagle-import") (part "M01PTH_SMD_3.25X0.85MM_NO_SILK"))
    )
    (comp (ref "JP1279")
      (value "M01PTH_SMD_3.25X0.85MM_NO_SILK")
      (footprint "eagle-import:1X01_SMD_3.25X0.85MM_NO_SILK")
      (libsource (lib "eagle-import") (part "M01PTH_SMD_3.25X0.85MM_NO_SILK"))
    )
    (comp (ref "JP1280")
      (value "M01PTH_SMD_3.25X0.85MM_NO_SILK")
      (footprint "eagle-import:1X01_SMD_3.25X0.85MM_NO_SILK")
      (libsource (lib "eagle-import") (part "M01PTH_SMD_3.25X0.85MM_NO_SILK"))
    )
    (comp (ref "JP1281")
      (value "M01PTH_SMD_3.25X0.85MM_NO_SILK")
      (footprint "eagle-import:1X01_SMD_3.25X0.85MM_NO_SILK")
      (libsource (lib "eagle-import") (part "M01PTH_SMD_3.25X0.85MM_NO_SILK"))
    )
    (comp (ref "JP1282")
      (value "M01PTH_SMD_3.25X0.85MM_NO_SILK")
      (footprint "eagle-import:1X01_SMD_3.25X0.85MM_NO_SILK")
      (libsource (lib "eagle-import") (part "M01PTH_SMD_3.25X0.85MM_NO_SILK"))
    )
    (comp (ref "JP1283")
      (value "M01PTH_SMD_3.25X0.85MM_NO_SILK")
      (footprint "eagle-import:1X01_SMD_3.25X0.85MM_NO_SILK")
      (libsource (lib "eagle-import") (part "M01PTH_SMD_3.25X0.85MM_NO_SILK"))
    )
    (comp (ref "JP1284")
      (value "M01PTH_SMD_3.25X0.85MM_NO_SILK")
      (footprint "eagle-import:1X01_SMD_3.25X0.85MM_NO_SILK")
      (libsource (lib "eagle-import") (part "M01PTH_SMD_3.25X0.85MM_NO_SILK"))
    )
    (comp (ref "JP1285")
      (value "M01PTH_SMD_3.25X0.85MM_NO_SILK")
      (footprint "eagle-import:1X01_SMD_3.25X0.85MM_NO_SILK")
      (libsource (lib "eagle-import") (part "M01PTH_SMD_3.25X0.85MM_NO_SILK"))
    )
    (comp (ref "JP1286")
      (value "M01PTH_SMD_3.25X0.85MM_NO_SILK")
      (footprint "eagle-import:1X01_SMD_3.25X0.85MM_NO_SILK")
      (libsource (lib "eagle-import") (part "M01PTH_SMD_3.25X0.85MM_NO_SILK"))
    )
    (comp (ref "JP1287")
      (value "M01PTH_SMD_3.25X0.85MM_NO_SILK")
      (footprint "eagle-import:1X01_SMD_3.25X0.85MM_NO_SILK")
      (libsource (lib "eagle-import") (part "M01PTH_SMD_3.25X0.85MM_NO_SILK"))
    )
    (comp (ref "JP1288")
      (value "M01PTH_SMD_3.25X0.85MM_NO_SILK")
      (footprint "eagle-import:1X01_SMD_3.25X0.85MM_NO_SILK")
      (libsource (lib "eagle-import") (part "M01PTH_SMD_3.25X0.85MM_NO_SILK"))
    )
    (comp (ref "JP1289")
      (value "M01PTH_SMD_3.25X0.85MM_NO_SILK")
      (footprint "eagle-import:1X01_SMD_3.25X0.85MM_NO_SILK")
      (libsource (lib "eagle-import") (part "M01PTH_SMD_3.25X0.85MM_NO_SILK"))
    )
    (comp (ref "JP1290")
      (value "M01PTH_SMD_3.25X0.85MM_NO_SILK")
      (footprint "eagle-import:1X01_SMD_3.25X0.85MM_NO_SILK")
      (libsource (lib "eagle-import") (part "M01PTH_SMD_3.25X0.85MM_NO_SILK"))
    )
    (comp (ref "JP1291")
      (value "M01PTH_SMD_3.25X0.85MM_NO_SILK")
      (footprint "eagle-import:1X01_SMD_3.25X0.85MM_NO_SILK")
      (libsource (lib "eagle-import") (part "M01PTH_SMD_3.25X0.85MM_NO_SILK"))
    )
    (comp (ref "JP1292")
      (value "M01PTH_SMD_3.25X0.85MM_NO_SILK")
      (footprint "eagle-import:1X01_SMD_3.25X0.85MM_NO_SILK")
      (libsource (lib "eagle-import") (part "M01PTH_SMD_3.25X0.85MM_NO_SILK"))
    )
    (comp (ref "JP1293")
      (value "M01PTH_SMD_3.25X0.85MM_NO_SILK")
      (footprint "eagle-import:1X01_SMD_3.25X0.85MM_NO_SILK")
      (libsource (lib "eagle-import") (part "M01PTH_SMD_3.25X0.85MM_NO_SILK"))
    )
    (comp (ref "JP1294")
      (value "M01PTH_SMD_3.25X0.85MM_NO_SILK")
      (footprint "eagle-import:1X01_SMD_3.25X0.85MM_NO_SILK")
      (libsource (lib "eagle-import") (part "M01PTH_SMD_3.25X0.85MM_NO_SILK"))
    )
    (comp (ref "JP1295")
      (value "M01PTH_SMD_3.25X0.85MM_NO_SILK")
      (footprint "eagle-import:1X01_SMD_3.25X0.85MM_NO_SILK")
      (libsource (lib "eagle-import") (part "M01PTH_SMD_3.25X0.85MM_NO_SILK"))
    )
    (comp (ref "JP1296")
      (value "M01PTH_SMD_3.25X0.85MM_NO_SILK")
      (footprint "eagle-import:1X01_SMD_3.25X0.85MM_NO_SILK")
      (libsource (lib "eagle-import") (part "M01PTH_SMD_3.25X0.85MM_NO_SILK"))
    )
    (comp (ref "JP1297")
      (value "M01PTH_SMD_3.25X0.85MM_NO_SILK")
      (footprint "eagle-import:1X01_SMD_3.25X0.85MM_NO_SILK")
      (libsource (lib "eagle-import") (part "M01PTH_SMD_3.25X0.85MM_NO_SILK"))
    )
    (comp (ref "JP1298")
      (value "M01PTH_SMD_3.25X0.85MM_NO_SILK")
      (footprint "eagle-import:1X01_SMD_3.25X0.85MM_NO_SILK")
      (libsource (lib "eagle-import") (part "M01PTH_SMD_3.25X0.85MM_NO_SILK"))
    )
    (comp (ref "JP1299")
      (value "M01PTH_SMD_3.25X0.85MM_NO_SILK")
      (footprint "eagle-import:1X01_SMD_3.25X0.85MM_NO_SILK")
      (libsource (lib "eagle-import") (part "M01PTH_SMD_3.25X0.85MM_NO_SILK"))
    )
    (comp (ref "JP1300")
      (value "M01PTH_SMD_3.25X0.85MM_NO_SILK")
      (footprint "eagle-import:1X01_SMD_3.25X0.85MM_NO_SILK")
      (libsource (lib "eagle-import") (part "M01PTH_SMD_3.25X0.85MM_NO_SILK"))
    )
    (comp (ref "JP1301")
      (value "M01PTH_SMD_3.25X0.85MM_NO_SILK")
      (footprint "eagle-import:1X01_SMD_3.25X0.85MM_NO_SILK")
      (libsource (lib "eagle-import") (part "M01PTH_SMD_3.25X0.85MM_NO_SILK"))
    )
    (comp (ref "JP1302")
      (value "M01PTH_SMD_3.25X0.85MM_NO_SILK")
      (footprint "eagle-import:1X01_SMD_3.25X0.85MM_NO_SILK")
      (libsource (lib "eagle-import") (part "M01PTH_SMD_3.25X0.85MM_NO_SILK"))
    )
    (comp (ref "JP1303")
      (value "M01PTH_SMD_3.25X0.85MM_NO_SILK")
      (footprint "eagle-import:1X01_SMD_3.25X0.85MM_NO_SILK")
      (libsource (lib "eagle-import") (part "M01PTH_SMD_3.25X0.85MM_NO_SILK"))
    )
    (comp (ref "JP1304")
      (value "M01PTH_SMD_3.25X0.85MM_NO_SILK")
      (footprint "eagle-import:1X01_SMD_3.25X0.85MM_NO_SILK")
      (libsource (lib "eagle-import") (part "M01PTH_SMD_3.25X0.85MM_NO_SILK"))
    )
    (comp (ref "JP1305")
      (value "M01PTH_SMD_3.25X0.85MM_NO_SILK")
      (footprint "eagle-import:1X01_SMD_3.25X0.85MM_NO_SILK")
      (libsource (lib "eagle-import") (part "M01PTH_SMD_3.25X0.85MM_NO_SILK"))
    )
    (comp (ref "JP1306")
      (value "M01PTH_SMD_3.25X0.85MM_NO_SILK")
      (footprint "eagle-import:1X01_SMD_3.25X0.85MM_NO_SILK")
      (libsource (lib "eagle-import") (part "M01PTH_SMD_3.25X0.85MM_NO_SILK"))
    )
    (comp (ref "JP1307")
      (value "M01PTH_SMD_3.25X0.85MM_NO_SILK")
      (footprint "eagle-import:1X01_SMD_3.25X0.85MM_NO_SILK")
      (libsource (lib "eagle-import") (part "M01PTH_SMD_3.25X0.85MM_NO_SILK"))
    )
    (comp (ref "JP1308")
      (value "M01PTH_SMD_3.25X0.85MM_NO_SILK")
      (footprint "eagle-import:1X01_SMD_3.25X0.85MM_NO_SILK")
      (libsource (lib "eagle-import") (part "M01PTH_SMD_3.25X0.85MM_NO_SILK"))
    )
    (comp (ref "JP1309")
      (value "M01PTH_SMD_3.25X0.85MM_NO_SILK")
      (footprint "eagle-import:1X01_SMD_3.25X0.85MM_NO_SILK")
      (libsource (lib "eagle-import") (part "M01PTH_SMD_3.25X0.85MM_NO_SILK"))
    )
    (comp (ref "JP1310")
      (value "M01PTH_SMD_3.25X0.85MM_NO_SILK")
      (footprint "eagle-import:1X01_SMD_3.25X0.85MM_NO_SILK")
      (libsource (lib "eagle-import") (part "M01PTH_SMD_3.25X0.85MM_NO_SILK"))
    )
    (comp (ref "JP1311")
      (value "M01PTH_SMD_3.25X0.85MM_NO_SILK")
      (footprint "eagle-import:1X01_SMD_3.25X0.85MM_NO_SILK")
      (libsource (lib "eagle-import") (part "M01PTH_SMD_3.25X0.85MM_NO_SILK"))
    )
    (comp (ref "JP1312")
      (value "M01PTH_SMD_3.25X0.85MM_NO_SILK")
      (footprint "eagle-import:1X01_SMD_3.25X0.85MM_NO_SILK")
      (libsource (lib "eagle-import") (part "M01PTH_SMD_3.25X0.85MM_NO_SILK"))
    )
    (comp (ref "JP1313")
      (value "M01PTH_SMD_3.25X0.85MM_NO_SILK")
      (footprint "eagle-import:1X01_SMD_3.25X0.85MM_NO_SILK")
      (libsource (lib "eagle-import") (part "M01PTH_SMD_3.25X0.85MM_NO_SILK"))
    )
    (comp (ref "JP1314")
      (value "M01PTH_SMD_3.25X0.85MM_NO_SILK")
      (footprint "eagle-import:1X01_SMD_3.25X0.85MM_NO_SILK")
      (libsource (lib "eagle-import") (part "M01PTH_SMD_3.25X0.85MM_NO_SILK"))
    )
    (comp (ref "JP1315")
      (value "M01PTH_SMD_3.25X0.85MM_NO_SILK")
      (footprint "eagle-import:1X01_SMD_3.25X0.85MM_NO_SILK")
      (libsource (lib "eagle-import") (part "M01PTH_SMD_3.25X0.85MM_NO_SILK"))
    )
    (comp (ref "JP1316")
      (value "M01PTH_SMD_3.25X0.85MM_NO_SILK")
      (footprint "eagle-import:1X01_SMD_3.25X0.85MM_NO_SILK")
      (libsource (lib "eagle-import") (part "M01PTH_SMD_3.25X0.85MM_NO_SILK"))
    )
    (comp (ref "JP1317")
      (value "M01PTH_SMD_3.25X0.85MM_NO_SILK")
      (footprint "eagle-import:1X01_SMD_3.25X0.85MM_NO_SILK")
      (libsource (lib "eagle-import") (part "M01PTH_SMD_3.25X0.85MM_NO_SILK"))
    )
    (comp (ref "JP1318")
      (value "M01PTH_SMD_3.25X0.85MM_NO_SILK")
      (footprint "eagle-import:1X01_SMD_3.25X0.85MM_NO_SILK")
      (libsource (lib "eagle-import") (part "M01PTH_SMD_3.25X0.85MM_NO_SILK"))
    )
    (comp (ref "JP1319")
      (value "M01PTH_SMD_3.25X0.85MM_NO_SILK")
      (footprint "eagle-import:1X01_SMD_3.25X0.85MM_NO_SILK")
      (libsource (lib "eagle-import") (part "M01PTH_SMD_3.25X0.85MM_NO_SILK"))
    )
    (comp (ref "JP1320")
      (value "M01PTH_SMD_3.25X0.85MM_NO_SILK")
      (footprint "eagle-import:1X01_SMD_3.25X0.85MM_NO_SILK")
      (libsource (lib "eagle-import") (part "M01PTH_SMD_3.25X0.85MM_NO_SILK"))
    )
    (comp (ref "JP1321")
      (value "M01PTH_SMD_3.25X0.85MM_NO_SILK")
      (footprint "eagle-import:1X01_SMD_3.25X0.85MM_NO_SILK")
      (libsource (lib "eagle-import") (part "M01PTH_SMD_3.25X0.85MM_NO_SILK"))
    )
    (comp (ref "JP1322")
      (value "M01PTH_SMD_3.25X0.85MM_NO_SILK")
      (footprint "eagle-import:1X01_SMD_3.25X0.85MM_NO_SILK")
      (libsource (lib "eagle-import") (part "M01PTH_SMD_3.25X0.85MM_NO_SILK"))
    )
    (comp (ref "JP1323")
      (value "M01PTH_SMD_3.25X0.85MM_NO_SILK")
      (footprint "eagle-import:1X01_SMD_3.25X0.85MM_NO_SILK")
      (libsource (lib "eagle-import") (part "M01PTH_SMD_3.25X0.85MM_NO_SILK"))
    )
    (comp (ref "JP1324")
      (value "M01PTH_SMD_3.25X0.85MM_NO_SILK")
      (footprint "eagle-import:1X01_SMD_3.25X0.85MM_NO_SILK")
      (libsource (lib "eagle-import") (part "M01PTH_SMD_3.25X0.85MM_NO_SILK"))
    )
    (comp (ref "JP1325")
      (value "M01PTH_SMD_3.25X0.85MM_NO_SILK")
      (footprint "eagle-import:1X01_SMD_3.25X0.85MM_NO_SILK")
      (libsource (lib "eagle-import") (part "M01PTH_SMD_3.25X0.85MM_NO_SILK"))
    )
    (comp (ref "JP1326")
      (value "M01PTH_SMD_3.25X0.85MM_NO_SILK")
      (footprint "eagle-import:1X01_SMD_3.25X0.85MM_NO_SILK")
      (libsource (lib "eagle-import") (part "M01PTH_SMD_3.25X0.85MM_NO_SILK"))
    )
    (comp (ref "JP1327")
      (value "M01PTH_SMD_3.25X0.85MM_NO_SILK")
      (footprint "eagle-import:1X01_SMD_3.25X0.85MM_NO_SILK")
      (libsource (lib "eagle-import") (part "M01PTH_SMD_3.25X0.85MM_NO_SILK"))
    )
    (comp (ref "JP1328")
      (value "M01PTH_SMD_3.25X0.85MM_NO_SILK")
      (footprint "eagle-import:1X01_SMD_3.25X0.85MM_NO_SILK")
      (libsource (lib "eagle-import") (part "M01PTH_SMD_3.25X0.85MM_NO_SILK"))
    )
    (comp (ref "JP1329")
      (value "M01PTH_SMD_3.25X0.85MM_NO_SILK")
      (footprint "eagle-import:1X01_SMD_3.25X0.85MM_NO_SILK")
      (libsource (lib "eagle-import") (part "M01PTH_SMD_3.25X0.85MM_NO_SILK"))
    )
    (comp (ref "JP1330")
      (value "M01PTH_SMD_3.25X0.85MM_NO_SILK")
      (footprint "eagle-import:1X01_SMD_3.25X0.85MM_NO_SILK")
      (libsource (lib "eagle-import") (part "M01PTH_SMD_3.25X0.85MM_NO_SILK"))
    )
    (comp (ref "JP1331")
      (value "M01PTH_SMD_3.25X0.85MM_NO_SILK")
      (footprint "eagle-import:1X01_SMD_3.25X0.85MM_NO_SILK")
      (libsource (lib "eagle-import") (part "M01PTH_SMD_3.25X0.85MM_NO_SILK"))
    )
    (comp (ref "JP1332")
      (value "M01PTH_SMD_3.25X0.85MM_NO_SILK")
      (footprint "eagle-import:1X01_SMD_3.25X0.85MM_NO_SILK")
      (libsource (lib "eagle-import") (part "M01PTH_SMD_3.25X0.85MM_NO_SILK"))
    )
    (comp (ref "JP1333")
      (value "M01PTH_SMD_3.25X0.85MM_NO_SILK")
      (footprint "eagle-import:1X01_SMD_3.25X0.85MM_NO_SILK")
      (libsource (lib "eagle-import") (part "M01PTH_SMD_3.25X0.85MM_NO_SILK"))
    )
    (comp (ref "JP1334")
      (value "M01PTH_SMD_3.25X0.85MM_NO_SILK")
      (footprint "eagle-import:1X01_SMD_3.25X0.85MM_NO_SILK")
      (libsource (lib "eagle-import") (part "M01PTH_SMD_3.25X0.85MM_NO_SILK"))
    )
    (comp (ref "JP1335")
      (value "M01PTH_SMD_3.25X0.85MM_NO_SILK")
      (footprint "eagle-import:1X01_SMD_3.25X0.85MM_NO_SILK")
      (libsource (lib "eagle-import") (part "M01PTH_SMD_3.25X0.85MM_NO_SILK"))
    )
    (comp (ref "JP1336")
      (value "M01PTH_SMD_3.25X0.85MM_NO_SILK")
      (footprint "eagle-import:1X01_SMD_3.25X0.85MM_NO_SILK")
      (libsource (lib "eagle-import") (part "M01PTH_SMD_3.25X0.85MM_NO_SILK"))
    )
    (comp (ref "JP1337")
      (value "M01PTH_SMD_3.25X0.85MM_NO_SILK")
      (footprint "eagle-import:1X01_SMD_3.25X0.85MM_NO_SILK")
      (libsource (lib "eagle-import") (part "M01PTH_SMD_3.25X0.85MM_NO_SILK"))
    )
    (comp (ref "JP1338")
      (value "M01PTH_SMD_3.25X0.85MM_NO_SILK")
      (footprint "eagle-import:1X01_SMD_3.25X0.85MM_NO_SILK")
      (libsource (lib "eagle-import") (part "M01PTH_SMD_3.25X0.85MM_NO_SILK"))
    )
    (comp (ref "JP1339")
      (value "M01PTH_SMD_3.25X0.85MM_NO_SILK")
      (footprint "eagle-import:1X01_SMD_3.25X0.85MM_NO_SILK")
      (libsource (lib "eagle-import") (part "M01PTH_SMD_3.25X0.85MM_NO_SILK"))
    )
    (comp (ref "JP1340")
      (value "M01PTH_SMD_3.25X0.85MM_NO_SILK")
      (footprint "eagle-import:1X01_SMD_3.25X0.85MM_NO_SILK")
      (libsource (lib "eagle-import") (part "M01PTH_SMD_3.25X0.85MM_NO_SILK"))
    )
    (comp (ref "JP1341")
      (value "M01PTH_SMD_3.25X0.85MM_NO_SILK")
      (footprint "eagle-import:1X01_SMD_3.25X0.85MM_NO_SILK")
      (libsource (lib "eagle-import") (part "M01PTH_SMD_3.25X0.85MM_NO_SILK"))
    )
    (comp (ref "JP1342")
      (value "M01PTH_SMD_3.25X0.85MM_NO_SILK")
      (footprint "eagle-import:1X01_SMD_3.25X0.85MM_NO_SILK")
      (libsource (lib "eagle-import") (part "M01PTH_SMD_3.25X0.85MM_NO_SILK"))
    )
    (comp (ref "JP1343")
      (value "M01PTH_SMD_3.25X0.85MM_NO_SILK")
      (footprint "eagle-import:1X01_SMD_3.25X0.85MM_NO_SILK")
      (libsource (lib "eagle-import") (part "M01PTH_SMD_3.25X0.85MM_NO_SILK"))
    )
    (comp (ref "JP1344")
      (value "M01PTH_SMD_3.25X0.85MM_NO_SILK")
      (footprint "eagle-import:1X01_SMD_3.25X0.85MM_NO_SILK")
      (libsource (lib "eagle-import") (part "M01PTH_SMD_3.25X0.85MM_NO_SILK"))
    )
    (comp (ref "JP1345")
      (value "M01PTH_SMD_3.25X0.85MM_NO_SILK")
      (footprint "eagle-import:1X01_SMD_3.25X0.85MM_NO_SILK")
      (libsource (lib "eagle-import") (part "M01PTH_SMD_3.25X0.85MM_NO_SILK"))
    )
    (comp (ref "JP1346")
      (value "M01PTH_SMD_3.25X0.85MM_NO_SILK")
      (footprint "eagle-import:1X01_SMD_3.25X0.85MM_NO_SILK")
      (libsource (lib "eagle-import") (part "M01PTH_SMD_3.25X0.85MM_NO_SILK"))
    )
    (comp (ref "JP1347")
      (value "M01PTH_SMD_3.25X0.85MM_NO_SILK")
      (footprint "eagle-import:1X01_SMD_3.25X0.85MM_NO_SILK")
      (libsource (lib "eagle-import") (part "M01PTH_SMD_3.25X0.85MM_NO_SILK"))
    )
    (comp (ref "JP1348")
      (value "M01PTH_SMD_3.25X0.85MM_NO_SILK")
      (footprint "eagle-import:1X01_SMD_3.25X0.85MM_NO_SILK")
      (libsource (lib "eagle-import") (part "M01PTH_SMD_3.25X0.85MM_NO_SILK"))
    )
    (comp (ref "JP1349")
      (value "M01PTH_SMD_3.25X0.85MM_NO_SILK")
      (footprint "eagle-import:1X01_SMD_3.25X0.85MM_NO_SILK")
      (libsource (lib "eagle-import") (part "M01PTH_SMD_3.25X0.85MM_NO_SILK"))
    )
    (comp (ref "JP1350")
      (value "M01PTH_SMD_3.25X0.85MM_NO_SILK")
      (footprint "eagle-import:1X01_SMD_3.25X0.85MM_NO_SILK")
      (libsource (lib "eagle-import") (part "M01PTH_SMD_3.25X0.85MM_NO_SILK"))
    )
    (comp (ref "JP1351")
      (value "M01PTH_SMD_3.25X0.85MM_NO_SILK")
      (footprint "eagle-import:1X01_SMD_3.25X0.85MM_NO_SILK")
      (libsource (lib "eagle-import") (part "M01PTH_SMD_3.25X0.85MM_NO_SILK"))
    )
    (comp (ref "JP1352")
      (value "M01PTH_SMD_3.25X0.85MM_NO_SILK")
      (footprint "eagle-import:1X01_SMD_3.25X0.85MM_NO_SILK")
      (libsource (lib "eagle-import") (part "M01PTH_SMD_3.25X0.85MM_NO_SILK"))
    )
    (comp (ref "JP1353")
      (value "M01PTH_SMD_3.25X0.85MM_NO_SILK")
      (footprint "eagle-import:1X01_SMD_3.25X0.85MM_NO_SILK")
      (libsource (lib "eagle-import") (part "M01PTH_SMD_3.25X0.85MM_NO_SILK"))
    )
    (comp (ref "JP1354")
      (value "M01PTH_SMD_3.25X0.85MM_NO_SILK")
      (footprint "eagle-import:1X01_SMD_3.25X0.85MM_NO_SILK")
      (libsource (lib "eagle-import") (part "M01PTH_SMD_3.25X0.85MM_NO_SILK"))
    )
    (comp (ref "JP1355")
      (value "M01PTH_SMD_3.25X0.85MM_NO_SILK")
      (footprint "eagle-import:1X01_SMD_3.25X0.85MM_NO_SILK")
      (libsource (lib "eagle-import") (part "M01PTH_SMD_3.25X0.85MM_NO_SILK"))
    )
    (comp (ref "JP1356")
      (value "M01PTH_SMD_3.25X0.85MM_NO_SILK")
      (footprint "eagle-import:1X01_SMD_3.25X0.85MM_NO_SILK")
      (libsource (lib "eagle-import") (part "M01PTH_SMD_3.25X0.85MM_NO_SILK"))
    )
    (comp (ref "JP1357")
      (value "M01PTH_SMD_3.25X0.85MM_NO_SILK")
      (footprint "eagle-import:1X01_SMD_3.25X0.85MM_NO_SILK")
      (libsource (lib "eagle-import") (part "M01PTH_SMD_3.25X0.85MM_NO_SILK"))
    )
    (comp (ref "JP1358")
      (value "M01PTH_SMD_3.25X0.85MM_NO_SILK")
      (footprint "eagle-import:1X01_SMD_3.25X0.85MM_NO_SILK")
      (libsource (lib "eagle-import") (part "M01PTH_SMD_3.25X0.85MM_NO_SILK"))
    )
    (comp (ref "JP1359")
      (value "M01PTH_SMD_3.25X0.85MM_NO_SILK")
      (footprint "eagle-import:1X01_SMD_3.25X0.85MM_NO_SILK")
      (libsource (lib "eagle-import") (part "M01PTH_SMD_3.25X0.85MM_NO_SILK"))
    )
    (comp (ref "JP1360")
      (value "M01PTH_SMD_3.25X0.85MM_NO_SILK")
      (footprint "eagle-import:1X01_SMD_3.25X0.85MM_NO_SILK")
      (libsource (lib "eagle-import") (part "M01PTH_SMD_3.25X0.85MM_NO_SILK"))
    )
    (comp (ref "JP1361")
      (value "M01PTH_SMD_3.25X0.85MM_NO_SILK")
      (footprint "eagle-import:1X01_SMD_3.25X0.85MM_NO_SILK")
      (libsource (lib "eagle-import") (part "M01PTH_SMD_3.25X0.85MM_NO_SILK"))
    )
    (comp (ref "JP1362")
      (value "M01PTH_SMD_3.25X0.85MM_NO_SILK")
      (footprint "eagle-import:1X01_SMD_3.25X0.85MM_NO_SILK")
      (libsource (lib "eagle-import") (part "M01PTH_SMD_3.25X0.85MM_NO_SILK"))
    )
    (comp (ref "JP1363")
      (value "M01PTH_SMD_3.25X0.85MM_NO_SILK")
      (footprint "eagle-import:1X01_SMD_3.25X0.85MM_NO_SILK")
      (libsource (lib "eagle-import") (part "M01PTH_SMD_3.25X0.85MM_NO_SILK"))
    )
    (comp (ref "JP1364")
      (value "M01PTH_SMD_3.25X0.85MM_NO_SILK")
      (footprint "eagle-import:1X01_SMD_3.25X0.85MM_NO_SILK")
      (libsource (lib "eagle-import") (part "M01PTH_SMD_3.25X0.85MM_NO_SILK"))
    )
    (comp (ref "JP1365")
      (value "M01PTH_SMD_3.25X0.85MM_NO_SILK")
      (footprint "eagle-import:1X01_SMD_3.25X0.85MM_NO_SILK")
      (libsource (lib "eagle-import") (part "M01PTH_SMD_3.25X0.85MM_NO_SILK"))
    )
    (comp (ref "JP1366")
      (value "M01PTH_SMD_3.25X0.85MM_NO_SILK")
      (footprint "eagle-import:1X01_SMD_3.25X0.85MM_NO_SILK")
      (libsource (lib "eagle-import") (part "M01PTH_SMD_3.25X0.85MM_NO_SILK"))
    )
    (comp (ref "JP1367")
      (value "M01PTH_SMD_3.25X0.85MM_NO_SILK")
      (footprint "eagle-import:1X01_SMD_3.25X0.85MM_NO_SILK")
      (libsource (lib "eagle-import") (part "M01PTH_SMD_3.25X0.85MM_NO_SILK"))
    )
    (comp (ref "JP1368")
      (value "M01PTH_SMD_3.25X0.85MM_NO_SILK")
      (footprint "eagle-import:1X01_SMD_3.25X0.85MM_NO_SILK")
      (libsource (lib "eagle-import") (part "M01PTH_SMD_3.25X0.85MM_NO_SILK"))
    )
    (comp (ref "JP1369")
      (value "M01PTH_SMD_3.25X0.85MM_NO_SILK")
      (footprint "eagle-import:1X01_SMD_3.25X0.85MM_NO_SILK")
      (libsource (lib "eagle-import") (part "M01PTH_SMD_3.25X0.85MM_NO_SILK"))
    )
    (comp (ref "JP1370")
      (value "M01PTH_SMD_3.25X0.85MM_NO_SILK")
      (footprint "eagle-import:1X01_SMD_3.25X0.85MM_NO_SILK")
      (libsource (lib "eagle-import") (part "M01PTH_SMD_3.25X0.85MM_NO_SILK"))
    )
    (comp (ref "JP1371")
      (value "M01PTH_SMD_3.25X0.85MM_NO_SILK")
      (footprint "eagle-import:1X01_SMD_3.25X0.85MM_NO_SILK")
      (libsource (lib "eagle-import") (part "M01PTH_SMD_3.25X0.85MM_NO_SILK"))
    )
    (comp (ref "JP1372")
      (value "M01PTH_SMD_3.25X0.85MM_NO_SILK")
      (footprint "eagle-import:1X01_SMD_3.25X0.85MM_NO_SILK")
      (libsource (lib "eagle-import") (part "M01PTH_SMD_3.25X0.85MM_NO_SILK"))
    )
    (comp (ref "JP1373")
      (value "M01PTH_SMD_3.25X0.85MM_NO_SILK")
      (footprint "eagle-import:1X01_SMD_3.25X0.85MM_NO_SILK")
      (libsource (lib "eagle-import") (part "M01PTH_SMD_3.25X0.85MM_NO_SILK"))
    )
    (comp (ref "JP1374")
      (value "M01PTH_SMD_3.25X0.85MM_NO_SILK")
      (footprint "eagle-import:1X01_SMD_3.25X0.85MM_NO_SILK")
      (libsource (lib "eagle-import") (part "M01PTH_SMD_3.25X0.85MM_NO_SILK"))
    )
    (comp (ref "JP1375")
      (value "M01PTH_SMD_3.25X0.85MM_NO_SILK")
      (footprint "eagle-import:1X01_SMD_3.25X0.85MM_NO_SILK")
      (libsource (lib "eagle-import") (part "M01PTH_SMD_3.25X0.85MM_NO_SILK"))
    )
    (comp (ref "JP1376")
      (value "M01PTH_SMD_3.25X0.85MM_NO_SILK")
      (footprint "eagle-import:1X01_SMD_3.25X0.85MM_NO_SILK")
      (libsource (lib "eagle-import") (part "M01PTH_SMD_3.25X0.85MM_NO_SILK"))
    )
    (comp (ref "JP1377")
      (value "M01PTH_SMD_3.25X0.85MM_NO_SILK")
      (footprint "eagle-import:1X01_SMD_3.25X0.85MM_NO_SILK")
      (libsource (lib "eagle-import") (part "M01PTH_SMD_3.25X0.85MM_NO_SILK"))
    )
    (comp (ref "JP1378")
      (value "M01PTH_SMD_3.25X0.85MM_NO_SILK")
      (footprint "eagle-import:1X01_SMD_3.25X0.85MM_NO_SILK")
      (libsource (lib "eagle-import") (part "M01PTH_SMD_3.25X0.85MM_NO_SILK"))
    )
    (comp (ref "JP1379")
      (value "M01PTH_SMD_3.25X0.85MM_NO_SILK")
      (footprint "eagle-import:1X01_SMD_3.25X0.85MM_NO_SILK")
      (libsource (lib "eagle-import") (part "M01PTH_SMD_3.25X0.85MM_NO_SILK"))
    )
    (comp (ref "JP1380")
      (value "M01PTH_SMD_3.25X0.85MM_NO_SILK")
      (footprint "eagle-import:1X01_SMD_3.25X0.85MM_NO_SILK")
      (libsource (lib "eagle-import") (part "M01PTH_SMD_3.25X0.85MM_NO_SILK"))
    )
    (comp (ref "JP1381")
      (value "M01PTH_SMD_3.25X0.85MM_NO_SILK")
      (footprint "eagle-import:1X01_SMD_3.25X0.85MM_NO_SILK")
      (libsource (lib "eagle-import") (part "M01PTH_SMD_3.25X0.85MM_NO_SILK"))
    )
    (comp (ref "JP1382")
      (value "M01PTH_SMD_3.25X0.85MM_NO_SILK")
      (footprint "eagle-import:1X01_SMD_3.25X0.85MM_NO_SILK")
      (libsource (lib "eagle-import") (part "M01PTH_SMD_3.25X0.85MM_NO_SILK"))
    )
    (comp (ref "JP1383")
      (value "M01PTH_SMD_3.25X0.85MM_NO_SILK")
      (footprint "eagle-import:1X01_SMD_3.25X0.85MM_NO_SILK")
      (libsource (lib "eagle-import") (part "M01PTH_SMD_3.25X0.85MM_NO_SILK"))
    )
    (comp (ref "JP1384")
      (value "M01PTH_SMD_3.25X0.85MM_NO_SILK")
      (footprint "eagle-import:1X01_SMD_3.25X0.85MM_NO_SILK")
      (libsource (lib "eagle-import") (part "M01PTH_SMD_3.25X0.85MM_NO_SILK"))
    )
    (comp (ref "JP1385")
      (value "M01PTH_SMD_3.25X0.85MM_NO_SILK")
      (footprint "eagle-import:1X01_SMD_3.25X0.85MM_NO_SILK")
      (libsource (lib "eagle-import") (part "M01PTH_SMD_3.25X0.85MM_NO_SILK"))
    )
    (comp (ref "JP1386")
      (value "M01PTH_SMD_3.25X0.85MM_NO_SILK")
      (footprint "eagle-import:1X01_SMD_3.25X0.85MM_NO_SILK")
      (libsource (lib "eagle-import") (part "M01PTH_SMD_3.25X0.85MM_NO_SILK"))
    )
    (comp (ref "JP1387")
      (value "M01PTH_SMD_3.25X0.85MM_NO_SILK")
      (footprint "eagle-import:1X01_SMD_3.25X0.85MM_NO_SILK")
      (libsource (lib "eagle-import") (part "M01PTH_SMD_3.25X0.85MM_NO_SILK"))
    )
    (comp (ref "JP1388")
      (value "M01PTH_SMD_3.25X0.85MM_NO_SILK")
      (footprint "eagle-import:1X01_SMD_3.25X0.85MM_NO_SILK")
      (libsource (lib "eagle-import") (part "M01PTH_SMD_3.25X0.85MM_NO_SILK"))
    )
    (comp (ref "JP1389")
      (value "M01PTH_SMD_3.25X0.85MM_NO_SILK")
      (footprint "eagle-import:1X01_SMD_3.25X0.85MM_NO_SILK")
      (libsource (lib "eagle-import") (part "M01PTH_SMD_3.25X0.85MM_NO_SILK"))
    )
    (comp (ref "JP1390")
      (value "M01PTH_SMD_3.25X0.85MM_NO_SILK")
      (footprint "eagle-import:1X01_SMD_3.25X0.85MM_NO_SILK")
      (libsource (lib "eagle-import") (part "M01PTH_SMD_3.25X0.85MM_NO_SILK"))
    )
    (comp (ref "JP1391")
      (value "M01PTH_SMD_3.25X0.85MM_NO_SILK")
      (footprint "eagle-import:1X01_SMD_3.25X0.85MM_NO_SILK")
      (libsource (lib "eagle-import") (part "M01PTH_SMD_3.25X0.85MM_NO_SILK"))
    )
    (comp (ref "JP1392")
      (value "M01PTH_SMD_3.25X0.85MM_NO_SILK")
      (footprint "eagle-import:1X01_SMD_3.25X0.85MM_NO_SILK")
      (libsource (lib "eagle-import") (part "M01PTH_SMD_3.25X0.85MM_NO_SILK"))
    )
    (comp (ref "JP1393")
      (value "M01PTH_SMD_3.25X0.85MM_NO_SILK")
      (footprint "eagle-import:1X01_SMD_3.25X0.85MM_NO_SILK")
      (libsource (lib "eagle-import") (part "M01PTH_SMD_3.25X0.85MM_NO_SILK"))
    )
    (comp (ref "JP1394")
      (value "M01PTH_SMD_3.25X0.85MM_NO_SILK")
      (footprint "eagle-import:1X01_SMD_3.25X0.85MM_NO_SILK")
      (libsource (lib "eagle-import") (part "M01PTH_SMD_3.25X0.85MM_NO_SILK"))
    )
    (comp (ref "JP1395")
      (value "M01PTH_SMD_3.25X0.85MM_NO_SILK")
      (footprint "eagle-import:1X01_SMD_3.25X0.85MM_NO_SILK")
      (libsource (lib "eagle-import") (part "M01PTH_SMD_3.25X0.85MM_NO_SILK"))
    )
    (comp (ref "JP1396")
      (value "M01PTH_SMD_3.25X0.85MM_NO_SILK")
      (footprint "eagle-import:1X01_SMD_3.25X0.85MM_NO_SILK")
      (libsource (lib "eagle-import") (part "M01PTH_SMD_3.25X0.85MM_NO_SILK"))
    )
    (comp (ref "JP1397")
      (value "M01PTH_SMD_3.25X0.85MM_NO_SILK")
      (footprint "eagle-import:1X01_SMD_3.25X0.85MM_NO_SILK")
      (libsource (lib "eagle-import") (part "M01PTH_SMD_3.25X0.85MM_NO_SILK"))
    )
    (comp (ref "JP1398")
      (value "M01PTH_SMD_3.25X0.85MM_NO_SILK")
      (footprint "eagle-import:1X01_SMD_3.25X0.85MM_NO_SILK")
      (libsource (lib "eagle-import") (part "M01PTH_SMD_3.25X0.85MM_NO_SILK"))
    )
    (comp (ref "JP1399")
      (value "M01PTH_SMD_3.25X0.85MM_NO_SILK")
      (footprint "eagle-import:1X01_SMD_3.25X0.85MM_NO_SILK")
      (libsource (lib "eagle-import") (part "M01PTH_SMD_3.25X0.85MM_NO_SILK"))
    )
    (comp (ref "JP1400")
      (value "M01PTH_SMD_3.25X0.85MM_NO_SILK")
      (footprint "eagle-import:1X01_SMD_3.25X0.85MM_NO_SILK")
      (libsource (lib "eagle-import") (part "M01PTH_SMD_3.25X0.85MM_NO_SILK"))
    )
    (comp (ref "JP1401")
      (value "M01PTH_SMD_3.25X0.85MM_NO_SILK")
      (footprint "eagle-import:1X01_SMD_3.25X0.85MM_NO_SILK")
      (libsource (lib "eagle-import") (part "M01PTH_SMD_3.25X0.85MM_NO_SILK"))
    )
    (comp (ref "JP1402")
      (value "M01PTH_SMD_3.25X0.85MM_NO_SILK")
      (footprint "eagle-import:1X01_SMD_3.25X0.85MM_NO_SILK")
      (libsource (lib "eagle-import") (part "M01PTH_SMD_3.25X0.85MM_NO_SILK"))
    )
    (comp (ref "JP1403")
      (value "M01PTH_SMD_3.25X0.85MM_NO_SILK")
      (footprint "eagle-import:1X01_SMD_3.25X0.85MM_NO_SILK")
      (libsource (lib "eagle-import") (part "M01PTH_SMD_3.25X0.85MM_NO_SILK"))
    )
    (comp (ref "JP1404")
      (value "M01PTH_SMD_3.25X0.85MM_NO_SILK")
      (footprint "eagle-import:1X01_SMD_3.25X0.85MM_NO_SILK")
      (libsource (lib "eagle-import") (part "M01PTH_SMD_3.25X0.85MM_NO_SILK"))
    )
    (comp (ref "JP1405")
      (value "M01PTH_SMD_3.25X0.85MM_NO_SILK")
      (footprint "eagle-import:1X01_SMD_3.25X0.85MM_NO_SILK")
      (libsource (lib "eagle-import") (part "M01PTH_SMD_3.25X0.85MM_NO_SILK"))
    )
    (comp (ref "JP1406")
      (value "M01PTH_SMD_3.25X0.85MM_NO_SILK")
      (footprint "eagle-import:1X01_SMD_3.25X0.85MM_NO_SILK")
      (libsource (lib "eagle-import") (part "M01PTH_SMD_3.25X0.85MM_NO_SILK"))
    )
    (comp (ref "JP1407")
      (value "M01PTH_SMD_3.25X0.85MM_NO_SILK")
      (footprint "eagle-import:1X01_SMD_3.25X0.85MM_NO_SILK")
      (libsource (lib "eagle-import") (part "M01PTH_SMD_3.25X0.85MM_NO_SILK"))
    )
    (comp (ref "JP1408")
      (value "M01PTH_SMD_3.25X0.85MM_NO_SILK")
      (footprint "eagle-import:1X01_SMD_3.25X0.85MM_NO_SILK")
      (libsource (lib "eagle-import") (part "M01PTH_SMD_3.25X0.85MM_NO_SILK"))
    )
    (comp (ref "JP1409")
      (value "M01PTH_SMD_3.25X0.85MM_NO_SILK")
      (footprint "eagle-import:1X01_SMD_3.25X0.85MM_NO_SILK")
      (libsource (lib "eagle-import") (part "M01PTH_SMD_3.25X0.85MM_NO_SILK"))
    )
    (comp (ref "JP1410")
      (value "M01PTH_SMD_3.25X0.85MM_NO_SILK")
      (footprint "eagle-import:1X01_SMD_3.25X0.85MM_NO_SILK")
      (libsource (lib "eagle-import") (part "M01PTH_SMD_3.25X0.85MM_NO_SILK"))
    )
    (comp (ref "JP1411")
      (value "M01PTH_SMD_3.25X0.85MM_NO_SILK")
      (footprint "eagle-import:1X01_SMD_3.25X0.85MM_NO_SILK")
      (libsource (lib "eagle-import") (part "M01PTH_SMD_3.25X0.85MM_NO_SILK"))
    )
    (comp (ref "JP1412")
      (value "M01PTH_SMD_3.25X0.85MM_NO_SILK")
      (footprint "eagle-import:1X01_SMD_3.25X0.85MM_NO_SILK")
      (libsource (lib "eagle-import") (part "M01PTH_SMD_3.25X0.85MM_NO_SILK"))
    )
    (comp (ref "JP1413")
      (value "M01PTH_SMD_3.25X0.85MM_NO_SILK")
      (footprint "eagle-import:1X01_SMD_3.25X0.85MM_NO_SILK")
      (libsource (lib "eagle-import") (part "M01PTH_SMD_3.25X0.85MM_NO_SILK"))
    )
    (comp (ref "JP1414")
      (value "M01PTH_SMD_3.25X0.85MM_NO_SILK")
      (footprint "eagle-import:1X01_SMD_3.25X0.85MM_NO_SILK")
      (libsource (lib "eagle-import") (part "M01PTH_SMD_3.25X0.85MM_NO_SILK"))
    )
    (comp (ref "JP1415")
      (value "M01PTH_SMD_3.25X0.85MM_NO_SILK")
      (footprint "eagle-import:1X01_SMD_3.25X0.85MM_NO_SILK")
      (libsource (lib "eagle-import") (part "M01PTH_SMD_3.25X0.85MM_NO_SILK"))
    )
    (comp (ref "JP1416")
      (value "M01PTH_SMD_3.25X0.85MM_NO_SILK")
      (footprint "eagle-import:1X01_SMD_3.25X0.85MM_NO_SILK")
      (libsource (lib "eagle-import") (part "M01PTH_SMD_3.25X0.85MM_NO_SILK"))
    )
    (comp (ref "JP1417")
      (value "M01PTH_SMD_3.25X0.85MM_NO_SILK")
      (footprint "eagle-import:1X01_SMD_3.25X0.85MM_NO_SILK")
      (libsource (lib "eagle-import") (part "M01PTH_SMD_3.25X0.85MM_NO_SILK"))
    )
    (comp (ref "JP1418")
      (value "M01PTH_SMD_3.25X0.85MM_NO_SILK")
      (footprint "eagle-import:1X01_SMD_3.25X0.85MM_NO_SILK")
      (libsource (lib "eagle-import") (part "M01PTH_SMD_3.25X0.85MM_NO_SILK"))
    )
    (comp (ref "JP1419")
      (value "M01PTH_SMD_3.25X0.85MM_NO_SILK")
      (footprint "eagle-import:1X01_SMD_3.25X0.85MM_NO_SILK")
      (libsource (lib "eagle-import") (part "M01PTH_SMD_3.25X0.85MM_NO_SILK"))
    )
    (comp (ref "JP1420")
      (value "M01PTH_SMD_3.25X0.85MM_NO_SILK")
      (footprint "eagle-import:1X01_SMD_3.25X0.85MM_NO_SILK")
      (libsource (lib "eagle-import") (part "M01PTH_SMD_3.25X0.85MM_NO_SILK"))
    )
    (comp (ref "JP1421")
      (value "M01PTH_SMD_3.25X0.85MM_NO_SILK")
      (footprint "eagle-import:1X01_SMD_3.25X0.85MM_NO_SILK")
      (libsource (lib "eagle-import") (part "M01PTH_SMD_3.25X0.85MM_NO_SILK"))
    )
    (comp (ref "JP1422")
      (value "M01PTH_SMD_3.25X0.85MM_NO_SILK")
      (footprint "eagle-import:1X01_SMD_3.25X0.85MM_NO_SILK")
      (libsource (lib "eagle-import") (part "M01PTH_SMD_3.25X0.85MM_NO_SILK"))
    )
    (comp (ref "JP1423")
      (value "M01PTH_SMD_3.25X0.85MM_NO_SILK")
      (footprint "eagle-import:1X01_SMD_3.25X0.85MM_NO_SILK")
      (libsource (lib "eagle-import") (part "M01PTH_SMD_3.25X0.85MM_NO_SILK"))
    )
    (comp (ref "JP1424")
      (value "M01PTH_SMD_3.25X0.85MM_NO_SILK")
      (footprint "eagle-import:1X01_SMD_3.25X0.85MM_NO_SILK")
      (libsource (lib "eagle-import") (part "M01PTH_SMD_3.25X0.85MM_NO_SILK"))
    )
    (comp (ref "JP1425")
      (value "M01PTH_SMD_3.25X0.85MM_NO_SILK")
      (footprint "eagle-import:1X01_SMD_3.25X0.85MM_NO_SILK")
      (libsource (lib "eagle-import") (part "M01PTH_SMD_3.25X0.85MM_NO_SILK"))
    )
    (comp (ref "JP1426")
      (value "M01PTH_SMD_3.25X0.85MM_NO_SILK")
      (footprint "eagle-import:1X01_SMD_3.25X0.85MM_NO_SILK")
      (libsource (lib "eagle-import") (part "M01PTH_SMD_3.25X0.85MM_NO_SILK"))
    )
    (comp (ref "JP1427")
      (value "M01PTH_SMD_3.25X0.85MM_NO_SILK")
      (footprint "eagle-import:1X01_SMD_3.25X0.85MM_NO_SILK")
      (libsource (lib "eagle-import") (part "M01PTH_SMD_3.25X0.85MM_NO_SILK"))
    )
    (comp (ref "JP1428")
      (value "M01PTH_SMD_3.25X0.85MM_NO_SILK")
      (footprint "eagle-import:1X01_SMD_3.25X0.85MM_NO_SILK")
      (libsource (lib "eagle-import") (part "M01PTH_SMD_3.25X0.85MM_NO_SILK"))
    )
    (comp (ref "JP1429")
      (value "M01PTH_SMD_3.25X0.85MM_NO_SILK")
      (footprint "eagle-import:1X01_SMD_3.25X0.85MM_NO_SILK")
      (libsource (lib "eagle-import") (part "M01PTH_SMD_3.25X0.85MM_NO_SILK"))
    )
    (comp (ref "JP1430")
      (value "M01PTH_SMD_3.25X0.85MM_NO_SILK")
      (footprint "eagle-import:1X01_SMD_3.25X0.85MM_NO_SILK")
      (libsource (lib "eagle-import") (part "M01PTH_SMD_3.25X0.85MM_NO_SILK"))
    )
    (comp (ref "JP1431")
      (value "M01PTH_SMD_3.25X0.85MM_NO_SILK")
      (footprint "eagle-import:1X01_SMD_3.25X0.85MM_NO_SILK")
      (libsource (lib "eagle-import") (part "M01PTH_SMD_3.25X0.85MM_NO_SILK"))
    )
    (comp (ref "JP1432")
      (value "M01PTH_SMD_3.25X0.85MM_NO_SILK")
      (footprint "eagle-import:1X01_SMD_3.25X0.85MM_NO_SILK")
      (libsource (lib "eagle-import") (part "M01PTH_SMD_3.25X0.85MM_NO_SILK"))
    )
    (comp (ref "JP1433")
      (value "M01PTH_SMD_3.25X0.85MM_NO_SILK")
      (footprint "eagle-import:1X01_SMD_3.25X0.85MM_NO_SILK")
      (libsource (lib "eagle-import") (part "M01PTH_SMD_3.25X0.85MM_NO_SILK"))
    )
    (comp (ref "JP1434")
      (value "M01PTH_SMD_3.25X0.85MM_NO_SILK")
      (footprint "eagle-import:1X01_SMD_3.25X0.85MM_NO_SILK")
      (libsource (lib "eagle-import") (part "M01PTH_SMD_3.25X0.85MM_NO_SILK"))
    )
    (comp (ref "JP1435")
      (value "M01PTH_SMD_3.25X0.85MM_NO_SILK")
      (footprint "eagle-import:1X01_SMD_3.25X0.85MM_NO_SILK")
      (libsource (lib "eagle-import") (part "M01PTH_SMD_3.25X0.85MM_NO_SILK"))
    )
    (comp (ref "JP1436")
      (value "M01PTH_SMD_3.25X0.85MM_NO_SILK")
      (footprint "eagle-import:1X01_SMD_3.25X0.85MM_NO_SILK")
      (libsource (lib "eagle-import") (part "M01PTH_SMD_3.25X0.85MM_NO_SILK"))
    )
    (comp (ref "JP1437")
      (value "M01PTH_SMD_3.25X0.85MM_NO_SILK")
      (footprint "eagle-import:1X01_SMD_3.25X0.85MM_NO_SILK")
      (libsource (lib "eagle-import") (part "M01PTH_SMD_3.25X0.85MM_NO_SILK"))
    )
    (comp (ref "JP1438")
      (value "M01PTH_SMD_3.25X0.85MM_NO_SILK")
      (footprint "eagle-import:1X01_SMD_3.25X0.85MM_NO_SILK")
      (libsource (lib "eagle-import") (part "M01PTH_SMD_3.25X0.85MM_NO_SILK"))
    )
    (comp (ref "JP1439")
      (value "M01PTH_SMD_3.25X0.85MM_NO_SILK")
      (footprint "eagle-import:1X01_SMD_3.25X0.85MM_NO_SILK")
      (libsource (lib "eagle-import") (part "M01PTH_SMD_3.25X0.85MM_NO_SILK"))
    )
    (comp (ref "JP1440")
      (value "M01PTH_SMD_3.25X0.85MM_NO_SILK")
      (footprint "eagle-import:1X01_SMD_3.25X0.85MM_NO_SILK")
      (libsource (lib "eagle-import") (part "M01PTH_SMD_3.25X0.85MM_NO_SILK"))
    )
    (comp (ref "JP1441")
      (value "M01PTH_SMD_3.25X0.85MM_NO_SILK")
      (footprint "eagle-import:1X01_SMD_3.25X0.85MM_NO_SILK")
      (libsource (lib "eagle-import") (part "M01PTH_SMD_3.25X0.85MM_NO_SILK"))
    )
    (comp (ref "JP1442")
      (value "M01PTH_SMD_3.25X0.85MM_NO_SILK")
      (footprint "eagle-import:1X01_SMD_3.25X0.85MM_NO_SILK")
      (libsource (lib "eagle-import") (part "M01PTH_SMD_3.25X0.85MM_NO_SILK"))
    )
    (comp (ref "JP1443")
      (value "M01PTH_SMD_3.25X0.85MM_NO_SILK")
      (footprint "eagle-import:1X01_SMD_3.25X0.85MM_NO_SILK")
      (libsource (lib "eagle-import") (part "M01PTH_SMD_3.25X0.85MM_NO_SILK"))
    )
    (comp (ref "JP1444")
      (value "M01PTH_SMD_3.25X0.85MM_NO_SILK")
      (footprint "eagle-import:1X01_SMD_3.25X0.85MM_NO_SILK")
      (libsource (lib "eagle-import") (part "M01PTH_SMD_3.25X0.85MM_NO_SILK"))
    )
    (comp (ref "JP1445")
      (value "M01PTH_SMD_3.25X0.85MM_NO_SILK")
      (footprint "eagle-import:1X01_SMD_3.25X0.85MM_NO_SILK")
      (libsource (lib "eagle-import") (part "M01PTH_SMD_3.25X0.85MM_NO_SILK"))
    )
    (comp (ref "JP1446")
      (value "M01PTH_SMD_3.25X0.85MM_NO_SILK")
      (footprint "eagle-import:1X01_SMD_3.25X0.85MM_NO_SILK")
      (libsource (lib "eagle-import") (part "M01PTH_SMD_3.25X0.85MM_NO_SILK"))
    )
    (comp (ref "JP1447")
      (value "M01PTH_SMD_3.25X0.85MM_NO_SILK")
      (footprint "eagle-import:1X01_SMD_3.25X0.85MM_NO_SILK")
      (libsource (lib "eagle-import") (part "M01PTH_SMD_3.25X0.85MM_NO_SILK"))
    )
    (comp (ref "JP1448")
      (value "M01PTH_SMD_3.25X0.85MM_NO_SILK")
      (footprint "eagle-import:1X01_SMD_3.25X0.85MM_NO_SILK")
      (libsource (lib "eagle-import") (part "M01PTH_SMD_3.25X0.85MM_NO_SILK"))
    )
    (comp (ref "JP1449")
      (value "M01PTH_SMD_3.25X0.85MM_NO_SILK")
      (footprint "eagle-import:1X01_SMD_3.25X0.85MM_NO_SILK")
      (libsource (lib "eagle-import") (part "M01PTH_SMD_3.25X0.85MM_NO_SILK"))
    )
    (comp (ref "JP1450")
      (value "M01PTH_SMD_3.25X0.85MM_NO_SILK")
      (footprint "eagle-import:1X01_SMD_3.25X0.85MM_NO_SILK")
      (libsource (lib "eagle-import") (part "M01PTH_SMD_3.25X0.85MM_NO_SILK"))
    )
    (comp (ref "JP1451")
      (value "M01PTH_SMD_3.25X0.85MM_NO_SILK")
      (footprint "eagle-import:1X01_SMD_3.25X0.85MM_NO_SILK")
      (libsource (lib "eagle-import") (part "M01PTH_SMD_3.25X0.85MM_NO_SILK"))
    )
    (comp (ref "JP1452")
      (value "M01PTH_SMD_3.25X0.85MM_NO_SILK")
      (footprint "eagle-import:1X01_SMD_3.25X0.85MM_NO_SILK")
      (libsource (lib "eagle-import") (part "M01PTH_SMD_3.25X0.85MM_NO_SILK"))
    )
    (comp (ref "JP1453")
      (value "M01PTH_SMD_3.25X0.85MM_NO_SILK")
      (footprint "eagle-import:1X01_SMD_3.25X0.85MM_NO_SILK")
      (libsource (lib "eagle-import") (part "M01PTH_SMD_3.25X0.85MM_NO_SILK"))
    )
    (comp (ref "JP1454")
      (value "M01PTH_SMD_3.25X0.85MM_NO_SILK")
      (footprint "eagle-import:1X01_SMD_3.25X0.85MM_NO_SILK")
      (libsource (lib "eagle-import") (part "M01PTH_SMD_3.25X0.85MM_NO_SILK"))
    )
    (comp (ref "JP1455")
      (value "M01PTH_SMD_3.25X0.85MM_NO_SILK")
      (footprint "eagle-import:1X01_SMD_3.25X0.85MM_NO_SILK")
      (libsource (lib "eagle-import") (part "M01PTH_SMD_3.25X0.85MM_NO_SILK"))
    )
    (comp (ref "JP1456")
      (value "M01PTH_SMD_3.25X0.85MM_NO_SILK")
      (footprint "eagle-import:1X01_SMD_3.25X0.85MM_NO_SILK")
      (libsource (lib "eagle-import") (part "M01PTH_SMD_3.25X0.85MM_NO_SILK"))
    )
    (comp (ref "JP1457")
      (value "M01PTH_SMD_3.25X0.85MM_NO_SILK")
      (footprint "eagle-import:1X01_SMD_3.25X0.85MM_NO_SILK")
      (libsource (lib "eagle-import") (part "M01PTH_SMD_3.25X0.85MM_NO_SILK"))
    )
    (comp (ref "JP1458")
      (value "M01PTH_SMD_3.25X0.85MM_NO_SILK")
      (footprint "eagle-import:1X01_SMD_3.25X0.85MM_NO_SILK")
      (libsource (lib "eagle-import") (part "M01PTH_SMD_3.25X0.85MM_NO_SILK"))
    )
    (comp (ref "JP1459")
      (value "M01PTH_SMD_3.25X0.85MM_NO_SILK")
      (footprint "eagle-import:1X01_SMD_3.25X0.85MM_NO_SILK")
      (libsource (lib "eagle-import") (part "M01PTH_SMD_3.25X0.85MM_NO_SILK"))
    )
    (comp (ref "JP1460")
      (value "M01PTH_SMD_3.25X0.85MM_NO_SILK")
      (footprint "eagle-import:1X01_SMD_3.25X0.85MM_NO_SILK")
      (libsource (lib "eagle-import") (part "M01PTH_SMD_3.25X0.85MM_NO_SILK"))
    )
    (comp (ref "JP1461")
      (value "M01PTH_SMD_3.25X0.85MM_NO_SILK")
      (footprint "eagle-import:1X01_SMD_3.25X0.85MM_NO_SILK")
      (libsource (lib "eagle-import") (part "M01PTH_SMD_3.25X0.85MM_NO_SILK"))
    )
    (comp (ref "JP1462")
      (value "M01PTH_SMD_3.25X0.85MM_NO_SILK")
      (footprint "eagle-import:1X01_SMD_3.25X0.85MM_NO_SILK")
      (libsource (lib "eagle-import") (part "M01PTH_SMD_3.25X0.85MM_NO_SILK"))
    )
    (comp (ref "JP1463")
      (value "M01PTH_SMD_3.25X0.85MM_NO_SILK")
      (footprint "eagle-import:1X01_SMD_3.25X0.85MM_NO_SILK")
      (libsource (lib "eagle-import") (part "M01PTH_SMD_3.25X0.85MM_NO_SILK"))
    )
    (comp (ref "JP1464")
      (value "M01PTH_SMD_3.25X0.85MM_NO_SILK")
      (footprint "eagle-import:1X01_SMD_3.25X0.85MM_NO_SILK")
      (libsource (lib "eagle-import") (part "M01PTH_SMD_3.25X0.85MM_NO_SILK"))
    )
    (comp (ref "JP1465")
      (value "M01PTH_SMD_3.25X0.85MM_NO_SILK")
      (footprint "eagle-import:1X01_SMD_3.25X0.85MM_NO_SILK")
      (libsource (lib "eagle-import") (part "M01PTH_SMD_3.25X0.85MM_NO_SILK"))
    )
    (comp (ref "JP1466")
      (value "M01PTH_SMD_3.25X0.85MM_NO_SILK")
      (footprint "eagle-import:1X01_SMD_3.25X0.85MM_NO_SILK")
      (libsource (lib "eagle-import") (part "M01PTH_SMD_3.25X0.85MM_NO_SILK"))
    )
    (comp (ref "JP1467")
      (value "M01PTH_SMD_3.25X0.85MM_NO_SILK")
      (footprint "eagle-import:1X01_SMD_3.25X0.85MM_NO_SILK")
      (libsource (lib "eagle-import") (part "M01PTH_SMD_3.25X0.85MM_NO_SILK"))
    )
    (comp (ref "JP1468")
      (value "M01PTH_SMD_3.25X0.85MM_NO_SILK")
      (footprint "eagle-import:1X01_SMD_3.25X0.85MM_NO_SILK")
      (libsource (lib "eagle-import") (part "M01PTH_SMD_3.25X0.85MM_NO_SILK"))
    )
    (comp (ref "JP1469")
      (value "M01PTH_SMD_3.25X0.85MM_NO_SILK")
      (footprint "eagle-import:1X01_SMD_3.25X0.85MM_NO_SILK")
      (libsource (lib "eagle-import") (part "M01PTH_SMD_3.25X0.85MM_NO_SILK"))
    )
    (comp (ref "JP1470")
      (value "M01PTH_SMD_3.25X0.85MM_NO_SILK")
      (footprint "eagle-import:1X01_SMD_3.25X0.85MM_NO_SILK")
      (libsource (lib "eagle-import") (part "M01PTH_SMD_3.25X0.85MM_NO_SILK"))
    )
    (comp (ref "JP1471")
      (value "M01PTH_SMD_3.25X0.85MM_NO_SILK")
      (footprint "eagle-import:1X01_SMD_3.25X0.85MM_NO_SILK")
      (libsource (lib "eagle-import") (part "M01PTH_SMD_3.25X0.85MM_NO_SILK"))
    )
    (comp (ref "JP1472")
      (value "M01PTH_SMD_3.25X0.85MM_NO_SILK")
      (footprint "eagle-import:1X01_SMD_3.25X0.85MM_NO_SILK")
      (libsource (lib "eagle-import") (part "M01PTH_SMD_3.25X0.85MM_NO_SILK"))
    )
    (comp (ref "JP1473")
      (value "M01PTH_SMD_3.25X0.85MM_NO_SILK")
      (footprint "eagle-import:1X01_SMD_3.25X0.85MM_NO_SILK")
      (libsource (lib "eagle-import") (part "M01PTH_SMD_3.25X0.85MM_NO_SILK"))
    )
    (comp (ref "JP1474")
      (value "M01PTH_SMD_3.25X0.85MM_NO_SILK")
      (footprint "eagle-import:1X01_SMD_3.25X0.85MM_NO_SILK")
      (libsource (lib "eagle-import") (part "M01PTH_SMD_3.25X0.85MM_NO_SILK"))
    )
    (comp (ref "JP1475")
      (value "M01PTH_SMD_3.25X0.85MM_NO_SILK")
      (footprint "eagle-import:1X01_SMD_3.25X0.85MM_NO_SILK")
      (libsource (lib "eagle-import") (part "M01PTH_SMD_3.25X0.85MM_NO_SILK"))
    )
    (comp (ref "JP1476")
      (value "M01PTH_SMD_3.25X0.85MM_NO_SILK")
      (footprint "eagle-import:1X01_SMD_3.25X0.85MM_NO_SILK")
      (libsource (lib "eagle-import") (part "M01PTH_SMD_3.25X0.85MM_NO_SILK"))
    )
    (comp (ref "JP1477")
      (value "M01PTH_SMD_3.25X0.85MM_NO_SILK")
      (footprint "eagle-import:1X01_SMD_3.25X0.85MM_NO_SILK")
      (libsource (lib "eagle-import") (part "M01PTH_SMD_3.25X0.85MM_NO_SILK"))
    )
    (comp (ref "JP1478")
      (value "M01PTH_SMD_3.25X0.85MM_NO_SILK")
      (footprint "eagle-import:1X01_SMD_3.25X0.85MM_NO_SILK")
      (libsource (lib "eagle-import") (part "M01PTH_SMD_3.25X0.85MM_NO_SILK"))
    )
    (comp (ref "JP1479")
      (value "M01PTH_SMD_3.25X0.85MM_NO_SILK")
      (footprint "eagle-import:1X01_SMD_3.25X0.85MM_NO_SILK")
      (libsource (lib "eagle-import") (part "M01PTH_SMD_3.25X0.85MM_NO_SILK"))
    )
    (comp (ref "JP1480")
      (value "M01PTH_SMD_3.25X0.85MM_NO_SILK")
      (footprint "eagle-import:1X01_SMD_3.25X0.85MM_NO_SILK")
      (libsource (lib "eagle-import") (part "M01PTH_SMD_3.25X0.85MM_NO_SILK"))
    )
    (comp (ref "JP1481")
      (value "M01PTH_SMD_3.25X0.85MM_NO_SILK")
      (footprint "eagle-import:1X01_SMD_3.25X0.85MM_NO_SILK")
      (libsource (lib "eagle-import") (part "M01PTH_SMD_3.25X0.85MM_NO_SILK"))
    )
    (comp (ref "JP1482")
      (value "M01PTH_SMD_3.25X0.85MM_NO_SILK")
      (footprint "eagle-import:1X01_SMD_3.25X0.85MM_NO_SILK")
      (libsource (lib "eagle-import") (part "M01PTH_SMD_3.25X0.85MM_NO_SILK"))
    )
    (comp (ref "JP1483")
      (value "M01PTH_SMD_3.25X0.85MM_NO_SILK")
      (footprint "eagle-import:1X01_SMD_3.25X0.85MM_NO_SILK")
      (libsource (lib "eagle-import") (part "M01PTH_SMD_3.25X0.85MM_NO_SILK"))
    )
    (comp (ref "JP1484")
      (value "M01PTH_SMD_3.25X0.85MM_NO_SILK")
      (footprint "eagle-import:1X01_SMD_3.25X0.85MM_NO_SILK")
      (libsource (lib "eagle-import") (part "M01PTH_SMD_3.25X0.85MM_NO_SILK"))
    )
    (comp (ref "JP1485")
      (value "M01PTH_SMD_3.25X0.85MM_NO_SILK")
      (footprint "eagle-import:1X01_SMD_3.25X0.85MM_NO_SILK")
      (libsource (lib "eagle-import") (part "M01PTH_SMD_3.25X0.85MM_NO_SILK"))
    )
    (comp (ref "JP1486")
      (value "M01PTH_SMD_3.25X0.85MM_NO_SILK")
      (footprint "eagle-import:1X01_SMD_3.25X0.85MM_NO_SILK")
      (libsource (lib "eagle-import") (part "M01PTH_SMD_3.25X0.85MM_NO_SILK"))
    )
    (comp (ref "JP1487")
      (value "M01PTH_SMD_3.25X0.85MM_NO_SILK")
      (footprint "eagle-import:1X01_SMD_3.25X0.85MM_NO_SILK")
      (libsource (lib "eagle-import") (part "M01PTH_SMD_3.25X0.85MM_NO_SILK"))
    )
    (comp (ref "JP1488")
      (value "M01PTH_SMD_3.25X0.85MM_NO_SILK")
      (footprint "eagle-import:1X01_SMD_3.25X0.85MM_NO_SILK")
      (libsource (lib "eagle-import") (part "M01PTH_SMD_3.25X0.85MM_NO_SILK"))
    )
    (comp (ref "JP1489")
      (value "M01PTH_SMD_3.25X0.85MM_NO_SILK")
      (footprint "eagle-import:1X01_SMD_3.25X0.85MM_NO_SILK")
      (libsource (lib "eagle-import") (part "M01PTH_SMD_3.25X0.85MM_NO_SILK"))
    )
    (comp (ref "JP1490")
      (value "M01PTH_SMD_3.25X0.85MM_NO_SILK")
      (footprint "eagle-import:1X01_SMD_3.25X0.85MM_NO_SILK")
      (libsource (lib "eagle-import") (part "M01PTH_SMD_3.25X0.85MM_NO_SILK"))
    )
    (comp (ref "JP1491")
      (value "M01PTH_SMD_3.25X0.85MM_NO_SILK")
      (footprint "eagle-import:1X01_SMD_3.25X0.85MM_NO_SILK")
      (libsource (lib "eagle-import") (part "M01PTH_SMD_3.25X0.85MM_NO_SILK"))
    )
    (comp (ref "JP1492")
      (value "M01PTH_SMD_3.25X0.85MM_NO_SILK")
      (footprint "eagle-import:1X01_SMD_3.25X0.85MM_NO_SILK")
      (libsource (lib "eagle-import") (part "M01PTH_SMD_3.25X0.85MM_NO_SILK"))
    )
    (comp (ref "JP1493")
      (value "M01PTH_SMD_3.25X0.85MM_NO_SILK")
      (footprint "eagle-import:1X01_SMD_3.25X0.85MM_NO_SILK")
      (libsource (lib "eagle-import") (part "M01PTH_SMD_3.25X0.85MM_NO_SILK"))
    )
    (comp (ref "JP1494")
      (value "M01PTH_SMD_3.25X0.85MM_NO_SILK")
      (footprint "eagle-import:1X01_SMD_3.25X0.85MM_NO_SILK")
      (libsource (lib "eagle-import") (part "M01PTH_SMD_3.25X0.85MM_NO_SILK"))
    )
    (comp (ref "JP1495")
      (value "M01PTH_SMD_3.25X0.85MM_NO_SILK")
      (footprint "eagle-import:1X01_SMD_3.25X0.85MM_NO_SILK")
      (libsource (lib "eagle-import") (part "M01PTH_SMD_3.25X0.85MM_NO_SILK"))
    )
    (comp (ref "JP1496")
      (value "M01PTH_SMD_3.25X0.85MM_NO_SILK")
      (footprint "eagle-import:1X01_SMD_3.25X0.85MM_NO_SILK")
      (libsource (lib "eagle-import") (part "M01PTH_SMD_3.25X0.85MM_NO_SILK"))
    )
    (comp (ref "JP1497")
      (value "M01PTH_SMD_3.25X0.85MM_NO_SILK")
      (footprint "eagle-import:1X01_SMD_3.25X0.85MM_NO_SILK")
      (libsource (lib "eagle-import") (part "M01PTH_SMD_3.25X0.85MM_NO_SILK"))
    )
    (comp (ref "JP1498")
      (value "M01PTH_SMD_3.25X0.85MM_NO_SILK")
      (footprint "eagle-import:1X01_SMD_3.25X0.85MM_NO_SILK")
      (libsource (lib "eagle-import") (part "M01PTH_SMD_3.25X0.85MM_NO_SILK"))
    )
    (comp (ref "JP1499")
      (value "M01PTH_SMD_3.25X0.85MM_NO_SILK")
      (footprint "eagle-import:1X01_SMD_3.25X0.85MM_NO_SILK")
      (libsource (lib "eagle-import") (part "M01PTH_SMD_3.25X0.85MM_NO_SILK"))
    )
    (comp (ref "JP1500")
      (value "M01PTH_SMD_3.25X0.85MM_NO_SILK")
      (footprint "eagle-import:1X01_SMD_3.25X0.85MM_NO_SILK")
      (libsource (lib "eagle-import") (part "M01PTH_SMD_3.25X0.85MM_NO_SILK"))
    )
  )
  (nets
    (net (code "1") (name "Net-(JP1-Pad1)") (class "Default")
      (node (ref "JP1") (pin "1") (pinfunction "1_1") (pintype "passive"))
      (node (ref "JP301") (pin "1") (pinfunction "1_1") (pintype "passive"))
    )
    (net (code "2") (name "Net-(JP2-Pad1)") (class "Default")
      (node (ref "JP2") (pin "1") (pinfunction "1_1") (pintype "passive"))
      (node (ref "JP302") (pin "1") (pinfunction "1_1") (pintype "passive"))
    )
    (net (code "3") (name "Net-(JP3-Pad1)") (class "Default")
      (node (ref "JP3") (pin "1") (pinfunction "1_1") (pintype "passive"))
      (node (ref "JP303") (pin "1") (pinfunction "1_1") (pintype "passive"))
    )
    (net (code "4") (name "Net-(JP10-Pad1)") (class "Default")
      (node (ref "JP10") (pin "1") (pinfunction "1_1") (pintype "passive"))
      (node (ref "JP310") (pin "1") (pinfunction "1_1") (pintype "passive"))
    )
    (net (code "5") (name "Net-(JP11-Pad1)") (class "Default")
      (node (ref "JP11") (pin "1") (pinfunction "1_1") (pintype "passive"))
      (node (ref "JP311") (pin "1") (pinfunction "1_1") (pintype "passive"))
    )
    (net (code "6") (name "Net-(JP12-Pad1)") (class "Default")
      (node (ref "JP12") (pin "1") (pinfunction "1_1") (pintype "passive"))
      (node (ref "JP312") (pin "1") (pinfunction "1_1") (pintype "passive"))
    )
    (net (code "7") (name "Net-(JP13-Pad1)") (class "Default")
      (node (ref "JP13") (pin "1") (pinfunction "1_1") (pintype "passive"))
      (node (ref "JP313") (pin "1") (pinfunction "1_1") (pintype "passive"))
    )
    (net (code "8") (name "Net-(JP14-Pad1)") (class "Default")
      (node (ref "JP14") (pin "1") (pinfunction "1_1") (pintype "passive"))
      (node (ref "JP314") (pin "1") (pinfunction "1_1") (pintype "passive"))
    )
    (net (code "9") (name "Net-(JP15-Pad1)") (class "Default")
      (node (ref "JP15") (pin "1") (pinfunction "1_1") (pintype "passive"))
      (node (ref "JP315") (pin "1") (pinfunction "1_1") (pintype "passive"))
    )
    (net (code "10") (name "Net-(JP16-Pad1)") (class "Default")
      (node (ref "JP16") (pin "1") (pinfunction "1_1") (pintype "passive"))
      (node (ref "JP316") (pin "1") (pinfunction "1_1") (pintype "passive"))
    )
    (net (code "11") (name "Net-(JP17-Pad1)") (class "Default")
      (node (ref "JP17") (pin "1") (pinfunction "1_1") (pintype "passive"))
      (node (ref "JP317") (pin "1") (pinfunction "1_1") (pintype "passive"))
    )
    (net (code "12") (name "Net-(JP18-Pad1)") (class "Default")
      (node (ref "JP18") (pin "1") (pinfunction "1_1") (pintype "passive"))
      (node (ref "JP318") (pin "1") (pinfunction "1_1") (pintype "passive"))
    )
    (net (code "13") (name "Net-(JP19-Pad1)") (class "Default")
      (node (ref "JP19") (pin "1") (pinfunction "1_1") (pintype "passive"))
      (node (ref "JP319") (pin "1") (pinfunction "1_1") (pintype "passive"))
    )
    (net (code "14") (name "Net-(JP20-Pad1)") (class "Default")
      (node (ref "JP20") (pin "1") (pinfunction "1_1") (pintype "passive"))
      (node (ref "JP320") (pin "1") (pinfunction "1_1") (pintype "passive"))
    )
    (net (code "15") (name "Net-(JP21-Pad1)") (class "Default")
      (node (ref "JP21") (pin "1") (pinfunction "1_1") (pintype "passive"))
      (node (ref "JP321") (pin "1") (pinfunction "1_1") (pintype "passive"))
    )
    (net (code "16") (name "Net-(JP22-Pad1)") (class "Default")
      (node (ref "JP22") (pin "1") (pinfunction "1_1") (pintype "passive"))
      (node (ref "JP322") (pin "1") (pinfunction "1_1") (pintype "passive"))
    )
    (net (code "17") (name "Net-(JP23-Pad1)") (class "Default")
      (node (ref "JP23") (pin "1") (pinfunction "1_1") (pintype "passive"))
      (node (ref "JP323") (pin "1") (pinfunction "1_1") (pintype "passive"))
    )
    (net (code "18") (name "Net-(JP24-Pad1)") (class "Default")
      (node (ref "JP24") (pin "1") (pinfunction "1_1") (pintype "passive"))
      (node (ref "JP324") (pin "1") (pinfunction "1_1") (pintype "passive"))
    )
    (net (code "19") (name "Net-(JP25-Pad1)") (class "Default")
      (node (ref "JP25") (pin "1") (pinfunction "1_1") (pintype "passive"))
      (node (ref "JP325") (pin "1") (pinfunction "1_1") (pintype "passive"))
    )
    (net (code "20") (name "Net-(JP26-Pad1)") (class "Default")
      (node (ref "JP26") (pin "1") (pinfunction "1_1") (pintype "passive"))
      (node (ref "JP326") (pin "1") (pinfunction "1_1") (pintype "passive"))
    )
    (net (code "21") (name "Net-(JP27-Pad1)") (class "Default")
      (node (ref "JP27") (pin "1") (pinfunction "1_1") (pintype "passive"))
      (node (ref "JP327") (pin "1") (pinfunction "1_1") (pintype "passive"))
    )
    (net (code "22") (name "Net-(JP28-Pad1)") (class "Default")
      (node (ref "JP28") (pin "1") (pinfunction "1_1") (pintype "passive"))
      (node (ref "JP328") (pin "1") (pinfunction "1_1") (pintype "passive"))
    )
    (net (code "23") (name "Net-(JP29-Pad1)") (class "Default")
      (node (ref "JP29") (pin "1") (pinfunction "1_1") (pintype "passive"))
      (node (ref "JP329") (pin "1") (pinfunction "1_1") (pintype "passive"))
    )
    (net (code "24") (name "Net-(JP30-Pad1)") (class "Default")
      (node (ref "JP30") (pin "1") (pinfunction "1_1") (pintype "passive"))
      (node (ref "JP330") (pin "1") (pinfunction "1_1") (pintype "passive"))
    )
    (net (code "25") (name "Net-(JP31-Pad1)") (class "Default")
      (node (ref "JP31") (pin "1") (pinfunction "1_1") (pintype "passive"))
      (node (ref "JP331") (pin "1") (pinfunction "1_1") (pintype "passive"))
    )
    (net (code "26") (name "Net-(JP32-Pad1)") (class "Default")
      (node (ref "JP32") (pin "1") (pinfunction "1_1") (pintype "passive"))
      (node (ref "JP332") (pin "1") (pinfunction "1_1") (pintype "passive"))
    )
    (net (code "27") (name "Net-(JP33-Pad1)") (class "Default")
      (node (ref "JP33") (pin "1") (pinfunction "1_1") (pintype "passive"))
      (node (ref "JP333") (pin "1") (pinfunction "1_1") (pintype "passive"))
    )
    (net (code "28") (name "Net-(JP100-Pad1)") (class "Default")
      (node (ref "JP100") (pin "1") (pinfunction "1_1") (pintype "passive"))
      (node (ref "JP400") (pin "1") (pinfunction "1_1") (pintype "passive"))
    )
    (net (code "29") (name "Net-(JP101-Pad1)") (class "Default")
      (node (ref "JP101") (pin "1") (pinfunction "1_1") (pintype "passive"))
      (node (ref "JP401") (pin "1") (pinfunction "1_1") (pintype "passive"))
    )
    (net (code "30") (name "Net-(JP102-Pad1)") (class "Default")
      (node (ref "JP102") (pin "1") (pinfunction "1_1") (pintype "passive"))
      (node (ref "JP402") (pin "1") (pinfunction "1_1") (pintype "passive"))
    )
    (net (code "31") (name "Net-(JP103-Pad1)") (class "Default")
      (node (ref "JP103") (pin "1") (pinfunction "1_1") (pintype "passive"))
      (node (ref "JP403") (pin "1") (pinfunction "1_1") (pintype "passive"))
    )
    (net (code "32") (name "Net-(JP104-Pad1)") (class "Default")
      (node (ref "JP104") (pin "1") (pinfunction "1_1") (pintype "passive"))
      (node (ref "JP404") (pin "1") (pinfunction "1_1") (pintype "passive"))
    )
    (net (code "33") (name "Net-(JP105-Pad1)") (class "Default")
      (node (ref "JP105") (pin "1") (pinfunction "1_1") (pintype "passive"))
      (node (ref "JP405") (pin "1") (pinfunction "1_1") (pintype "passive"))
    )
    (net (code "34") (name "Net-(JP106-Pad1)") (class "Default")
      (node (ref "JP106") (pin "1") (pinfunction "1_1") (pintype "passive"))
      (node (ref "JP406") (pin "1") (pinfunction "1_1") (pintype "passive"))
    )
    (net (code "35") (name "Net-(JP107-Pad1)") (class "Default")
      (node (ref "JP107") (pin "1") (pinfunction "1_1") (pintype "passive"))
      (node (ref "JP407") (pin "1") (pinfunction "1_1") (pintype "passive"))
    )
    (net (code "36") (name "Net-(JP108-Pad1)") (class "Default")
      (node (ref "JP108") (pin "1") (pinfunction "1_1") (pintype "passive"))
      (node (ref "JP408") (pin "1") (pinfunction "1_1") (pintype "passive"))
    )
    (net (code "37") (name "Net-(JP109-Pad1)") (class "Default")
      (node (ref "JP109") (pin "1") (pinfunction "1_1") (pintype "passive"))
      (node (ref "JP409") (pin "1") (pinfunction "1_1") (pintype "passive"))
    )
    (net (code "38") (name "Net-(JP110-Pad1)") (class "Default")
      (node (ref "JP110") (pin "1") (pinfunction "1_1") (pintype "passive"))
      (node (ref "JP410") (pin "1") (pinfunction "1_1") (pintype "passive"))
    )
    (net (code "39") (name "Net-(JP111-Pad1)") (class "Default")
      (node (ref "JP111") (pin "1") (pinfunction "1_1") (pintype "passive"))
      (node (ref "JP411") (pin "1") (pinfunction "1_1") (pintype "passive"))
    )
    (net (code "40") (name "Net-(JP112-Pad1)") (class "Default")
      (node (ref "JP112") (pin "1") (pinfunction "1_1") (pintype "passive"))
      (node (ref "JP412") (pin "1") (pinfunction "1_1") (pintype "passive"))
    )
    (net (code "41") (name "Net-(JP113-Pad1)") (class "Default")
      (node (ref "JP113") (pin "1") (pinfunction "1_1") (pintype "passive"))
      (node (ref "JP413") (pin "1") (pinfunction "1_1") (pintype "passive"))
    )
    (net (code "42") (name "Net-(JP114-Pad1)") (class "Default")
      (node (ref "JP114") (pin "1") (pinfunction "1_1") (pintype "passive"))
      (node (ref "JP414") (pin "1") (pinfunction "1_1") (pintype "passive"))
    )
    (net (code "43") (name "Net-(JP115-Pad1)") (class "Default")
      (node (ref "JP115") (pin "1") (pinfunction "1_1") (pintype "passive"))
      (node (ref "JP415") (pin "1") (pinfunction "1_1") (pintype "passive"))
    )
    (net (code "44") (name "Net-(JP116-Pad1)") (class "Default")
      (node (ref "JP116") (pin "1") (pinfunction "1_1") (pintype "passive"))
      (node (ref "JP416") (pin "1") (pinfunction "1_1") (pintype "passive"))
    )
    (net (code "45") (name "Net-(JP117-Pad1)") (class "Default")
      (node (ref "JP117") (pin "1") (pinfunction "1_1") (pintype "passive"))
      (node (ref "JP417") (pin "1") (pinfunction "1_1") (pintype "passive"))
    )
    (net (code "46") (name "Net-(JP118-Pad1)") (class "Default")
      (node (ref "JP118") (pin "1") (pinfunction "1_1") (pintype "passive"))
      (node (ref "JP418") (pin "1") (pinfunction "1_1") (pintype "passive"))
    )
    (net (code "47") (name "Net-(JP119-Pad1)") (class "Default")
      (node (ref "JP119") (pin "1") (pinfunction "1_1") (pintype "passive"))
      (node (ref "JP419") (pin "1") (pinfunction "1_1") (pintype "passive"))
    )
    (net (code "48") (name "Net-(JP120-Pad1)") (class "Default")
      (node (ref "JP120") (pin "1") (pinfunction "1_1") (pintype "passive"))
      (node (ref "JP420") (pin "1") (pinfunction "1_1") (pintype "passive"))
    )
    (net (code "49") (name "Net-(JP121-Pad1)") (class "Default")
      (node (ref "JP121") (pin "1") (pinfunction "1_1") (pintype "passive"))
      (node (ref "JP421") (pin "1") (pinfunction "1_1") (pintype "passive"))
    )
    (net (code "50") (name "Net-(JP122-Pad1)") (class "Default")
      (node (ref "JP122") (pin "1") (pinfunction "1_1") (pintype "passive"))
      (node (ref "JP422") (pin "1") (pinfunction "1_1") (pintype "passive"))
    )
    (net (code "51") (name "Net-(JP123-Pad1)") (class "Default")
      (node (ref "JP123") (pin "1") (pinfunction "1_1") (pintype "passive"))
      (node (ref "JP423") (pin "1") (pinfunction "1_1") (pintype "passive"))
    )
    (net (code "52") (name "Net-(JP124-Pad1)") (class "Default")
      (node (ref "JP124") (pin "1") (pinfunction "1_1") (pintype "passive"))
      (node (ref "JP424") (pin "1") (pinfunction "1_1") (pintype "passive"))
    )
    (net (code "53") (name "Net-(JP125-Pad1)") (class "Default")
      (node (ref "JP125") (pin "1") (pinfunction "1_1") (pintype "passive"))
      (node (ref "JP425") (pin "1") (pinfunction "1_1") (pintype "passive"))
    )
    (net (code "54") (name "Net-(JP126-Pad1)") (class "Default")
      (node (ref "JP126") (pin "1") (pinfunction "1_1") (pintype "passive"))
      (node (ref "JP426") (pin "1") (pinfunction "1_1") (pintype "passive"))
    )
    (net (code "55") (name "Net-(JP127-Pad1)") (class "Default")
      (node (ref "JP127") (pin "1") (pinfunction "1_1") (pintype "passive"))
      (node (ref "JP427") (pin "1") (pinfunction "1_1") (pintype "passive"))
    )
    (net (code "56") (name "Net-(JP128-Pad1)") (class "Default")
      (node (ref "JP128") (pin "1") (pinfunction "1_1") (pintype "passive"))
      (node (ref "JP428") (pin "1") (pinfunction "1_1") (pintype "passive"))
    )
    (net (code "57") (name "Net-(JP129-Pad1)") (class "Default")
      (node (ref "JP129") (pin "1") (pinfunction "1_1") (pintype "passive"))
      (node (ref "JP429") (pin "1") (pinfunction "1_1") (pintype "passive"))
    )
    (net (code "58") (name "Net-(JP130-Pad1)") (class "Default")
      (node (ref "JP130") (pin "1") (pinfunction "1_1") (pintype "passive"))
      (node (ref "JP430") (pin "1") (pinfunction "1_1") (pintype "passive"))
    )
    (net (code "59") (name "Net-(JP131-Pad1)") (class "Default")
      (node (ref "JP131") (pin "1") (pinfunction "1_1") (pintype "passive"))
      (node (ref "JP431") (pin "1") (pinfunction "1_1") (pintype "passive"))
    )
    (net (code "60") (name "Net-(JP132-Pad1)") (class "Default")
      (node (ref "JP132") (pin "1") (pinfunction "1_1") (pintype "passive"))
      (node (ref "JP432") (pin "1") (pinfunction "1_1") (pintype "passive"))
    )
    (net (code "61") (name "Net-(JP133-Pad1)") (class "Default")
      (node (ref "JP133") (pin "1") (pinfunction "1_1") (pintype "passive"))
      (node (ref "JP433") (pin "1") (pinfunction "1_1") (pintype "passive"))
    )
    (net (code "62") (name "Net-(JP134-Pad1)") (class "Default")
      (node (ref "JP134") (pin "1") (pinfunction "1_1") (pintype "passive"))
      (node (ref "JP434") (pin "1") (pinfunction "1_1") (pintype "passive"))
    )
    (net (code "63") (name "Net-(JP135-Pad1)") (class "Default")
      (node (ref "JP135") (pin "1") (pinfunction "1_1") (pintype "passive"))
      (node (ref "JP435") (pin "1") (pinfunction "1_1") (pintype "passive"))
    )
    (net (code "64") (name "Net-(JP136-Pad1)") (class "Default")
      (node (ref "JP136") (pin "1") (pinfunction "1_1") (pintype "passive"))
      (node (ref "JP436") (pin "1") (pinfunction "1_1") (pintype "passive"))
    )
    (net (code "65") (name "Net-(JP137-Pad1)") (class "Default")
      (node (ref "JP137") (pin "1") (pinfunction "1_1") (pintype "passive"))
      (node (ref "JP437") (pin "1") (pinfunction "1_1") (pintype "passive"))
    )
    (net (code "66") (name "Net-(JP138-Pad1)") (class "Default")
      (node (ref "JP138") (pin "1") (pinfunction "1_1") (pintype "passive"))
      (node (ref "JP438") (pin "1") (pinfunction "1_1") (pintype "passive"))
    )
    (net (code "67") (name "Net-(JP139-Pad1)") (class "Default")
      (node (ref "JP139") (pin "1") (pinfunction "1_1") (pintype "passive"))
      (node (ref "JP439") (pin "1") (pinfunction "1_1") (pintype "passive"))
    )
    (net (code "68") (name "Net-(JP140-Pad1)") (class "Default")
      (node (ref "JP140") (pin "1") (pinfunction "1_1") (pintype "passive"))
      (node (ref "JP440") (pin "1") (pinfunction "1_1") (pintype "passive"))
    )
    (net (code "69") (name "Net-(JP141-Pad1)") (class "Default")
      (node (ref "JP141") (pin "1") (pinfunction "1_1") (pintype "passive"))
      (node (ref "JP441") (pin "1") (pinfunction "1_1") (pintype "passive"))
    )
    (net (code "70") (name "Net-(JP142-Pad1)") (class "Default")
      (node (ref "JP142") (pin "1") (pinfunction "1_1") (pintype "passive"))
      (node (ref "JP442") (pin "1") (pinfunction "1_1") (pintype "passive"))
    )
    (net (code "71") (name "Net-(JP143-Pad1)") (class "Default")
      (node (ref "JP143") (pin "1") (pinfunction "1_1") (pintype "passive"))
      (node (ref "JP443") (pin "1") (pinfunction "1_1") (pintype "passive"))
    )
    (net (code "72") (name "Net-(JP144-Pad1)") (class "Default")
      (node (ref "JP144") (pin "1") (pinfunction "1_1") (pintype "passive"))
      (node (ref "JP444") (pin "1") (pinfunction "1_1") (pintype "passive"))
    )
    (net (code "73") (name "Net-(JP145-Pad1)") (class "Default")
      (node (ref "JP145") (pin "1") (pinfunction "1_1") (pintype "passive"))
      (node (ref "JP445") (pin "1") (pinfunction "1_1") (pintype "passive"))
    )
    (net (code "74") (name "Net-(JP146-Pad1)") (class "Default")
      (node (ref "JP146") (pin "1") (pinfunction "1_1") (pintype "passive"))
      (node (ref "JP446") (pin "1") (pinfunction "1_1") (pintype "passive"))
    )
    (net (code "75") (name "Net-(JP147-Pad1)") (class "Default")
      (node (ref "JP147") (pin "1") (pinfunction "1_1") (pintype "passive"))
      (node (ref "JP447") (pin "1") (pinfunction "1_1") (pintype "passive"))
    )
    (net (code "76") (name "Net-(JP148-Pad1)") (class "Default")
      (node (ref "JP148") (pin "1") (pinfunction "1_1") (pintype "passive"))
      (node (ref "JP448") (pin "1") (pinfunction "1_1") (pintype "passive"))
    )
    (net (code "77") (name "Net-(JP149-Pad1)") (class "Default")
      (node (ref "JP149") (pin "1") (pinfunction "1_1") (pintype "passive"))
      (node (ref "JP449") (pin "1") (pinfunction "1_1") (pintype "passive"))
    )
    (net (code "78") (name "Net-(JP150-Pad1)") (class "Default")
      (node (ref "JP150") (pin "1") (pinfunction "1_1") (pintype "passive"))
      (node (ref "JP450") (pin "1") (pinfunction "1_1") (pintype "passive"))
    )
    (net (code "79") (name "Net-(JP151-Pad1)") (class "Default")
      (node (ref "JP151") (pin "1") (pinfunction "1_1") (pintype "passive"))
      (node (ref "JP451") (pin "1") (pinfunction "1_1") (pintype "passive"))
    )
    (net (code "80") (name "Net-(JP152-Pad1)") (class "Default")
      (node (ref "JP152") (pin "1") (pinfunction "1_1") (pintype "passive"))
      (node (ref "JP452") (pin "1") (pinfunction "1_1") (pintype "passive"))
    )
    (net (code "81") (name "Net-(JP153-Pad1)") (class "Default")
      (node (ref "JP153") (pin "1") (pinfunction "1_1") (pintype "passive"))
      (node (ref "JP453") (pin "1") (pinfunction "1_1") (pintype "passive"))
    )
    (net (code "82") (name "Net-(JP154-Pad1)") (class "Default")
      (node (ref "JP154") (pin "1") (pinfunction "1_1") (pintype "passive"))
      (node (ref "JP454") (pin "1") (pinfunction "1_1") (pintype "passive"))
    )
    (net (code "83") (name "Net-(JP155-Pad1)") (class "Default")
      (node (ref "JP155") (pin "1") (pinfunction "1_1") (pintype "passive"))
      (node (ref "JP455") (pin "1") (pinfunction "1_1") (pintype "passive"))
    )
    (net (code "84") (name "Net-(JP156-Pad1)") (class "Default")
      (node (ref "JP156") (pin "1") (pinfunction "1_1") (pintype "passive"))
      (node (ref "JP456") (pin "1") (pinfunction "1_1") (pintype "passive"))
    )
    (net (code "85") (name "Net-(JP157-Pad1)") (class "Default")
      (node (ref "JP157") (pin "1") (pinfunction "1_1") (pintype "passive"))
      (node (ref "JP457") (pin "1") (pinfunction "1_1") (pintype "passive"))
    )
    (net (code "86") (name "Net-(JP158-Pad1)") (class "Default")
      (node (ref "JP158") (pin "1") (pinfunction "1_1") (pintype "passive"))
      (node (ref "JP458") (pin "1") (pinfunction "1_1") (pintype "passive"))
    )
    (net (code "87") (name "Net-(JP159-Pad1)") (class "Default")
      (node (ref "JP159") (pin "1") (pinfunction "1_1") (pintype "passive"))
      (node (ref "JP459") (pin "1") (pinfunction "1_1") (pintype "passive"))
    )
    (net (code "88") (name "Net-(JP160-Pad1)") (class "Default")
      (node (ref "JP160") (pin "1") (pinfunction "1_1") (pintype "passive"))
      (node (ref "JP460") (pin "1") (pinfunction "1_1") (pintype "passive"))
    )
    (net (code "89") (name "Net-(JP161-Pad1)") (class "Default")
      (node (ref "JP161") (pin "1") (pinfunction "1_1") (pintype "passive"))
      (node (ref "JP461") (pin "1") (pinfunction "1_1") (pintype "passive"))
    )
    (net (code "90") (name "Net-(JP162-Pad1)") (class "Default")
      (node (ref "JP162") (pin "1") (pinfunction "1_1") (pintype "passive"))
      (node (ref "JP462") (pin "1") (pinfunction "1_1") (pintype "passive"))
    )
    (net (code "91") (name "Net-(JP163-Pad1)") (class "Default")
      (node (ref "JP163") (pin "1") (pinfunction "1_1") (pintype "passive"))
      (node (ref "JP463") (pin "1") (pinfunction "1_1") (pintype "passive"))
    )
    (net (code "92") (name "Net-(JP164-Pad1)") (class "Default")
      (node (ref "JP164") (pin "1") (pinfunction "1_1") (pintype "passive"))
      (node (ref "JP464") (pin "1") (pinfunction "1_1") (pintype "passive"))
    )
    (net (code "93") (name "Net-(JP165-Pad1)") (class "Default")
      (node (ref "JP165") (pin "1") (pinfunction "1_1") (pintype "passive"))
      (node (ref "JP465") (pin "1") (pinfunction "1_1") (pintype "passive"))
    )
    (net (code "94") (name "Net-(JP166-Pad1)") (class "Default")
      (node (ref "JP166") (pin "1") (pinfunction "1_1") (pintype "passive"))
      (node (ref "JP466") (pin "1") (pinfunction "1_1") (pintype "passive"))
    )
    (net (code "95") (name "Net-(JP167-Pad1)") (class "Default")
      (node (ref "JP167") (pin "1") (pinfunction "1_1") (pintype "passive"))
      (node (ref "JP467") (pin "1") (pinfunction "1_1") (pintype "passive"))
    )
    (net (code "96") (name "Net-(JP168-Pad1)") (class "Default")
      (node (ref "JP168") (pin "1") (pinfunction "1_1") (pintype "passive"))
      (node (ref "JP468") (pin "1") (pinfunction "1_1") (pintype "passive"))
    )
    (net (code "97") (name "Net-(JP169-Pad1)") (class "Default")
      (node (ref "JP169") (pin "1") (pinfunction "1_1") (pintype "passive"))
      (node (ref "JP469") (pin "1") (pinfunction "1_1") (pintype "passive"))
    )
    (net (code "98") (name "Net-(JP170-Pad1)") (class "Default")
      (node (ref "JP170") (pin "1") (pinfunction "1_1") (pintype "passive"))
      (node (ref "JP470") (pin "1") (pinfunction "1_1") (pintype "passive"))
    )
    (net (code "99") (name "Net-(JP171-Pad1)") (class "Default")
      (node (ref "JP171") (pin "1") (pinfunction "1_1") (pintype "passive"))
      (node (ref "JP471") (pin "1") (pinfunction "1_1") (pintype "passive"))
    )
    (net (code "100") (name "Net-(JP172-Pad1)") (class "Default")
      (node (ref "JP172") (pin "1") (pinfunction "1_1") (pintype "passive"))
      (node (ref "JP472") (pin "1") (pinfunction "1_1") (pintype "passive"))
    )
    (net (code "101") (name "Net-(JP173-Pad1)") (class "Default")
      (node (ref "JP173") (pin "1") (pinfunction "1_1") (pintype "passive"))
      (node (ref "JP473") (pin "1") (pinfunction "1_1") (pintype "passive"))
    )
    (net (code "102") (name "Net-(JP174-Pad1)") (class "Default")
      (node (ref "JP174") (pin "1") (pinfunction "1_1") (pintype "passive"))
      (node (ref "JP474") (pin "1") (pinfunction "1_1") (pintype "passive"))
    )
    (net (code "103") (name "Net-(JP175-Pad1)") (class "Default")
      (node (ref "JP175") (pin "1") (pinfunction "1_1") (pintype "passive"))
      (node (ref "JP475") (pin "1") (pinfunction "1_1") (pintype "passive"))
    )
    (net (code "104") (name "Net-(JP176-Pad1)") (class "Default")
      (node (ref "JP176") (pin "1") (pinfunction "1_1") (pintype "passive"))
      (node (ref "JP476") (pin "1") (pinfunction "1_1") (pintype "passive"))
    )
    (net (code "105") (name "Net-(JP177-Pad1)") (class "Default")
      (node (ref "JP177") (pin "1") (pinfunction "1_1") (pintype "passive"))
      (node (ref "JP477") (pin "1") (pinfunction "1_1") (pintype "passive"))
    )
    (net (code "106") (name "Net-(JP178-Pad1)") (class "Default")
      (node (ref "JP178") (pin "1") (pinfunction "1_1") (pintype "passive"))
      (node (ref "JP478") (pin "1") (pinfunction "1_1") (pintype "passive"))
    )
    (net (code "107") (name "Net-(JP179-Pad1)") (class "Default")
      (node (ref "JP179") (pin "1") (pinfunction "1_1") (pintype "passive"))
      (node (ref "JP479") (pin "1") (pinfunction "1_1") (pintype "passive"))
    )
    (net (code "108") (name "Net-(JP180-Pad1)") (class "Default")
      (node (ref "JP180") (pin "1") (pinfunction "1_1") (pintype "passive"))
      (node (ref "JP480") (pin "1") (pinfunction "1_1") (pintype "passive"))
    )
    (net (code "109") (name "Net-(JP181-Pad1)") (class "Default")
      (node (ref "JP181") (pin "1") (pinfunction "1_1") (pintype "passive"))
      (node (ref "JP481") (pin "1") (pinfunction "1_1") (pintype "passive"))
    )
    (net (code "110") (name "Net-(JP182-Pad1)") (class "Default")
      (node (ref "JP182") (pin "1") (pinfunction "1_1") (pintype "passive"))
      (node (ref "JP482") (pin "1") (pinfunction "1_1") (pintype "passive"))
    )
    (net (code "111") (name "Net-(JP183-Pad1)") (class "Default")
      (node (ref "JP183") (pin "1") (pinfunction "1_1") (pintype "passive"))
      (node (ref "JP483") (pin "1") (pinfunction "1_1") (pintype "passive"))
    )
    (net (code "112") (name "Net-(JP184-Pad1)") (class "Default")
      (node (ref "JP184") (pin "1") (pinfunction "1_1") (pintype "passive"))
      (node (ref "JP484") (pin "1") (pinfunction "1_1") (pintype "passive"))
    )
    (net (code "113") (name "Net-(JP185-Pad1)") (class "Default")
      (node (ref "JP185") (pin "1") (pinfunction "1_1") (pintype "passive"))
      (node (ref "JP485") (pin "1") (pinfunction "1_1") (pintype "passive"))
    )
    (net (code "114") (name "Net-(JP186-Pad1)") (class "Default")
      (node (ref "JP186") (pin "1") (pinfunction "1_1") (pintype "passive"))
      (node (ref "JP486") (pin "1") (pinfunction "1_1") (pintype "passive"))
    )
    (net (code "115") (name "Net-(JP187-Pad1)") (class "Default")
      (node (ref "JP187") (pin "1") (pinfunction "1_1") (pintype "passive"))
      (node (ref "JP487") (pin "1") (pinfunction "1_1") (pintype "passive"))
    )
    (net (code "116") (name "Net-(JP188-Pad1)") (class "Default")
      (node (ref "JP188") (pin "1") (pinfunction "1_1") (pintype "passive"))
      (node (ref "JP488") (pin "1") (pinfunction "1_1") (pintype "passive"))
    )
    (net (code "117") (name "Net-(JP189-Pad1)") (class "Default")
      (node (ref "JP189") (pin "1") (pinfunction "1_1") (pintype "passive"))
      (node (ref "JP489") (pin "1") (pinfunction "1_1") (pintype "passive"))
    )
    (net (code "118") (name "Net-(JP190-Pad1)") (class "Default")
      (node (ref "JP190") (pin "1") (pinfunction "1_1") (pintype "passive"))
      (node (ref "JP490") (pin "1") (pinfunction "1_1") (pintype "passive"))
    )
    (net (code "119") (name "Net-(JP191-Pad1)") (class "Default")
      (node (ref "JP191") (pin "1") (pinfunction "1_1") (pintype "passive"))
      (node (ref "JP491") (pin "1") (pinfunction "1_1") (pintype "passive"))
    )
    (net (code "120") (name "Net-(JP192-Pad1)") (class "Default")
      (node (ref "JP192") (pin "1") (pinfunction "1_1") (pintype "passive"))
      (node (ref "JP492") (pin "1") (pinfunction "1_1") (pintype "passive"))
    )
    (net (code "121") (name "Net-(JP193-Pad1)") (class "Default")
      (node (ref "JP193") (pin "1") (pinfunction "1_1") (pintype "passive"))
      (node (ref "JP493") (pin "1") (pinfunction "1_1") (pintype "passive"))
    )
    (net (code "122") (name "Net-(JP194-Pad1)") (class "Default")
      (node (ref "JP194") (pin "1") (pinfunction "1_1") (pintype "passive"))
      (node (ref "JP494") (pin "1") (pinfunction "1_1") (pintype "passive"))
    )
    (net (code "123") (name "Net-(JP195-Pad1)") (class "Default")
      (node (ref "JP195") (pin "1") (pinfunction "1_1") (pintype "passive"))
      (node (ref "JP495") (pin "1") (pinfunction "1_1") (pintype "passive"))
    )
    (net (code "124") (name "Net-(JP196-Pad1)") (class "Default")
      (node (ref "JP196") (pin "1") (pinfunction "1_1") (pintype "passive"))
      (node (ref "JP496") (pin "1") (pinfunction "1_1") (pintype "passive"))
    )
    (net (code "125") (name "Net-(JP197-Pad1)") (class "Default")
      (node (ref "JP197") (pin "1") (pinfunction "1_1") (pintype "passive"))
      (node (ref "JP497") (pin "1") (pinfunction "1_1") (pintype "passive"))
    )
    (net (code "126") (name "Net-(JP198-Pad1)") (class "Default")
      (node (ref "JP198") (pin "1") (pinfunction "1_1") (pintype "passive"))
      (node (ref "JP498") (pin "1") (pinfunction "1_1") (pintype "passive"))
    )
    (net (code "127") (name "Net-(JP199-Pad1)") (class "Default")
      (node (ref "JP199") (pin "1") (pinfunction "1_1") (pintype "passive"))
      (node (ref "JP499") (pin "1") (pinfunction "1_1") (pintype "passive"))
    )
    (net (code "128") (name "Net-(JP200-Pad1)") (class "Default")
      (node (ref "JP200") (pin "1") (pinfunction "1_1") (pintype "passive"))
      (node (ref "JP500") (pin "1") (pinfunction "1_1") (pintype "passive"))
    )
    (net (code "129") (name "Net-(JP201-Pad1)") (class "Default")
      (node (ref "JP201") (pin "1") (pinfunction "1_1") (pintype "passive"))
      (node (ref "JP501") (pin "1") (pinfunction "1_1") (pintype "passive"))
    )
    (net (code "130") (name "Net-(JP202-Pad1)") (class "Default")
      (node (ref "JP202") (pin "1") (pinfunction "1_1") (pintype "passive"))
      (node (ref "JP502") (pin "1") (pinfunction "1_1") (pintype "passive"))
    )
    (net (code "131") (name "Net-(JP203-Pad1)") (class "Default")
      (node (ref "JP203") (pin "1") (pinfunction "1_1") (pintype "passive"))
      (node (ref "JP503") (pin "1") (pinfunction "1_1") (pintype "passive"))
    )
    (net (code "132") (name "Net-(JP204-Pad1)") (class "Default")
      (node (ref "JP204") (pin "1") (pinfunction "1_1") (pintype "passive"))
      (node (ref "JP504") (pin "1") (pinfunction "1_1") (pintype "passive"))
    )
    (net (code "133") (name "Net-(JP205-Pad1)") (class "Default")
      (node (ref "JP205") (pin "1") (pinfunction "1_1") (pintype "passive"))
      (node (ref "JP505") (pin "1") (pinfunction "1_1") (pintype "passive"))
    )
    (net (code "134") (name "Net-(JP206-Pad1)") (class "Default")
      (node (ref "JP206") (pin "1") (pinfunction "1_1") (pintype "passive"))
      (node (ref "JP506") (pin "1") (pinfunction "1_1") (pintype "passive"))
    )
    (net (code "135") (name "Net-(JP207-Pad1)") (class "Default")
      (node (ref "JP207") (pin "1") (pinfunction "1_1") (pintype "passive"))
      (node (ref "JP507") (pin "1") (pinfunction "1_1") (pintype "passive"))
    )
    (net (code "136") (name "Net-(JP208-Pad1)") (class "Default")
      (node (ref "JP208") (pin "1") (pinfunction "1_1") (pintype "passive"))
      (node (ref "JP508") (pin "1") (pinfunction "1_1") (pintype "passive"))
    )
    (net (code "137") (name "Net-(JP209-Pad1)") (class "Default")
      (node (ref "JP209") (pin "1") (pinfunction "1_1") (pintype "passive"))
      (node (ref "JP509") (pin "1") (pinfunction "1_1") (pintype "passive"))
    )
    (net (code "138") (name "Net-(JP210-Pad1)") (class "Default")
      (node (ref "JP210") (pin "1") (pinfunction "1_1") (pintype "passive"))
      (node (ref "JP510") (pin "1") (pinfunction "1_1") (pintype "passive"))
    )
    (net (code "139") (name "Net-(JP211-Pad1)") (class "Default")
      (node (ref "JP211") (pin "1") (pinfunction "1_1") (pintype "passive"))
      (node (ref "JP511") (pin "1") (pinfunction "1_1") (pintype "passive"))
    )
    (net (code "140") (name "Net-(JP212-Pad1)") (class "Default")
      (node (ref "JP212") (pin "1") (pinfunction "1_1") (pintype "passive"))
      (node (ref "JP512") (pin "1") (pinfunction "1_1") (pintype "passive"))
    )
    (net (code "141") (name "Net-(JP213-Pad1)") (class "Default")
      (node (ref "JP213") (pin "1") (pinfunction "1_1") (pintype "passive"))
      (node (ref "JP513") (pin "1") (pinfunction "1_1") (pintype "passive"))
    )
    (net (code "142") (name "Net-(JP214-Pad1)") (class "Default")
      (node (ref "JP214") (pin "1") (pinfunction "1_1") (pintype "passive"))
      (node (ref "JP514") (pin "1") (pinfunction "1_1") (pintype "passive"))
    )
    (net (code "143") (name "Net-(JP215-Pad1)") (class "Default")
      (node (ref "JP215") (pin "1") (pinfunction "1_1") (pintype "passive"))
      (node (ref "JP515") (pin "1") (pinfunction "1_1") (pintype "passive"))
    )
    (net (code "144") (name "Net-(JP216-Pad1)") (class "Default")
      (node (ref "JP216") (pin "1") (pinfunction "1_1") (pintype "passive"))
      (node (ref "JP516") (pin "1") (pinfunction "1_1") (pintype "passive"))
    )
    (net (code "145") (name "Net-(JP217-Pad1)") (class "Default")
      (node (ref "JP217") (pin "1") (pinfunction "1_1") (pintype "passive"))
      (node (ref "JP517") (pin "1") (pinfunction "1_1") (pintype "passive"))
    )
    (net (code "146") (name "Net-(JP218-Pad1)") (class "Default")
      (node (ref "JP218") (pin "1") (pinfunction "1_1") (pintype "passive"))
      (node (ref "JP518") (pin "1") (pinfunction "1_1") (pintype "passive"))
    )
    (net (code "147") (name "Net-(JP219-Pad1)") (class "Default")
      (node (ref "JP219") (pin "1") (pinfunction "1_1") (pintype "passive"))
      (node (ref "JP519") (pin "1") (pinfunction "1_1") (pintype "passive"))
    )
    (net (code "148") (name "Net-(JP220-Pad1)") (class "Default")
      (node (ref "JP220") (pin "1") (pinfunction "1_1") (pintype "passive"))
      (node (ref "JP520") (pin "1") (pinfunction "1_1") (pintype "passive"))
    )
    (net (code "149") (name "Net-(JP221-Pad1)") (class "Default")
      (node (ref "JP221") (pin "1") (pinfunction "1_1") (pintype "passive"))
      (node (ref "JP521") (pin "1") (pinfunction "1_1") (pintype "passive"))
    )
    (net (code "150") (name "Net-(JP222-Pad1)") (class "Default")
      (node (ref "JP222") (pin "1") (pinfunction "1_1") (pintype "passive"))
      (node (ref "JP522") (pin "1") (pinfunction "1_1") (pintype "passive"))
    )
    (net (code "151") (name "Net-(JP223-Pad1)") (class "Default")
      (node (ref "JP223") (pin "1") (pinfunction "1_1") (pintype "passive"))
      (node (ref "JP523") (pin "1") (pinfunction "1_1") (pintype "passive"))
    )
    (net (code "152") (name "Net-(JP224-Pad1)") (class "Default")
      (node (ref "JP224") (pin "1") (pinfunction "1_1") (pintype "passive"))
      (node (ref "JP524") (pin "1") (pinfunction "1_1") (pintype "passive"))
    )
    (net (code "153") (name "Net-(JP225-Pad1)") (class "Default")
      (node (ref "JP225") (pin "1") (pinfunction "1_1") (pintype "passive"))
      (node (ref "JP525") (pin "1") (pinfunction "1_1") (pintype "passive"))
    )
    (net (code "154") (name "Net-(JP226-Pad1)") (class "Default")
      (node (ref "JP226") (pin "1") (pinfunction "1_1") (pintype "passive"))
      (node (ref "JP526") (pin "1") (pinfunction "1_1") (pintype "passive"))
    )
    (net (code "155") (name "Net-(JP227-Pad1)") (class "Default")
      (node (ref "JP227") (pin "1") (pinfunction "1_1") (pintype "passive"))
      (node (ref "JP527") (pin "1") (pinfunction "1_1") (pintype "passive"))
    )
    (net (code "156") (name "Net-(JP228-Pad1)") (class "Default")
      (node (ref "JP228") (pin "1") (pinfunction "1_1") (pintype "passive"))
      (node (ref "JP528") (pin "1") (pinfunction "1_1") (pintype "passive"))
    )
    (net (code "157") (name "Net-(JP229-Pad1)") (class "Default")
      (node (ref "JP229") (pin "1") (pinfunction "1_1") (pintype "passive"))
      (node (ref "JP529") (pin "1") (pinfunction "1_1") (pintype "passive"))
    )
    (net (code "158") (name "Net-(JP230-Pad1)") (class "Default")
      (node (ref "JP230") (pin "1") (pinfunction "1_1") (pintype "passive"))
      (node (ref "JP530") (pin "1") (pinfunction "1_1") (pintype "passive"))
    )
    (net (code "159") (name "Net-(JP231-Pad1)") (class "Default")
      (node (ref "JP231") (pin "1") (pinfunction "1_1") (pintype "passive"))
      (node (ref "JP531") (pin "1") (pinfunction "1_1") (pintype "passive"))
    )
    (net (code "160") (name "Net-(JP232-Pad1)") (class "Default")
      (node (ref "JP232") (pin "1") (pinfunction "1_1") (pintype "passive"))
      (node (ref "JP532") (pin "1") (pinfunction "1_1") (pintype "passive"))
    )
    (net (code "161") (name "Net-(JP233-Pad1)") (class "Default")
      (node (ref "JP233") (pin "1") (pinfunction "1_1") (pintype "passive"))
      (node (ref "JP533") (pin "1") (pinfunction "1_1") (pintype "passive"))
    )
    (net (code "162") (name "Net-(JP234-Pad1)") (class "Default")
      (node (ref "JP234") (pin "1") (pinfunction "1_1") (pintype "passive"))
      (node (ref "JP534") (pin "1") (pinfunction "1_1") (pintype "passive"))
    )
    (net (code "163") (name "Net-(JP235-Pad1)") (class "Default")
      (node (ref "JP235") (pin "1") (pinfunction "1_1") (pintype "passive"))
      (node (ref "JP535") (pin "1") (pinfunction "1_1") (pintype "passive"))
    )
    (net (code "164") (name "Net-(JP236-Pad1)") (class "Default")
      (node (ref "JP236") (pin "1") (pinfunction "1_1") (pintype "passive"))
      (node (ref "JP536") (pin "1") (pinfunction "1_1") (pintype "passive"))
    )
    (net (code "165") (name "Net-(JP237-Pad1)") (class "Default")
      (node (ref "JP237") (pin "1") (pinfunction "1_1") (pintype "passive"))
      (node (ref "JP537") (pin "1") (pinfunction "1_1") (pintype "passive"))
    )
    (net (code "166") (name "Net-(JP238-Pad1)") (class "Default")
      (node (ref "JP238") (pin "1") (pinfunction "1_1") (pintype "passive"))
      (node (ref "JP538") (pin "1") (pinfunction "1_1") (pintype "passive"))
    )
    (net (code "167") (name "Net-(JP239-Pad1)") (class "Default")
      (node (ref "JP239") (pin "1") (pinfunction "1_1") (pintype "passive"))
      (node (ref "JP539") (pin "1") (pinfunction "1_1") (pintype "passive"))
    )
    (net (code "168") (name "Net-(JP240-Pad1)") (class "Default")
      (node (ref "JP240") (pin "1") (pinfunction "1_1") (pintype "passive"))
      (node (ref "JP540") (pin "1") (pinfunction "1_1") (pintype "passive"))
    )
    (net (code "169") (name "Net-(JP241-Pad1)") (class "Default")
      (node (ref "JP241") (pin "1") (pinfunction "1_1") (pintype "passive"))
      (node (ref "JP541") (pin "1") (pinfunction "1_1") (pintype "passive"))
    )
    (net (code "170") (name "Net-(JP242-Pad1)") (class "Default")
      (node (ref "JP242") (pin "1") (pinfunction "1_1") (pintype "passive"))
      (node (ref "JP542") (pin "1") (pinfunction "1_1") (pintype "passive"))
    )
    (net (code "171") (name "Net-(JP243-Pad1)") (class "Default")
      (node (ref "JP243") (pin "1") (pinfunction "1_1") (pintype "passive"))
      (node (ref "JP543") (pin "1") (pinfunction "1_1") (pintype "passive"))
    )
    (net (code "172") (name "Net-(JP244-Pad1)") (class "Default")
      (node (ref "JP244") (pin "1") (pinfunction "1_1") (pintype "passive"))
      (node (ref "JP544") (pin "1") (pinfunction "1_1") (pintype "passive"))
    )
    (net (code "173") (name "Net-(JP245-Pad1)") (class "Default")
      (node (ref "JP245") (pin "1") (pinfunction "1_1") (pintype "passive"))
      (node (ref "JP545") (pin "1") (pinfunction "1_1") (pintype "passive"))
    )
    (net (code "174") (name "Net-(JP246-Pad1)") (class "Default")
      (node (ref "JP246") (pin "1") (pinfunction "1_1") (pintype "passive"))
      (node (ref "JP546") (pin "1") (pinfunction "1_1") (pintype "passive"))
    )
    (net (code "175") (name "Net-(JP247-Pad1)") (class "Default")
      (node (ref "JP247") (pin "1") (pinfunction "1_1") (pintype "passive"))
      (node (ref "JP547") (pin "1") (pinfunction "1_1") (pintype "passive"))
    )
    (net (code "176") (name "Net-(JP248-Pad1)") (class "Default")
      (node (ref "JP248") (pin "1") (pinfunction "1_1") (pintype "passive"))
      (node (ref "JP548") (pin "1") (pinfunction "1_1") (pintype "passive"))
    )
    (net (code "177") (name "Net-(JP249-Pad1)") (class "Default")
      (node (ref "JP249") (pin "1") (pinfunction "1_1") (pintype "passive"))
      (node (ref "JP549") (pin "1") (pinfunction "1_1") (pintype "passive"))
    )
    (net (code "178") (name "Net-(JP250-Pad1)") (class "Default")
      (node (ref "JP250") (pin "1") (pinfunction "1_1") (pintype "passive"))
      (node (ref "JP550") (pin "1") (pinfunction "1_1") (pintype "passive"))
    )
    (net (code "179") (name "Net-(JP251-Pad1)") (class "Default")
      (node (ref "JP251") (pin "1") (pinfunction "1_1") (pintype "passive"))
      (node (ref "JP551") (pin "1") (pinfunction "1_1") (pintype "passive"))
    )
    (net (code "180") (name "Net-(JP252-Pad1)") (class "Default")
      (node (ref "JP252") (pin "1") (pinfunction "1_1") (pintype "passive"))
      (node (ref "JP552") (pin "1") (pinfunction "1_1") (pintype "passive"))
    )
    (net (code "181") (name "Net-(JP253-Pad1)") (class "Default")
      (node (ref "JP253") (pin "1") (pinfunction "1_1") (pintype "passive"))
      (node (ref "JP553") (pin "1") (pinfunction "1_1") (pintype "passive"))
    )
    (net (code "182") (name "Net-(JP254-Pad1)") (class "Default")
      (node (ref "JP254") (pin "1") (pinfunction "1_1") (pintype "passive"))
      (node (ref "JP554") (pin "1") (pinfunction "1_1") (pintype "passive"))
    )
    (net (code "183") (name "Net-(JP255-Pad1)") (class "Default")
      (node (ref "JP255") (pin "1") (pinfunction "1_1") (pintype "passive"))
      (node (ref "JP555") (pin "1") (pinfunction "1_1") (pintype "passive"))
    )
    (net (code "184") (name "Net-(JP256-Pad1)") (class "Default")
      (node (ref "JP256") (pin "1") (pinfunction "1_1") (pintype "passive"))
      (node (ref "JP556") (pin "1") (pinfunction "1_1") (pintype "passive"))
    )
    (net (code "185") (name "Net-(JP257-Pad1)") (class "Default")
      (node (ref "JP257") (pin "1") (pinfunction "1_1") (pintype "passive"))
      (node (ref "JP557") (pin "1") (pinfunction "1_1") (pintype "passive"))
    )
    (net (code "186") (name "Net-(JP258-Pad1)") (class "Default")
      (node (ref "JP258") (pin "1") (pinfunction "1_1") (pintype "passive"))
      (node (ref "JP558") (pin "1") (pinfunction "1_1") (pintype "passive"))
    )
    (net (code "187") (name "Net-(JP259-Pad1)") (class "Default")
      (node (ref "JP259") (pin "1") (pinfunction "1_1") (pintype "passive"))
      (node (ref "JP559") (pin "1") (pinfunction "1_1") (pintype "passive"))
    )
    (net (code "188") (name "Net-(JP260-Pad1)") (class "Default")
      (node (ref "JP260") (pin "1") (pinfunction "1_1") (pintype "passive"))
      (node (ref "JP560") (pin "1") (pinfunction "1_1") (pintype "passive"))
    )
    (net (code "189") (name "Net-(JP261-Pad1)") (class "Default")
      (node (ref "JP261") (pin "1") (pinfunction "1_1") (pintype "passive"))
      (node (ref "JP561") (pin "1") (pinfunction "1_1") (pintype "passive"))
    )
    (net (code "190") (name "Net-(JP262-Pad1)") (class "Default")
      (node (ref "JP262") (pin "1") (pinfunction "1_1") (pintype "passive"))
      (node (ref "JP562") (pin "1") (pinfunction "1_1") (pintype "passive"))
    )
    (net (code "191") (name "Net-(JP263-Pad1)") (class "Default")
      (node (ref "JP263") (pin "1") (pinfunction "1_1") (pintype "passive"))
      (node (ref "JP563") (pin "1") (pinfunction "1_1") (pintype "passive"))
    )
    (net (code "192") (name "Net-(JP264-Pad1)") (class "Default")
      (node (ref "JP264") (pin "1") (pinfunction "1_1") (pintype "passive"))
      (node (ref "JP564") (pin "1") (pinfunction "1_1") (pintype "passive"))
    )
    (net (code "193") (name "Net-(JP265-Pad1)") (class "Default")
      (node (ref "JP265") (pin "1") (pinfunction "1_1") (pintype "passive"))
      (node (ref "JP565") (pin "1") (pinfunction "1_1") (pintype "passive"))
    )
    (net (code "194") (name "Net-(JP266-Pad1)") (class "Default")
      (node (ref "JP266") (pin "1") (pinfunction "1_1") (pintype "passive"))
      (node (ref "JP566") (pin "1") (pinfunction "1_1") (pintype "passive"))
    )
    (net (code "195") (name "Net-(JP267-Pad1)") (class "Default")
      (node (ref "JP267") (pin "1") (pinfunction "1_1") (pintype "passive"))
      (node (ref "JP567") (pin "1") (pinfunction "1_1") (pintype "passive"))
    )
    (net (code "196") (name "Net-(JP268-Pad1)") (class "Default")
      (node (ref "JP268") (pin "1") (pinfunction "1_1") (pintype "passive"))
      (node (ref "JP568") (pin "1") (pinfunction "1_1") (pintype "passive"))
    )
    (net (code "197") (name "Net-(JP269-Pad1)") (class "Default")
      (node (ref "JP269") (pin "1") (pinfunction "1_1") (pintype "passive"))
      (node (ref "JP569") (pin "1") (pinfunction "1_1") (pintype "passive"))
    )
    (net (code "198") (name "Net-(JP270-Pad1)") (class "Default")
      (node (ref "JP270") (pin "1") (pinfunction "1_1") (pintype "passive"))
      (node (ref "JP570") (pin "1") (pinfunction "1_1") (pintype "passive"))
    )
    (net (code "199") (name "Net-(JP271-Pad1)") (class "Default")
      (node (ref "JP271") (pin "1") (pinfunction "1_1") (pintype "passive"))
      (node (ref "JP571") (pin "1") (pinfunction "1_1") (pintype "passive"))
    )
    (net (code "200") (name "Net-(JP272-Pad1)") (class "Default")
      (node (ref "JP272") (pin "1") (pinfunction "1_1") (pintype "passive"))
      (node (ref "JP572") (pin "1") (pinfunction "1_1") (pintype "passive"))
    )
    (net (code "201") (name "Net-(JP273-Pad1)") (class "Default")
      (node (ref "JP273") (pin "1") (pinfunction "1_1") (pintype "passive"))
      (node (ref "JP573") (pin "1") (pinfunction "1_1") (pintype "passive"))
    )
    (net (code "202") (name "Net-(JP274-Pad1)") (class "Default")
      (node (ref "JP274") (pin "1") (pinfunction "1_1") (pintype "passive"))
      (node (ref "JP574") (pin "1") (pinfunction "1_1") (pintype "passive"))
    )
    (net (code "203") (name "Net-(JP275-Pad1)") (class "Default")
      (node (ref "JP275") (pin "1") (pinfunction "1_1") (pintype "passive"))
      (node (ref "JP575") (pin "1") (pinfunction "1_1") (pintype "passive"))
    )
    (net (code "204") (name "Net-(JP276-Pad1)") (class "Default")
      (node (ref "JP276") (pin "1") (pinfunction "1_1") (pintype "passive"))
      (node (ref "JP576") (pin "1") (pinfunction "1_1") (pintype "passive"))
    )
    (net (code "205") (name "Net-(JP277-Pad1)") (class "Default")
      (node (ref "JP277") (pin "1") (pinfunction "1_1") (pintype "passive"))
      (node (ref "JP577") (pin "1") (pinfunction "1_1") (pintype "passive"))
    )
    (net (code "206") (name "Net-(JP278-Pad1)") (class "Default")
      (node (ref "JP278") (pin "1") (pinfunction "1_1") (pintype "passive"))
      (node (ref "JP578") (pin "1") (pinfunction "1_1") (pintype "passive"))
    )
    (net (code "207") (name "Net-(JP279-Pad1)") (class "Default")
      (node (ref "JP279") (pin "1") (pinfunction "1_1") (pintype "passive"))
      (node (ref "JP579") (pin "1") (pinfunction "1_1") (pintype "passive"))
    )
    (net (code "208") (name "Net-(JP280-Pad1)") (class "Default")
      (node (ref "JP280") (pin "1") (pinfunction "1_1") (pintype "passive"))
      (node (ref "JP580") (pin "1") (pinfunction "1_1") (pintype "passive"))
    )
    (net (code "209") (name "Net-(JP281-Pad1)") (class "Default")
      (node (ref "JP281") (pin "1") (pinfunction "1_1") (pintype "passive"))
      (node (ref "JP581") (pin "1") (pinfunction "1_1") (pintype "passive"))
    )
    (net (code "210") (name "Net-(JP282-Pad1)") (class "Default")
      (node (ref "JP282") (pin "1") (pinfunction "1_1") (pintype "passive"))
      (node (ref "JP582") (pin "1") (pinfunction "1_1") (pintype "passive"))
    )
    (net (code "211") (name "Net-(JP283-Pad1)") (class "Default")
      (node (ref "JP283") (pin "1") (pinfunction "1_1") (pintype "passive"))
      (node (ref "JP583") (pin "1") (pinfunction "1_1") (pintype "passive"))
    )
    (net (code "212") (name "Net-(JP284-Pad1)") (class "Default")
      (node (ref "JP284") (pin "1") (pinfunction "1_1") (pintype "passive"))
      (node (ref "JP584") (pin "1") (pinfunction "1_1") (pintype "passive"))
    )
    (net (code "213") (name "Net-(JP285-Pad1)") (class "Default")
      (node (ref "JP285") (pin "1") (pinfunction "1_1") (pintype "passive"))
      (node (ref "JP585") (pin "1") (pinfunction "1_1") (pintype "passive"))
    )
    (net (code "214") (name "Net-(JP286-Pad1)") (class "Default")
      (node (ref "JP286") (pin "1") (pinfunction "1_1") (pintype "passive"))
      (node (ref "JP586") (pin "1") (pinfunction "1_1") (pintype "passive"))
    )
    (net (code "215") (name "Net-(JP287-Pad1)") (class "Default")
      (node (ref "JP287") (pin "1") (pinfunction "1_1") (pintype "passive"))
      (node (ref "JP587") (pin "1") (pinfunction "1_1") (pintype "passive"))
    )
    (net (code "216") (name "Net-(JP288-Pad1)") (class "Default")
      (node (ref "JP288") (pin "1") (pinfunction "1_1") (pintype "passive"))
      (node (ref "JP588") (pin "1") (pinfunction "1_1") (pintype "passive"))
    )
    (net (code "217") (name "Net-(JP289-Pad1)") (class "Default")
      (node (ref "JP289") (pin "1") (pinfunction "1_1") (pintype "passive"))
      (node (ref "JP589") (pin "1") (pinfunction "1_1") (pintype "passive"))
    )
    (net (code "218") (name "Net-(JP290-Pad1)") (class "Default")
      (node (ref "JP290") (pin "1") (pinfunction "1_1") (pintype "passive"))
      (node (ref "JP590") (pin "1") (pinfunction "1_1") (pintype "passive"))
    )
    (net (code "219") (name "Net-(JP291-Pad1)") (class "Default")
      (node (ref "JP291") (pin "1") (pinfunction "1_1") (pintype "passive"))
      (node (ref "JP591") (pin "1") (pinfunction "1_1") (pintype "passive"))
    )
    (net (code "220") (name "Net-(JP292-Pad1)") (class "Default")
      (node (ref "JP292") (pin "1") (pinfunction "1_1") (pintype "passive"))
      (node (ref "JP592") (pin "1") (pinfunction "1_1") (pintype "passive"))
    )
    (net (code "221") (name "Net-(JP293-Pad1)") (class "Default")
      (node (ref "JP293") (pin "1") (pinfunction "1_1") (pintype "passive"))
      (node (ref "JP593") (pin "1") (pinfunction "1_1") (pintype "passive"))
    )
    (net (code "222") (name "Net-(JP294-Pad1)") (class "Default")
      (node (ref "JP294") (pin "1") (pinfunction "1_1") (pintype "passive"))
      (node (ref "JP594") (pin "1") (pinfunction "1_1") (pintype "passive"))
    )
    (net (code "223") (name "Net-(JP295-Pad1)") (class "Default")
      (node (ref "JP295") (pin "1") (pinfunction "1_1") (pintype "passive"))
      (node (ref "JP595") (pin "1") (pinfunction "1_1") (pintype "passive"))
    )
    (net (code "224") (name "Net-(JP296-Pad1)") (class "Default")
      (node (ref "JP296") (pin "1") (pinfunction "1_1") (pintype "passive"))
      (node (ref "JP596") (pin "1") (pinfunction "1_1") (pintype "passive"))
    )
    (net (code "225") (name "Net-(JP297-Pad1)") (class "Default")
      (node (ref "JP297") (pin "1") (pinfunction "1_1") (pintype "passive"))
      (node (ref "JP597") (pin "1") (pinfunction "1_1") (pintype "passive"))
    )
    (net (code "226") (name "Net-(JP298-Pad1)") (class "Default")
      (node (ref "JP298") (pin "1") (pinfunction "1_1") (pintype "passive"))
      (node (ref "JP598") (pin "1") (pinfunction "1_1") (pintype "passive"))
    )
    (net (code "227") (name "Net-(JP299-Pad1)") (class "Default")
      (node (ref "JP299") (pin "1") (pinfunction "1_1") (pintype "passive"))
      (node (ref "JP599") (pin "1") (pinfunction "1_1") (pintype "passive"))
    )
    (net (code "228") (name "Net-(JP300-Pad1)") (class "Default")
      (node (ref "JP300") (pin "1") (pinfunction "1_1") (pintype "passive"))
      (node (ref "JP600") (pin "1") (pinfunction "1_1") (pintype "passive"))
    )
    (net (code "229") (name "Net-(JP304-Pad1)") (class "Default")
      (node (ref "JP304") (pin "1") (pinfunction "1_1") (pintype "passive"))
      (node (ref "JP4") (pin "1") (pinfunction "1_1") (pintype "passive"))
    )
    (net (code "230") (name "Net-(JP305-Pad1)") (class "Default")
      (node (ref "JP305") (pin "1") (pinfunction "1_1") (pintype "passive"))
      (node (ref "JP5") (pin "1") (pinfunction "1_1") (pintype "passive"))
    )
    (net (code "231") (name "Net-(JP306-Pad1)") (class "Default")
      (node (ref "JP306") (pin "1") (pinfunction "1_1") (pintype "passive"))
      (node (ref "JP6") (pin "1") (pinfunction "1_1") (pintype "passive"))
    )
    (net (code "232") (name "Net-(JP307-Pad1)") (class "Default")
      (node (ref "JP307") (pin "1") (pinfunction "1_1") (pintype "passive"))
      (node (ref "JP7") (pin "1") (pinfunction "1_1") (pintype "passive"))
    )
    (net (code "233") (name "Net-(JP308-Pad1)") (class "Default")
      (node (ref "JP308") (pin "1") (pinfunction "1_1") (pintype "passive"))
      (node (ref "JP8") (pin "1") (pinfunction "1_1") (pintype "passive"))
    )
    (net (code "234") (name "Net-(JP309-Pad1)") (class "Default")
      (node (ref "JP309") (pin "1") (pinfunction "1_1") (pintype "passive"))
      (node (ref "JP9") (pin "1") (pinfunction "1_1") (pintype "passive"))
    )
    (net (code "235") (name "Net-(JP334-Pad1)") (class "Default")
      (node (ref "JP334") (pin "1") (pinfunction "1_1") (pintype "passive"))
      (node (ref "JP34") (pin "1") (pinfunction "1_1") (pintype "passive"))
    )
    (net (code "236") (name "Net-(JP335-Pad1)") (class "Default")
      (node (ref "JP335") (pin "1") (pinfunction "1_1") (pintype "passive"))
      (node (ref "JP35") (pin "1") (pinfunction "1_1") (pintype "passive"))
    )
    (net (code "237") (name "Net-(JP336-Pad1)") (class "Default")
      (node (ref "JP336") (pin "1") (pinfunction "1_1") (pintype "passive"))
      (node (ref "JP36") (pin "1") (pinfunction "1_1") (pintype "passive"))
    )
    (net (code "238") (name "Net-(JP337-Pad1)") (class "Default")
      (node (ref "JP337") (pin "1") (pinfunction "1_1") (pintype "passive"))
      (node (ref "JP37") (pin "1") (pinfunction "1_1") (pintype "passive"))
    )
    (net (code "239") (name "Net-(JP338-Pad1)") (class "Default")
      (node (ref "JP338") (pin "1") (pinfunction "1_1") (pintype "passive"))
      (node (ref "JP38") (pin "1") (pinfunction "1_1") (pintype "passive"))
    )
    (net (code "240") (name "Net-(JP339-Pad1)") (class "Default")
      (node (ref "JP339") (pin "1") (pinfunction "1_1") (pintype "passive"))
      (node (ref "JP39") (pin "1") (pinfunction "1_1") (pintype "passive"))
    )
    (net (code "241") (name "Net-(JP340-Pad1)") (class "Default")
      (node (ref "JP340") (pin "1") (pinfunction "1_1") (pintype "passive"))
      (node (ref "JP40") (pin "1") (pinfunction "1_1") (pintype "passive"))
    )
    (net (code "242") (name "Net-(JP341-Pad1)") (class "Default")
      (node (ref "JP341") (pin "1") (pinfunction "1_1") (pintype "passive"))
      (node (ref "JP41") (pin "1") (pinfunction "1_1") (pintype "passive"))
    )
    (net (code "243") (name "Net-(JP342-Pad1)") (class "Default")
      (node (ref "JP342") (pin "1") (pinfunction "1_1") (pintype "passive"))
      (node (ref "JP42") (pin "1") (pinfunction "1_1") (pintype "passive"))
    )
    (net (code "244") (name "Net-(JP343-Pad1)") (class "Default")
      (node (ref "JP343") (pin "1") (pinfunction "1_1") (pintype "passive"))
      (node (ref "JP43") (pin "1") (pinfunction "1_1") (pintype "passive"))
    )
    (net (code "245") (name "Net-(JP344-Pad1)") (class "Default")
      (node (ref "JP344") (pin "1") (pinfunction "1_1") (pintype "passive"))
      (node (ref "JP44") (pin "1") (pinfunction "1_1") (pintype "passive"))
    )
    (net (code "246") (name "Net-(JP345-Pad1)") (class "Default")
      (node (ref "JP345") (pin "1") (pinfunction "1_1") (pintype "passive"))
      (node (ref "JP45") (pin "1") (pinfunction "1_1") (pintype "passive"))
    )
    (net (code "247") (name "Net-(JP346-Pad1)") (class "Default")
      (node (ref "JP346") (pin "1") (pinfunction "1_1") (pintype "passive"))
      (node (ref "JP46") (pin "1") (pinfunction "1_1") (pintype "passive"))
    )
    (net (code "248") (name "Net-(JP347-Pad1)") (class "Default")
      (node (ref "JP347") (pin "1") (pinfunction "1_1") (pintype "passive"))
      (node (ref "JP47") (pin "1") (pinfunction "1_1") (pintype "passive"))
    )
    (net (code "249") (name "Net-(JP348-Pad1)") (class "Default")
      (node (ref "JP348") (pin "1") (pinfunction "1_1") (pintype "passive"))
      (node (ref "JP48") (pin "1") (pinfunction "1_1") (pintype "passive"))
    )
    (net (code "250") (name "Net-(JP349-Pad1)") (class "Default")
      (node (ref "JP349") (pin "1") (pinfunction "1_1") (pintype "passive"))
      (node (ref "JP49") (pin "1") (pinfunction "1_1") (pintype "passive"))
    )
    (net (code "251") (name "Net-(JP350-Pad1)") (class "Default")
      (node (ref "JP350") (pin "1") (pinfunction "1_1") (pintype "passive"))
      (node (ref "JP50") (pin "1") (pinfunction "1_1") (pintype "passive"))
    )
    (net (code "252") (name "Net-(JP351-Pad1)") (class "Default")
      (node (ref "JP351") (pin "1") (pinfunction "1_1") (pintype "passive"))
      (node (ref "JP51") (pin "1") (pinfunction "1_1") (pintype "passive"))
    )
    (net (code "253") (name "Net-(JP352-Pad1)") (class "Default")
      (node (ref "JP352") (pin "1") (pinfunction "1_1") (pintype "passive"))
      (node (ref "JP52") (pin "1") (pinfunction "1_1") (pintype "passive"))
    )
    (net (code "254") (name "Net-(JP353-Pad1)") (class "Default")
      (node (ref "JP353") (pin "1") (pinfunction "1_1") (pintype "passive"))
      (node (ref "JP53") (pin "1") (pinfunction "1_1") (pintype "passive"))
    )
    (net (code "255") (name "Net-(JP354-Pad1)") (class "Default")
      (node (ref "JP354") (pin "1") (pinfunction "1_1") (pintype "passive"))
      (node (ref "JP54") (pin "1") (pinfunction "1_1") (pintype "passive"))
    )
    (net (code "256") (name "Net-(JP355-Pad1)") (class "Default")
      (node (ref "JP355") (pin "1") (pinfunction "1_1") (pintype "passive"))
      (node (ref "JP55") (pin "1") (pinfunction "1_1") (pintype "passive"))
    )
    (net (code "257") (name "Net-(JP356-Pad1)") (class "Default")
      (node (ref "JP356") (pin "1") (pinfunction "1_1") (pintype "passive"))
      (node (ref "JP56") (pin "1") (pinfunction "1_1") (pintype "passive"))
    )
    (net (code "258") (name "Net-(JP357-Pad1)") (class "Default")
      (node (ref "JP357") (pin "1") (pinfunction "1_1") (pintype "passive"))
      (node (ref "JP57") (pin "1") (pinfunction "1_1") (pintype "passive"))
    )
    (net (code "259") (name "Net-(JP358-Pad1)") (class "Default")
      (node (ref "JP358") (pin "1") (pinfunction "1_1") (pintype "passive"))
      (node (ref "JP58") (pin "1") (pinfunction "1_1") (pintype "passive"))
    )
    (net (code "260") (name "Net-(JP359-Pad1)") (class "Default")
      (node (ref "JP359") (pin "1") (pinfunction "1_1") (pintype "passive"))
      (node (ref "JP59") (pin "1") (pinfunction "1_1") (pintype "passive"))
    )
    (net (code "261") (name "Net-(JP360-Pad1)") (class "Default")
      (node (ref "JP360") (pin "1") (pinfunction "1_1") (pintype "passive"))
      (node (ref "JP60") (pin "1") (pinfunction "1_1") (pintype "passive"))
    )
    (net (code "262") (name "Net-(JP361-Pad1)") (class "Default")
      (node (ref "JP361") (pin "1") (pinfunction "1_1") (pintype "passive"))
      (node (ref "JP61") (pin "1") (pinfunction "1_1") (pintype "passive"))
    )
    (net (code "263") (name "Net-(JP362-Pad1)") (class "Default")
      (node (ref "JP362") (pin "1") (pinfunction "1_1") (pintype "passive"))
      (node (ref "JP62") (pin "1") (pinfunction "1_1") (pintype "passive"))
    )
    (net (code "264") (name "Net-(JP363-Pad1)") (class "Default")
      (node (ref "JP363") (pin "1") (pinfunction "1_1") (pintype "passive"))
      (node (ref "JP63") (pin "1") (pinfunction "1_1") (pintype "passive"))
    )
    (net (code "265") (name "Net-(JP364-Pad1)") (class "Default")
      (node (ref "JP364") (pin "1") (pinfunction "1_1") (pintype "passive"))
      (node (ref "JP64") (pin "1") (pinfunction "1_1") (pintype "passive"))
    )
    (net (code "266") (name "Net-(JP365-Pad1)") (class "Default")
      (node (ref "JP365") (pin "1") (pinfunction "1_1") (pintype "passive"))
      (node (ref "JP65") (pin "1") (pinfunction "1_1") (pintype "passive"))
    )
    (net (code "267") (name "Net-(JP366-Pad1)") (class "Default")
      (node (ref "JP366") (pin "1") (pinfunction "1_1") (pintype "passive"))
      (node (ref "JP66") (pin "1") (pinfunction "1_1") (pintype "passive"))
    )
    (net (code "268") (name "Net-(JP367-Pad1)") (class "Default")
      (node (ref "JP367") (pin "1") (pinfunction "1_1") (pintype "passive"))
      (node (ref "JP67") (pin "1") (pinfunction "1_1") (pintype "passive"))
    )
    (net (code "269") (name "Net-(JP368-Pad1)") (class "Default")
      (node (ref "JP368") (pin "1") (pinfunction "1_1") (pintype "passive"))
      (node (ref "JP68") (pin "1") (pinfunction "1_1") (pintype "passive"))
    )
    (net (code "270") (name "Net-(JP369-Pad1)") (class "Default")
      (node (ref "JP369") (pin "1") (pinfunction "1_1") (pintype "passive"))
      (node (ref "JP69") (pin "1") (pinfunction "1_1") (pintype "passive"))
    )
    (net (code "271") (name "Net-(JP370-Pad1)") (class "Default")
      (node (ref "JP370") (pin "1") (pinfunction "1_1") (pintype "passive"))
      (node (ref "JP70") (pin "1") (pinfunction "1_1") (pintype "passive"))
    )
    (net (code "272") (name "Net-(JP371-Pad1)") (class "Default")
      (node (ref "JP371") (pin "1") (pinfunction "1_1") (pintype "passive"))
      (node (ref "JP71") (pin "1") (pinfunction "1_1") (pintype "passive"))
    )
    (net (code "273") (name "Net-(JP372-Pad1)") (class "Default")
      (node (ref "JP372") (pin "1") (pinfunction "1_1") (pintype "passive"))
      (node (ref "JP72") (pin "1") (pinfunction "1_1") (pintype "passive"))
    )
    (net (code "274") (name "Net-(JP373-Pad1)") (class "Default")
      (node (ref "JP373") (pin "1") (pinfunction "1_1") (pintype "passive"))
      (node (ref "JP73") (pin "1") (pinfunction "1_1") (pintype "passive"))
    )
    (net (code "275") (name "Net-(JP374-Pad1)") (class "Default")
      (node (ref "JP374") (pin "1") (pinfunction "1_1") (pintype "passive"))
      (node (ref "JP74") (pin "1") (pinfunction "1_1") (pintype "passive"))
    )
    (net (code "276") (name "Net-(JP375-Pad1)") (class "Default")
      (node (ref "JP375") (pin "1") (pinfunction "1_1") (pintype "passive"))
      (node (ref "JP75") (pin "1") (pinfunction "1_1") (pintype "passive"))
    )
    (net (code "277") (name "Net-(JP376-Pad1)") (class "Default")
      (node (ref "JP376") (pin "1") (pinfunction "1_1") (pintype "passive"))
      (node (ref "JP76") (pin "1") (pinfunction "1_1") (pintype "passive"))
    )
    (net (code "278") (name "Net-(JP377-Pad1)") (class "Default")
      (node (ref "JP377") (pin "1") (pinfunction "1_1") (pintype "passive"))
      (node (ref "JP77") (pin "1") (pinfunction "1_1") (pintype "passive"))
    )
    (net (code "279") (name "Net-(JP378-Pad1)") (class "Default")
      (node (ref "JP378") (pin "1") (pinfunction "1_1") (pintype "passive"))
      (node (ref "JP78") (pin "1") (pinfunction "1_1") (pintype "passive"))
    )
    (net (code "280") (name "Net-(JP379-Pad1)") (class "Default")
      (node (ref "JP379") (pin "1") (pinfunction "1_1") (pintype "passive"))
      (node (ref "JP79") (pin "1") (pinfunction "1_1") (pintype "passive"))
    )
    (net (code "281") (name "Net-(JP380-Pad1)") (class "Default")
      (node (ref "JP380") (pin "1") (pinfunction "1_1") (pintype "passive"))
      (node (ref "JP80") (pin "1") (pinfunction "1_1") (pintype "passive"))
    )
    (net (code "282") (name "Net-(JP381-Pad1)") (class "Default")
      (node (ref "JP381") (pin "1") (pinfunction "1_1") (pintype "passive"))
      (node (ref "JP81") (pin "1") (pinfunction "1_1") (pintype "passive"))
    )
    (net (code "283") (name "Net-(JP382-Pad1)") (class "Default")
      (node (ref "JP382") (pin "1") (pinfunction "1_1") (pintype "passive"))
      (node (ref "JP82") (pin "1") (pinfunction "1_1") (pintype "passive"))
    )
    (net (code "284") (name "Net-(JP383-Pad1)") (class "Default")
      (node (ref "JP383") (pin "1") (pinfunction "1_1") (pintype "passive"))
      (node (ref "JP83") (pin "1") (pinfunction "1_1") (pintype "passive"))
    )
    (net (code "285") (name "Net-(JP384-Pad1)") (class "Default")
      (node (ref "JP384") (pin "1") (pinfunction "1_1") (pintype "passive"))
      (node (ref "JP84") (pin "1") (pinfunction "1_1") (pintype "passive"))
    )
    (net (code "286") (name "Net-(JP385-Pad1)") (class "Default")
      (node (ref "JP385") (pin "1") (pinfunction "1_1") (pintype "passive"))
      (node (ref "JP85") (pin "1") (pinfunction "1_1") (pintype "passive"))
    )
    (net (code "287") (name "Net-(JP386-Pad1)") (class "Default")
      (node (ref "JP386") (pin "1") (pinfunction "1_1") (pintype "passive"))
      (node (ref "JP86") (pin "1") (pinfunction "1_1") (pintype "passive"))
    )
    (net (code "288") (name "Net-(JP387-Pad1)") (class "Default")
      (node (ref "JP387") (pin "1") (pinfunction "1_1") (pintype "passive"))
      (node (ref "JP87") (pin "1") (pinfunction "1_1") (pintype "passive"))
    )
    (net (code "289") (name "Net-(JP388-Pad1)") (class "Default")
      (node (ref "JP388") (pin "1") (pinfunction "1_1") (pintype "passive"))
      (node (ref "JP88") (pin "1") (pinfunction "1_1") (pintype "passive"))
    )
    (net (code "290") (name "Net-(JP389-Pad1)") (class "Default")
      (node (ref "JP389") (pin "1") (pinfunction "1_1") (pintype "passive"))
      (node (ref "JP89") (pin "1") (pinfunction "1_1") (pintype "passive"))
    )
    (net (code "291") (name "Net-(JP390-Pad1)") (class "Default")
      (node (ref "JP390") (pin "1") (pinfunction "1_1") (pintype "passive"))
      (node (ref "JP90") (pin "1") (pinfunction "1_1") (pintype "passive"))
    )
    (net (code "292") (name "Net-(JP391-Pad1)") (class "Default")
      (node (ref "JP391") (pin "1") (pinfunction "1_1") (pintype "passive"))
      (node (ref "JP91") (pin "1") (pinfunction "1_1") (pintype "passive"))
    )
    (net (code "293") (name "Net-(JP392-Pad1)") (class "Default")
      (node (ref "JP392") (pin "1") (pinfunction "1_1") (pintype "passive"))
      (node (ref "JP92") (pin "1") (pinfunction "1_1") (pintype "passive"))
    )
    (net (code "294") (name "Net-(JP393-Pad1)") (class "Default")
      (node (ref "JP393") (pin "1") (pinfunction "1_1") (pintype "passive"))
      (node (ref "JP93") (pin "1") (pinfunction "1_1") (pintype "passive"))
    )
    (net (code "295") (name "Net-(JP394-Pad1)") (class "Default")
      (node (ref "JP394") (pin "1") (pinfunction "1_1") (pintype "passive"))
      (node (ref "JP94") (pin "1") (pinfunction "1_1") (pintype "passive"))
    )
    (net (code "296") (name "Net-(JP395-Pad1)") (class "Default")
      (node (ref "JP395") (pin "1") (pinfunction "1_1") (pintype "passive"))
      (node (ref "JP95") (pin "1") (pinfunction "1_1") (pintype "passive"))
    )
    (net (code "297") (name "Net-(JP396-Pad1)") (class "Default")
      (node (ref "JP396") (pin "1") (pinfunction "1_1") (pintype "passive"))
      (node (ref "JP96") (pin "1") (pinfunction "1_1") (pintype "passive"))
    )
    (net (code "298") (name "Net-(JP397-Pad1)") (class "Default")
      (node (ref "JP397") (pin "1") (pinfunction "1_1") (pintype "passive"))
      (node (ref "JP97") (pin "1") (pinfunction "1_1") (pintype "passive"))
    )
    (net (code "299") (name "Net-(JP398-Pad1)") (class "Default")
      (node (ref "JP398") (pin "1") (pinfunction "1_1") (pintype "passive"))
      (node (ref "JP98") (pin "1") (pinfunction "1_1") (pintype "passive"))
    )
    (net (code "300") (name "Net-(JP399-Pad1)") (class "Default")
      (node (ref "JP399") (pin "1") (pinfunction "1_1") (pintype "passive"))
      (node (ref "JP99") (pin "1") (pinfunction "1_1") (pintype "passive"))
    )
    (net (code "301") (name "unconnected-(JP601-1-PadP$3)") (class "Default")
      (node (ref "JP601") (pin "P$3") (pinfunction "1_P$3") (pintype "passive"))
    )
    (net (code "302") (name "unconnected-(JP602-1-PadP$3)") (class "Default")
      (node (ref "JP602") (pin "P$3") (pinfunction "1_P$3") (pintype "passive"))
    )
    (net (code "303") (name "unconnected-(JP603-1-PadP$3)") (class "Default")
      (node (ref "JP603") (pin "P$3") (pinfunction "1_P$3") (pintype "passive"))
    )
    (net (code "304") (name "unconnected-(JP604-1-PadP$3)") (class "Default")
      (node (ref "JP604") (pin "P$3") (pinfunction "1_P$3") (pintype "passive"))
    )
    (net (code "305") (name "unconnected-(JP605-1-PadP$3)") (class "Default")
      (node (ref "JP605") (pin "P$3") (pinfunction "1_P$3") (pintype "passive"))
    )
    (net (code "306") (name "unconnected-(JP606-1-PadP$3)") (class "Default")
      (node (ref "JP606") (pin "P$3") (pinfunction "1_P$3") (pintype "passive"))
    )
    (net (code "307") (name "unconnected-(JP607-1-PadP$3)") (class "Default")
      (node (ref "JP607") (pin "P$3") (pinfunction "1_P$3") (pintype "passive"))
    )
    (net (code "308") (name "unconnected-(JP608-1-PadP$3)") (class "Default")
      (node (ref "JP608") (pin "P$3") (pinfunction "1_P$3") (pintype "passive"))
    )
    (net (code "309") (name "unconnected-(JP609-1-PadP$3)") (class "Default")
      (node (ref "JP609") (pin "P$3") (pinfunction "1_P$3") (pintype "passive"))
    )
    (net (code "310") (name "unconnected-(JP610-1-PadP$3)") (class "Default")
      (node (ref "JP610") (pin "P$3") (pinfunction "1_P$3") (pintype "passive"))
    )
    (net (code "311") (name "unconnected-(JP611-1-PadP$3)") (class "Default")
      (node (ref "JP611") (pin "P$3") (pinfunction "1_P$3") (pintype "passive"))
    )
    (net (code "312") (name "unconnected-(JP612-1-PadP$3)") (class "Default")
      (node (ref "JP612") (pin "P$3") (pinfunction "1_P$3") (pintype "passive"))
    )
    (net (code "313") (name "unconnected-(JP613-1-PadP$3)") (class "Default")
      (node (ref "JP613") (pin "P$3") (pinfunction "1_P$3") (pintype "passive"))
    )
    (net (code "314") (name "unconnected-(JP614-1-PadP$3)") (class "Default")
      (node (ref "JP614") (pin "P$3") (pinfunction "1_P$3") (pintype "passive"))
    )
    (net (code "315") (name "unconnected-(JP615-1-PadP$3)") (class "Default")
      (node (ref "JP615") (pin "P$3") (pinfunction "1_P$3") (pintype "passive"))
    )
    (net (code "316") (name "unconnected-(JP616-1-PadP$3)") (class "Default")
      (node (ref "JP616") (pin "P$3") (pinfunction "1_P$3") (pintype "passive"))
    )
    (net (code "317") (name "unconnected-(JP617-1-PadP$3)") (class "Default")
      (node (ref "JP617") (pin "P$3") (pinfunction "1_P$3") (pintype "passive"))
    )
    (net (code "318") (name "unconnected-(JP618-1-PadP$3)") (class "Default")
      (node (ref "JP618") (pin "P$3") (pinfunction "1_P$3") (pintype "passive"))
    )
    (net (code "319") (name "unconnected-(JP619-1-PadP$3)") (class "Default")
      (node (ref "JP619") (pin "P$3") (pinfunction "1_P$3") (pintype "passive"))
    )
    (net (code "320") (name "unconnected-(JP620-1-PadP$3)") (class "Default")
      (node (ref "JP620") (pin "P$3") (pinfunction "1_P$3") (pintype "passive"))
    )
    (net (code "321") (name "unconnected-(JP621-1-PadP$3)") (class "Default")
      (node (ref "JP621") (pin "P$3") (pinfunction "1_P$3") (pintype "passive"))
    )
    (net (code "322") (name "unconnected-(JP622-1-PadP$3)") (class "Default")
      (node (ref "JP622") (pin "P$3") (pinfunction "1_P$3") (pintype "passive"))
    )
    (net (code "323") (name "unconnected-(JP623-1-PadP$3)") (class "Default")
      (node (ref "JP623") (pin "P$3") (pinfunction "1_P$3") (pintype "passive"))
    )
    (net (code "324") (name "unconnected-(JP624-1-PadP$3)") (class "Default")
      (node (ref "JP624") (pin "P$3") (pinfunction "1_P$3") (pintype "passive"))
    )
    (net (code "325") (name "unconnected-(JP625-1-PadP$3)") (class "Default")
      (node (ref "JP625") (pin "P$3") (pinfunction "1_P$3") (pintype "passive"))
    )
    (net (code "326") (name "unconnected-(JP626-1-PadP$3)") (class "Default")
      (node (ref "JP626") (pin "P$3") (pinfunction "1_P$3") (pintype "passive"))
    )
    (net (code "327") (name "unconnected-(JP627-1-PadP$3)") (class "Default")
      (node (ref "JP627") (pin "P$3") (pinfunction "1_P$3") (pintype "passive"))
    )
    (net (code "328") (name "unconnected-(JP628-1-PadP$3)") (class "Default")
      (node (ref "JP628") (pin "P$3") (pinfunction "1_P$3") (pintype "passive"))
    )
    (net (code "329") (name "unconnected-(JP629-1-PadP$3)") (class "Default")
      (node (ref "JP629") (pin "P$3") (pinfunction "1_P$3") (pintype "passive"))
    )
    (net (code "330") (name "unconnected-(JP630-1-PadP$3)") (class "Default")
      (node (ref "JP630") (pin "P$3") (pinfunction "1_P$3") (pintype "passive"))
    )
    (net (code "331") (name "unconnected-(JP631-1-PadP$3)") (class "Default")
      (node (ref "JP631") (pin "P$3") (pinfunction "1_P$3") (pintype "passive"))
    )
    (net (code "332") (name "unconnected-(JP632-1-PadP$3)") (class "Default")
      (node (ref "JP632") (pin "P$3") (pinfunction "1_P$3") (pintype "passive"))
    )
    (net (code "333") (name "unconnected-(JP633-1-PadP$3)") (class "Default")
      (node (ref "JP633") (pin "P$3") (pinfunction "1_P$3") (pintype "passive"))
    )
    (net (code "334") (name "unconnected-(JP634-1-PadP$3)") (class "Default")
      (node (ref "JP634") (pin "P$3") (pinfunction "1_P$3") (pintype "passive"))
    )
    (net (code "335") (name "unconnected-(JP635-1-PadP$3)") (class "Default")
      (node (ref "JP635") (pin "P$3") (pinfunction "1_P$3") (pintype "passive"))
    )
    (net (code "336") (name "unconnected-(JP636-1-PadP$3)") (class "Default")
      (node (ref "JP636") (pin "P$3") (pinfunction "1_P$3") (pintype "passive"))
    )
    (net (code "337") (name "unconnected-(JP637-1-PadP$3)") (class "Default")
      (node (ref "JP637") (pin "P$3") (pinfunction "1_P$3") (pintype "passive"))
    )
    (net (code "338") (name "unconnected-(JP638-1-PadP$3)") (class "Default")
      (node (ref "JP638") (pin "P$3") (pinfunction "1_P$3") (pintype "passive"))
    )
    (net (code "339") (name "unconnected-(JP639-1-PadP$3)") (class "Default")
      (node (ref "JP639") (pin "P$3") (pinfunction "1_P$3") (pintype "passive"))
    )
    (net (code "340") (name "unconnected-(JP640-1-PadP$3)") (class "Default")
      (node (ref "JP640") (pin "P$3") (pinfunction "1_P$3") (pintype "passive"))
    )
    (net (code "341") (name "unconnected-(JP641-1-PadP$3)") (class "Default")
      (node (ref "JP641") (pin "P$3") (pinfunction "1_P$3") (pintype "passive"))
    )
    (net (code "342") (name "unconnected-(JP642-1-PadP$3)") (class "Default")
      (node (ref "JP642") (pin "P$3") (pinfunction "1_P$3") (pintype "passive"))
    )
    (net (code "343") (name "unconnected-(JP643-1-PadP$3)") (class "Default")
      (node (ref "JP643") (pin "P$3") (pinfunction "1_P$3") (pintype "passive"))
    )
    (net (code "344") (name "unconnected-(JP644-1-PadP$3)") (class "Default")
      (node (ref "JP644") (pin "P$3") (pinfunction "1_P$3") (pintype "passive"))
    )
    (net (code "345") (name "unconnected-(JP645-1-PadP$3)") (class "Default")
      (node (ref "JP645") (pin "P$3") (pinfunction "1_P$3") (pintype "passive"))
    )
    (net (code "346") (name "unconnected-(JP646-1-PadP$3)") (class "Default")
      (node (ref "JP646") (pin "P$3") (pinfunction "1_P$3") (pintype "passive"))
    )
    (net (code "347") (name "unconnected-(JP647-1-PadP$3)") (class "Default")
      (node (ref "JP647") (pin "P$3") (pinfunction "1_P$3") (pintype "passive"))
    )
    (net (code "348") (name "unconnected-(JP648-1-PadP$3)") (class "Default")
      (node (ref "JP648") (pin "P$3") (pinfunction "1_P$3") (pintype "passive"))
    )
    (net (code "349") (name "unconnected-(JP649-1-PadP$3)") (class "Default")
      (node (ref "JP649") (pin "P$3") (pinfunction "1_P$3") (pintype "passive"))
    )
    (net (code "350") (name "unconnected-(JP650-1-PadP$3)") (class "Default")
      (node (ref "JP650") (pin "P$3") (pinfunction "1_P$3") (pintype "passive"))
    )
    (net (code "351") (name "unconnected-(JP651-1-PadP$3)") (class "Default")
      (node (ref "JP651") (pin "P$3") (pinfunction "1_P$3") (pintype "passive"))
    )
    (net (code "352") (name "unconnected-(JP652-1-PadP$3)") (class "Default")
      (node (ref "JP652") (pin "P$3") (pinfunction "1_P$3") (pintype "passive"))
    )
    (net (code "353") (name "unconnected-(JP653-1-PadP$3)") (class "Default")
      (node (ref "JP653") (pin "P$3") (pinfunction "1_P$3") (pintype "passive"))
    )
    (net (code "354") (name "unconnected-(JP654-1-PadP$3)") (class "Default")
      (node (ref "JP654") (pin "P$3") (pinfunction "1_P$3") (pintype "passive"))
    )
    (net (code "355") (name "unconnected-(JP655-1-PadP$3)") (class "Default")
      (node (ref "JP655") (pin "P$3") (pinfunction "1_P$3") (pintype "passive"))
    )
    (net (code "356") (name "unconnected-(JP656-1-PadP$3)") (class "Default")
      (node (ref "JP656") (pin "P$3") (pinfunction "1_P$3") (pintype "passive"))
    )
    (net (code "357") (name "unconnected-(JP657-1-PadP$3)") (class "Default")
      (node (ref "JP657") (pin "P$3") (pinfunction "1_P$3") (pintype "passive"))
    )
    (net (code "358") (name "unconnected-(JP658-1-PadP$3)") (class "Default")
      (node (ref "JP658") (pin "P$3") (pinfunction "1_P$3") (pintype "passive"))
    )
    (net (code "359") (name "unconnected-(JP659-1-PadP$3)") (class "Default")
      (node (ref "JP659") (pin "P$3") (pinfunction "1_P$3") (pintype "passive"))
    )
    (net (code "360") (name "unconnected-(JP660-1-PadP$3)") (class "Default")
      (node (ref "JP660") (pin "P$3") (pinfunction "1_P$3") (pintype "passive"))
    )
    (net (code "361") (name "unconnected-(JP661-1-PadP$3)") (class "Default")
      (node (ref "JP661") (pin "P$3") (pinfunction "1_P$3") (pintype "passive"))
    )
    (net (code "362") (name "unconnected-(JP662-1-PadP$3)") (class "Default")
      (node (ref "JP662") (pin "P$3") (pinfunction "1_P$3") (pintype "passive"))
    )
    (net (code "363") (name "unconnected-(JP663-1-PadP$3)") (class "Default")
      (node (ref "JP663") (pin "P$3") (pinfunction "1_P$3") (pintype "passive"))
    )
    (net (code "364") (name "unconnected-(JP664-1-PadP$3)") (class "Default")
      (node (ref "JP664") (pin "P$3") (pinfunction "1_P$3") (pintype "passive"))
    )
    (net (code "365") (name "unconnected-(JP665-1-PadP$3)") (class "Default")
      (node (ref "JP665") (pin "P$3") (pinfunction "1_P$3") (pintype "passive"))
    )
    (net (code "366") (name "unconnected-(JP666-1-PadP$3)") (class "Default")
      (node (ref "JP666") (pin "P$3") (pinfunction "1_P$3") (pintype "passive"))
    )
    (net (code "367") (name "unconnected-(JP667-1-PadP$3)") (class "Default")
      (node (ref "JP667") (pin "P$3") (pinfunction "1_P$3") (pintype "passive"))
    )
    (net (code "368") (name "unconnected-(JP668-1-PadP$3)") (class "Default")
      (node (ref "JP668") (pin "P$3") (pinfunction "1_P$3") (pintype "passive"))
    )
    (net (code "369") (name "unconnected-(JP669-1-PadP$3)") (class "Default")
      (node (ref "JP669") (pin "P$3") (pinfunction "1_P$3") (pintype "passive"))
    )
    (net (code "370") (name "unconnected-(JP670-1-PadP$3)") (class "Default")
      (node (ref "JP670") (pin "P$3") (pinfunction "1_P$3") (pintype "passive"))
    )
    (net (code "371") (name "unconnected-(JP671-1-PadP$3)") (class "Default")
      (node (ref "JP671") (pin "P$3") (pinfunction "1_P$3") (pintype "passive"))
    )
    (net (code "372") (name "unconnected-(JP672-1-PadP$3)") (class "Default")
      (node (ref "JP672") (pin "P$3") (pinfunction "1_P$3") (pintype "passive"))
    )
    (net (code "373") (name "unconnected-(JP673-1-PadP$3)") (class "Default")
      (node (ref "JP673") (pin "P$3") (pinfunction "1_P$3") (pintype "passive"))
    )
    (net (code "374") (name "unconnected-(JP674-1-PadP$3)") (class "Default")
      (node (ref "JP674") (pin "P$3") (pinfunction "1_P$3") (pintype "passive"))
    )
    (net (code "375") (name "unconnected-(JP675-1-PadP$3)") (class "Default")
      (node (ref "JP675") (pin "P$3") (pinfunction "1_P$3") (pintype "passive"))
    )
    (net (code "376") (name "unconnected-(JP676-1-PadP$3)") (class "Default")
      (node (ref "JP676") (pin "P$3") (pinfunction "1_P$3") (pintype "passive"))
    )
    (net (code "377") (name "unconnected-(JP677-1-PadP$3)") (class "Default")
      (node (ref "JP677") (pin "P$3") (pinfunction "1_P$3") (pintype "passive"))
    )
    (net (code "378") (name "unconnected-(JP678-1-PadP$3)") (class "Default")
      (node (ref "JP678") (pin "P$3") (pinfunction "1_P$3") (pintype "passive"))
    )
    (net (code "379") (name "unconnected-(JP679-1-PadP$3)") (class "Default")
      (node (ref "JP679") (pin "P$3") (pinfunction "1_P$3") (pintype "passive"))
    )
    (net (code "380") (name "unconnected-(JP680-1-PadP$3)") (class "Default")
      (node (ref "JP680") (pin "P$3") (pinfunction "1_P$3") (pintype "passive"))
    )
    (net (code "381") (name "unconnected-(JP681-1-PadP$3)") (class "Default")
      (node (ref "JP681") (pin "P$3") (pinfunction "1_P$3") (pintype "passive"))
    )
    (net (code "382") (name "unconnected-(JP682-1-PadP$3)") (class "Default")
      (node (ref "JP682") (pin "P$3") (pinfunction "1_P$3") (pintype "passive"))
    )
    (net (code "383") (name "unconnected-(JP683-1-PadP$3)") (class "Default")
      (node (ref "JP683") (pin "P$3") (pinfunction "1_P$3") (pintype "passive"))
    )
    (net (code "384") (name "unconnected-(JP684-1-PadP$3)") (class "Default")
      (node (ref "JP684") (pin "P$3") (pinfunction "1_P$3") (pintype "passive"))
    )
    (net (code "385") (name "unconnected-(JP685-1-PadP$3)") (class "Default")
      (node (ref "JP685") (pin "P$3") (pinfunction "1_P$3") (pintype "passive"))
    )
    (net (code "386") (name "unconnected-(JP686-1-PadP$3)") (class "Default")
      (node (ref "JP686") (pin "P$3") (pinfunction "1_P$3") (pintype "passive"))
    )
    (net (code "387") (name "unconnected-(JP687-1-PadP$3)") (class "Default")
      (node (ref "JP687") (pin "P$3") (pinfunction "1_P$3") (pintype "passive"))
    )
    (net (code "388") (name "unconnected-(JP688-1-PadP$3)") (class "Default")
      (node (ref "JP688") (pin "P$3") (pinfunction "1_P$3") (pintype "passive"))
    )
    (net (code "389") (name "unconnected-(JP689-1-PadP$3)") (class "Default")
      (node (ref "JP689") (pin "P$3") (pinfunction "1_P$3") (pintype "passive"))
    )
    (net (code "390") (name "unconnected-(JP690-1-PadP$3)") (class "Default")
      (node (ref "JP690") (pin "P$3") (pinfunction "1_P$3") (pintype "passive"))
    )
    (net (code "391") (name "unconnected-(JP691-1-PadP$3)") (class "Default")
      (node (ref "JP691") (pin "P$3") (pinfunction "1_P$3") (pintype "passive"))
    )
    (net (code "392") (name "unconnected-(JP692-1-PadP$3)") (class "Default")
      (node (ref "JP692") (pin "P$3") (pinfunction "1_P$3") (pintype "passive"))
    )
    (net (code "393") (name "unconnected-(JP693-1-PadP$3)") (class "Default")
      (node (ref "JP693") (pin "P$3") (pinfunction "1_P$3") (pintype "passive"))
    )
    (net (code "394") (name "unconnected-(JP694-1-PadP$3)") (class "Default")
      (node (ref "JP694") (pin "P$3") (pinfunction "1_P$3") (pintype "passive"))
    )
    (net (code "395") (name "unconnected-(JP695-1-PadP$3)") (class "Default")
      (node (ref "JP695") (pin "P$3") (pinfunction "1_P$3") (pintype "passive"))
    )
    (net (code "396") (name "unconnected-(JP696-1-PadP$3)") (class "Default")
      (node (ref "JP696") (pin "P$3") (pinfunction "1_P$3") (pintype "passive"))
    )
    (net (code "397") (name "unconnected-(JP697-1-PadP$3)") (class "Default")
      (node (ref "JP697") (pin "P$3") (pinfunction "1_P$3") (pintype "passive"))
    )
    (net (code "398") (name "unconnected-(JP698-1-PadP$3)") (class "Default")
      (node (ref "JP698") (pin "P$3") (pinfunction "1_P$3") (pintype "passive"))
    )
    (net (code "399") (name "unconnected-(JP699-1-PadP$3)") (class "Default")
      (node (ref "JP699") (pin "P$3") (pinfunction "1_P$3") (pintype "passive"))
    )
    (net (code "400") (name "unconnected-(JP700-1-PadP$3)") (class "Default")
      (node (ref "JP700") (pin "P$3") (pinfunction "1_P$3") (pintype "passive"))
    )
    (net (code "401") (name "unconnected-(JP701-1-PadP$3)") (class "Default")
      (node (ref "JP701") (pin "P$3") (pinfunction "1_P$3") (pintype "passive"))
    )
    (net (code "402") (name "unconnected-(JP702-1-PadP$3)") (class "Default")
      (node (ref "JP702") (pin "P$3") (pinfunction "1_P$3") (pintype "passive"))
    )
    (net (code "403") (name "unconnected-(JP703-1-PadP$3)") (class "Default")
      (node (ref "JP703") (pin "P$3") (pinfunction "1_P$3") (pintype "passive"))
    )
    (net (code "404") (name "unconnected-(JP704-1-PadP$3)") (class "Default")
      (node (ref "JP704") (pin "P$3") (pinfunction "1_P$3") (pintype "passive"))
    )
    (net (code "405") (name "unconnected-(JP705-1-PadP$3)") (class "Default")
      (node (ref "JP705") (pin "P$3") (pinfunction "1_P$3") (pintype "passive"))
    )
    (net (code "406") (name "unconnected-(JP706-1-PadP$3)") (class "Default")
      (node (ref "JP706") (pin "P$3") (pinfunction "1_P$3") (pintype "passive"))
    )
    (net (code "407") (name "unconnected-(JP707-1-PadP$3)") (class "Default")
      (node (ref "JP707") (pin "P$3") (pinfunction "1_P$3") (pintype "passive"))
    )
    (net (code "408") (name "unconnected-(JP708-1-PadP$3)") (class "Default")
      (node (ref "JP708") (pin "P$3") (pinfunction "1_P$3") (pintype "passive"))
    )
    (net (code "409") (name "unconnected-(JP709-1-PadP$3)") (class "Default")
      (node (ref "JP709") (pin "P$3") (pinfunction "1_P$3") (pintype "passive"))
    )
    (net (code "410") (name "unconnected-(JP710-1-PadP$3)") (class "Default")
      (node (ref "JP710") (pin "P$3") (pinfunction "1_P$3") (pintype "passive"))
    )
    (net (code "411") (name "unconnected-(JP711-1-PadP$3)") (class "Default")
      (node (ref "JP711") (pin "P$3") (pinfunction "1_P$3") (pintype "passive"))
    )
    (net (code "412") (name "unconnected-(JP712-1-PadP$3)") (class "Default")
      (node (ref "JP712") (pin "P$3") (pinfunction "1_P$3") (pintype "passive"))
    )
    (net (code "413") (name "unconnected-(JP713-1-PadP$3)") (class "Default")
      (node (ref "JP713") (pin "P$3") (pinfunction "1_P$3") (pintype "passive"))
    )
    (net (code "414") (name "unconnected-(JP714-1-PadP$3)") (class "Default")
      (node (ref "JP714") (pin "P$3") (pinfunction "1_P$3") (pintype "passive"))
    )
    (net (code "415") (name "unconnected-(JP715-1-PadP$3)") (class "Default")
      (node (ref "JP715") (pin "P$3") (pinfunction "1_P$3") (pintype "passive"))
    )
    (net (code "416") (name "unconnected-(JP716-1-PadP$3)") (class "Default")
      (node (ref "JP716") (pin "P$3") (pinfunction "1_P$3") (pintype "passive"))
    )
    (net (code "417") (name "unconnected-(JP717-1-PadP$3)") (class "Default")
      (node (ref "JP717") (pin "P$3") (pinfunction "1_P$3") (pintype "passive"))
    )
    (net (code "418") (name "unconnected-(JP718-1-PadP$3)") (class "Default")
      (node (ref "JP718") (pin "P$3") (pinfunction "1_P$3") (pintype "passive"))
    )
    (net (code "419") (name "unconnected-(JP719-1-PadP$3)") (class "Default")
      (node (ref "JP719") (pin "P$3") (pinfunction "1_P$3") (pintype "passive"))
    )
    (net (code "420") (name "unconnected-(JP720-1-PadP$3)") (class "Default")
      (node (ref "JP720") (pin "P$3") (pinfunction "1_P$3") (pintype "passive"))
    )
    (net (code "421") (name "unconnected-(JP721-1-PadP$3)") (class "Default")
      (node (ref "JP721") (pin "P$3") (pinfunction "1_P$3") (pintype "passive"))
    )
    (net (code "422") (name "unconnected-(JP722-1-PadP$3)") (class "Default")
      (node (ref "JP722") (pin "P$3") (pinfunction "1_P$3") (pintype "passive"))
    )
    (net (code "423") (name "unconnected-(JP723-1-PadP$3)") (class "Default")
      (node (ref "JP723") (pin "P$3") (pinfunction "1_P$3") (pintype "passive"))
    )
    (net (code "424") (name "unconnected-(JP724-1-PadP$3)") (class "Default")
      (node (ref "JP724") (pin "P$3") (pinfunction "1_P$3") (pintype "passive"))
    )
    (net (code "425") (name "unconnected-(JP725-1-PadP$3)") (class "Default")
      (node (ref "JP725") (pin "P$3") (pinfunction "1_P$3") (pintype "passive"))
    )
    (net (code "426") (name "unconnected-(JP726-1-PadP$3)") (class "Default")
      (node (ref "JP726") (pin "P$3") (pinfunction "1_P$3") (pintype "passive"))
    )
    (net (code "427") (name "unconnected-(JP727-1-PadP$3)") (class "Default")
      (node (ref "JP727") (pin "P$3") (pinfunction "1_P$3") (pintype "passive"))
    )
    (net (code "428") (name "unconnected-(JP728-1-PadP$3)") (class "Default")
      (node (ref "JP728") (pin "P$3") (pinfunction "1_P$3") (pintype "passive"))
    )
    (net (code "429") (name "unconnected-(JP729-1-PadP$3)") (class "Default")
      (node (ref "JP729") (pin "P$3") (pinfunction "1_P$3") (pintype "passive"))
    )
    (net (code "430") (name "unconnected-(JP730-1-PadP$3)") (class "Default")
      (node (ref "JP730") (pin "P$3") (pinfunction "1_P$3") (pintype "passive"))
    )
    (net (code "431") (name "unconnected-(JP731-1-PadP$3)") (class "Default")
      (node (ref "JP731") (pin "P$3") (pinfunction "1_P$3") (pintype "passive"))
    )
    (net (code "432") (name "unconnected-(JP732-1-PadP$3)") (class "Default")
      (node (ref "JP732") (pin "P$3") (pinfunction "1_P$3") (pintype "passive"))
    )
    (net (code "433") (name "unconnected-(JP733-1-PadP$3)") (class "Default")
      (node (ref "JP733") (pin "P$3") (pinfunction "1_P$3") (pintype "passive"))
    )
    (net (code "434") (name "unconnected-(JP734-1-PadP$3)") (class "Default")
      (node (ref "JP734") (pin "P$3") (pinfunction "1_P$3") (pintype "passive"))
    )
    (net (code "435") (name "unconnected-(JP735-1-PadP$3)") (class "Default")
      (node (ref "JP735") (pin "P$3") (pinfunction "1_P$3") (pintype "passive"))
    )
    (net (code "436") (name "unconnected-(JP736-1-PadP$3)") (class "Default")
      (node (ref "JP736") (pin "P$3") (pinfunction "1_P$3") (pintype "passive"))
    )
    (net (code "437") (name "unconnected-(JP737-1-PadP$3)") (class "Default")
      (node (ref "JP737") (pin "P$3") (pinfunction "1_P$3") (pintype "passive"))
    )
    (net (code "438") (name "unconnected-(JP738-1-PadP$3)") (class "Default")
      (node (ref "JP738") (pin "P$3") (pinfunction "1_P$3") (pintype "passive"))
    )
    (net (code "439") (name "unconnected-(JP739-1-PadP$3)") (class "Default")
      (node (ref "JP739") (pin "P$3") (pinfunction "1_P$3") (pintype "passive"))
    )
    (net (code "440") (name "unconnected-(JP740-1-PadP$3)") (class "Default")
      (node (ref "JP740") (pin "P$3") (pinfunction "1_P$3") (pintype "passive"))
    )
    (net (code "441") (name "unconnected-(JP741-1-PadP$3)") (class "Default")
      (node (ref "JP741") (pin "P$3") (pinfunction "1_P$3") (pintype "passive"))
    )
    (net (code "442") (name "unconnected-(JP742-1-PadP$3)") (class "Default")
      (node (ref "JP742") (pin "P$3") (pinfunction "1_P$3") (pintype "passive"))
    )
    (net (code "443") (name "unconnected-(JP743-1-PadP$3)") (class "Default")
      (node (ref "JP743") (pin "P$3") (pinfunction "1_P$3") (pintype "passive"))
    )
    (net (code "444") (name "unconnected-(JP744-1-PadP$3)") (class "Default")
      (node (ref "JP744") (pin "P$3") (pinfunction "1_P$3") (pintype "passive"))
    )
    (net (code "445") (name "unconnected-(JP745-1-PadP$3)") (class "Default")
      (node (ref "JP745") (pin "P$3") (pinfunction "1_P$3") (pintype "passive"))
    )
    (net (code "446") (name "unconnected-(JP746-1-PadP$3)") (class "Default")
      (node (ref "JP746") (pin "P$3") (pinfunction "1_P$3") (pintype "passive"))
    )
    (net (code "447") (name "unconnected-(JP747-1-PadP$3)") (class "Default")
      (node (ref "JP747") (pin "P$3") (pinfunction "1_P$3") (pintype "passive"))
    )
    (net (code "448") (name "unconnected-(JP748-1-PadP$3)") (class "Default")
      (node (ref "JP748") (pin "P$3") (pinfunction "1_P$3") (pintype "passive"))
    )
    (net (code "449") (name "unconnected-(JP749-1-PadP$3)") (class "Default")
      (node (ref "JP749") (pin "P$3") (pinfunction "1_P$3") (pintype "passive"))
    )
    (net (code "450") (name "unconnected-(JP750-1-PadP$3)") (class "Default")
      (node (ref "JP750") (pin "P$3") (pinfunction "1_P$3") (pintype "passive"))
    )
    (net (code "451") (name "unconnected-(JP751-1-PadP$3)") (class "Default")
      (node (ref "JP751") (pin "P$3") (pinfunction "1_P$3") (pintype "passive"))
    )
    (net (code "452") (name "unconnected-(JP752-1-PadP$3)") (class "Default")
      (node (ref "JP752") (pin "P$3") (pinfunction "1_P$3") (pintype "passive"))
    )
    (net (code "453") (name "unconnected-(JP753-1-PadP$3)") (class "Default")
      (node (ref "JP753") (pin "P$3") (pinfunction "1_P$3") (pintype "passive"))
    )
    (net (code "454") (name "unconnected-(JP754-1-PadP$3)") (class "Default")
      (node (ref "JP754") (pin "P$3") (pinfunction "1_P$3") (pintype "passive"))
    )
    (net (code "455") (name "unconnected-(JP755-1-PadP$3)") (class "Default")
      (node (ref "JP755") (pin "P$3") (pinfunction "1_P$3") (pintype "passive"))
    )
    (net (code "456") (name "unconnected-(JP756-1-PadP$3)") (class "Default")
      (node (ref "JP756") (pin "P$3") (pinfunction "1_P$3") (pintype "passive"))
    )
    (net (code "457") (name "unconnected-(JP757-1-PadP$3)") (class "Default")
      (node (ref "JP757") (pin "P$3") (pinfunction "1_P$3") (pintype "passive"))
    )
    (net (code "458") (name "unconnected-(JP758-1-PadP$3)") (class "Default")
      (node (ref "JP758") (pin "P$3") (pinfunction "1_P$3") (pintype "passive"))
    )
    (net (code "459") (name "unconnected-(JP759-1-PadP$3)") (class "Default")
      (node (ref "JP759") (pin "P$3") (pinfunction "1_P$3") (pintype "passive"))
    )
    (net (code "460") (name "unconnected-(JP760-1-PadP$3)") (class "Default")
      (node (ref "JP760") (pin "P$3") (pinfunction "1_P$3") (pintype "passive"))
    )
    (net (code "461") (name "unconnected-(JP761-1-PadP$3)") (class "Default")
      (node (ref "JP761") (pin "P$3") (pinfunction "1_P$3") (pintype "passive"))
    )
    (net (code "462") (name "unconnected-(JP762-1-PadP$3)") (class "Default")
      (node (ref "JP762") (pin "P$3") (pinfunction "1_P$3") (pintype "passive"))
    )
    (net (code "463") (name "unconnected-(JP763-1-PadP$3)") (class "Default")
      (node (ref "JP763") (pin "P$3") (pinfunction "1_P$3") (pintype "passive"))
    )
    (net (code "464") (name "unconnected-(JP764-1-PadP$3)") (class "Default")
      (node (ref "JP764") (pin "P$3") (pinfunction "1_P$3") (pintype "passive"))
    )
    (net (code "465") (name "unconnected-(JP765-1-PadP$3)") (class "Default")
      (node (ref "JP765") (pin "P$3") (pinfunction "1_P$3") (pintype "passive"))
    )
    (net (code "466") (name "unconnected-(JP766-1-PadP$3)") (class "Default")
      (node (ref "JP766") (pin "P$3") (pinfunction "1_P$3") (pintype "passive"))
    )
    (net (code "467") (name "unconnected-(JP767-1-PadP$3)") (class "Default")
      (node (ref "JP767") (pin "P$3") (pinfunction "1_P$3") (pintype "passive"))
    )
    (net (code "468") (name "unconnected-(JP768-1-PadP$3)") (class "Default")
      (node (ref "JP768") (pin "P$3") (pinfunction "1_P$3") (pintype "passive"))
    )
    (net (code "469") (name "unconnected-(JP769-1-PadP$3)") (class "Default")
      (node (ref "JP769") (pin "P$3") (pinfunction "1_P$3") (pintype "passive"))
    )
    (net (code "470") (name "unconnected-(JP770-1-PadP$3)") (class "Default")
      (node (ref "JP770") (pin "P$3") (pinfunction "1_P$3") (pintype "passive"))
    )
    (net (code "471") (name "unconnected-(JP771-1-PadP$3)") (class "Default")
      (node (ref "JP771") (pin "P$3") (pinfunction "1_P$3") (pintype "passive"))
    )
    (net (code "472") (name "unconnected-(JP772-1-PadP$3)") (class "Default")
      (node (ref "JP772") (pin "P$3") (pinfunction "1_P$3") (pintype "passive"))
    )
    (net (code "473") (name "unconnected-(JP773-1-PadP$3)") (class "Default")
      (node (ref "JP773") (pin "P$3") (pinfunction "1_P$3") (pintype "passive"))
    )
    (net (code "474") (name "unconnected-(JP774-1-PadP$3)") (class "Default")
      (node (ref "JP774") (pin "P$3") (pinfunction "1_P$3") (pintype "passive"))
    )
    (net (code "475") (name "unconnected-(JP775-1-PadP$3)") (class "Default")
      (node (ref "JP775") (pin "P$3") (pinfunction "1_P$3") (pintype "passive"))
    )
    (net (code "476") (name "unconnected-(JP776-1-PadP$3)") (class "Default")
      (node (ref "JP776") (pin "P$3") (pinfunction "1_P$3") (pintype "passive"))
    )
    (net (code "477") (name "unconnected-(JP777-1-PadP$3)") (class "Default")
      (node (ref "JP777") (pin "P$3") (pinfunction "1_P$3") (pintype "passive"))
    )
    (net (code "478") (name "unconnected-(JP778-1-PadP$3)") (class "Default")
      (node (ref "JP778") (pin "P$3") (pinfunction "1_P$3") (pintype "passive"))
    )
    (net (code "479") (name "unconnected-(JP779-1-PadP$3)") (class "Default")
      (node (ref "JP779") (pin "P$3") (pinfunction "1_P$3") (pintype "passive"))
    )
    (net (code "480") (name "unconnected-(JP780-1-PadP$3)") (class "Default")
      (node (ref "JP780") (pin "P$3") (pinfunction "1_P$3") (pintype "passive"))
    )
    (net (code "481") (name "unconnected-(JP781-1-PadP$3)") (class "Default")
      (node (ref "JP781") (pin "P$3") (pinfunction "1_P$3") (pintype "passive"))
    )
    (net (code "482") (name "unconnected-(JP782-1-PadP$3)") (class "Default")
      (node (ref "JP782") (pin "P$3") (pinfunction "1_P$3") (pintype "passive"))
    )
    (net (code "483") (name "unconnected-(JP783-1-PadP$3)") (class "Default")
      (node (ref "JP783") (pin "P$3") (pinfunction "1_P$3") (pintype "passive"))
    )
    (net (code "484") (name "unconnected-(JP784-1-PadP$3)") (class "Default")
      (node (ref "JP784") (pin "P$3") (pinfunction "1_P$3") (pintype "passive"))
    )
    (net (code "485") (name "unconnected-(JP785-1-PadP$3)") (class "Default")
      (node (ref "JP785") (pin "P$3") (pinfunction "1_P$3") (pintype "passive"))
    )
    (net (code "486") (name "unconnected-(JP786-1-PadP$3)") (class "Default")
      (node (ref "JP786") (pin "P$3") (pinfunction "1_P$3") (pintype "passive"))
    )
    (net (code "487") (name "unconnected-(JP787-1-PadP$3)") (class "Default")
      (node (ref "JP787") (pin "P$3") (pinfunction "1_P$3") (pintype "passive"))
    )
    (net (code "488") (name "unconnected-(JP788-1-PadP$3)") (class "Default")
      (node (ref "JP788") (pin "P$3") (pinfunction "1_P$3") (pintype "passive"))
    )
    (net (code "489") (name "unconnected-(JP789-1-PadP$3)") (class "Default")
      (node (ref "JP789") (pin "P$3") (pinfunction "1_P$3") (pintype "passive"))
    )
    (net (code "490") (name "unconnected-(JP790-1-PadP$3)") (class "Default")
      (node (ref "JP790") (pin "P$3") (pinfunction "1_P$3") (pintype "passive"))
    )
    (net (code "491") (name "unconnected-(JP791-1-PadP$3)") (class "Default")
      (node (ref "JP791") (pin "P$3") (pinfunction "1_P$3") (pintype "passive"))
    )
    (net (code "492") (name "unconnected-(JP792-1-PadP$3)") (class "Default")
      (node (ref "JP792") (pin "P$3") (pinfunction "1_P$3") (pintype "passive"))
    )
    (net (code "493") (name "unconnected-(JP793-1-PadP$3)") (class "Default")
      (node (ref "JP793") (pin "P$3") (pinfunction "1_P$3") (pintype "passive"))
    )
    (net (code "494") (name "unconnected-(JP794-1-PadP$3)") (class "Default")
      (node (ref "JP794") (pin "P$3") (pinfunction "1_P$3") (pintype "passive"))
    )
    (net (code "495") (name "unconnected-(JP795-1-PadP$3)") (class "Default")
      (node (ref "JP795") (pin "P$3") (pinfunction "1_P$3") (pintype "passive"))
    )
    (net (code "496") (name "unconnected-(JP796-1-PadP$3)") (class "Default")
      (node (ref "JP796") (pin "P$3") (pinfunction "1_P$3") (pintype "passive"))
    )
    (net (code "497") (name "unconnected-(JP797-1-PadP$3)") (class "Default")
      (node (ref "JP797") (pin "P$3") (pinfunction "1_P$3") (pintype "passive"))
    )
    (net (code "498") (name "unconnected-(JP798-1-PadP$3)") (class "Default")
      (node (ref "JP798") (pin "P$3") (pinfunction "1_P$3") (pintype "passive"))
    )
    (net (code "499") (name "unconnected-(JP799-1-PadP$3)") (class "Default")
      (node (ref "JP799") (pin "P$3") (pinfunction "1_P$3") (pintype "passive"))
    )
    (net (code "500") (name "unconnected-(JP800-1-PadP$3)") (class "Default")
      (node (ref "JP800") (pin "P$3") (pinfunction "1_P$3") (pintype "passive"))
    )
    (net (code "501") (name "unconnected-(JP801-1-PadP$3)") (class "Default")
      (node (ref "JP801") (pin "P$3") (pinfunction "1_P$3") (pintype "passive"))
    )
    (net (code "502") (name "unconnected-(JP802-1-PadP$3)") (class "Default")
      (node (ref "JP802") (pin "P$3") (pinfunction "1_P$3") (pintype "passive"))
    )
    (net (code "503") (name "unconnected-(JP803-1-PadP$3)") (class "Default")
      (node (ref "JP803") (pin "P$3") (pinfunction "1_P$3") (pintype "passive"))
    )
    (net (code "504") (name "unconnected-(JP804-1-PadP$3)") (class "Default")
      (node (ref "JP804") (pin "P$3") (pinfunction "1_P$3") (pintype "passive"))
    )
    (net (code "505") (name "unconnected-(JP805-1-PadP$3)") (class "Default")
      (node (ref "JP805") (pin "P$3") (pinfunction "1_P$3") (pintype "passive"))
    )
    (net (code "506") (name "unconnected-(JP806-1-PadP$3)") (class "Default")
      (node (ref "JP806") (pin "P$3") (pinfunction "1_P$3") (pintype "passive"))
    )
    (net (code "507") (name "unconnected-(JP807-1-PadP$3)") (class "Default")
      (node (ref "JP807") (pin "P$3") (pinfunction "1_P$3") (pintype "passive"))
    )
    (net (code "508") (name "unconnected-(JP808-1-PadP$3)") (class "Default")
      (node (ref "JP808") (pin "P$3") (pinfunction "1_P$3") (pintype "passive"))
    )
    (net (code "509") (name "unconnected-(JP809-1-PadP$3)") (class "Default")
      (node (ref "JP809") (pin "P$3") (pinfunction "1_P$3") (pintype "passive"))
    )
    (net (code "510") (name "unconnected-(JP810-1-PadP$3)") (class "Default")
      (node (ref "JP810") (pin "P$3") (pinfunction "1_P$3") (pintype "passive"))
    )
    (net (code "511") (name "unconnected-(JP811-1-PadP$3)") (class "Default")
      (node (ref "JP811") (pin "P$3") (pinfunction "1_P$3") (pintype "passive"))
    )
    (net (code "512") (name "unconnected-(JP812-1-PadP$3)") (class "Default")
      (node (ref "JP812") (pin "P$3") (pinfunction "1_P$3") (pintype "passive"))
    )
    (net (code "513") (name "unconnected-(JP813-1-PadP$3)") (class "Default")
      (node (ref "JP813") (pin "P$3") (pinfunction "1_P$3") (pintype "passive"))
    )
    (net (code "514") (name "unconnected-(JP814-1-PadP$3)") (class "Default")
      (node (ref "JP814") (pin "P$3") (pinfunction "1_P$3") (pintype "passive"))
    )
    (net (code "515") (name "unconnected-(JP815-1-PadP$3)") (class "Default")
      (node (ref "JP815") (pin "P$3") (pinfunction "1_P$3") (pintype "passive"))
    )
    (net (code "516") (name "unconnected-(JP816-1-PadP$3)") (class "Default")
      (node (ref "JP816") (pin "P$3") (pinfunction "1_P$3") (pintype "passive"))
    )
    (net (code "517") (name "unconnected-(JP817-1-PadP$3)") (class "Default")
      (node (ref "JP817") (pin "P$3") (pinfunction "1_P$3") (pintype "passive"))
    )
    (net (code "518") (name "unconnected-(JP818-1-PadP$3)") (class "Default")
      (node (ref "JP818") (pin "P$3") (pinfunction "1_P$3") (pintype "passive"))
    )
    (net (code "519") (name "unconnected-(JP819-1-PadP$3)") (class "Default")
      (node (ref "JP819") (pin "P$3") (pinfunction "1_P$3") (pintype "passive"))
    )
    (net (code "520") (name "unconnected-(JP820-1-PadP$3)") (class "Default")
      (node (ref "JP820") (pin "P$3") (pinfunction "1_P$3") (pintype "passive"))
    )
    (net (code "521") (name "unconnected-(JP821-1-PadP$3)") (class "Default")
      (node (ref "JP821") (pin "P$3") (pinfunction "1_P$3") (pintype "passive"))
    )
    (net (code "522") (name "unconnected-(JP822-1-PadP$3)") (class "Default")
      (node (ref "JP822") (pin "P$3") (pinfunction "1_P$3") (pintype "passive"))
    )
    (net (code "523") (name "unconnected-(JP823-1-PadP$3)") (class "Default")
      (node (ref "JP823") (pin "P$3") (pinfunction "1_P$3") (pintype "passive"))
    )
    (net (code "524") (name "unconnected-(JP824-1-PadP$3)") (class "Default")
      (node (ref "JP824") (pin "P$3") (pinfunction "1_P$3") (pintype "passive"))
    )
    (net (code "525") (name "unconnected-(JP825-1-PadP$3)") (class "Default")
      (node (ref "JP825") (pin "P$3") (pinfunction "1_P$3") (pintype "passive"))
    )
    (net (code "526") (name "unconnected-(JP826-1-PadP$3)") (class "Default")
      (node (ref "JP826") (pin "P$3") (pinfunction "1_P$3") (pintype "passive"))
    )
    (net (code "527") (name "unconnected-(JP827-1-PadP$3)") (class "Default")
      (node (ref "JP827") (pin "P$3") (pinfunction "1_P$3") (pintype "passive"))
    )
    (net (code "528") (name "unconnected-(JP828-1-PadP$3)") (class "Default")
      (node (ref "JP828") (pin "P$3") (pinfunction "1_P$3") (pintype "passive"))
    )
    (net (code "529") (name "unconnected-(JP829-1-PadP$3)") (class "Default")
      (node (ref "JP829") (pin "P$3") (pinfunction "1_P$3") (pintype "passive"))
    )
    (net (code "530") (name "unconnected-(JP830-1-PadP$3)") (class "Default")
      (node (ref "JP830") (pin "P$3") (pinfunction "1_P$3") (pintype "passive"))
    )
    (net (code "531") (name "unconnected-(JP831-1-PadP$3)") (class "Default")
      (node (ref "JP831") (pin "P$3") (pinfunction "1_P$3") (pintype "passive"))
    )
    (net (code "532") (name "unconnected-(JP832-1-PadP$3)") (class "Default")
      (node (ref "JP832") (pin "P$3") (pinfunction "1_P$3") (pintype "passive"))
    )
    (net (code "533") (name "unconnected-(JP833-1-PadP$3)") (class "Default")
      (node (ref "JP833") (pin "P$3") (pinfunction "1_P$3") (pintype "passive"))
    )
    (net (code "534") (name "unconnected-(JP834-1-PadP$3)") (class "Default")
      (node (ref "JP834") (pin "P$3") (pinfunction "1_P$3") (pintype "passive"))
    )
    (net (code "535") (name "unconnected-(JP835-1-PadP$3)") (class "Default")
      (node (ref "JP835") (pin "P$3") (pinfunction "1_P$3") (pintype "passive"))
    )
    (net (code "536") (name "unconnected-(JP836-1-PadP$3)") (class "Default")
      (node (ref "JP836") (pin "P$3") (pinfunction "1_P$3") (pintype "passive"))
    )
    (net (code "537") (name "unconnected-(JP837-1-PadP$3)") (class "Default")
      (node (ref "JP837") (pin "P$3") (pinfunction "1_P$3") (pintype "passive"))
    )
    (net (code "538") (name "unconnected-(JP838-1-PadP$3)") (class "Default")
      (node (ref "JP838") (pin "P$3") (pinfunction "1_P$3") (pintype "passive"))
    )
    (net (code "539") (name "unconnected-(JP839-1-PadP$3)") (class "Default")
      (node (ref "JP839") (pin "P$3") (pinfunction "1_P$3") (pintype "passive"))
    )
    (net (code "540") (name "unconnected-(JP840-1-PadP$3)") (class "Default")
      (node (ref "JP840") (pin "P$3") (pinfunction "1_P$3") (pintype "passive"))
    )
    (net (code "541") (name "unconnected-(JP841-1-PadP$3)") (class "Default")
      (node (ref "JP841") (pin "P$3") (pinfunction "1_P$3") (pintype "passive"))
    )
    (net (code "542") (name "unconnected-(JP842-1-PadP$3)") (class "Default")
      (node (ref "JP842") (pin "P$3") (pinfunction "1_P$3") (pintype "passive"))
    )
    (net (code "543") (name "unconnected-(JP843-1-PadP$3)") (class "Default")
      (node (ref "JP843") (pin "P$3") (pinfunction "1_P$3") (pintype "passive"))
    )
    (net (code "544") (name "unconnected-(JP844-1-PadP$3)") (class "Default")
      (node (ref "JP844") (pin "P$3") (pinfunction "1_P$3") (pintype "passive"))
    )
    (net (code "545") (name "unconnected-(JP845-1-PadP$3)") (class "Default")
      (node (ref "JP845") (pin "P$3") (pinfunction "1_P$3") (pintype "passive"))
    )
    (net (code "546") (name "unconnected-(JP846-1-PadP$3)") (class "Default")
      (node (ref "JP846") (pin "P$3") (pinfunction "1_P$3") (pintype "passive"))
    )
    (net (code "547") (name "unconnected-(JP847-1-PadP$3)") (class "Default")
      (node (ref "JP847") (pin "P$3") (pinfunction "1_P$3") (pintype "passive"))
    )
    (net (code "548") (name "unconnected-(JP848-1-PadP$3)") (class "Default")
      (node (ref "JP848") (pin "P$3") (pinfunction "1_P$3") (pintype "passive"))
    )
    (net (code "549") (name "unconnected-(JP849-1-PadP$3)") (class "Default")
      (node (ref "JP849") (pin "P$3") (pinfunction "1_P$3") (pintype "passive"))
    )
    (net (code "550") (name "unconnected-(JP850-1-PadP$3)") (class "Default")
      (node (ref "JP850") (pin "P$3") (pinfunction "1_P$3") (pintype "passive"))
    )
    (net (code "551") (name "unconnected-(JP851-1-PadP$3)") (class "Default")
      (node (ref "JP851") (pin "P$3") (pinfunction "1_P$3") (pintype "passive"))
    )
    (net (code "552") (name "unconnected-(JP852-1-PadP$3)") (class "Default")
      (node (ref "JP852") (pin "P$3") (pinfunction "1_P$3") (pintype "passive"))
    )
    (net (code "553") (name "unconnected-(JP853-1-PadP$3)") (class "Default")
      (node (ref "JP853") (pin "P$3") (pinfunction "1_P$3") (pintype "passive"))
    )
    (net (code "554") (name "unconnected-(JP854-1-PadP$3)") (class "Default")
      (node (ref "JP854") (pin "P$3") (pinfunction "1_P$3") (pintype "passive"))
    )
    (net (code "555") (name "unconnected-(JP855-1-PadP$3)") (class "Default")
      (node (ref "JP855") (pin "P$3") (pinfunction "1_P$3") (pintype "passive"))
    )
    (net (code "556") (name "unconnected-(JP856-1-PadP$3)") (class "Default")
      (node (ref "JP856") (pin "P$3") (pinfunction "1_P$3") (pintype "passive"))
    )
    (net (code "557") (name "unconnected-(JP857-1-PadP$3)") (class "Default")
      (node (ref "JP857") (pin "P$3") (pinfunction "1_P$3") (pintype "passive"))
    )
    (net (code "558") (name "unconnected-(JP858-1-PadP$3)") (class "Default")
      (node (ref "JP858") (pin "P$3") (pinfunction "1_P$3") (pintype "passive"))
    )
    (net (code "559") (name "unconnected-(JP859-1-PadP$3)") (class "Default")
      (node (ref "JP859") (pin "P$3") (pinfunction "1_P$3") (pintype "passive"))
    )
    (net (code "560") (name "unconnected-(JP860-1-PadP$3)") (class "Default")
      (node (ref "JP860") (pin "P$3") (pinfunction "1_P$3") (pintype "passive"))
    )
    (net (code "561") (name "unconnected-(JP861-1-PadP$3)") (class "Default")
      (node (ref "JP861") (pin "P$3") (pinfunction "1_P$3") (pintype "passive"))
    )
    (net (code "562") (name "unconnected-(JP862-1-PadP$3)") (class "Default")
      (node (ref "JP862") (pin "P$3") (pinfunction "1_P$3") (pintype "passive"))
    )
    (net (code "563") (name "unconnected-(JP863-1-PadP$3)") (class "Default")
      (node (ref "JP863") (pin "P$3") (pinfunction "1_P$3") (pintype "passive"))
    )
    (net (code "564") (name "unconnected-(JP864-1-PadP$3)") (class "Default")
      (node (ref "JP864") (pin "P$3") (pinfunction "1_P$3") (pintype "passive"))
    )
    (net (code "565") (name "unconnected-(JP865-1-PadP$3)") (class "Default")
      (node (ref "JP865") (pin "P$3") (pinfunction "1_P$3") (pintype "passive"))
    )
    (net (code "566") (name "unconnected-(JP866-1-PadP$3)") (class "Default")
      (node (ref "JP866") (pin "P$3") (pinfunction "1_P$3") (pintype "passive"))
    )
    (net (code "567") (name "unconnected-(JP867-1-PadP$3)") (class "Default")
      (node (ref "JP867") (pin "P$3") (pinfunction "1_P$3") (pintype "passive"))
    )
    (net (code "568") (name "unconnected-(JP868-1-PadP$3)") (class "Default")
      (node (ref "JP868") (pin "P$3") (pinfunction "1_P$3") (pintype "passive"))
    )
    (net (code "569") (name "unconnected-(JP869-1-PadP$3)") (class "Default")
      (node (ref "JP869") (pin "P$3") (pinfunction "1_P$3") (pintype "passive"))
    )
    (net (code "570") (name "unconnected-(JP870-1-PadP$3)") (class "Default")
      (node (ref "JP870") (pin "P$3") (pinfunction "1_P$3") (pintype "passive"))
    )
    (net (code "571") (name "unconnected-(JP871-1-PadP$3)") (class "Default")
      (node (ref "JP871") (pin "P$3") (pinfunction "1_P$3") (pintype "passive"))
    )
    (net (code "572") (name "unconnected-(JP872-1-PadP$3)") (class "Default")
      (node (ref "JP872") (pin "P$3") (pinfunction "1_P$3") (pintype "passive"))
    )
    (net (code "573") (name "unconnected-(JP873-1-PadP$3)") (class "Default")
      (node (ref "JP873") (pin "P$3") (pinfunction "1_P$3") (pintype "passive"))
    )
    (net (code "574") (name "unconnected-(JP874-1-PadP$3)") (class "Default")
      (node (ref "JP874") (pin "P$3") (pinfunction "1_P$3") (pintype "passive"))
    )
    (net (code "575") (name "unconnected-(JP875-1-PadP$3)") (class "Default")
      (node (ref "JP875") (pin "P$3") (pinfunction "1_P$3") (pintype "passive"))
    )
    (net (code "576") (name "unconnected-(JP876-1-PadP$3)") (class "Default")
      (node (ref "JP876") (pin "P$3") (pinfunction "1_P$3") (pintype "passive"))
    )
    (net (code "577") (name "unconnected-(JP877-1-PadP$3)") (class "Default")
      (node (ref "JP877") (pin "P$3") (pinfunction "1_P$3") (pintype "passive"))
    )
    (net (code "578") (name "unconnected-(JP878-1-PadP$3)") (class "Default")
      (node (ref "JP878") (pin "P$3") (pinfunction "1_P$3") (pintype "passive"))
    )
    (net (code "579") (name "unconnected-(JP879-1-PadP$3)") (class "Default")
      (node (ref "JP879") (pin "P$3") (pinfunction "1_P$3") (pintype "passive"))
    )
    (net (code "580") (name "unconnected-(JP880-1-PadP$3)") (class "Default")
      (node (ref "JP880") (pin "P$3") (pinfunction "1_P$3") (pintype "passive"))
    )
    (net (code "581") (name "unconnected-(JP881-1-PadP$3)") (class "Default")
      (node (ref "JP881") (pin "P$3") (pinfunction "1_P$3") (pintype "passive"))
    )
    (net (code "582") (name "unconnected-(JP882-1-PadP$3)") (class "Default")
      (node (ref "JP882") (pin "P$3") (pinfunction "1_P$3") (pintype "passive"))
    )
    (net (code "583") (name "unconnected-(JP883-1-PadP$3)") (class "Default")
      (node (ref "JP883") (pin "P$3") (pinfunction "1_P$3") (pintype "passive"))
    )
    (net (code "584") (name "unconnected-(JP884-1-PadP$3)") (class "Default")
      (node (ref "JP884") (pin "P$3") (pinfunction "1_P$3") (pintype "passive"))
    )
    (net (code "585") (name "unconnected-(JP885-1-PadP$3)") (class "Default")
      (node (ref "JP885") (pin "P$3") (pinfunction "1_P$3") (pintype "passive"))
    )
    (net (code "586") (name "unconnected-(JP886-1-PadP$3)") (class "Default")
      (node (ref "JP886") (pin "P$3") (pinfunction "1_P$3") (pintype "passive"))
    )
    (net (code "587") (name "unconnected-(JP887-1-PadP$3)") (class "Default")
      (node (ref "JP887") (pin "P$3") (pinfunction "1_P$3") (pintype "passive"))
    )
    (net (code "588") (name "unconnected-(JP888-1-PadP$3)") (class "Default")
      (node (ref "JP888") (pin "P$3") (pinfunction "1_P$3") (pintype "passive"))
    )
    (net (code "589") (name "unconnected-(JP889-1-PadP$3)") (class "Default")
      (node (ref "JP889") (pin "P$3") (pinfunction "1_P$3") (pintype "passive"))
    )
    (net (code "590") (name "unconnected-(JP890-1-PadP$3)") (class "Default")
      (node (ref "JP890") (pin "P$3") (pinfunction "1_P$3") (pintype "passive"))
    )
    (net (code "591") (name "unconnected-(JP891-1-PadP$3)") (class "Default")
      (node (ref "JP891") (pin "P$3") (pinfunction "1_P$3") (pintype "passive"))
    )
    (net (code "592") (name "unconnected-(JP892-1-PadP$3)") (class "Default")
      (node (ref "JP892") (pin "P$3") (pinfunction "1_P$3") (pintype "passive"))
    )
    (net (code "593") (name "unconnected-(JP893-1-PadP$3)") (class "Default")
      (node (ref "JP893") (pin "P$3") (pinfunction "1_P$3") (pintype "passive"))
    )
    (net (code "594") (name "unconnected-(JP894-1-PadP$3)") (class "Default")
      (node (ref "JP894") (pin "P$3") (pinfunction "1_P$3") (pintype "passive"))
    )
    (net (code "595") (name "unconnected-(JP895-1-PadP$3)") (class "Default")
      (node (ref "JP895") (pin "P$3") (pinfunction "1_P$3") (pintype "passive"))
    )
    (net (code "596") (name "unconnected-(JP896-1-PadP$3)") (class "Default")
      (node (ref "JP896") (pin "P$3") (pinfunction "1_P$3") (pintype "passive"))
    )
    (net (code "597") (name "unconnected-(JP897-1-PadP$3)") (class "Default")
      (node (ref "JP897") (pin "P$3") (pinfunction "1_P$3") (pintype "passive"))
    )
    (net (code "598") (name "unconnected-(JP898-1-PadP$3)") (class "Default")
      (node (ref "JP898") (pin "P$3") (pinfunction "1_P$3") (pintype "passive"))
    )
    (net (code "599") (name "unconnected-(JP899-1-PadP$3)") (class "Default")
      (node (ref "JP899") (pin "P$3") (pinfunction "1_P$3") (pintype "passive"))
    )
    (net (code "600") (name "unconnected-(JP900-1-PadP$3)") (class "Default")
      (node (ref "JP900") (pin "P$3") (pinfunction "1_P$3") (pintype "passive"))
    )
    (net (code "601") (name "unconnected-(JP901-1-PadP$3)") (class "Default")
      (node (ref "JP901") (pin "P$3") (pinfunction "1_P$3") (pintype "passive"))
    )
    (net (code "602") (name "unconnected-(JP902-1-PadP$3)") (class "Default")
      (node (ref "JP902") (pin "P$3") (pinfunction "1_P$3") (pintype "passive"))
    )
    (net (code "603") (name "unconnected-(JP903-1-PadP$3)") (class "Default")
      (node (ref "JP903") (pin "P$3") (pinfunction "1_P$3") (pintype "passive"))
    )
    (net (code "604") (name "unconnected-(JP904-1-PadP$3)") (class "Default")
      (node (ref "JP904") (pin "P$3") (pinfunction "1_P$3") (pintype "passive"))
    )
    (net (code "605") (name "unconnected-(JP905-1-PadP$3)") (class "Default")
      (node (ref "JP905") (pin "P$3") (pinfunction "1_P$3") (pintype "passive"))
    )
    (net (code "606") (name "unconnected-(JP906-1-PadP$3)") (class "Default")
      (node (ref "JP906") (pin "P$3") (pinfunction "1_P$3") (pintype "passive"))
    )
    (net (code "607") (name "unconnected-(JP907-1-PadP$3)") (class "Default")
      (node (ref "JP907") (pin "P$3") (pinfunction "1_P$3") (pintype "passive"))
    )
    (net (code "608") (name "unconnected-(JP908-1-PadP$3)") (class "Default")
      (node (ref "JP908") (pin "P$3") (pinfunction "1_P$3") (pintype "passive"))
    )
    (net (code "609") (name "unconnected-(JP909-1-PadP$3)") (class "Default")
      (node (ref "JP909") (pin "P$3") (pinfunction "1_P$3") (pintype "passive"))
    )
    (net (code "610") (name "unconnected-(JP910-1-PadP$3)") (class "Default")
      (node (ref "JP910") (pin "P$3") (pinfunction "1_P$3") (pintype "passive"))
    )
    (net (code "611") (name "unconnected-(JP911-1-PadP$3)") (class "Default")
      (node (ref "JP911") (pin "P$3") (pinfunction "1_P$3") (pintype "passive"))
    )
    (net (code "612") (name "unconnected-(JP912-1-PadP$3)") (class "Default")
      (node (ref "JP912") (pin "P$3") (pinfunction "1_P$3") (pintype "passive"))
    )
    (net (code "613") (name "unconnected-(JP913-1-PadP$3)") (class "Default")
      (node (ref "JP913") (pin "P$3") (pinfunction "1_P$3") (pintype "passive"))
    )
    (net (code "614") (name "unconnected-(JP914-1-PadP$3)") (class "Default")
      (node (ref "JP914") (pin "P$3") (pinfunction "1_P$3") (pintype "passive"))
    )
    (net (code "615") (name "unconnected-(JP915-1-PadP$3)") (class "Default")
      (node (ref "JP915") (pin "P$3") (pinfunction "1_P$3") (pintype "passive"))
    )
    (net (code "616") (name "unconnected-(JP916-1-PadP$3)") (class "Default")
      (node (ref "JP916") (pin "P$3") (pinfunction "1_P$3") (pintype "passive"))
    )
    (net (code "617") (name "unconnected-(JP917-1-PadP$3)") (class "Default")
      (node (ref "JP917") (pin "P$3") (pinfunction "1_P$3") (pintype "passive"))
    )
    (net (code "618") (name "unconnected-(JP918-1-PadP$3)") (class "Default")
      (node (ref "JP918") (pin "P$3") (pinfunction "1_P$3") (pintype "passive"))
    )
    (net (code "619") (name "unconnected-(JP919-1-PadP$3)") (class "Default")
      (node (ref "JP919") (pin "P$3") (pinfunction "1_P$3") (pintype "passive"))
    )
    (net (code "620") (name "unconnected-(JP920-1-PadP$3)") (class "Default")
      (node (ref "JP920") (pin "P$3") (pinfunction "1_P$3") (pintype "passive"))
    )
    (net (code "621") (name "unconnected-(JP921-1-PadP$3)") (class "Default")
      (node (ref "JP921") (pin "P$3") (pinfunction "1_P$3") (pintype "passive"))
    )
    (net (code "622") (name "unconnected-(JP922-1-PadP$3)") (class "Default")
      (node (ref "JP922") (pin "P$3") (pinfunction "1_P$3") (pintype "passive"))
    )
    (net (code "623") (name "unconnected-(JP923-1-PadP$3)") (class "Default")
      (node (ref "JP923") (pin "P$3") (pinfunction "1_P$3") (pintype "passive"))
    )
    (net (code "624") (name "unconnected-(JP924-1-PadP$3)") (class "Default")
      (node (ref "JP924") (pin "P$3") (pinfunction "1_P$3") (pintype "passive"))
    )
    (net (code "625") (name "unconnected-(JP925-1-PadP$3)") (class "Default")
      (node (ref "JP925") (pin "P$3") (pinfunction "1_P$3") (pintype "passive"))
    )
    (net (code "626") (name "unconnected-(JP926-1-PadP$3)") (class "Default")
      (node (ref "JP926") (pin "P$3") (pinfunction "1_P$3") (pintype "passive"))
    )
    (net (code "627") (name "unconnected-(JP927-1-PadP$3)") (class "Default")
      (node (ref "JP927") (pin "P$3") (pinfunction "1_P$3") (pintype "passive"))
    )
    (net (code "628") (name "unconnected-(JP928-1-PadP$3)") (class "Default")
      (node (ref "JP928") (pin "P$3") (pinfunction "1_P$3") (pintype "passive"))
    )
    (net (code "629") (name "unconnected-(JP929-1-PadP$3)") (class "Default")
      (node (ref "JP929") (pin "P$3") (pinfunction "1_P$3") (pintype "passive"))
    )
    (net (code "630") (name "unconnected-(JP930-1-PadP$3)") (class "Default")
      (node (ref "JP930") (pin "P$3") (pinfunction "1_P$3") (pintype "passive"))
    )
    (net (code "631") (name "unconnected-(JP931-1-PadP$3)") (class "Default")
      (node (ref "JP931") (pin "P$3") (pinfunction "1_P$3") (pintype "passive"))
    )
    (net (code "632") (name "unconnected-(JP932-1-PadP$3)") (class "Default")
      (node (ref "JP932") (pin "P$3") (pinfunction "1_P$3") (pintype "passive"))
    )
    (net (code "633") (name "unconnected-(JP933-1-PadP$3)") (class "Default")
      (node (ref "JP933") (pin "P$3") (pinfunction "1_P$3") (pintype "passive"))
    )
    (net (code "634") (name "unconnected-(JP934-1-PadP$3)") (class "Default")
      (node (ref "JP934") (pin "P$3") (pinfunction "1_P$3") (pintype "passive"))
    )
    (net (code "635") (name "unconnected-(JP935-1-PadP$3)") (class "Default")
      (node (ref "JP935") (pin "P$3") (pinfunction "1_P$3") (pintype "passive"))
    )
    (net (code "636") (name "unconnected-(JP936-1-PadP$3)") (class "Default")
      (node (ref "JP936") (pin "P$3") (pinfunction "1_P$3") (pintype "passive"))
    )
    (net (code "637") (name "unconnected-(JP937-1-PadP$3)") (class "Default")
      (node (ref "JP937") (pin "P$3") (pinfunction "1_P$3") (pintype "passive"))
    )
    (net (code "638") (name "unconnected-(JP938-1-PadP$3)") (class "Default")
      (node (ref "JP938") (pin "P$3") (pinfunction "1_P$3") (pintype "passive"))
    )
    (net (code "639") (name "unconnected-(JP939-1-PadP$3)") (class "Default")
      (node (ref "JP939") (pin "P$3") (pinfunction "1_P$3") (pintype "passive"))
    )
    (net (code "640") (name "unconnected-(JP940-1-PadP$3)") (class "Default")
      (node (ref "JP940") (pin "P$3") (pinfunction "1_P$3") (pintype "passive"))
    )
    (net (code "641") (name "unconnected-(JP941-1-PadP$3)") (class "Default")
      (node (ref "JP941") (pin "P$3") (pinfunction "1_P$3") (pintype "passive"))
    )
    (net (code "642") (name "unconnected-(JP942-1-PadP$3)") (class "Default")
      (node (ref "JP942") (pin "P$3") (pinfunction "1_P$3") (pintype "passive"))
    )
    (net (code "643") (name "unconnected-(JP943-1-PadP$3)") (class "Default")
      (node (ref "JP943") (pin "P$3") (pinfunction "1_P$3") (pintype "passive"))
    )
    (net (code "644") (name "unconnected-(JP944-1-PadP$3)") (class "Default")
      (node (ref "JP944") (pin "P$3") (pinfunction "1_P$3") (pintype "passive"))
    )
    (net (code "645") (name "unconnected-(JP945-1-PadP$3)") (class "Default")
      (node (ref "JP945") (pin "P$3") (pinfunction "1_P$3") (pintype "passive"))
    )
    (net (code "646") (name "unconnected-(JP946-1-PadP$3)") (class "Default")
      (node (ref "JP946") (pin "P$3") (pinfunction "1_P$3") (pintype "passive"))
    )
    (net (code "647") (name "unconnected-(JP947-1-PadP$3)") (class "Default")
      (node (ref "JP947") (pin "P$3") (pinfunction "1_P$3") (pintype "passive"))
    )
    (net (code "648") (name "unconnected-(JP948-1-PadP$3)") (class "Default")
      (node (ref "JP948") (pin "P$3") (pinfunction "1_P$3") (pintype "passive"))
    )
    (net (code "649") (name "unconnected-(JP949-1-PadP$3)") (class "Default")
      (node (ref "JP949") (pin "P$3") (pinfunction "1_P$3") (pintype "passive"))
    )
    (net (code "650") (name "unconnected-(JP950-1-PadP$3)") (class "Default")
      (node (ref "JP950") (pin "P$3") (pinfunction "1_P$3") (pintype "passive"))
    )
    (net (code "651") (name "unconnected-(JP951-1-PadP$3)") (class "Default")
      (node (ref "JP951") (pin "P$3") (pinfunction "1_P$3") (pintype "passive"))
    )
    (net (code "652") (name "unconnected-(JP952-1-PadP$3)") (class "Default")
      (node (ref "JP952") (pin "P$3") (pinfunction "1_P$3") (pintype "passive"))
    )
    (net (code "653") (name "unconnected-(JP953-1-PadP$3)") (class "Default")
      (node (ref "JP953") (pin "P$3") (pinfunction "1_P$3") (pintype "passive"))
    )
    (net (code "654") (name "unconnected-(JP954-1-PadP$3)") (class "Default")
      (node (ref "JP954") (pin "P$3") (pinfunction "1_P$3") (pintype "passive"))
    )
    (net (code "655") (name "unconnected-(JP955-1-PadP$3)") (class "Default")
      (node (ref "JP955") (pin "P$3") (pinfunction "1_P$3") (pintype "passive"))
    )
    (net (code "656") (name "unconnected-(JP956-1-PadP$3)") (class "Default")
      (node (ref "JP956") (pin "P$3") (pinfunction "1_P$3") (pintype "passive"))
    )
    (net (code "657") (name "unconnected-(JP957-1-PadP$3)") (class "Default")
      (node (ref "JP957") (pin "P$3") (pinfunction "1_P$3") (pintype "passive"))
    )
    (net (code "658") (name "unconnected-(JP958-1-PadP$3)") (class "Default")
      (node (ref "JP958") (pin "P$3") (pinfunction "1_P$3") (pintype "passive"))
    )
    (net (code "659") (name "unconnected-(JP959-1-PadP$3)") (class "Default")
      (node (ref "JP959") (pin "P$3") (pinfunction "1_P$3") (pintype "passive"))
    )
    (net (code "660") (name "unconnected-(JP960-1-PadP$3)") (class "Default")
      (node (ref "JP960") (pin "P$3") (pinfunction "1_P$3") (pintype "passive"))
    )
    (net (code "661") (name "unconnected-(JP961-1-PadP$3)") (class "Default")
      (node (ref "JP961") (pin "P$3") (pinfunction "1_P$3") (pintype "passive"))
    )
    (net (code "662") (name "unconnected-(JP962-1-PadP$3)") (class "Default")
      (node (ref "JP962") (pin "P$3") (pinfunction "1_P$3") (pintype "passive"))
    )
    (net (code "663") (name "unconnected-(JP963-1-PadP$3)") (class "Default")
      (node (ref "JP963") (pin "P$3") (pinfunction "1_P$3") (pintype "passive"))
    )
    (net (code "664") (name "unconnected-(JP964-1-PadP$3)") (class "Default")
      (node (ref "JP964") (pin "P$3") (pinfunction "1_P$3") (pintype "passive"))
    )
    (net (code "665") (name "unconnected-(JP965-1-PadP$3)") (class "Default")
      (node (ref "JP965") (pin "P$3") (pinfunction "1_P$3") (pintype "passive"))
    )
    (net (code "666") (name "unconnected-(JP966-1-PadP$3)") (class "Default")
      (node (ref "JP966") (pin "P$3") (pinfunction "1_P$3") (pintype "passive"))
    )
    (net (code "667") (name "unconnected-(JP967-1-PadP$3)") (class "Default")
      (node (ref "JP967") (pin "P$3") (pinfunction "1_P$3") (pintype "passive"))
    )
    (net (code "668") (name "unconnected-(JP968-1-PadP$3)") (class "Default")
      (node (ref "JP968") (pin "P$3") (pinfunction "1_P$3") (pintype "passive"))
    )
    (net (code "669") (name "unconnected-(JP969-1-PadP$3)") (class "Default")
      (node (ref "JP969") (pin "P$3") (pinfunction "1_P$3") (pintype "passive"))
    )
    (net (code "670") (name "unconnected-(JP970-1-PadP$3)") (class "Default")
      (node (ref "JP970") (pin "P$3") (pinfunction "1_P$3") (pintype "passive"))
    )
    (net (code "671") (name "unconnected-(JP971-1-PadP$3)") (class "Default")
      (node (ref "JP971") (pin "P$3") (pinfunction "1_P$3") (pintype "passive"))
    )
    (net (code "672") (name "unconnected-(JP972-1-PadP$3)") (class "Default")
      (node (ref "JP972") (pin "P$3") (pinfunction "1_P$3") (pintype "passive"))
    )
    (net (code "673") (name "unconnected-(JP973-1-PadP$3)") (class "Default")
      (node (ref "JP973") (pin "P$3") (pinfunction "1_P$3") (pintype "passive"))
    )
    (net (code "674") (name "unconnected-(JP974-1-PadP$3)") (class "Default")
      (node (ref "JP974") (pin "P$3") (pinfunction "1_P$3") (pintype "passive"))
    )
    (net (code "675") (name "unconnected-(JP975-1-PadP$3)") (class "Default")
      (node (ref "JP975") (pin "P$3") (pinfunction "1_P$3") (pintype "passive"))
    )
    (net (code "676") (name "unconnected-(JP976-1-PadP$3)") (class "Default")
      (node (ref "JP976") (pin "P$3") (pinfunction "1_P$3") (pintype "passive"))
    )
    (net (code "677") (name "unconnected-(JP977-1-PadP$3)") (class "Default")
      (node (ref "JP977") (pin "P$3") (pinfunction "1_P$3") (pintype "passive"))
    )
    (net (code "678") (name "unconnected-(JP978-1-PadP$3)") (class "Default")
      (node (ref "JP978") (pin "P$3") (pinfunction "1_P$3") (pintype "passive"))
    )
    (net (code "679") (name "unconnected-(JP979-1-PadP$3)") (class "Default")
      (node (ref "JP979") (pin "P$3") (pinfunction "1_P$3") (pintype "passive"))
    )
    (net (code "680") (name "unconnected-(JP980-1-PadP$3)") (class "Default")
      (node (ref "JP980") (pin "P$3") (pinfunction "1_P$3") (pintype "passive"))
    )
    (net (code "681") (name "unconnected-(JP981-1-PadP$3)") (class "Default")
      (node (ref "JP981") (pin "P$3") (pinfunction "1_P$3") (pintype "passive"))
    )
    (net (code "682") (name "unconnected-(JP982-1-PadP$3)") (class "Default")
      (node (ref "JP982") (pin "P$3") (pinfunction "1_P$3") (pintype "passive"))
    )
    (net (code "683") (name "unconnected-(JP983-1-PadP$3)") (class "Default")
      (node (ref "JP983") (pin "P$3") (pinfunction "1_P$3") (pintype "passive"))
    )
    (net (code "684") (name "unconnected-(JP984-1-PadP$3)") (class "Default")
      (node (ref "JP984") (pin "P$3") (pinfunction "1_P$3") (pintype "passive"))
    )
    (net (code "685") (name "unconnected-(JP985-1-PadP$3)") (class "Default")
      (node (ref "JP985") (pin "P$3") (pinfunction "1_P$3") (pintype "passive"))
    )
    (net (code "686") (name "unconnected-(JP986-1-PadP$3)") (class "Default")
      (node (ref "JP986") (pin "P$3") (pinfunction "1_P$3") (pintype "passive"))
    )
    (net (code "687") (name "unconnected-(JP987-1-PadP$3)") (class "Default")
      (node (ref "JP987") (pin "P$3") (pinfunction "1_P$3") (pintype "passive"))
    )
    (net (code "688") (name "unconnected-(JP988-1-PadP$3)") (class "Default")
      (node (ref "JP988") (pin "P$3") (pinfunction "1_P$3") (pintype "passive"))
    )
    (net (code "689") (name "unconnected-(JP989-1-PadP$3)") (class "Default")
      (node (ref "JP989") (pin "P$3") (pinfunction "1_P$3") (pintype "passive"))
    )
    (net (code "690") (name "unconnected-(JP990-1-PadP$3)") (class "Default")
      (node (ref "JP990") (pin "P$3") (pinfunction "1_P$3") (pintype "passive"))
    )
    (net (code "691") (name "unconnected-(JP991-1-PadP$3)") (class "Default")
      (node (ref "JP991") (pin "P$3") (pinfunction "1_P$3") (pintype "passive"))
    )
    (net (code "692") (name "unconnected-(JP992-1-PadP$3)") (class "Default")
      (node (ref "JP992") (pin "P$3") (pinfunction "1_P$3") (pintype "passive"))
    )
    (net (code "693") (name "unconnected-(JP993-1-PadP$3)") (class "Default")
      (node (ref "JP993") (pin "P$3") (pinfunction "1_P$3") (pintype "passive"))
    )
    (net (code "694") (name "unconnected-(JP994-1-PadP$3)") (class "Default")
      (node (ref "JP994") (pin "P$3") (pinfunction "1_P$3") (pintype "passive"))
    )
    (net (code "695") (name "unconnected-(JP995-1-PadP$3)") (class "Default")
      (node (ref "JP995") (pin "P$3") (pinfunction "1_P$3") (pintype "passive"))
    )
    (net (code "696") (name "unconnected-(JP996-1-PadP$3)") (class "Default")
      (node (ref "JP996") (pin "P$3") (pinfunction "1_P$3") (pintype "passive"))
    )
    (net (code "697") (name "unconnected-(JP997-1-PadP$3)") (class "Default")
      (node (ref "JP997") (pin "P$3") (pinfunction "1_P$3") (pintype "passive"))
    )
    (net (code "698") (name "unconnected-(JP998-1-PadP$3)") (class "Default")
      (node (ref "JP998") (pin "P$3") (pinfunction "1_P$3") (pintype "passive"))
    )
    (net (code "699") (name "unconnected-(JP999-1-PadP$3)") (class "Default")
      (node (ref "JP999") (pin "P$3") (pinfunction "1_P$3") (pintype "passive"))
    )
    (net (code "700") (name "unconnected-(JP1000-1-PadP$3)") (class "Default")
      (node (ref "JP1000") (pin "P$3") (pinfunction "1_P$3") (pintype "passive"))
    )
    (net (code "701") (name "unconnected-(JP1001-1-PadP$3)") (class "Default")
      (node (ref "JP1001") (pin "P$3") (pinfunction "1_P$3") (pintype "passive"))
    )
    (net (code "702") (name "unconnected-(JP1002-1-PadP$3)") (class "Default")
      (node (ref "JP1002") (pin "P$3") (pinfunction "1_P$3") (pintype "passive"))
    )
    (net (code "703") (name "unconnected-(JP1003-1-PadP$3)") (class "Default")
      (node (ref "JP1003") (pin "P$3") (pinfunction "1_P$3") (pintype "passive"))
    )
    (net (code "704") (name "unconnected-(JP1004-1-PadP$3)") (class "Default")
      (node (ref "JP1004") (pin "P$3") (pinfunction "1_P$3") (pintype "passive"))
    )
    (net (code "705") (name "unconnected-(JP1005-1-PadP$3)") (class "Default")
      (node (ref "JP1005") (pin "P$3") (pinfunction "1_P$3") (pintype "passive"))
    )
    (net (code "706") (name "unconnected-(JP1006-1-PadP$3)") (class "Default")
      (node (ref "JP1006") (pin "P$3") (pinfunction "1_P$3") (pintype "passive"))
    )
    (net (code "707") (name "unconnected-(JP1007-1-PadP$3)") (class "Default")
      (node (ref "JP1007") (pin "P$3") (pinfunction "1_P$3") (pintype "passive"))
    )
    (net (code "708") (name "unconnected-(JP1008-1-PadP$3)") (class "Default")
      (node (ref "JP1008") (pin "P$3") (pinfunction "1_P$3") (pintype "passive"))
    )
    (net (code "709") (name "unconnected-(JP1009-1-PadP$3)") (class "Default")
      (node (ref "JP1009") (pin "P$3") (pinfunction "1_P$3") (pintype "passive"))
    )
    (net (code "710") (name "unconnected-(JP1010-1-PadP$3)") (class "Default")
      (node (ref "JP1010") (pin "P$3") (pinfunction "1_P$3") (pintype "passive"))
    )
    (net (code "711") (name "unconnected-(JP1011-1-PadP$3)") (class "Default")
      (node (ref "JP1011") (pin "P$3") (pinfunction "1_P$3") (pintype "passive"))
    )
    (net (code "712") (name "unconnected-(JP1012-1-PadP$3)") (class "Default")
      (node (ref "JP1012") (pin "P$3") (pinfunction "1_P$3") (pintype "passive"))
    )
    (net (code "713") (name "unconnected-(JP1013-1-PadP$3)") (class "Default")
      (node (ref "JP1013") (pin "P$3") (pinfunction "1_P$3") (pintype "passive"))
    )
    (net (code "714") (name "unconnected-(JP1014-1-PadP$3)") (class "Default")
      (node (ref "JP1014") (pin "P$3") (pinfunction "1_P$3") (pintype "passive"))
    )
    (net (code "715") (name "unconnected-(JP1015-1-PadP$3)") (class "Default")
      (node (ref "JP1015") (pin "P$3") (pinfunction "1_P$3") (pintype "passive"))
    )
    (net (code "716") (name "unconnected-(JP1016-1-PadP$3)") (class "Default")
      (node (ref "JP1016") (pin "P$3") (pinfunction "1_P$3") (pintype "passive"))
    )
    (net (code "717") (name "unconnected-(JP1017-1-PadP$3)") (class "Default")
      (node (ref "JP1017") (pin "P$3") (pinfunction "1_P$3") (pintype "passive"))
    )
    (net (code "718") (name "unconnected-(JP1018-1-PadP$3)") (class "Default")
      (node (ref "JP1018") (pin "P$3") (pinfunction "1_P$3") (pintype "passive"))
    )
    (net (code "719") (name "unconnected-(JP1019-1-PadP$3)") (class "Default")
      (node (ref "JP1019") (pin "P$3") (pinfunction "1_P$3") (pintype "passive"))
    )
    (net (code "720") (name "unconnected-(JP1020-1-PadP$3)") (class "Default")
      (node (ref "JP1020") (pin "P$3") (pinfunction "1_P$3") (pintype "passive"))
    )
    (net (code "721") (name "unconnected-(JP1021-1-PadP$3)") (class "Default")
      (node (ref "JP1021") (pin "P$3") (pinfunction "1_P$3") (pintype "passive"))
    )
    (net (code "722") (name "unconnected-(JP1022-1-PadP$3)") (class "Default")
      (node (ref "JP1022") (pin "P$3") (pinfunction "1_P$3") (pintype "passive"))
    )
    (net (code "723") (name "unconnected-(JP1023-1-PadP$3)") (class "Default")
      (node (ref "JP1023") (pin "P$3") (pinfunction "1_P$3") (pintype "passive"))
    )
    (net (code "724") (name "unconnected-(JP1024-1-PadP$3)") (class "Default")
      (node (ref "JP1024") (pin "P$3") (pinfunction "1_P$3") (pintype "passive"))
    )
    (net (code "725") (name "unconnected-(JP1025-1-PadP$3)") (class "Default")
      (node (ref "JP1025") (pin "P$3") (pinfunction "1_P$3") (pintype "passive"))
    )
    (net (code "726") (name "unconnected-(JP1026-1-PadP$3)") (class "Default")
      (node (ref "JP1026") (pin "P$3") (pinfunction "1_P$3") (pintype "passive"))
    )
    (net (code "727") (name "unconnected-(JP1027-1-PadP$3)") (class "Default")
      (node (ref "JP1027") (pin "P$3") (pinfunction "1_P$3") (pintype "passive"))
    )
    (net (code "728") (name "unconnected-(JP1028-1-PadP$3)") (class "Default")
      (node (ref "JP1028") (pin "P$3") (pinfunction "1_P$3") (pintype "passive"))
    )
    (net (code "729") (name "unconnected-(JP1029-1-PadP$3)") (class "Default")
      (node (ref "JP1029") (pin "P$3") (pinfunction "1_P$3") (pintype "passive"))
    )
    (net (code "730") (name "unconnected-(JP1030-1-PadP$3)") (class "Default")
      (node (ref "JP1030") (pin "P$3") (pinfunction "1_P$3") (pintype "passive"))
    )
    (net (code "731") (name "unconnected-(JP1031-1-PadP$3)") (class "Default")
      (node (ref "JP1031") (pin "P$3") (pinfunction "1_P$3") (pintype "passive"))
    )
    (net (code "732") (name "unconnected-(JP1032-1-PadP$3)") (class "Default")
      (node (ref "JP1032") (pin "P$3") (pinfunction "1_P$3") (pintype "passive"))
    )
    (net (code "733") (name "unconnected-(JP1033-1-PadP$3)") (class "Default")
      (node (ref "JP1033") (pin "P$3") (pinfunction "1_P$3") (pintype "passive"))
    )
    (net (code "734") (name "unconnected-(JP1034-1-PadP$3)") (class "Default")
      (node (ref "JP1034") (pin "P$3") (pinfunction "1_P$3") (pintype "passive"))
    )
    (net (code "735") (name "unconnected-(JP1035-1-PadP$3)") (class "Default")
      (node (ref "JP1035") (pin "P$3") (pinfunction "1_P$3") (pintype "passive"))
    )
    (net (code "736") (name "unconnected-(JP1036-1-PadP$3)") (class "Default")
      (node (ref "JP1036") (pin "P$3") (pinfunction "1_P$3") (pintype "passive"))
    )
    (net (code "737") (name "unconnected-(JP1037-1-PadP$3)") (class "Default")
      (node (ref "JP1037") (pin "P$3") (pinfunction "1_P$3") (pintype "passive"))
    )
    (net (code "738") (name "unconnected-(JP1038-1-PadP$3)") (class "Default")
      (node (ref "JP1038") (pin "P$3") (pinfunction "1_P$3") (pintype "passive"))
    )
    (net (code "739") (name "unconnected-(JP1039-1-PadP$3)") (class "Default")
      (node (ref "JP1039") (pin "P$3") (pinfunction "1_P$3") (pintype "passive"))
    )
    (net (code "740") (name "unconnected-(JP1040-1-PadP$3)") (class "Default")
      (node (ref "JP1040") (pin "P$3") (pinfunction "1_P$3") (pintype "passive"))
    )
    (net (code "741") (name "unconnected-(JP1041-1-PadP$3)") (class "Default")
      (node (ref "JP1041") (pin "P$3") (pinfunction "1_P$3") (pintype "passive"))
    )
    (net (code "742") (name "unconnected-(JP1042-1-PadP$3)") (class "Default")
      (node (ref "JP1042") (pin "P$3") (pinfunction "1_P$3") (pintype "passive"))
    )
    (net (code "743") (name "unconnected-(JP1043-1-PadP$3)") (class "Default")
      (node (ref "JP1043") (pin "P$3") (pinfunction "1_P$3") (pintype "passive"))
    )
    (net (code "744") (name "unconnected-(JP1044-1-PadP$3)") (class "Default")
      (node (ref "JP1044") (pin "P$3") (pinfunction "1_P$3") (pintype "passive"))
    )
    (net (code "745") (name "unconnected-(JP1045-1-PadP$3)") (class "Default")
      (node (ref "JP1045") (pin "P$3") (pinfunction "1_P$3") (pintype "passive"))
    )
    (net (code "746") (name "unconnected-(JP1046-1-PadP$3)") (class "Default")
      (node (ref "JP1046") (pin "P$3") (pinfunction "1_P$3") (pintype "passive"))
    )
    (net (code "747") (name "unconnected-(JP1047-1-PadP$3)") (class "Default")
      (node (ref "JP1047") (pin "P$3") (pinfunction "1_P$3") (pintype "passive"))
    )
    (net (code "748") (name "unconnected-(JP1048-1-PadP$3)") (class "Default")
      (node (ref "JP1048") (pin "P$3") (pinfunction "1_P$3") (pintype "passive"))
    )
    (net (code "749") (name "unconnected-(JP1049-1-PadP$3)") (class "Default")
      (node (ref "JP1049") (pin "P$3") (pinfunction "1_P$3") (pintype "passive"))
    )
    (net (code "750") (name "unconnected-(JP1050-1-PadP$3)") (class "Default")
      (node (ref "JP1050") (pin "P$3") (pinfunction "1_P$3") (pintype "passive"))
    )
    (net (code "751") (name "unconnected-(JP1051-1-PadP$3)") (class "Default")
      (node (ref "JP1051") (pin "P$3") (pinfunction "1_P$3") (pintype "passive"))
    )
    (net (code "752") (name "unconnected-(JP1052-1-PadP$3)") (class "Default")
      (node (ref "JP1052") (pin "P$3") (pinfunction "1_P$3") (pintype "passive"))
    )
    (net (code "753") (name "unconnected-(JP1053-1-PadP$3)") (class "Default")
      (node (ref "JP1053") (pin "P$3") (pinfunction "1_P$3") (pintype "passive"))
    )
    (net (code "754") (name "unconnected-(JP1054-1-PadP$3)") (class "Default")
      (node (ref "JP1054") (pin "P$3") (pinfunction "1_P$3") (pintype "passive"))
    )
    (net (code "755") (name "unconnected-(JP1055-1-PadP$3)") (class "Default")
      (node (ref "JP1055") (pin "P$3") (pinfunction "1_P$3") (pintype "passive"))
    )
    (net (code "756") (name "unconnected-(JP1056-1-PadP$3)") (class "Default")
      (node (ref "JP1056") (pin "P$3") (pinfunction "1_P$3") (pintype "passive"))
    )
    (net (code "757") (name "unconnected-(JP1057-1-PadP$3)") (class "Default")
      (node (ref "JP1057") (pin "P$3") (pinfunction "1_P$3") (pintype "passive"))
    )
    (net (code "758") (name "unconnected-(JP1058-1-PadP$3)") (class "Default")
      (node (ref "JP1058") (pin "P$3") (pinfunction "1_P$3") (pintype "passive"))
    )
    (net (code "759") (name "unconnected-(JP1059-1-PadP$3)") (class "Default")
      (node (ref "JP1059") (pin "P$3") (pinfunction "1_P$3") (pintype "passive"))
    )
    (net (code "760") (name "unconnected-(JP1060-1-PadP$3)") (class "Default")
      (node (ref "JP1060") (pin "P$3") (pinfunction "1_P$3") (pintype "passive"))
    )
    (net (code "761") (name "unconnected-(JP1061-1-PadP$3)") (class "Default")
      (node (ref "JP1061") (pin "P$3") (pinfunction "1_P$3") (pintype "passive"))
    )
    (net (code "762") (name "unconnected-(JP1062-1-PadP$3)") (class "Default")
      (node (ref "JP1062") (pin "P$3") (pinfunction "1_P$3") (pintype "passive"))
    )
    (net (code "763") (name "unconnected-(JP1063-1-PadP$3)") (class "Default")
      (node (ref "JP1063") (pin "P$3") (pinfunction "1_P$3") (pintype "passive"))
    )
    (net (code "764") (name "unconnected-(JP1064-1-PadP$3)") (class "Default")
      (node (ref "JP1064") (pin "P$3") (pinfunction "1_P$3") (pintype "passive"))
    )
    (net (code "765") (name "unconnected-(JP1065-1-PadP$3)") (class "Default")
      (node (ref "JP1065") (pin "P$3") (pinfunction "1_P$3") (pintype "passive"))
    )
    (net (code "766") (name "unconnected-(JP1066-1-PadP$3)") (class "Default")
      (node (ref "JP1066") (pin "P$3") (pinfunction "1_P$3") (pintype "passive"))
    )
    (net (code "767") (name "unconnected-(JP1067-1-PadP$3)") (class "Default")
      (node (ref "JP1067") (pin "P$3") (pinfunction "1_P$3") (pintype "passive"))
    )
    (net (code "768") (name "unconnected-(JP1068-1-PadP$3)") (class "Default")
      (node (ref "JP1068") (pin "P$3") (pinfunction "1_P$3") (pintype "passive"))
    )
    (net (code "769") (name "unconnected-(JP1069-1-PadP$3)") (class "Default")
      (node (ref "JP1069") (pin "P$3") (pinfunction "1_P$3") (pintype "passive"))
    )
    (net (code "770") (name "unconnected-(JP1070-1-PadP$3)") (class "Default")
      (node (ref "JP1070") (pin "P$3") (pinfunction "1_P$3") (pintype "passive"))
    )
    (net (code "771") (name "unconnected-(JP1071-1-PadP$3)") (class "Default")
      (node (ref "JP1071") (pin "P$3") (pinfunction "1_P$3") (pintype "passive"))
    )
    (net (code "772") (name "unconnected-(JP1072-1-PadP$3)") (class "Default")
      (node (ref "JP1072") (pin "P$3") (pinfunction "1_P$3") (pintype "passive"))
    )
    (net (code "773") (name "unconnected-(JP1073-1-PadP$3)") (class "Default")
      (node (ref "JP1073") (pin "P$3") (pinfunction "1_P$3") (pintype "passive"))
    )
    (net (code "774") (name "unconnected-(JP1074-1-PadP$3)") (class "Default")
      (node (ref "JP1074") (pin "P$3") (pinfunction "1_P$3") (pintype "passive"))
    )
    (net (code "775") (name "unconnected-(JP1075-1-PadP$3)") (class "Default")
      (node (ref "JP1075") (pin "P$3") (pinfunction "1_P$3") (pintype "passive"))
    )
    (net (code "776") (name "unconnected-(JP1076-1-PadP$3)") (class "Default")
      (node (ref "JP1076") (pin "P$3") (pinfunction "1_P$3") (pintype "passive"))
    )
    (net (code "777") (name "unconnected-(JP1077-1-PadP$3)") (class "Default")
      (node (ref "JP1077") (pin "P$3") (pinfunction "1_P$3") (pintype "passive"))
    )
    (net (code "778") (name "unconnected-(JP1078-1-PadP$3)") (class "Default")
      (node (ref "JP1078") (pin "P$3") (pinfunction "1_P$3") (pintype "passive"))
    )
    (net (code "779") (name "unconnected-(JP1079-1-PadP$3)") (class "Default")
      (node (ref "JP1079") (pin "P$3") (pinfunction "1_P$3") (pintype "passive"))
    )
    (net (code "780") (name "unconnected-(JP1080-1-PadP$3)") (class "Default")
      (node (ref "JP1080") (pin "P$3") (pinfunction "1_P$3") (pintype "passive"))
    )
    (net (code "781") (name "unconnected-(JP1081-1-PadP$3)") (class "Default")
      (node (ref "JP1081") (pin "P$3") (pinfunction "1_P$3") (pintype "passive"))
    )
    (net (code "782") (name "unconnected-(JP1082-1-PadP$3)") (class "Default")
      (node (ref "JP1082") (pin "P$3") (pinfunction "1_P$3") (pintype "passive"))
    )
    (net (code "783") (name "unconnected-(JP1083-1-PadP$3)") (class "Default")
      (node (ref "JP1083") (pin "P$3") (pinfunction "1_P$3") (pintype "passive"))
    )
    (net (code "784") (name "unconnected-(JP1084-1-PadP$3)") (class "Default")
      (node (ref "JP1084") (pin "P$3") (pinfunction "1_P$3") (pintype "passive"))
    )
    (net (code "785") (name "unconnected-(JP1085-1-PadP$3)") (class "Default")
      (node (ref "JP1085") (pin "P$3") (pinfunction "1_P$3") (pintype "passive"))
    )
    (net (code "786") (name "unconnected-(JP1086-1-PadP$3)") (class "Default")
      (node (ref "JP1086") (pin "P$3") (pinfunction "1_P$3") (pintype "passive"))
    )
    (net (code "787") (name "unconnected-(JP1087-1-PadP$3)") (class "Default")
      (node (ref "JP1087") (pin "P$3") (pinfunction "1_P$3") (pintype "passive"))
    )
    (net (code "788") (name "unconnected-(JP1088-1-PadP$3)") (class "Default")
      (node (ref "JP1088") (pin "P$3") (pinfunction "1_P$3") (pintype "passive"))
    )
    (net (code "789") (name "unconnected-(JP1089-1-PadP$3)") (class "Default")
      (node (ref "JP1089") (pin "P$3") (pinfunction "1_P$3") (pintype "passive"))
    )
    (net (code "790") (name "unconnected-(JP1090-1-PadP$3)") (class "Default")
      (node (ref "JP1090") (pin "P$3") (pinfunction "1_P$3") (pintype "passive"))
    )
    (net (code "791") (name "unconnected-(JP1091-1-PadP$3)") (class "Default")
      (node (ref "JP1091") (pin "P$3") (pinfunction "1_P$3") (pintype "passive"))
    )
    (net (code "792") (name "unconnected-(JP1092-1-PadP$3)") (class "Default")
      (node (ref "JP1092") (pin "P$3") (pinfunction "1_P$3") (pintype "passive"))
    )
    (net (code "793") (name "unconnected-(JP1093-1-PadP$3)") (class "Default")
      (node (ref "JP1093") (pin "P$3") (pinfunction "1_P$3") (pintype "passive"))
    )
    (net (code "794") (name "unconnected-(JP1094-1-PadP$3)") (class "Default")
      (node (ref "JP1094") (pin "P$3") (pinfunction "1_P$3") (pintype "passive"))
    )
    (net (code "795") (name "unconnected-(JP1095-1-PadP$3)") (class "Default")
      (node (ref "JP1095") (pin "P$3") (pinfunction "1_P$3") (pintype "passive"))
    )
    (net (code "796") (name "unconnected-(JP1096-1-PadP$3)") (class "Default")
      (node (ref "JP1096") (pin "P$3") (pinfunction "1_P$3") (pintype "passive"))
    )
    (net (code "797") (name "unconnected-(JP1097-1-PadP$3)") (class "Default")
      (node (ref "JP1097") (pin "P$3") (pinfunction "1_P$3") (pintype "passive"))
    )
    (net (code "798") (name "unconnected-(JP1098-1-PadP$3)") (class "Default")
      (node (ref "JP1098") (pin "P$3") (pinfunction "1_P$3") (pintype "passive"))
    )
    (net (code "799") (name "unconnected-(JP1099-1-PadP$3)") (class "Default")
      (node (ref "JP1099") (pin "P$3") (pinfunction "1_P$3") (pintype "passive"))
    )
    (net (code "800") (name "unconnected-(JP1100-1-PadP$3)") (class "Default")
      (node (ref "JP1100") (pin "P$3") (pinfunction "1_P$3") (pintype "passive"))
    )
    (net (code "801") (name "unconnected-(JP1101-1-PadP$3)") (class "Default")
      (node (ref "JP1101") (pin "P$3") (pinfunction "1_P$3") (pintype "passive"))
    )
    (net (code "802") (name "unconnected-(JP1102-1-PadP$3)") (class "Default")
      (node (ref "JP1102") (pin "P$3") (pinfunction "1_P$3") (pintype "passive"))
    )
    (net (code "803") (name "unconnected-(JP1103-1-PadP$3)") (class "Default")
      (node (ref "JP1103") (pin "P$3") (pinfunction "1_P$3") (pintype "passive"))
    )
    (net (code "804") (name "unconnected-(JP1104-1-PadP$3)") (class "Default")
      (node (ref "JP1104") (pin "P$3") (pinfunction "1_P$3") (pintype "passive"))
    )
    (net (code "805") (name "unconnected-(JP1105-1-PadP$3)") (class "Default")
      (node (ref "JP1105") (pin "P$3") (pinfunction "1_P$3") (pintype "passive"))
    )
    (net (code "806") (name "unconnected-(JP1106-1-PadP$3)") (class "Default")
      (node (ref "JP1106") (pin "P$3") (pinfunction "1_P$3") (pintype "passive"))
    )
    (net (code "807") (name "unconnected-(JP1107-1-PadP$3)") (class "Default")
      (node (ref "JP1107") (pin "P$3") (pinfunction "1_P$3") (pintype "passive"))
    )
    (net (code "808") (name "unconnected-(JP1108-1-PadP$3)") (class "Default")
      (node (ref "JP1108") (pin "P$3") (pinfunction "1_P$3") (pintype "passive"))
    )
    (net (code "809") (name "unconnected-(JP1109-1-PadP$3)") (class "Default")
      (node (ref "JP1109") (pin "P$3") (pinfunction "1_P$3") (pintype "passive"))
    )
    (net (code "810") (name "unconnected-(JP1110-1-PadP$3)") (class "Default")
      (node (ref "JP1110") (pin "P$3") (pinfunction "1_P$3") (pintype "passive"))
    )
    (net (code "811") (name "unconnected-(JP1111-1-PadP$3)") (class "Default")
      (node (ref "JP1111") (pin "P$3") (pinfunction "1_P$3") (pintype "passive"))
    )
    (net (code "812") (name "unconnected-(JP1112-1-PadP$3)") (class "Default")
      (node (ref "JP1112") (pin "P$3") (pinfunction "1_P$3") (pintype "passive"))
    )
    (net (code "813") (name "unconnected-(JP1113-1-PadP$3)") (class "Default")
      (node (ref "JP1113") (pin "P$3") (pinfunction "1_P$3") (pintype "passive"))
    )
    (net (code "814") (name "unconnected-(JP1114-1-PadP$3)") (class "Default")
      (node (ref "JP1114") (pin "P$3") (pinfunction "1_P$3") (pintype "passive"))
    )
    (net (code "815") (name "unconnected-(JP1115-1-PadP$3)") (class "Default")
      (node (ref "JP1115") (pin "P$3") (pinfunction "1_P$3") (pintype "passive"))
    )
    (net (code "816") (name "unconnected-(JP1116-1-PadP$3)") (class "Default")
      (node (ref "JP1116") (pin "P$3") (pinfunction "1_P$3") (pintype "passive"))
    )
    (net (code "817") (name "unconnected-(JP1117-1-PadP$3)") (class "Default")
      (node (ref "JP1117") (pin "P$3") (pinfunction "1_P$3") (pintype "passive"))
    )
    (net (code "818") (name "unconnected-(JP1118-1-PadP$3)") (class "Default")
      (node (ref "JP1118") (pin "P$3") (pinfunction "1_P$3") (pintype "passive"))
    )
    (net (code "819") (name "unconnected-(JP1119-1-PadP$3)") (class "Default")
      (node (ref "JP1119") (pin "P$3") (pinfunction "1_P$3") (pintype "passive"))
    )
    (net (code "820") (name "unconnected-(JP1120-1-PadP$3)") (class "Default")
      (node (ref "JP1120") (pin "P$3") (pinfunction "1_P$3") (pintype "passive"))
    )
    (net (code "821") (name "unconnected-(JP1121-1-PadP$3)") (class "Default")
      (node (ref "JP1121") (pin "P$3") (pinfunction "1_P$3") (pintype "passive"))
    )
    (net (code "822") (name "unconnected-(JP1122-1-PadP$3)") (class "Default")
      (node (ref "JP1122") (pin "P$3") (pinfunction "1_P$3") (pintype "passive"))
    )
    (net (code "823") (name "unconnected-(JP1123-1-PadP$3)") (class "Default")
      (node (ref "JP1123") (pin "P$3") (pinfunction "1_P$3") (pintype "passive"))
    )
    (net (code "824") (name "unconnected-(JP1124-1-PadP$3)") (class "Default")
      (node (ref "JP1124") (pin "P$3") (pinfunction "1_P$3") (pintype "passive"))
    )
    (net (code "825") (name "unconnected-(JP1125-1-PadP$3)") (class "Default")
      (node (ref "JP1125") (pin "P$3") (pinfunction "1_P$3") (pintype "passive"))
    )
    (net (code "826") (name "unconnected-(JP1126-1-PadP$3)") (class "Default")
      (node (ref "JP1126") (pin "P$3") (pinfunction "1_P$3") (pintype "passive"))
    )
    (net (code "827") (name "unconnected-(JP1127-1-PadP$3)") (class "Default")
      (node (ref "JP1127") (pin "P$3") (pinfunction "1_P$3") (pintype "passive"))
    )
    (net (code "828") (name "unconnected-(JP1128-1-PadP$3)") (class "Default")
      (node (ref "JP1128") (pin "P$3") (pinfunction "1_P$3") (pintype "passive"))
    )
    (net (code "829") (name "unconnected-(JP1129-1-PadP$3)") (class "Default")
      (node (ref "JP1129") (pin "P$3") (pinfunction "1_P$3") (pintype "passive"))
    )
    (net (code "830") (name "unconnected-(JP1130-1-PadP$3)") (class "Default")
      (node (ref "JP1130") (pin "P$3") (pinfunction "1_P$3") (pintype "passive"))
    )
    (net (code "831") (name "unconnected-(JP1131-1-PadP$3)") (class "Default")
      (node (ref "JP1131") (pin "P$3") (pinfunction "1_P$3") (pintype "passive"))
    )
    (net (code "832") (name "unconnected-(JP1132-1-PadP$3)") (class "Default")
      (node (ref "JP1132") (pin "P$3") (pinfunction "1_P$3") (pintype "passive"))
    )
    (net (code "833") (name "unconnected-(JP1133-1-PadP$3)") (class "Default")
      (node (ref "JP1133") (pin "P$3") (pinfunction "1_P$3") (pintype "passive"))
    )
    (net (code "834") (name "unconnected-(JP1134-1-PadP$3)") (class "Default")
      (node (ref "JP1134") (pin "P$3") (pinfunction "1_P$3") (pintype "passive"))
    )
    (net (code "835") (name "unconnected-(JP1135-1-PadP$3)") (class "Default")
      (node (ref "JP1135") (pin "P$3") (pinfunction "1_P$3") (pintype "passive"))
    )
    (net (code "836") (name "unconnected-(JP1136-1-PadP$3)") (class "Default")
      (node (ref "JP1136") (pin "P$3") (pinfunction "1_P$3") (pintype "passive"))
    )
    (net (code "837") (name "unconnected-(JP1137-1-PadP$3)") (class "Default")
      (node (ref "JP1137") (pin "P$3") (pinfunction "1_P$3") (pintype "passive"))
    )
    (net (code "838") (name "unconnected-(JP1138-1-PadP$3)") (class "Default")
      (node (ref "JP1138") (pin "P$3") (pinfunction "1_P$3") (pintype "passive"))
    )
    (net (code "839") (name "unconnected-(JP1139-1-PadP$3)") (class "Default")
      (node (ref "JP1139") (pin "P$3") (pinfunction "1_P$3") (pintype "passive"))
    )
    (net (code "840") (name "unconnected-(JP1140-1-PadP$3)") (class "Default")
      (node (ref "JP1140") (pin "P$3") (pinfunction "1_P$3") (pintype "passive"))
    )
    (net (code "841") (name "unconnected-(JP1141-1-PadP$3)") (class "Default")
      (node (ref "JP1141") (pin "P$3") (pinfunction "1_P$3") (pintype "passive"))
    )
    (net (code "842") (name "unconnected-(JP1142-1-PadP$3)") (class "Default")
      (node (ref "JP1142") (pin "P$3") (pinfunction "1_P$3") (pintype "passive"))
    )
    (net (code "843") (name "unconnected-(JP1143-1-PadP$3)") (class "Default")
      (node (ref "JP1143") (pin "P$3") (pinfunction "1_P$3") (pintype "passive"))
    )
    (net (code "844") (name "unconnected-(JP1144-1-PadP$3)") (class "Default")
      (node (ref "JP1144") (pin "P$3") (pinfunction "1_P$3") (pintype "passive"))
    )
    (net (code "845") (name "unconnected-(JP1145-1-PadP$3)") (class "Default")
      (node (ref "JP1145") (pin "P$3") (pinfunction "1_P$3") (pintype "passive"))
    )
    (net (code "846") (name "unconnected-(JP1146-1-PadP$3)") (class "Default")
      (node (ref "JP1146") (pin "P$3") (pinfunction "1_P$3") (pintype "passive"))
    )
    (net (code "847") (name "unconnected-(JP1147-1-PadP$3)") (class "Default")
      (node (ref "JP1147") (pin "P$3") (pinfunction "1_P$3") (pintype "passive"))
    )
    (net (code "848") (name "unconnected-(JP1148-1-PadP$3)") (class "Default")
      (node (ref "JP1148") (pin "P$3") (pinfunction "1_P$3") (pintype "passive"))
    )
    (net (code "849") (name "unconnected-(JP1149-1-PadP$3)") (class "Default")
      (node (ref "JP1149") (pin "P$3") (pinfunction "1_P$3") (pintype "passive"))
    )
    (net (code "850") (name "unconnected-(JP1150-1-PadP$3)") (class "Default")
      (node (ref "JP1150") (pin "P$3") (pinfunction "1_P$3") (pintype "passive"))
    )
    (net (code "851") (name "unconnected-(JP1151-1-PadP$3)") (class "Default")
      (node (ref "JP1151") (pin "P$3") (pinfunction "1_P$3") (pintype "passive"))
    )
    (net (code "852") (name "unconnected-(JP1152-1-PadP$3)") (class "Default")
      (node (ref "JP1152") (pin "P$3") (pinfunction "1_P$3") (pintype "passive"))
    )
    (net (code "853") (name "unconnected-(JP1153-1-PadP$3)") (class "Default")
      (node (ref "JP1153") (pin "P$3") (pinfunction "1_P$3") (pintype "passive"))
    )
    (net (code "854") (name "unconnected-(JP1154-1-PadP$3)") (class "Default")
      (node (ref "JP1154") (pin "P$3") (pinfunction "1_P$3") (pintype "passive"))
    )
    (net (code "855") (name "unconnected-(JP1155-1-PadP$3)") (class "Default")
      (node (ref "JP1155") (pin "P$3") (pinfunction "1_P$3") (pintype "passive"))
    )
    (net (code "856") (name "unconnected-(JP1156-1-PadP$3)") (class "Default")
      (node (ref "JP1156") (pin "P$3") (pinfunction "1_P$3") (pintype "passive"))
    )
    (net (code "857") (name "unconnected-(JP1157-1-PadP$3)") (class "Default")
      (node (ref "JP1157") (pin "P$3") (pinfunction "1_P$3") (pintype "passive"))
    )
    (net (code "858") (name "unconnected-(JP1158-1-PadP$3)") (class "Default")
      (node (ref "JP1158") (pin "P$3") (pinfunction "1_P$3") (pintype "passive"))
    )
    (net (code "859") (name "unconnected-(JP1159-1-PadP$3)") (class "Default")
      (node (ref "JP1159") (pin "P$3") (pinfunction "1_P$3") (pintype "passive"))
    )
    (net (code "860") (name "unconnected-(JP1160-1-PadP$3)") (class "Default")
      (node (ref "JP1160") (pin "P$3") (pinfunction "1_P$3") (pintype "passive"))
    )
    (net (code "861") (name "unconnected-(JP1161-1-PadP$3)") (class "Default")
      (node (ref "JP1161") (pin "P$3") (pinfunction "1_P$3") (pintype "passive"))
    )
    (net (code "862") (name "unconnected-(JP1162-1-PadP$3)") (class "Default")
      (node (ref "JP1162") (pin "P$3") (pinfunction "1_P$3") (pintype "passive"))
    )
    (net (code "863") (name "unconnected-(JP1163-1-PadP$3)") (class "Default")
      (node (ref "JP1163") (pin "P$3") (pinfunction "1_P$3") (pintype "passive"))
    )
    (net (code "864") (name "unconnected-(JP1164-1-PadP$3)") (class "Default")
      (node (ref "JP1164") (pin "P$3") (pinfunction "1_P$3") (pintype "passive"))
    )
    (net (code "865") (name "unconnected-(JP1165-1-PadP$3)") (class "Default")
      (node (ref "JP1165") (pin "P$3") (pinfunction "1_P$3") (pintype "passive"))
    )
    (net (code "866") (name "unconnected-(JP1166-1-PadP$3)") (class "Default")
      (node (ref "JP1166") (pin "P$3") (pinfunction "1_P$3") (pintype "passive"))
    )
    (net (code "867") (name "unconnected-(JP1167-1-PadP$3)") (class "Default")
      (node (ref "JP1167") (pin "P$3") (pinfunction "1_P$3") (pintype "passive"))
    )
    (net (code "868") (name "unconnected-(JP1168-1-PadP$3)") (class "Default")
      (node (ref "JP1168") (pin "P$3") (pinfunction "1_P$3") (pintype "passive"))
    )
    (net (code "869") (name "unconnected-(JP1169-1-PadP$3)") (class "Default")
      (node (ref "JP1169") (pin "P$3") (pinfunction "1_P$3") (pintype "passive"))
    )
    (net (code "870") (name "unconnected-(JP1170-1-PadP$3)") (class "Default")
      (node (ref "JP1170") (pin "P$3") (pinfunction "1_P$3") (pintype "passive"))
    )
    (net (code "871") (name "unconnected-(JP1171-1-PadP$3)") (class "Default")
      (node (ref "JP1171") (pin "P$3") (pinfunction "1_P$3") (pintype "passive"))
    )
    (net (code "872") (name "unconnected-(JP1172-1-PadP$3)") (class "Default")
      (node (ref "JP1172") (pin "P$3") (pinfunction "1_P$3") (pintype "passive"))
    )
    (net (code "873") (name "unconnected-(JP1173-1-PadP$3)") (class "Default")
      (node (ref "JP1173") (pin "P$3") (pinfunction "1_P$3") (pintype "passive"))
    )
    (net (code "874") (name "unconnected-(JP1174-1-PadP$3)") (class "Default")
      (node (ref "JP1174") (pin "P$3") (pinfunction "1_P$3") (pintype "passive"))
    )
    (net (code "875") (name "unconnected-(JP1175-1-PadP$3)") (class "Default")
      (node (ref "JP1175") (pin "P$3") (pinfunction "1_P$3") (pintype "passive"))
    )
    (net (code "876") (name "unconnected-(JP1176-1-PadP$3)") (class "Default")
      (node (ref "JP1176") (pin "P$3") (pinfunction "1_P$3") (pintype "passive"))
    )
    (net (code "877") (name "unconnected-(JP1177-1-PadP$3)") (class "Default")
      (node (ref "JP1177") (pin "P$3") (pinfunction "1_P$3") (pintype "passive"))
    )
    (net (code "878") (name "unconnected-(JP1178-1-PadP$3)") (class "Default")
      (node (ref "JP1178") (pin "P$3") (pinfunction "1_P$3") (pintype "passive"))
    )
    (net (code "879") (name "unconnected-(JP1179-1-PadP$3)") (class "Default")
      (node (ref "JP1179") (pin "P$3") (pinfunction "1_P$3") (pintype "passive"))
    )
    (net (code "880") (name "unconnected-(JP1180-1-PadP$3)") (class "Default")
      (node (ref "JP1180") (pin "P$3") (pinfunction "1_P$3") (pintype "passive"))
    )
    (net (code "881") (name "unconnected-(JP1181-1-PadP$3)") (class "Default")
      (node (ref "JP1181") (pin "P$3") (pinfunction "1_P$3") (pintype "passive"))
    )
    (net (code "882") (name "unconnected-(JP1182-1-PadP$3)") (class "Default")
      (node (ref "JP1182") (pin "P$3") (pinfunction "1_P$3") (pintype "passive"))
    )
    (net (code "883") (name "unconnected-(JP1183-1-PadP$3)") (class "Default")
      (node (ref "JP1183") (pin "P$3") (pinfunction "1_P$3") (pintype "passive"))
    )
    (net (code "884") (name "unconnected-(JP1184-1-PadP$3)") (class "Default")
      (node (ref "JP1184") (pin "P$3") (pinfunction "1_P$3") (pintype "passive"))
    )
    (net (code "885") (name "unconnected-(JP1185-1-PadP$3)") (class "Default")
      (node (ref "JP1185") (pin "P$3") (pinfunction "1_P$3") (pintype "passive"))
    )
    (net (code "886") (name "unconnected-(JP1186-1-PadP$3)") (class "Default")
      (node (ref "JP1186") (pin "P$3") (pinfunction "1_P$3") (pintype "passive"))
    )
    (net (code "887") (name "unconnected-(JP1187-1-PadP$3)") (class "Default")
      (node (ref "JP1187") (pin "P$3") (pinfunction "1_P$3") (pintype "passive"))
    )
    (net (code "888") (name "unconnected-(JP1188-1-PadP$3)") (class "Default")
      (node (ref "JP1188") (pin "P$3") (pinfunction "1_P$3") (pintype "passive"))
    )
    (net (code "889") (name "unconnected-(JP1189-1-PadP$3)") (class "Default")
      (node (ref "JP1189") (pin "P$3") (pinfunction "1_P$3") (pintype "passive"))
    )
    (net (code "890") (name "unconnected-(JP1190-1-PadP$3)") (class "Default")
      (node (ref "JP1190") (pin "P$3") (pinfunction "1_P$3") (pintype "passive"))
    )
    (net (code "891") (name "unconnected-(JP1191-1-PadP$3)") (class "Default")
      (node (ref "JP1191") (pin "P$3") (pinfunction "1_P$3") (pintype "passive"))
    )
    (net (code "892") (name "unconnected-(JP1192-1-PadP$3)") (class "Default")
      (node (ref "JP1192") (pin "P$3") (pinfunction "1_P$3") (pintype "passive"))
    )
    (net (code "893") (name "unconnected-(JP1193-1-PadP$3)") (class "Default")
      (node (ref "JP1193") (pin "P$3") (pinfunction "1_P$3") (pintype "passive"))
    )
    (net (code "894") (name "unconnected-(JP1194-1-PadP$3)") (class "Default")
      (node (ref "JP1194") (pin "P$3") (pinfunction "1_P$3") (pintype "passive"))
    )
    (net (code "895") (name "unconnected-(JP1195-1-PadP$3)") (class "Default")
      (node (ref "JP1195") (pin "P$3") (pinfunction "1_P$3") (pintype "passive"))
    )
    (net (code "896") (name "unconnected-(JP1196-1-PadP$3)") (class "Default")
      (node (ref "JP1196") (pin "P$3") (pinfunction "1_P$3") (pintype "passive"))
    )
    (net (code "897") (name "unconnected-(JP1197-1-PadP$3)") (class "Default")
      (node (ref "JP1197") (pin "P$3") (pinfunction "1_P$3") (pintype "passive"))
    )
    (net (code "898") (name "unconnected-(JP1198-1-PadP$3)") (class "Default")
      (node (ref "JP1198") (pin "P$3") (pinfunction "1_P$3") (pintype "passive"))
    )
    (net (code "899") (name "unconnected-(JP1199-1-PadP$3)") (class "Default")
      (node (ref "JP1199") (pin "P$3") (pinfunction "1_P$3") (pintype "passive"))
    )
    (net (code "900") (name "unconnected-(JP1200-1-PadP$3)") (class "Default")
      (node (ref "JP1200") (pin "P$3") (pinfunction "1_P$3") (pintype "passive"))
    )
    (net (code "901") (name "unconnected-(JP1201-1-PadP$3)") (class "Default")
      (node (ref "JP1201") (pin "P$3") (pinfunction "1_P$3") (pintype "passive"))
    )
    (net (code "902") (name "unconnected-(JP1202-1-PadP$3)") (class "Default")
      (node (ref "JP1202") (pin "P$3") (pinfunction "1_P$3") (pintype "passive"))
    )
    (net (code "903") (name "unconnected-(JP1203-1-PadP$3)") (class "Default")
      (node (ref "JP1203") (pin "P$3") (pinfunction "1_P$3") (pintype "passive"))
    )
    (net (code "904") (name "unconnected-(JP1204-1-PadP$3)") (class "Default")
      (node (ref "JP1204") (pin "P$3") (pinfunction "1_P$3") (pintype "passive"))
    )
    (net (code "905") (name "unconnected-(JP1205-1-PadP$3)") (class "Default")
      (node (ref "JP1205") (pin "P$3") (pinfunction "1_P$3") (pintype "passive"))
    )
    (net (code "906") (name "unconnected-(JP1206-1-PadP$3)") (class "Default")
      (node (ref "JP1206") (pin "P$3") (pinfunction "1_P$3") (pintype "passive"))
    )
    (net (code "907") (name "unconnected-(JP1207-1-PadP$3)") (class "Default")
      (node (ref "JP1207") (pin "P$3") (pinfunction "1_P$3") (pintype "passive"))
    )
    (net (code "908") (name "unconnected-(JP1208-1-PadP$3)") (class "Default")
      (node (ref "JP1208") (pin "P$3") (pinfunction "1_P$3") (pintype "passive"))
    )
    (net (code "909") (name "unconnected-(JP1209-1-PadP$3)") (class "Default")
      (node (ref "JP1209") (pin "P$3") (pinfunction "1_P$3") (pintype "passive"))
    )
    (net (code "910") (name "unconnected-(JP1210-1-PadP$3)") (class "Default")
      (node (ref "JP1210") (pin "P$3") (pinfunction "1_P$3") (pintype "passive"))
    )
    (net (code "911") (name "unconnected-(JP1211-1-PadP$3)") (class "Default")
      (node (ref "JP1211") (pin "P$3") (pinfunction "1_P$3") (pintype "passive"))
    )
    (net (code "912") (name "unconnected-(JP1212-1-PadP$3)") (class "Default")
      (node (ref "JP1212") (pin "P$3") (pinfunction "1_P$3") (pintype "passive"))
    )
    (net (code "913") (name "unconnected-(JP1213-1-PadP$3)") (class "Default")
      (node (ref "JP1213") (pin "P$3") (pinfunction "1_P$3") (pintype "passive"))
    )
    (net (code "914") (name "unconnected-(JP1214-1-PadP$3)") (class "Default")
      (node (ref "JP1214") (pin "P$3") (pinfunction "1_P$3") (pintype "passive"))
    )
    (net (code "915") (name "unconnected-(JP1215-1-PadP$3)") (class "Default")
      (node (ref "JP1215") (pin "P$3") (pinfunction "1_P$3") (pintype "passive"))
    )
    (net (code "916") (name "unconnected-(JP1216-1-PadP$3)") (class "Default")
      (node (ref "JP1216") (pin "P$3") (pinfunction "1_P$3") (pintype "passive"))
    )
    (net (code "917") (name "unconnected-(JP1217-1-PadP$3)") (class "Default")
      (node (ref "JP1217") (pin "P$3") (pinfunction "1_P$3") (pintype "passive"))
    )
    (net (code "918") (name "unconnected-(JP1218-1-PadP$3)") (class "Default")
      (node (ref "JP1218") (pin "P$3") (pinfunction "1_P$3") (pintype "passive"))
    )
    (net (code "919") (name "unconnected-(JP1219-1-PadP$3)") (class "Default")
      (node (ref "JP1219") (pin "P$3") (pinfunction "1_P$3") (pintype "passive"))
    )
    (net (code "920") (name "unconnected-(JP1220-1-PadP$3)") (class "Default")
      (node (ref "JP1220") (pin "P$3") (pinfunction "1_P$3") (pintype "passive"))
    )
    (net (code "921") (name "unconnected-(JP1221-1-PadP$3)") (class "Default")
      (node (ref "JP1221") (pin "P$3") (pinfunction "1_P$3") (pintype "passive"))
    )
    (net (code "922") (name "unconnected-(JP1222-1-PadP$3)") (class "Default")
      (node (ref "JP1222") (pin "P$3") (pinfunction "1_P$3") (pintype "passive"))
    )
    (net (code "923") (name "unconnected-(JP1223-1-PadP$3)") (class "Default")
      (node (ref "JP1223") (pin "P$3") (pinfunction "1_P$3") (pintype "passive"))
    )
    (net (code "924") (name "unconnected-(JP1224-1-PadP$3)") (class "Default")
      (node (ref "JP1224") (pin "P$3") (pinfunction "1_P$3") (pintype "passive"))
    )
    (net (code "925") (name "unconnected-(JP1225-1-PadP$3)") (class "Default")
      (node (ref "JP1225") (pin "P$3") (pinfunction "1_P$3") (pintype "passive"))
    )
    (net (code "926") (name "unconnected-(JP1226-1-PadP$3)") (class "Default")
      (node (ref "JP1226") (pin "P$3") (pinfunction "1_P$3") (pintype "passive"))
    )
    (net (code "927") (name "unconnected-(JP1227-1-PadP$3)") (class "Default")
      (node (ref "JP1227") (pin "P$3") (pinfunction "1_P$3") (pintype "passive"))
    )
    (net (code "928") (name "unconnected-(JP1228-1-PadP$3)") (class "Default")
      (node (ref "JP1228") (pin "P$3") (pinfunction "1_P$3") (pintype "passive"))
    )
    (net (code "929") (name "unconnected-(JP1229-1-PadP$3)") (class "Default")
      (node (ref "JP1229") (pin "P$3") (pinfunction "1_P$3") (pintype "passive"))
    )
    (net (code "930") (name "unconnected-(JP1230-1-PadP$3)") (class "Default")
      (node (ref "JP1230") (pin "P$3") (pinfunction "1_P$3") (pintype "passive"))
    )
    (net (code "931") (name "unconnected-(JP1231-1-PadP$3)") (class "Default")
      (node (ref "JP1231") (pin "P$3") (pinfunction "1_P$3") (pintype "passive"))
    )
    (net (code "932") (name "unconnected-(JP1232-1-PadP$3)") (class "Default")
      (node (ref "JP1232") (pin "P$3") (pinfunction "1_P$3") (pintype "passive"))
    )
    (net (code "933") (name "unconnected-(JP1233-1-PadP$3)") (class "Default")
      (node (ref "JP1233") (pin "P$3") (pinfunction "1_P$3") (pintype "passive"))
    )
    (net (code "934") (name "unconnected-(JP1234-1-PadP$3)") (class "Default")
      (node (ref "JP1234") (pin "P$3") (pinfunction "1_P$3") (pintype "passive"))
    )
    (net (code "935") (name "unconnected-(JP1235-1-PadP$3)") (class "Default")
      (node (ref "JP1235") (pin "P$3") (pinfunction "1_P$3") (pintype "passive"))
    )
    (net (code "936") (name "unconnected-(JP1236-1-PadP$3)") (class "Default")
      (node (ref "JP1236") (pin "P$3") (pinfunction "1_P$3") (pintype "passive"))
    )
    (net (code "937") (name "unconnected-(JP1237-1-PadP$3)") (class "Default")
      (node (ref "JP1237") (pin "P$3") (pinfunction "1_P$3") (pintype "passive"))
    )
    (net (code "938") (name "unconnected-(JP1238-1-PadP$3)") (class "Default")
      (node (ref "JP1238") (pin "P$3") (pinfunction "1_P$3") (pintype "passive"))
    )
    (net (code "939") (name "unconnected-(JP1239-1-PadP$3)") (class "Default")
      (node (ref "JP1239") (pin "P$3") (pinfunction "1_P$3") (pintype "passive"))
    )
    (net (code "940") (name "unconnected-(JP1240-1-PadP$3)") (class "Default")
      (node (ref "JP1240") (pin "P$3") (pinfunction "1_P$3") (pintype "passive"))
    )
    (net (code "941") (name "unconnected-(JP1241-1-PadP$3)") (class "Default")
      (node (ref "JP1241") (pin "P$3") (pinfunction "1_P$3") (pintype "passive"))
    )
    (net (code "942") (name "unconnected-(JP1242-1-PadP$3)") (class "Default")
      (node (ref "JP1242") (pin "P$3") (pinfunction "1_P$3") (pintype "passive"))
    )
    (net (code "943") (name "unconnected-(JP1243-1-PadP$3)") (class "Default")
      (node (ref "JP1243") (pin "P$3") (pinfunction "1_P$3") (pintype "passive"))
    )
    (net (code "944") (name "unconnected-(JP1244-1-PadP$3)") (class "Default")
      (node (ref "JP1244") (pin "P$3") (pinfunction "1_P$3") (pintype "passive"))
    )
    (net (code "945") (name "unconnected-(JP1245-1-PadP$3)") (class "Default")
      (node (ref "JP1245") (pin "P$3") (pinfunction "1_P$3") (pintype "passive"))
    )
    (net (code "946") (name "unconnected-(JP1246-1-PadP$3)") (class "Default")
      (node (ref "JP1246") (pin "P$3") (pinfunction "1_P$3") (pintype "passive"))
    )
    (net (code "947") (name "unconnected-(JP1247-1-PadP$3)") (class "Default")
      (node (ref "JP1247") (pin "P$3") (pinfunction "1_P$3") (pintype "passive"))
    )
    (net (code "948") (name "unconnected-(JP1248-1-PadP$3)") (class "Default")
      (node (ref "JP1248") (pin "P$3") (pinfunction "1_P$3") (pintype "passive"))
    )
    (net (code "949") (name "unconnected-(JP1249-1-PadP$3)") (class "Default")
      (node (ref "JP1249") (pin "P$3") (pinfunction "1_P$3") (pintype "passive"))
    )
    (net (code "950") (name "unconnected-(JP1250-1-PadP$3)") (class "Default")
      (node (ref "JP1250") (pin "P$3") (pinfunction "1_P$3") (pintype "passive"))
    )
    (net (code "951") (name "unconnected-(JP1251-1-PadP$3)") (class "Default")
      (node (ref "JP1251") (pin "P$3") (pinfunction "1_P$3") (pintype "passive"))
    )
    (net (code "952") (name "unconnected-(JP1252-1-PadP$3)") (class "Default")
      (node (ref "JP1252") (pin "P$3") (pinfunction "1_P$3") (pintype "passive"))
    )
    (net (code "953") (name "unconnected-(JP1253-1-PadP$3)") (class "Default")
      (node (ref "JP1253") (pin "P$3") (pinfunction "1_P$3") (pintype "passive"))
    )
    (net (code "954") (name "unconnected-(JP1254-1-PadP$3)") (class "Default")
      (node (ref "JP1254") (pin "P$3") (pinfunction "1_P$3") (pintype "passive"))
    )
    (net (code "955") (name "unconnected-(JP1255-1-PadP$3)") (class "Default")
      (node (ref "JP1255") (pin "P$3") (pinfunction "1_P$3") (pintype "passive"))
    )
    (net (code "956") (name "unconnected-(JP1256-1-PadP$3)") (class "Default")
      (node (ref "JP1256") (pin "P$3") (pinfunction "1_P$3") (pintype "passive"))
    )
    (net (code "957") (name "unconnected-(JP1257-1-PadP$3)") (class "Default")
      (node (ref "JP1257") (pin "P$3") (pinfunction "1_P$3") (pintype "passive"))
    )
    (net (code "958") (name "unconnected-(JP1258-1-PadP$3)") (class "Default")
      (node (ref "JP1258") (pin "P$3") (pinfunction "1_P$3") (pintype "passive"))
    )
    (net (code "959") (name "unconnected-(JP1259-1-PadP$3)") (class "Default")
      (node (ref "JP1259") (pin "P$3") (pinfunction "1_P$3") (pintype "passive"))
    )
    (net (code "960") (name "unconnected-(JP1260-1-PadP$3)") (class "Default")
      (node (ref "JP1260") (pin "P$3") (pinfunction "1_P$3") (pintype "passive"))
    )
    (net (code "961") (name "unconnected-(JP1261-1-PadP$3)") (class "Default")
      (node (ref "JP1261") (pin "P$3") (pinfunction "1_P$3") (pintype "passive"))
    )
    (net (code "962") (name "unconnected-(JP1262-1-PadP$3)") (class "Default")
      (node (ref "JP1262") (pin "P$3") (pinfunction "1_P$3") (pintype "passive"))
    )
    (net (code "963") (name "unconnected-(JP1263-1-PadP$3)") (class "Default")
      (node (ref "JP1263") (pin "P$3") (pinfunction "1_P$3") (pintype "passive"))
    )
    (net (code "964") (name "unconnected-(JP1264-1-PadP$3)") (class "Default")
      (node (ref "JP1264") (pin "P$3") (pinfunction "1_P$3") (pintype "passive"))
    )
    (net (code "965") (name "unconnected-(JP1265-1-PadP$3)") (class "Default")
      (node (ref "JP1265") (pin "P$3") (pinfunction "1_P$3") (pintype "passive"))
    )
    (net (code "966") (name "unconnected-(JP1266-1-PadP$3)") (class "Default")
      (node (ref "JP1266") (pin "P$3") (pinfunction "1_P$3") (pintype "passive"))
    )
    (net (code "967") (name "unconnected-(JP1267-1-PadP$3)") (class "Default")
      (node (ref "JP1267") (pin "P$3") (pinfunction "1_P$3") (pintype "passive"))
    )
    (net (code "968") (name "unconnected-(JP1268-1-PadP$3)") (class "Default")
      (node (ref "JP1268") (pin "P$3") (pinfunction "1_P$3") (pintype "passive"))
    )
    (net (code "969") (name "unconnected-(JP1269-1-PadP$3)") (class "Default")
      (node (ref "JP1269") (pin "P$3") (pinfunction "1_P$3") (pintype "passive"))
    )
    (net (code "970") (name "unconnected-(JP1270-1-PadP$3)") (class "Default")
      (node (ref "JP1270") (pin "P$3") (pinfunction "1_P$3") (pintype "passive"))
    )
    (net (code "971") (name "unconnected-(JP1271-1-PadP$3)") (class "Default")
      (node (ref "JP1271") (pin "P$3") (pinfunction "1_P$3") (pintype "passive"))
    )
    (net (code "972") (name "unconnected-(JP1272-1-PadP$3)") (class "Default")
      (node (ref "JP1272") (pin "P$3") (pinfunction "1_P$3") (pintype "passive"))
    )
    (net (code "973") (name "unconnected-(JP1273-1-PadP$3)") (class "Default")
      (node (ref "JP1273") (pin "P$3") (pinfunction "1_P$3") (pintype "passive"))
    )
    (net (code "974") (name "unconnected-(JP1274-1-PadP$3)") (class "Default")
      (node (ref "JP1274") (pin "P$3") (pinfunction "1_P$3") (pintype "passive"))
    )
    (net (code "975") (name "unconnected-(JP1275-1-PadP$3)") (class "Default")
      (node (ref "JP1275") (pin "P$3") (pinfunction "1_P$3") (pintype "passive"))
    )
    (net (code "976") (name "unconnected-(JP1276-1-PadP$3)") (class "Default")
      (node (ref "JP1276") (pin "P$3") (pinfunction "1_P$3") (pintype "passive"))
    )
    (net (code "977") (name "unconnected-(JP1277-1-PadP$3)") (class "Default")
      (node (ref "JP1277") (pin "P$3") (pinfunction "1_P$3") (pintype "passive"))
    )
    (net (code "978") (name "unconnected-(JP1278-1-PadP$3)") (class "Default")
      (node (ref "JP1278") (pin "P$3") (pinfunction "1_P$3") (pintype "passive"))
    )
    (net (code "979") (name "unconnected-(JP1279-1-PadP$3)") (class "Default")
      (node (ref "JP1279") (pin "P$3") (pinfunction "1_P$3") (pintype "passive"))
    )
    (net (code "980") (name "unconnected-(JP1280-1-PadP$3)") (class "Default")
      (node (ref "JP1280") (pin "P$3") (pinfunction "1_P$3") (pintype "passive"))
    )
    (net (code "981") (name "unconnected-(JP1281-1-PadP$3)") (class "Default")
      (node (ref "JP1281") (pin "P$3") (pinfunction "1_P$3") (pintype "passive"))
    )
    (net (code "982") (name "unconnected-(JP1282-1-PadP$3)") (class "Default")
      (node (ref "JP1282") (pin "P$3") (pinfunction "1_P$3") (pintype "passive"))
    )
    (net (code "983") (name "unconnected-(JP1283-1-PadP$3)") (class "Default")
      (node (ref "JP1283") (pin "P$3") (pinfunction "1_P$3") (pintype "passive"))
    )
    (net (code "984") (name "unconnected-(JP1284-1-PadP$3)") (class "Default")
      (node (ref "JP1284") (pin "P$3") (pinfunction "1_P$3") (pintype "passive"))
    )
    (net (code "985") (name "unconnected-(JP1285-1-PadP$3)") (class "Default")
      (node (ref "JP1285") (pin "P$3") (pinfunction "1_P$3") (pintype "passive"))
    )
    (net (code "986") (name "unconnected-(JP1286-1-PadP$3)") (class "Default")
      (node (ref "JP1286") (pin "P$3") (pinfunction "1_P$3") (pintype "passive"))
    )
    (net (code "987") (name "unconnected-(JP1287-1-PadP$3)") (class "Default")
      (node (ref "JP1287") (pin "P$3") (pinfunction "1_P$3") (pintype "passive"))
    )
    (net (code "988") (name "unconnected-(JP1288-1-PadP$3)") (class "Default")
      (node (ref "JP1288") (pin "P$3") (pinfunction "1_P$3") (pintype "passive"))
    )
    (net (code "989") (name "unconnected-(JP1289-1-PadP$3)") (class "Default")
      (node (ref "JP1289") (pin "P$3") (pinfunction "1_P$3") (pintype "passive"))
    )
    (net (code "990") (name "unconnected-(JP1290-1-PadP$3)") (class "Default")
      (node (ref "JP1290") (pin "P$3") (pinfunction "1_P$3") (pintype "passive"))
    )
    (net (code "991") (name "unconnected-(JP1291-1-PadP$3)") (class "Default")
      (node (ref "JP1291") (pin "P$3") (pinfunction "1_P$3") (pintype "passive"))
    )
    (net (code "992") (name "unconnected-(JP1292-1-PadP$3)") (class "Default")
      (node (ref "JP1292") (pin "P$3") (pinfunction "1_P$3") (pintype "passive"))
    )
    (net (code "993") (name "unconnected-(JP1293-1-PadP$3)") (class "Default")
      (node (ref "JP1293") (pin "P$3") (pinfunction "1_P$3") (pintype "passive"))
    )
    (net (code "994") (name "unconnected-(JP1294-1-PadP$3)") (class "Default")
      (node (ref "JP1294") (pin "P$3") (pinfunction "1_P$3") (pintype "passive"))
    )
    (net (code "995") (name "unconnected-(JP1295-1-PadP$3)") (class "Default")
      (node (ref "JP1295") (pin "P$3") (pinfunction "1_P$3") (pintype "passive"))
    )
    (net (code "996") (name "unconnected-(JP1296-1-PadP$3)") (class "Default")
      (node (ref "JP1296") (pin "P$3") (pinfunction "1_P$3") (pintype "passive"))
    )
    (net (code "997") (name "unconnected-(JP1297-1-PadP$3)") (class "Default")
      (node (ref "JP1297") (pin "P$3") (pinfunction "1_P$3") (pintype "passive"))
    )
    (net (code "998") (name "unconnected-(JP1298-1-PadP$3)") (class "Default")
      (node (ref "JP1298") (pin "P$3") (pinfunction "1_P$3") (pintype "passive"))
    )
    (net (code "999") (name "unconnected-(JP1299-1-PadP$3)") (class "Default")
      (node (ref "JP1299") (pin "P$3") (pinfunction "1_P$3") (pintype "passive"))
    )
    (net (code "1000") (name "unconnected-(JP1300-1-PadP$3)") (class "Default")
      (node (ref "JP1300") (pin "P$3") (pinfunction "1_P$3") (pintype "passive"))
    )
    (net (code "1001") (name "unconnected-(JP1301-1-PadP$3)") (class "Default")
      (node (ref "JP1301") (pin "P$3") (pinfunction "1_P$3") (pintype "passive"))
    )
    (net (code "1002") (name "unconnected-(JP1302-1-PadP$3)") (class "Default")
      (node (ref "JP1302") (pin "P$3") (pinfunction "1_P$3") (pintype "passive"))
    )
    (net (code "1003") (name "unconnected-(JP1303-1-PadP$3)") (class "Default")
      (node (ref "JP1303") (pin "P$3") (pinfunction "1_P$3") (pintype "passive"))
    )
    (net (code "1004") (name "unconnected-(JP1304-1-PadP$3)") (class "Default")
      (node (ref "JP1304") (pin "P$3") (pinfunction "1_P$3") (pintype "passive"))
    )
    (net (code "1005") (name "unconnected-(JP1305-1-PadP$3)") (class "Default")
      (node (ref "JP1305") (pin "P$3") (pinfunction "1_P$3") (pintype "passive"))
    )
    (net (code "1006") (name "unconnected-(JP1306-1-PadP$3)") (class "Default")
      (node (ref "JP1306") (pin "P$3") (pinfunction "1_P$3") (pintype "passive"))
    )
    (net (code "1007") (name "unconnected-(JP1307-1-PadP$3)") (class "Default")
      (node (ref "JP1307") (pin "P$3") (pinfunction "1_P$3") (pintype "passive"))
    )
    (net (code "1008") (name "unconnected-(JP1308-1-PadP$3)") (class "Default")
      (node (ref "JP1308") (pin "P$3") (pinfunction "1_P$3") (pintype "passive"))
    )
    (net (code "1009") (name "unconnected-(JP1309-1-PadP$3)") (class "Default")
      (node (ref "JP1309") (pin "P$3") (pinfunction "1_P$3") (pintype "passive"))
    )
    (net (code "1010") (name "unconnected-(JP1310-1-PadP$3)") (class "Default")
      (node (ref "JP1310") (pin "P$3") (pinfunction "1_P$3") (pintype "passive"))
    )
    (net (code "1011") (name "unconnected-(JP1311-1-PadP$3)") (class "Default")
      (node (ref "JP1311") (pin "P$3") (pinfunction "1_P$3") (pintype "passive"))
    )
    (net (code "1012") (name "unconnected-(JP1312-1-PadP$3)") (class "Default")
      (node (ref "JP1312") (pin "P$3") (pinfunction "1_P$3") (pintype "passive"))
    )
    (net (code "1013") (name "unconnected-(JP1313-1-PadP$3)") (class "Default")
      (node (ref "JP1313") (pin "P$3") (pinfunction "1_P$3") (pintype "passive"))
    )
    (net (code "1014") (name "unconnected-(JP1314-1-PadP$3)") (class "Default")
      (node (ref "JP1314") (pin "P$3") (pinfunction "1_P$3") (pintype "passive"))
    )
    (net (code "1015") (name "unconnected-(JP1315-1-PadP$3)") (class "Default")
      (node (ref "JP1315") (pin "P$3") (pinfunction "1_P$3") (pintype "passive"))
    )
    (net (code "1016") (name "unconnected-(JP1316-1-PadP$3)") (class "Default")
      (node (ref "JP1316") (pin "P$3") (pinfunction "1_P$3") (pintype "passive"))
    )
    (net (code "1017") (name "unconnected-(JP1317-1-PadP$3)") (class "Default")
      (node (ref "JP1317") (pin "P$3") (pinfunction "1_P$3") (pintype "passive"))
    )
    (net (code "1018") (name "unconnected-(JP1318-1-PadP$3)") (class "Default")
      (node (ref "JP1318") (pin "P$3") (pinfunction "1_P$3") (pintype "passive"))
    )
    (net (code "1019") (name "unconnected-(JP1319-1-PadP$3)") (class "Default")
      (node (ref "JP1319") (pin "P$3") (pinfunction "1_P$3") (pintype "passive"))
    )
    (net (code "1020") (name "unconnected-(JP1320-1-PadP$3)") (class "Default")
      (node (ref "JP1320") (pin "P$3") (pinfunction "1_P$3") (pintype "passive"))
    )
    (net (code "1021") (name "unconnected-(JP1321-1-PadP$3)") (class "Default")
      (node (ref "JP1321") (pin "P$3") (pinfunction "1_P$3") (pintype "passive"))
    )
    (net (code "1022") (name "unconnected-(JP1322-1-PadP$3)") (class "Default")
      (node (ref "JP1322") (pin "P$3") (pinfunction "1_P$3") (pintype "passive"))
    )
    (net (code "1023") (name "unconnected-(JP1323-1-PadP$3)") (class "Default")
      (node (ref "JP1323") (pin "P$3") (pinfunction "1_P$3") (pintype "passive"))
    )
    (net (code "1024") (name "unconnected-(JP1324-1-PadP$3)") (class "Default")
      (node (ref "JP1324") (pin "P$3") (pinfunction "1_P$3") (pintype "passive"))
    )
    (net (code "1025") (name "unconnected-(JP1325-1-PadP$3)") (class "Default")
      (node (ref "JP1325") (pin "P$3") (pinfunction "1_P$3") (pintype "passive"))
    )
    (net (code "1026") (name "unconnected-(JP1326-1-PadP$3)") (class "Default")
      (node (ref "JP1326") (pin "P$3") (pinfunction "1_P$3") (pintype "passive"))
    )
    (net (code "1027") (name "unconnected-(JP1327-1-PadP$3)") (class "Default")
      (node (ref "JP1327") (pin "P$3") (pinfunction "1_P$3") (pintype "passive"))
    )
    (net (code "1028") (name "unconnected-(JP1328-1-PadP$3)") (class "Default")
      (node (ref "JP1328") (pin "P$3") (pinfunction "1_P$3") (pintype "passive"))
    )
    (net (code "1029") (name "unconnected-(JP1329-1-PadP$3)") (class "Default")
      (node (ref "JP1329") (pin "P$3") (pinfunction "1_P$3") (pintype "passive"))
    )
    (net (code "1030") (name "unconnected-(JP1330-1-PadP$3)") (class "Default")
      (node (ref "JP1330") (pin "P$3") (pinfunction "1_P$3") (pintype "passive"))
    )
    (net (code "1031") (name "unconnected-(JP1331-1-PadP$3)") (class "Default")
      (node (ref "JP1331") (pin "P$3") (pinfunction "1_P$3") (pintype "passive"))
    )
    (net (code "1032") (name "unconnected-(JP1332-1-PadP$3)") (class "Default")
      (node (ref "JP1332") (pin "P$3") (pinfunction "1_P$3") (pintype "passive"))
    )
    (net (code "1033") (name "unconnected-(JP1333-1-PadP$3)") (class "Default")
      (node (ref "JP1333") (pin "P$3") (pinfunction "1_P$3") (pintype "passive"))
    )
    (net (code "1034") (name "unconnected-(JP1334-1-PadP$3)") (class "Default")
      (node (ref "JP1334") (pin "P$3") (pinfunction "1_P$3") (pintype "passive"))
    )
    (net (code "1035") (name "unconnected-(JP1335-1-PadP$3)") (class "Default")
      (node (ref "JP1335") (pin "P$3") (pinfunction "1_P$3") (pintype "passive"))
    )
    (net (code "1036") (name "unconnected-(JP1336-1-PadP$3)") (class "Default")
      (node (ref "JP1336") (pin "P$3") (pinfunction "1_P$3") (pintype "passive"))
    )
    (net (code "1037") (name "unconnected-(JP1337-1-PadP$3)") (class "Default")
      (node (ref "JP1337") (pin "P$3") (pinfunction "1_P$3") (pintype "passive"))
    )
    (net (code "1038") (name "unconnected-(JP1338-1-PadP$3)") (class "Default")
      (node (ref "JP1338") (pin "P$3") (pinfunction "1_P$3") (pintype "passive"))
    )
    (net (code "1039") (name "unconnected-(JP1339-1-PadP$3)") (class "Default")
      (node (ref "JP1339") (pin "P$3") (pinfunction "1_P$3") (pintype "passive"))
    )
    (net (code "1040") (name "unconnected-(JP1340-1-PadP$3)") (class "Default")
      (node (ref "JP1340") (pin "P$3") (pinfunction "1_P$3") (pintype "passive"))
    )
    (net (code "1041") (name "unconnected-(JP1341-1-PadP$3)") (class "Default")
      (node (ref "JP1341") (pin "P$3") (pinfunction "1_P$3") (pintype "passive"))
    )
    (net (code "1042") (name "unconnected-(JP1342-1-PadP$3)") (class "Default")
      (node (ref "JP1342") (pin "P$3") (pinfunction "1_P$3") (pintype "passive"))
    )
    (net (code "1043") (name "unconnected-(JP1343-1-PadP$3)") (class "Default")
      (node (ref "JP1343") (pin "P$3") (pinfunction "1_P$3") (pintype "passive"))
    )
    (net (code "1044") (name "unconnected-(JP1344-1-PadP$3)") (class "Default")
      (node (ref "JP1344") (pin "P$3") (pinfunction "1_P$3") (pintype "passive"))
    )
    (net (code "1045") (name "unconnected-(JP1345-1-PadP$3)") (class "Default")
      (node (ref "JP1345") (pin "P$3") (pinfunction "1_P$3") (pintype "passive"))
    )
    (net (code "1046") (name "unconnected-(JP1346-1-PadP$3)") (class "Default")
      (node (ref "JP1346") (pin "P$3") (pinfunction "1_P$3") (pintype "passive"))
    )
    (net (code "1047") (name "unconnected-(JP1347-1-PadP$3)") (class "Default")
      (node (ref "JP1347") (pin "P$3") (pinfunction "1_P$3") (pintype "passive"))
    )
    (net (code "1048") (name "unconnected-(JP1348-1-PadP$3)") (class "Default")
      (node (ref "JP1348") (pin "P$3") (pinfunction "1_P$3") (pintype "passive"))
    )
    (net (code "1049") (name "unconnected-(JP1349-1-PadP$3)") (class "Default")
      (node (ref "JP1349") (pin "P$3") (pinfunction "1_P$3") (pintype "passive"))
    )
    (net (code "1050") (name "unconnected-(JP1350-1-PadP$3)") (class "Default")
      (node (ref "JP1350") (pin "P$3") (pinfunction "1_P$3") (pintype "passive"))
    )
    (net (code "1051") (name "unconnected-(JP1351-1-PadP$3)") (class "Default")
      (node (ref "JP1351") (pin "P$3") (pinfunction "1_P$3") (pintype "passive"))
    )
    (net (code "1052") (name "unconnected-(JP1352-1-PadP$3)") (class "Default")
      (node (ref "JP1352") (pin "P$3") (pinfunction "1_P$3") (pintype "passive"))
    )
    (net (code "1053") (name "unconnected-(JP1353-1-PadP$3)") (class "Default")
      (node (ref "JP1353") (pin "P$3") (pinfunction "1_P$3") (pintype "passive"))
    )
    (net (code "1054") (name "unconnected-(JP1354-1-PadP$3)") (class "Default")
      (node (ref "JP1354") (pin "P$3") (pinfunction "1_P$3") (pintype "passive"))
    )
    (net (code "1055") (name "unconnected-(JP1355-1-PadP$3)") (class "Default")
      (node (ref "JP1355") (pin "P$3") (pinfunction "1_P$3") (pintype "passive"))
    )
    (net (code "1056") (name "unconnected-(JP1356-1-PadP$3)") (class "Default")
      (node (ref "JP1356") (pin "P$3") (pinfunction "1_P$3") (pintype "passive"))
    )
    (net (code "1057") (name "unconnected-(JP1357-1-PadP$3)") (class "Default")
      (node (ref "JP1357") (pin "P$3") (pinfunction "1_P$3") (pintype "passive"))
    )
    (net (code "1058") (name "unconnected-(JP1358-1-PadP$3)") (class "Default")
      (node (ref "JP1358") (pin "P$3") (pinfunction "1_P$3") (pintype "passive"))
    )
    (net (code "1059") (name "unconnected-(JP1359-1-PadP$3)") (class "Default")
      (node (ref "JP1359") (pin "P$3") (pinfunction "1_P$3") (pintype "passive"))
    )
    (net (code "1060") (name "unconnected-(JP1360-1-PadP$3)") (class "Default")
      (node (ref "JP1360") (pin "P$3") (pinfunction "1_P$3") (pintype "passive"))
    )
    (net (code "1061") (name "unconnected-(JP1361-1-PadP$3)") (class "Default")
      (node (ref "JP1361") (pin "P$3") (pinfunction "1_P$3") (pintype "passive"))
    )
    (net (code "1062") (name "unconnected-(JP1362-1-PadP$3)") (class "Default")
      (node (ref "JP1362") (pin "P$3") (pinfunction "1_P$3") (pintype "passive"))
    )
    (net (code "1063") (name "unconnected-(JP1363-1-PadP$3)") (class "Default")
      (node (ref "JP1363") (pin "P$3") (pinfunction "1_P$3") (pintype "passive"))
    )
    (net (code "1064") (name "unconnected-(JP1364-1-PadP$3)") (class "Default")
      (node (ref "JP1364") (pin "P$3") (pinfunction "1_P$3") (pintype "passive"))
    )
    (net (code "1065") (name "unconnected-(JP1365-1-PadP$3)") (class "Default")
      (node (ref "JP1365") (pin "P$3") (pinfunction "1_P$3") (pintype "passive"))
    )
    (net (code "1066") (name "unconnected-(JP1366-1-PadP$3)") (class "Default")
      (node (ref "JP1366") (pin "P$3") (pinfunction "1_P$3") (pintype "passive"))
    )
    (net (code "1067") (name "unconnected-(JP1367-1-PadP$3)") (class "Default")
      (node (ref "JP1367") (pin "P$3") (pinfunction "1_P$3") (pintype "passive"))
    )
    (net (code "1068") (name "unconnected-(JP1368-1-PadP$3)") (class "Default")
      (node (ref "JP1368") (pin "P$3") (pinfunction "1_P$3") (pintype "passive"))
    )
    (net (code "1069") (name "unconnected-(JP1369-1-PadP$3)") (class "Default")
      (node (ref "JP1369") (pin "P$3") (pinfunction "1_P$3") (pintype "passive"))
    )
    (net (code "1070") (name "unconnected-(JP1370-1-PadP$3)") (class "Default")
      (node (ref "JP1370") (pin "P$3") (pinfunction "1_P$3") (pintype "passive"))
    )
    (net (code "1071") (name "unconnected-(JP1371-1-PadP$3)") (class "Default")
      (node (ref "JP1371") (pin "P$3") (pinfunction "1_P$3") (pintype "passive"))
    )
    (net (code "1072") (name "unconnected-(JP1372-1-PadP$3)") (class "Default")
      (node (ref "JP1372") (pin "P$3") (pinfunction "1_P$3") (pintype "passive"))
    )
    (net (code "1073") (name "unconnected-(JP1373-1-PadP$3)") (class "Default")
      (node (ref "JP1373") (pin "P$3") (pinfunction "1_P$3") (pintype "passive"))
    )
    (net (code "1074") (name "unconnected-(JP1374-1-PadP$3)") (class "Default")
      (node (ref "JP1374") (pin "P$3") (pinfunction "1_P$3") (pintype "passive"))
    )
    (net (code "1075") (name "unconnected-(JP1375-1-PadP$3)") (class "Default")
      (node (ref "JP1375") (pin "P$3") (pinfunction "1_P$3") (pintype "passive"))
    )
    (net (code "1076") (name "unconnected-(JP1376-1-PadP$3)") (class "Default")
      (node (ref "JP1376") (pin "P$3") (pinfunction "1_P$3") (pintype "passive"))
    )
    (net (code "1077") (name "unconnected-(JP1377-1-PadP$3)") (class "Default")
      (node (ref "JP1377") (pin "P$3") (pinfunction "1_P$3") (pintype "passive"))
    )
    (net (code "1078") (name "unconnected-(JP1378-1-PadP$3)") (class "Default")
      (node (ref "JP1378") (pin "P$3") (pinfunction "1_P$3") (pintype "passive"))
    )
    (net (code "1079") (name "unconnected-(JP1379-1-PadP$3)") (class "Default")
      (node (ref "JP1379") (pin "P$3") (pinfunction "1_P$3") (pintype "passive"))
    )
    (net (code "1080") (name "unconnected-(JP1380-1-PadP$3)") (class "Default")
      (node (ref "JP1380") (pin "P$3") (pinfunction "1_P$3") (pintype "passive"))
    )
    (net (code "1081") (name "unconnected-(JP1381-1-PadP$3)") (class "Default")
      (node (ref "JP1381") (pin "P$3") (pinfunction "1_P$3") (pintype "passive"))
    )
    (net (code "1082") (name "unconnected-(JP1382-1-PadP$3)") (class "Default")
      (node (ref "JP1382") (pin "P$3") (pinfunction "1_P$3") (pintype "passive"))
    )
    (net (code "1083") (name "unconnected-(JP1383-1-PadP$3)") (class "Default")
      (node (ref "JP1383") (pin "P$3") (pinfunction "1_P$3") (pintype "passive"))
    )
    (net (code "1084") (name "unconnected-(JP1384-1-PadP$3)") (class "Default")
      (node (ref "JP1384") (pin "P$3") (pinfunction "1_P$3") (pintype "passive"))
    )
    (net (code "1085") (name "unconnected-(JP1385-1-PadP$3)") (class "Default")
      (node (ref "JP1385") (pin "P$3") (pinfunction "1_P$3") (pintype "passive"))
    )
    (net (code "1086") (name "unconnected-(JP1386-1-PadP$3)") (class "Default")
      (node (ref "JP1386") (pin "P$3") (pinfunction "1_P$3") (pintype "passive"))
    )
    (net (code "1087") (name "unconnected-(JP1387-1-PadP$3)") (class "Default")
      (node (ref "JP1387") (pin "P$3") (pinfunction "1_P$3") (pintype "passive"))
    )
    (net (code "1088") (name "unconnected-(JP1388-1-PadP$3)") (class "Default")
      (node (ref "JP1388") (pin "P$3") (pinfunction "1_P$3") (pintype "passive"))
    )
    (net (code "1089") (name "unconnected-(JP1389-1-PadP$3)") (class "Default")
      (node (ref "JP1389") (pin "P$3") (pinfunction "1_P$3") (pintype "passive"))
    )
    (net (code "1090") (name "unconnected-(JP1390-1-PadP$3)") (class "Default")
      (node (ref "JP1390") (pin "P$3") (pinfunction "1_P$3") (pintype "passive"))
    )
    (net (code "1091") (name "unconnected-(JP1391-1-PadP$3)") (class "Default")
      (node (ref "JP1391") (pin "P$3") (pinfunction "1_P$3") (pintype "passive"))
    )
    (net (code "1092") (name "unconnected-(JP1392-1-PadP$3)") (class "Default")
      (node (ref "JP1392") (pin "P$3") (pinfunction "1_P$3") (pintype "passive"))
    )
    (net (code "1093") (name "unconnected-(JP1393-1-PadP$3)") (class "Default")
      (node (ref "JP1393") (pin "P$3") (pinfunction "1_P$3") (pintype "passive"))
    )
    (net (code "1094") (name "unconnected-(JP1394-1-PadP$3)") (class "Default")
      (node (ref "JP1394") (pin "P$3") (pinfunction "1_P$3") (pintype "passive"))
    )
    (net (code "1095") (name "unconnected-(JP1395-1-PadP$3)") (class "Default")
      (node (ref "JP1395") (pin "P$3") (pinfunction "1_P$3") (pintype "passive"))
    )
    (net (code "1096") (name "unconnected-(JP1396-1-PadP$3)") (class "Default")
      (node (ref "JP1396") (pin "P$3") (pinfunction "1_P$3") (pintype "passive"))
    )
    (net (code "1097") (name "unconnected-(JP1397-1-PadP$3)") (class "Default")
      (node (ref "JP1397") (pin "P$3") (pinfunction "1_P$3") (pintype "passive"))
    )
    (net (code "1098") (name "unconnected-(JP1398-1-PadP$3)") (class "Default")
      (node (ref "JP1398") (pin "P$3") (pinfunction "1_P$3") (pintype "passive"))
    )
    (net (code "1099") (name "unconnected-(JP1399-1-PadP$3)") (class "Default")
      (node (ref "JP1399") (pin "P$3") (pinfunction "1_P$3") (pintype "passive"))
    )
    (net (code "1100") (name "unconnected-(JP1400-1-PadP$3)") (class "Default")
      (node (ref "JP1400") (pin "P$3") (pinfunction "1_P$3") (pintype "passive"))
    )
    (net (code "1101") (name "unconnected-(JP1401-1-PadP$3)") (class "Default")
      (node (ref "JP1401") (pin "P$3") (pinfunction "1_P$3") (pintype "passive"))
    )
    (net (code "1102") (name "unconnected-(JP1402-1-PadP$3)") (class "Default")
      (node (ref "JP1402") (pin "P$3") (pinfunction "1_P$3") (pintype "passive"))
    )
    (net (code "1103") (name "unconnected-(JP1403-1-PadP$3)") (class "Default")
      (node (ref "JP1403") (pin "P$3") (pinfunction "1_P$3") (pintype "passive"))
    )
    (net (code "1104") (name "unconnected-(JP1404-1-PadP$3)") (class "Default")
      (node (ref "JP1404") (pin "P$3") (pinfunction "1_P$3") (pintype "passive"))
    )
    (net (code "1105") (name "unconnected-(JP1405-1-PadP$3)") (class "Default")
      (node (ref "JP1405") (pin "P$3") (pinfunction "1_P$3") (pintype "passive"))
    )
    (net (code "1106") (name "unconnected-(JP1406-1-PadP$3)") (class "Default")
      (node (ref "JP1406") (pin "P$3") (pinfunction "1_P$3") (pintype "passive"))
    )
    (net (code "1107") (name "unconnected-(JP1407-1-PadP$3)") (class "Default")
      (node (ref "JP1407") (pin "P$3") (pinfunction "1_P$3") (pintype "passive"))
    )
    (net (code "1108") (name "unconnected-(JP1408-1-PadP$3)") (class "Default")
      (node (ref "JP1408") (pin "P$3") (pinfunction "1_P$3") (pintype "passive"))
    )
    (net (code "1109") (name "unconnected-(JP1409-1-PadP$3)") (class "Default")
      (node (ref "JP1409") (pin "P$3") (pinfunction "1_P$3") (pintype "passive"))
    )
    (net (code "1110") (name "unconnected-(JP1410-1-PadP$3)") (class "Default")
      (node (ref "JP1410") (pin "P$3") (pinfunction "1_P$3") (pintype "passive"))
    )
    (net (code "1111") (name "unconnected-(JP1411-1-PadP$3)") (class "Default")
      (node (ref "JP1411") (pin "P$3") (pinfunction "1_P$3") (pintype "passive"))
    )
    (net (code "1112") (name "unconnected-(JP1412-1-PadP$3)") (class "Default")
      (node (ref "JP1412") (pin "P$3") (pinfunction "1_P$3") (pintype "passive"))
    )
    (net (code "1113") (name "unconnected-(JP1413-1-PadP$3)") (class "Default")
      (node (ref "JP1413") (pin "P$3") (pinfunction "1_P$3") (pintype "passive"))
    )
    (net (code "1114") (name "unconnected-(JP1414-1-PadP$3)") (class "Default")
      (node (ref "JP1414") (pin "P$3") (pinfunction "1_P$3") (pintype "passive"))
    )
    (net (code "1115") (name "unconnected-(JP1415-1-PadP$3)") (class "Default")
      (node (ref "JP1415") (pin "P$3") (pinfunction "1_P$3") (pintype "passive"))
    )
    (net (code "1116") (name "unconnected-(JP1416-1-PadP$3)") (class "Default")
      (node (ref "JP1416") (pin "P$3") (pinfunction "1_P$3") (pintype "passive"))
    )
    (net (code "1117") (name "unconnected-(JP1417-1-PadP$3)") (class "Default")
      (node (ref "JP1417") (pin "P$3") (pinfunction "1_P$3") (pintype "passive"))
    )
    (net (code "1118") (name "unconnected-(JP1418-1-PadP$3)") (class "Default")
      (node (ref "JP1418") (pin "P$3") (pinfunction "1_P$3") (pintype "passive"))
    )
    (net (code "1119") (name "unconnected-(JP1419-1-PadP$3)") (class "Default")
      (node (ref "JP1419") (pin "P$3") (pinfunction "1_P$3") (pintype "passive"))
    )
    (net (code "1120") (name "unconnected-(JP1420-1-PadP$3)") (class "Default")
      (node (ref "JP1420") (pin "P$3") (pinfunction "1_P$3") (pintype "passive"))
    )
    (net (code "1121") (name "unconnected-(JP1421-1-PadP$3)") (class "Default")
      (node (ref "JP1421") (pin "P$3") (pinfunction "1_P$3") (pintype "passive"))
    )
    (net (code "1122") (name "unconnected-(JP1422-1-PadP$3)") (class "Default")
      (node (ref "JP1422") (pin "P$3") (pinfunction "1_P$3") (pintype "passive"))
    )
    (net (code "1123") (name "unconnected-(JP1423-1-PadP$3)") (class "Default")
      (node (ref "JP1423") (pin "P$3") (pinfunction "1_P$3") (pintype "passive"))
    )
    (net (code "1124") (name "unconnected-(JP1424-1-PadP$3)") (class "Default")
      (node (ref "JP1424") (pin "P$3") (pinfunction "1_P$3") (pintype "passive"))
    )
    (net (code "1125") (name "unconnected-(JP1425-1-PadP$3)") (class "Default")
      (node (ref "JP1425") (pin "P$3") (pinfunction "1_P$3") (pintype "passive"))
    )
    (net (code "1126") (name "unconnected-(JP1426-1-PadP$3)") (class "Default")
      (node (ref "JP1426") (pin "P$3") (pinfunction "1_P$3") (pintype "passive"))
    )
    (net (code "1127") (name "unconnected-(JP1427-1-PadP$3)") (class "Default")
      (node (ref "JP1427") (pin "P$3") (pinfunction "1_P$3") (pintype "passive"))
    )
    (net (code "1128") (name "unconnected-(JP1428-1-PadP$3)") (class "Default")
      (node (ref "JP1428") (pin "P$3") (pinfunction "1_P$3") (pintype "passive"))
    )
    (net (code "1129") (name "unconnected-(JP1429-1-PadP$3)") (class "Default")
      (node (ref "JP1429") (pin "P$3") (pinfunction "1_P$3") (pintype "passive"))
    )
    (net (code "1130") (name "unconnected-(JP1430-1-PadP$3)") (class "Default")
      (node (ref "JP1430") (pin "P$3") (pinfunction "1_P$3") (pintype "passive"))
    )
    (net (code "1131") (name "unconnected-(JP1431-1-PadP$3)") (class "Default")
      (node (ref "JP1431") (pin "P$3") (pinfunction "1_P$3") (pintype "passive"))
    )
    (net (code "1132") (name "unconnected-(JP1432-1-PadP$3)") (class "Default")
      (node (ref "JP1432") (pin "P$3") (pinfunction "1_P$3") (pintype "passive"))
    )
    (net (code "1133") (name "unconnected-(JP1433-1-PadP$3)") (class "Default")
      (node (ref "JP1433") (pin "P$3") (pinfunction "1_P$3") (pintype "passive"))
    )
    (net (code "1134") (name "unconnected-(JP1434-1-PadP$3)") (class "Default")
      (node (ref "JP1434") (pin "P$3") (pinfunction "1_P$3") (pintype "passive"))
    )
    (net (code "1135") (name "unconnected-(JP1435-1-PadP$3)") (class "Default")
      (node (ref "JP1435") (pin "P$3") (pinfunction "1_P$3") (pintype "passive"))
    )
    (net (code "1136") (name "unconnected-(JP1436-1-PadP$3)") (class "Default")
      (node (ref "JP1436") (pin "P$3") (pinfunction "1_P$3") (pintype "passive"))
    )
    (net (code "1137") (name "unconnected-(JP1437-1-PadP$3)") (class "Default")
      (node (ref "JP1437") (pin "P$3") (pinfunction "1_P$3") (pintype "passive"))
    )
    (net (code "1138") (name "unconnected-(JP1438-1-PadP$3)") (class "Default")
      (node (ref "JP1438") (pin "P$3") (pinfunction "1_P$3") (pintype "passive"))
    )
    (net (code "1139") (name "unconnected-(JP1439-1-PadP$3)") (class "Default")
      (node (ref "JP1439") (pin "P$3") (pinfunction "1_P$3") (pintype "passive"))
    )
    (net (code "1140") (name "unconnected-(JP1440-1-PadP$3)") (class "Default")
      (node (ref "JP1440") (pin "P$3") (pinfunction "1_P$3") (pintype "passive"))
    )
    (net (code "1141") (name "unconnected-(JP1441-1-PadP$3)") (class "Default")
      (node (ref "JP1441") (pin "P$3") (pinfunction "1_P$3") (pintype "passive"))
    )
    (net (code "1142") (name "unconnected-(JP1442-1-PadP$3)") (class "Default")
      (node (ref "JP1442") (pin "P$3") (pinfunction "1_P$3") (pintype "passive"))
    )
    (net (code "1143") (name "unconnected-(JP1443-1-PadP$3)") (class "Default")
      (node (ref "JP1443") (pin "P$3") (pinfunction "1_P$3") (pintype "passive"))
    )
    (net (code "1144") (name "unconnected-(JP1444-1-PadP$3)") (class "Default")
      (node (ref "JP1444") (pin "P$3") (pinfunction "1_P$3") (pintype "passive"))
    )
    (net (code "1145") (name "unconnected-(JP1445-1-PadP$3)") (class "Default")
      (node (ref "JP1445") (pin "P$3") (pinfunction "1_P$3") (pintype "passive"))
    )
    (net (code "1146") (name "unconnected-(JP1446-1-PadP$3)") (class "Default")
      (node (ref "JP1446") (pin "P$3") (pinfunction "1_P$3") (pintype "passive"))
    )
    (net (code "1147") (name "unconnected-(JP1447-1-PadP$3)") (class "Default")
      (node (ref "JP1447") (pin "P$3") (pinfunction "1_P$3") (pintype "passive"))
    )
    (net (code "1148") (name "unconnected-(JP1448-1-PadP$3)") (class "Default")
      (node (ref "JP1448") (pin "P$3") (pinfunction "1_P$3") (pintype "passive"))
    )
    (net (code "1149") (name "unconnected-(JP1449-1-PadP$3)") (class "Default")
      (node (ref "JP1449") (pin "P$3") (pinfunction "1_P$3") (pintype "passive"))
    )
    (net (code "1150") (name "unconnected-(JP1450-1-PadP$3)") (class "Default")
      (node (ref "JP1450") (pin "P$3") (pinfunction "1_P$3") (pintype "passive"))
    )
    (net (code "1151") (name "unconnected-(JP1451-1-PadP$3)") (class "Default")
      (node (ref "JP1451") (pin "P$3") (pinfunction "1_P$3") (pintype "passive"))
    )
    (net (code "1152") (name "unconnected-(JP1452-1-PadP$3)") (class "Default")
      (node (ref "JP1452") (pin "P$3") (pinfunction "1_P$3") (pintype "passive"))
    )
    (net (code "1153") (name "unconnected-(JP1453-1-PadP$3)") (class "Default")
      (node (ref "JP1453") (pin "P$3") (pinfunction "1_P$3") (pintype "passive"))
    )
    (net (code "1154") (name "unconnected-(JP1454-1-PadP$3)") (class "Default")
      (node (ref "JP1454") (pin "P$3") (pinfunction "1_P$3") (pintype "passive"))
    )
    (net (code "1155") (name "unconnected-(JP1455-1-PadP$3)") (class "Default")
      (node (ref "JP1455") (pin "P$3") (pinfunction "1_P$3") (pintype "passive"))
    )
    (net (code "1156") (name "unconnected-(JP1456-1-PadP$3)") (class "Default")
      (node (ref "JP1456") (pin "P$3") (pinfunction "1_P$3") (pintype "passive"))
    )
    (net (code "1157") (name "unconnected-(JP1457-1-PadP$3)") (class "Default")
      (node (ref "JP1457") (pin "P$3") (pinfunction "1_P$3") (pintype "passive"))
    )
    (net (code "1158") (name "unconnected-(JP1458-1-PadP$3)") (class "Default")
      (node (ref "JP1458") (pin "P$3") (pinfunction "1_P$3") (pintype "passive"))
    )
    (net (code "1159") (name "unconnected-(JP1459-1-PadP$3)") (class "Default")
      (node (ref "JP1459") (pin "P$3") (pinfunction "1_P$3") (pintype "passive"))
    )
    (net (code "1160") (name "unconnected-(JP1460-1-PadP$3)") (class "Default")
      (node (ref "JP1460") (pin "P$3") (pinfunction "1_P$3") (pintype "passive"))
    )
    (net (code "1161") (name "unconnected-(JP1461-1-PadP$3)") (class "Default")
      (node (ref "JP1461") (pin "P$3") (pinfunction "1_P$3") (pintype "passive"))
    )
    (net (code "1162") (name "unconnected-(JP1462-1-PadP$3)") (class "Default")
      (node (ref "JP1462") (pin "P$3") (pinfunction "1_P$3") (pintype "passive"))
    )
    (net (code "1163") (name "unconnected-(JP1463-1-PadP$3)") (class "Default")
      (node (ref "JP1463") (pin "P$3") (pinfunction "1_P$3") (pintype "passive"))
    )
    (net (code "1164") (name "unconnected-(JP1464-1-PadP$3)") (class "Default")
      (node (ref "JP1464") (pin "P$3") (pinfunction "1_P$3") (pintype "passive"))
    )
    (net (code "1165") (name "unconnected-(JP1465-1-PadP$3)") (class "Default")
      (node (ref "JP1465") (pin "P$3") (pinfunction "1_P$3") (pintype "passive"))
    )
    (net (code "1166") (name "unconnected-(JP1466-1-PadP$3)") (class "Default")
      (node (ref "JP1466") (pin "P$3") (pinfunction "1_P$3") (pintype "passive"))
    )
    (net (code "1167") (name "unconnected-(JP1467-1-PadP$3)") (class "Default")
      (node (ref "JP1467") (pin "P$3") (pinfunction "1_P$3") (pintype "passive"))
    )
    (net (code "1168") (name "unconnected-(JP1468-1-PadP$3)") (class "Default")
      (node (ref "JP1468") (pin "P$3") (pinfunction "1_P$3") (pintype "passive"))
    )
    (net (code "1169") (name "unconnected-(JP1469-1-PadP$3)") (class "Default")
      (node (ref "JP1469") (pin "P$3") (pinfunction "1_P$3") (pintype "passive"))
    )
    (net (code "1170") (name "unconnected-(JP1470-1-PadP$3)") (class "Default")
      (node (ref "JP1470") (pin "P$3") (pinfunction "1_P$3") (pintype "passive"))
    )
    (net (code "1171") (name "unconnected-(JP1471-1-PadP$3)") (class "Default")
      (node (ref "JP1471") (pin "P$3") (pinfunction "1_P$3") (pintype "passive"))
    )
    (net (code "1172") (name "unconnected-(JP1472-1-PadP$3)") (class "Default")
      (node (ref "JP1472") (pin "P$3") (pinfunction "1_P$3") (pintype "passive"))
    )
    (net (code "1173") (name "unconnected-(JP1473-1-PadP$3)") (class "Default")
      (node (ref "JP1473") (pin "P$3") (pinfunction "1_P$3") (pintype "passive"))
    )
    (net (code "1174") (name "unconnected-(JP1474-1-PadP$3)") (class "Default")
      (node (ref "JP1474") (pin "P$3") (pinfunction "1_P$3") (pintype "passive"))
    )
    (net (code "1175") (name "unconnected-(JP1475-1-PadP$3)") (class "Default")
      (node (ref "JP1475") (pin "P$3") (pinfunction "1_P$3") (pintype "passive"))
    )
    (net (code "1176") (name "unconnected-(JP1476-1-PadP$3)") (class "Default")
      (node (ref "JP1476") (pin "P$3") (pinfunction "1_P$3") (pintype "passive"))
    )
    (net (code "1177") (name "unconnected-(JP1477-1-PadP$3)") (class "Default")
      (node (ref "JP1477") (pin "P$3") (pinfunction "1_P$3") (pintype "passive"))
    )
    (net (code "1178") (name "unconnected-(JP1478-1-PadP$3)") (class "Default")
      (node (ref "JP1478") (pin "P$3") (pinfunction "1_P$3") (pintype "passive"))
    )
    (net (code "1179") (name "unconnected-(JP1479-1-PadP$3)") (class "Default")
      (node (ref "JP1479") (pin "P$3") (pinfunction "1_P$3") (pintype "passive"))
    )
    (net (code "1180") (name "unconnected-(JP1480-1-PadP$3)") (class "Default")
      (node (ref "JP1480") (pin "P$3") (pinfunction "1_P$3") (pintype "passive"))
    )
    (net (code "1181") (name "unconnected-(JP1481-1-PadP$3)") (class "Default")
      (node (ref "JP1481") (pin "P$3") (pinfunction "1_P$3") (pintype "passive"))
    )
    (net (code "1182") (name "unconnected-(JP1482-1-PadP$3)") (class "Default")
      (node (ref "JP1482") (pin "P$3") (pinfunction "1_P$3") (pintype "passive"))
    )
    (net (code "1183") (name "unconnected-(JP1483-1-PadP$3)") (class "Default")
      (node (ref "JP1483") (pin "P$3") (pinfunction "1_P$3") (pintype "passive"))
    )
    (net (code "1184") (name "unconnected-(JP1484-1-PadP$3)") (class "Default")
      (node (ref "JP1484") (pin "P$3") (pinfunction "1_P$3") (pintype "passive"))
    )
    (net (code "1185") (name "unconnected-(JP1485-1-PadP$3)") (class "Default")
      (node (ref "JP1485") (pin "P$3") (pinfunction "1_P$3") (pintype "passive"))
    )
    (net (code "1186") (name "unconnected-(JP1486-1-PadP$3)") (class "Default")
      (node (ref "JP1486") (pin "P$3") (pinfunction "1_P$3") (pintype "passive"))
    )
    (net (code "1187") (name "unconnected-(JP1487-1-PadP$3)") (class "Default")
      (node (ref "JP1487") (pin "P$3") (pinfunction "1_P$3") (pintype "passive"))
    )
    (net (code "1188") (name "unconnected-(JP1488-1-PadP$3)") (class "Default")
      (node (ref "JP1488") (pin "P$3") (pinfunction "1_P$3") (pintype "passive"))
    )
    (net (code "1189") (name "unconnected-(JP1489-1-PadP$3)") (class "Default")
      (node (ref "JP1489") (pin "P$3") (pinfunction "1_P$3") (pintype "passive"))
    )
    (net (code "1190") (name "unconnected-(JP1490-1-PadP$3)") (class "Default")
      (node (ref "JP1490") (pin "P$3") (pinfunction "1_P$3") (pintype "passive"))
    )
    (net (code "1191") (name "unconnected-(JP1491-1-PadP$3)") (class "Default")
      (node (ref "JP1491") (pin "P$3") (pinfunction "1_P$3") (pintype "passive"))
    )
    (net (code "1192") (name "unconnected-(JP1492-1-PadP$3)") (class "Default")
      (node (ref "JP1492") (pin "P$3") (pinfunction "1_P$3") (pintype "passive"))
    )
    (net (code "1193") (name "unconnected-(JP1493-1-PadP$3)") (class "Default")
      (node (ref "JP1493") (pin "P$3") (pinfunction "1_P$3") (pintype "passive"))
    )
    (net (code "1194") (name "unconnected-(JP1494-1-PadP$3)") (class "Default")
      (node (ref "JP1494") (pin "P$3") (pinfunction "1_P$3") (pintype "passive"))
    )
    (net (code "1195") (name "unconnected-(JP1495-1-PadP$3)") (class "Default")
      (node (ref "JP1495") (pin "P$3") (pinfunction "1_P$3") (pintype "passive"))
    )
    (net (code "1196") (name "unconnected-(JP1496-1-PadP$3)") (class "Default")
      (node (ref "JP1496") (pin "P$3") (pinfunction "1_P$3") (pintype "passive"))
    )
    (net (code "1197") (name "unconnected-(JP1497-1-PadP$3)") (class "Default")
      (node (ref "JP1497") (pin "P$3") (pinfunction "1_P$3") (pintype "passive"))
    )
    (net (code "1198") (name "unconnected-(JP1498-1-PadP$3)") (class "Default")
      (node (ref "JP1498") (pin "P$3") (pinfunction "1_P$3") (pintype "passive"))
    )
    (net (code "1199") (name "unconnected-(JP1499-1-PadP$3)") (class "Default")
      (node (ref "JP1499") (pin "P$3") (pinfunction "1_P$3") (pintype "passive"))
    )
    (net (code "1200") (name "unconnected-(JP1500-1-PadP$3)") (class "Default")
      (node (ref "JP1500") (pin "P$3") (pinfunction "1_P$3") (pintype "passive"))
    )
  )
)
